# P1.net
KiCad netlist of a schematic drawn in Altium Designer
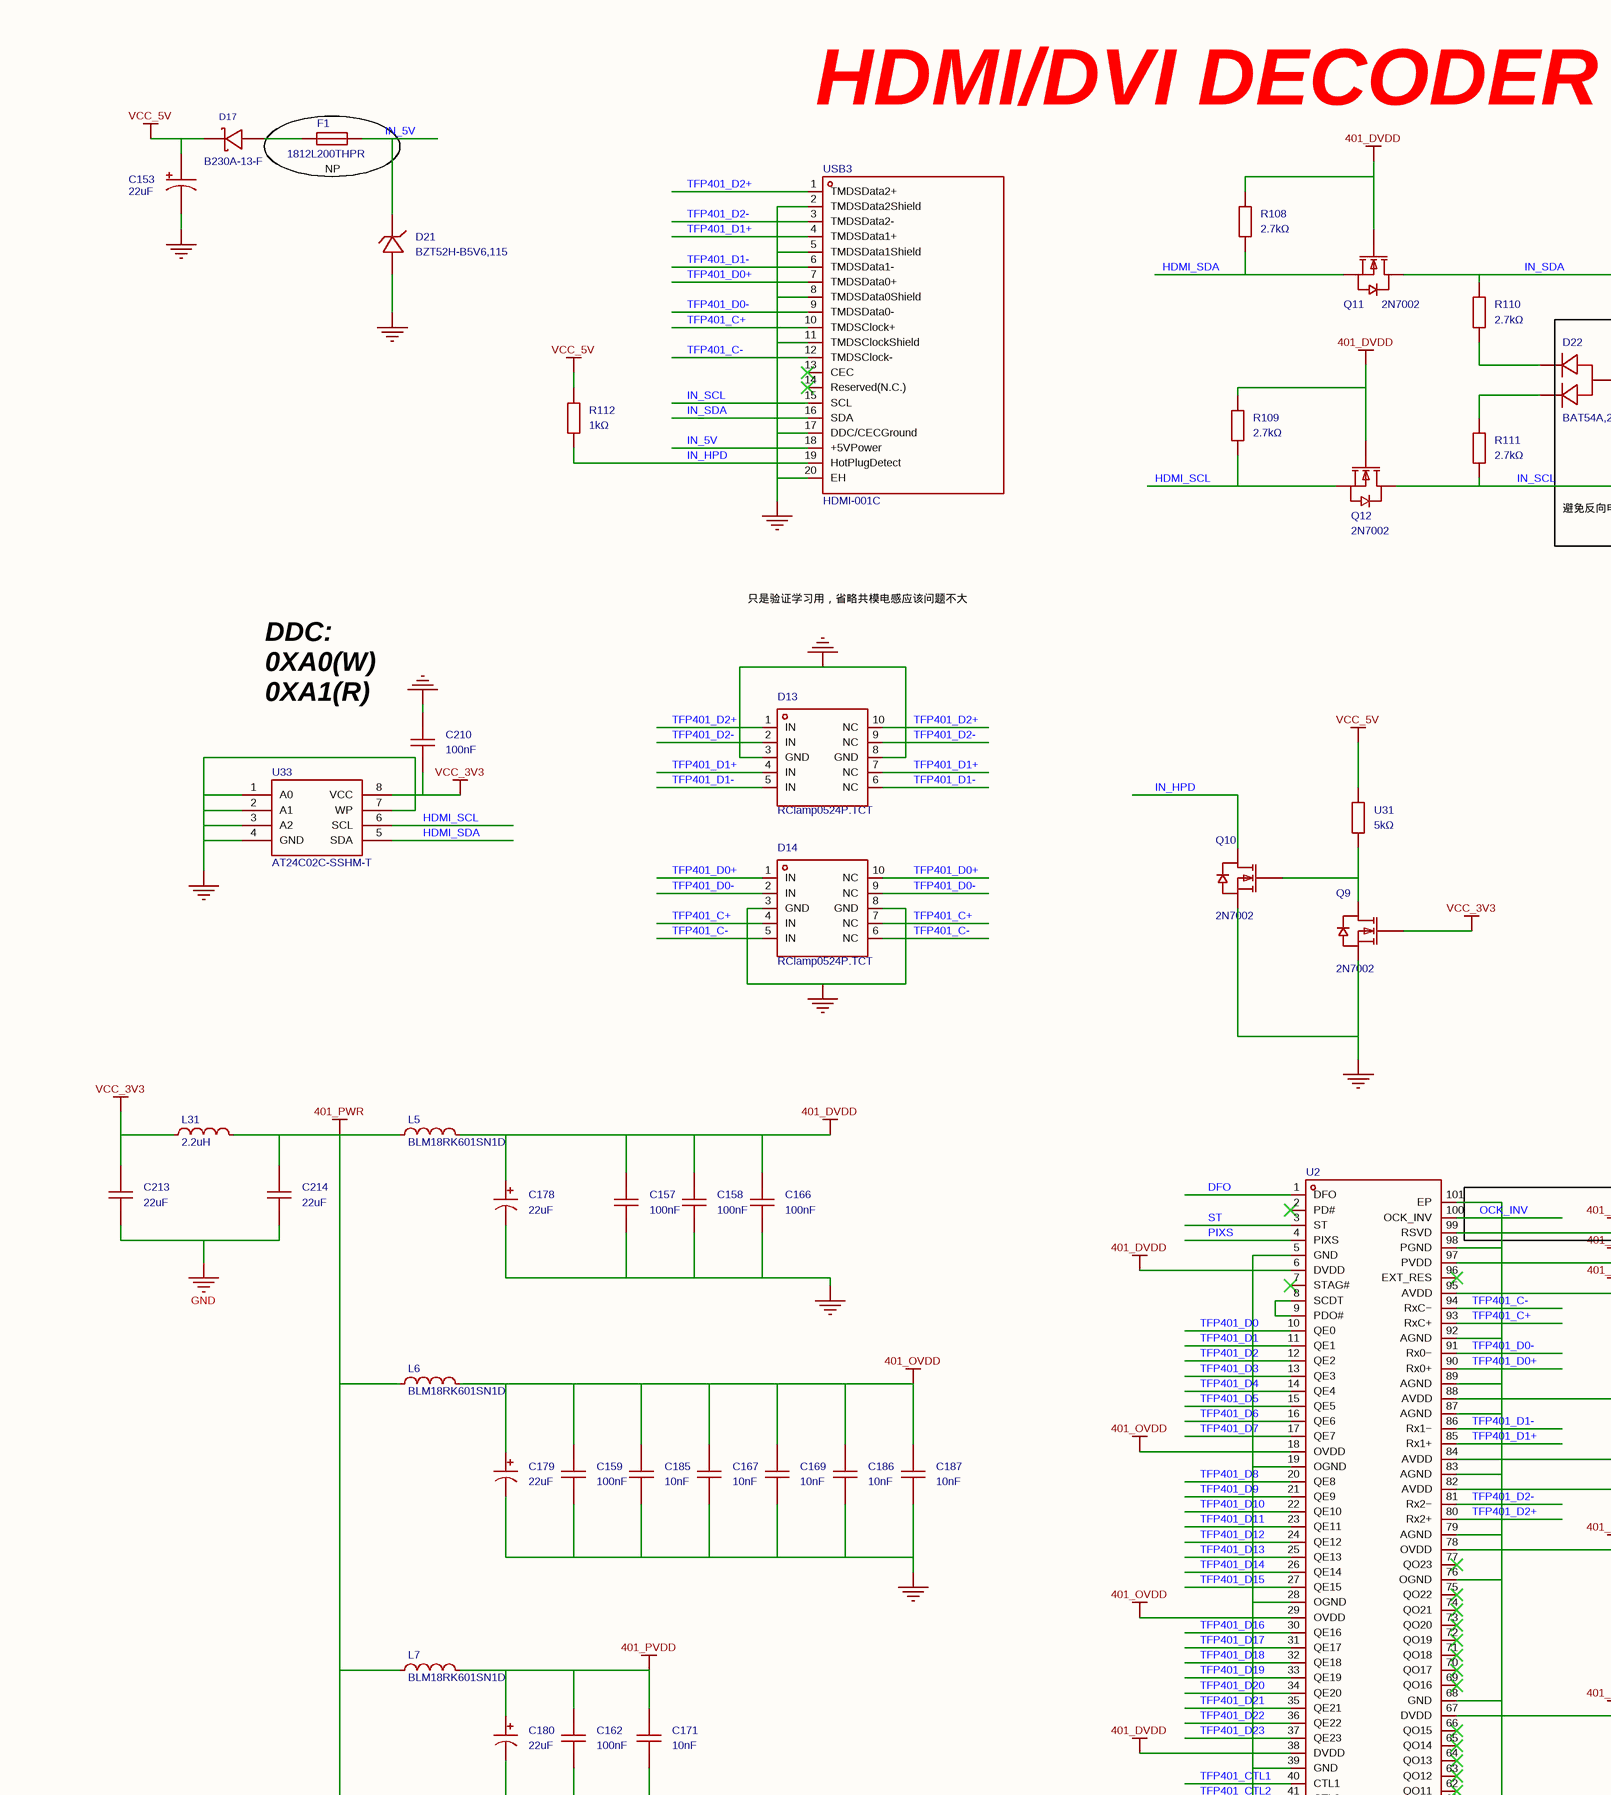
[diagram p0: P1.schdoc, top column 1 of 4]
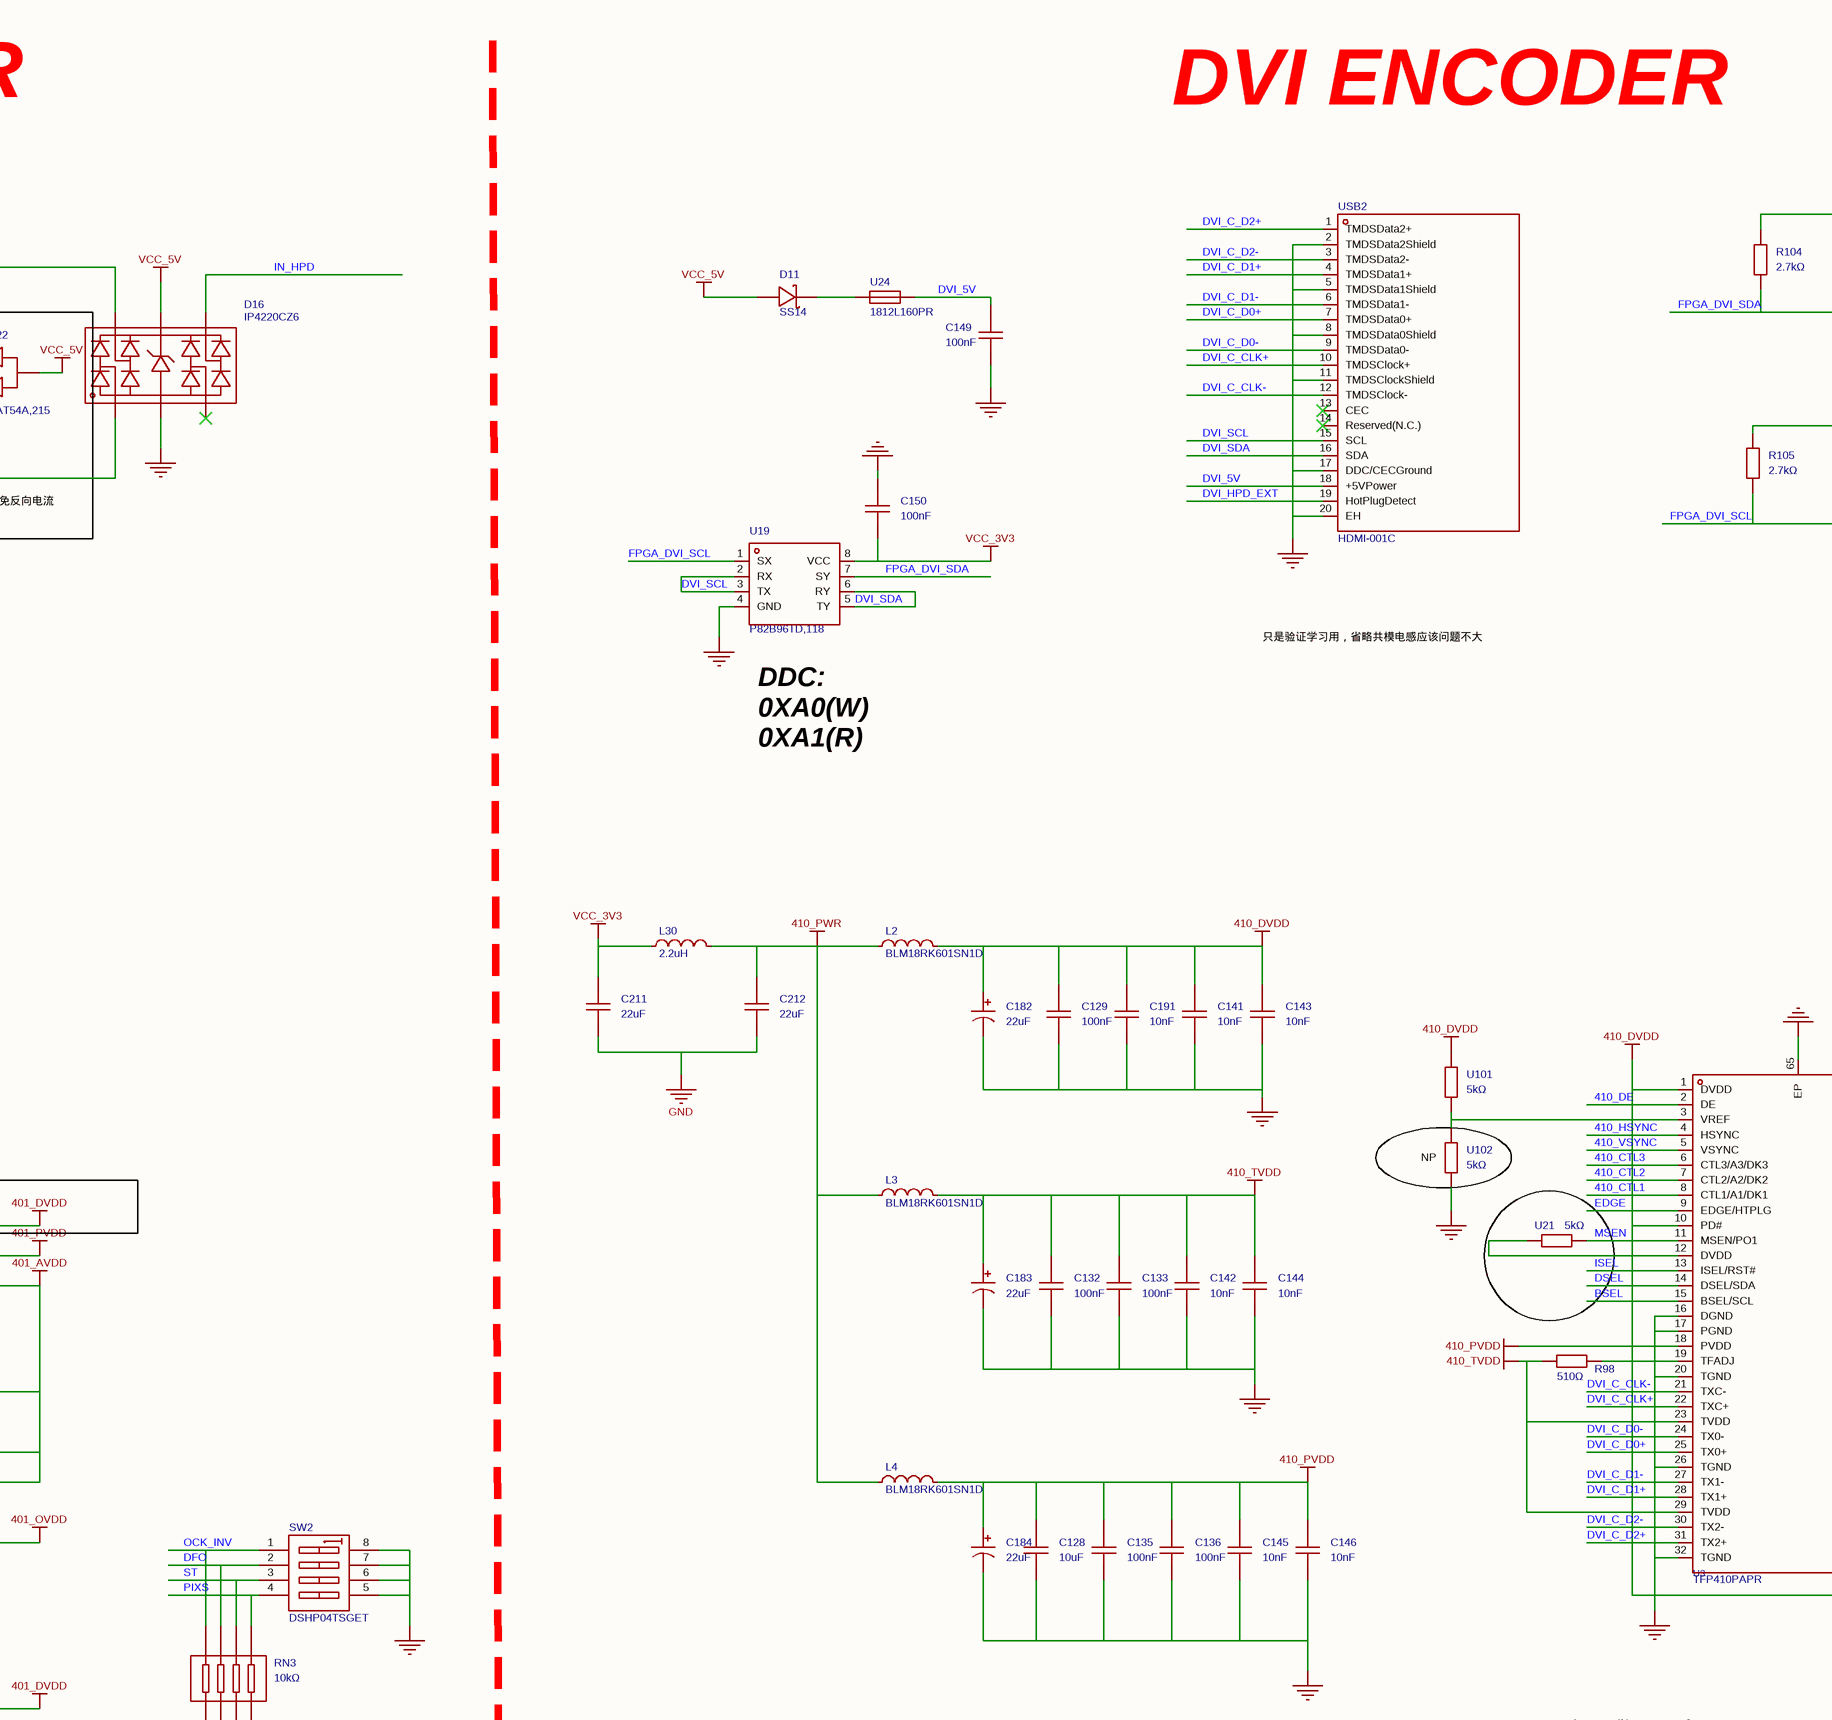
[diagram p1: P1.schdoc, top column 2 of 4]
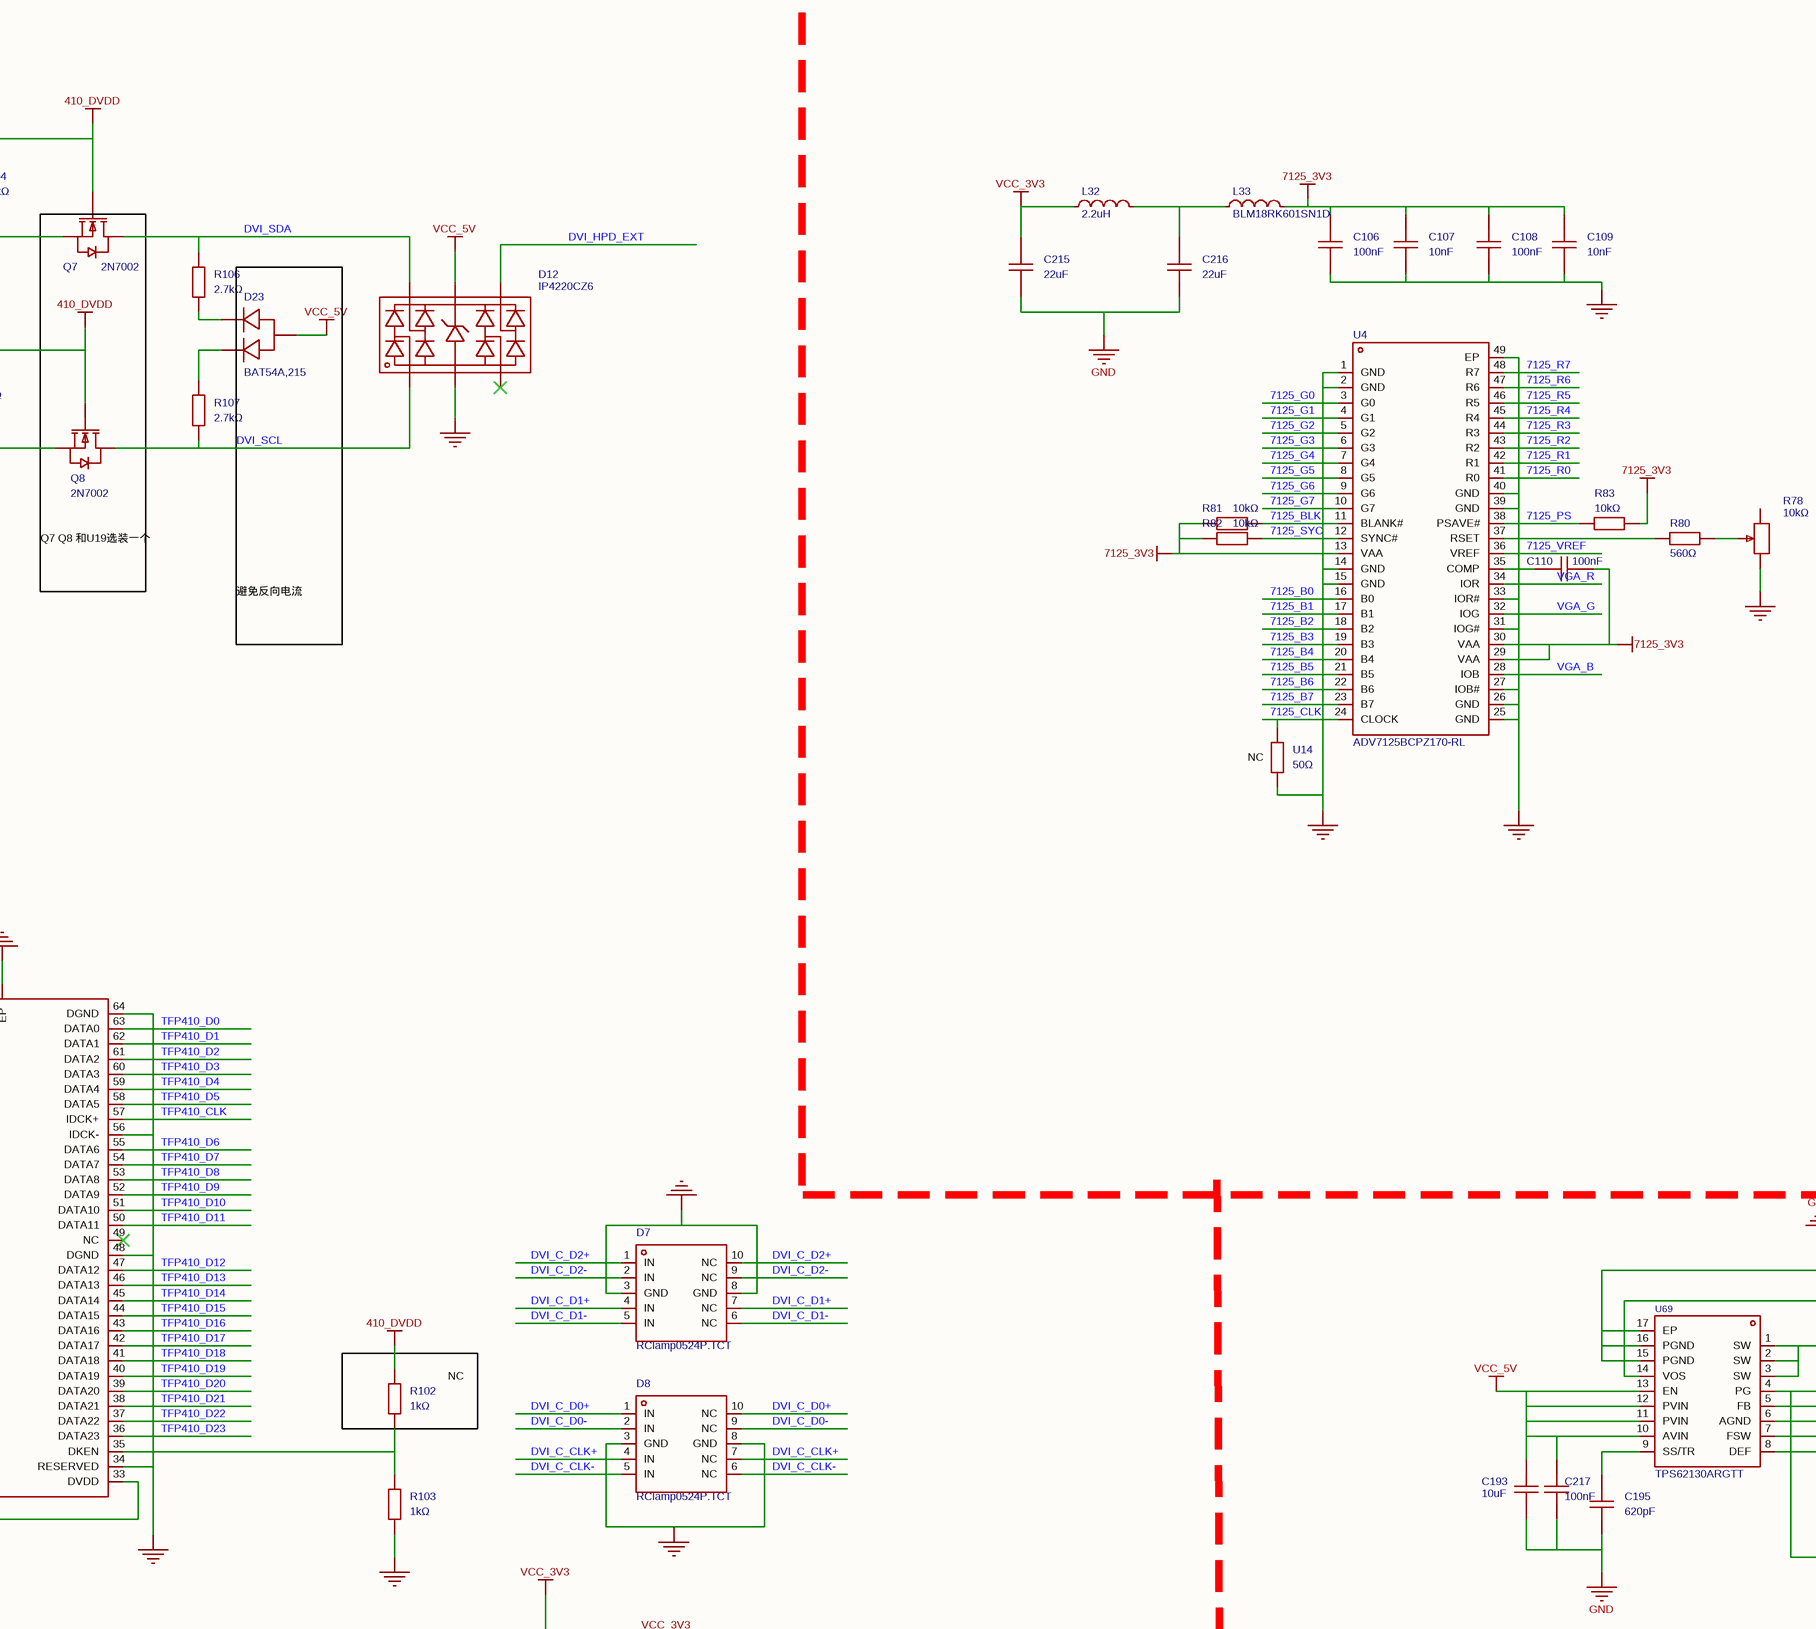
[diagram p2: P1.schdoc, top column 3 of 4]
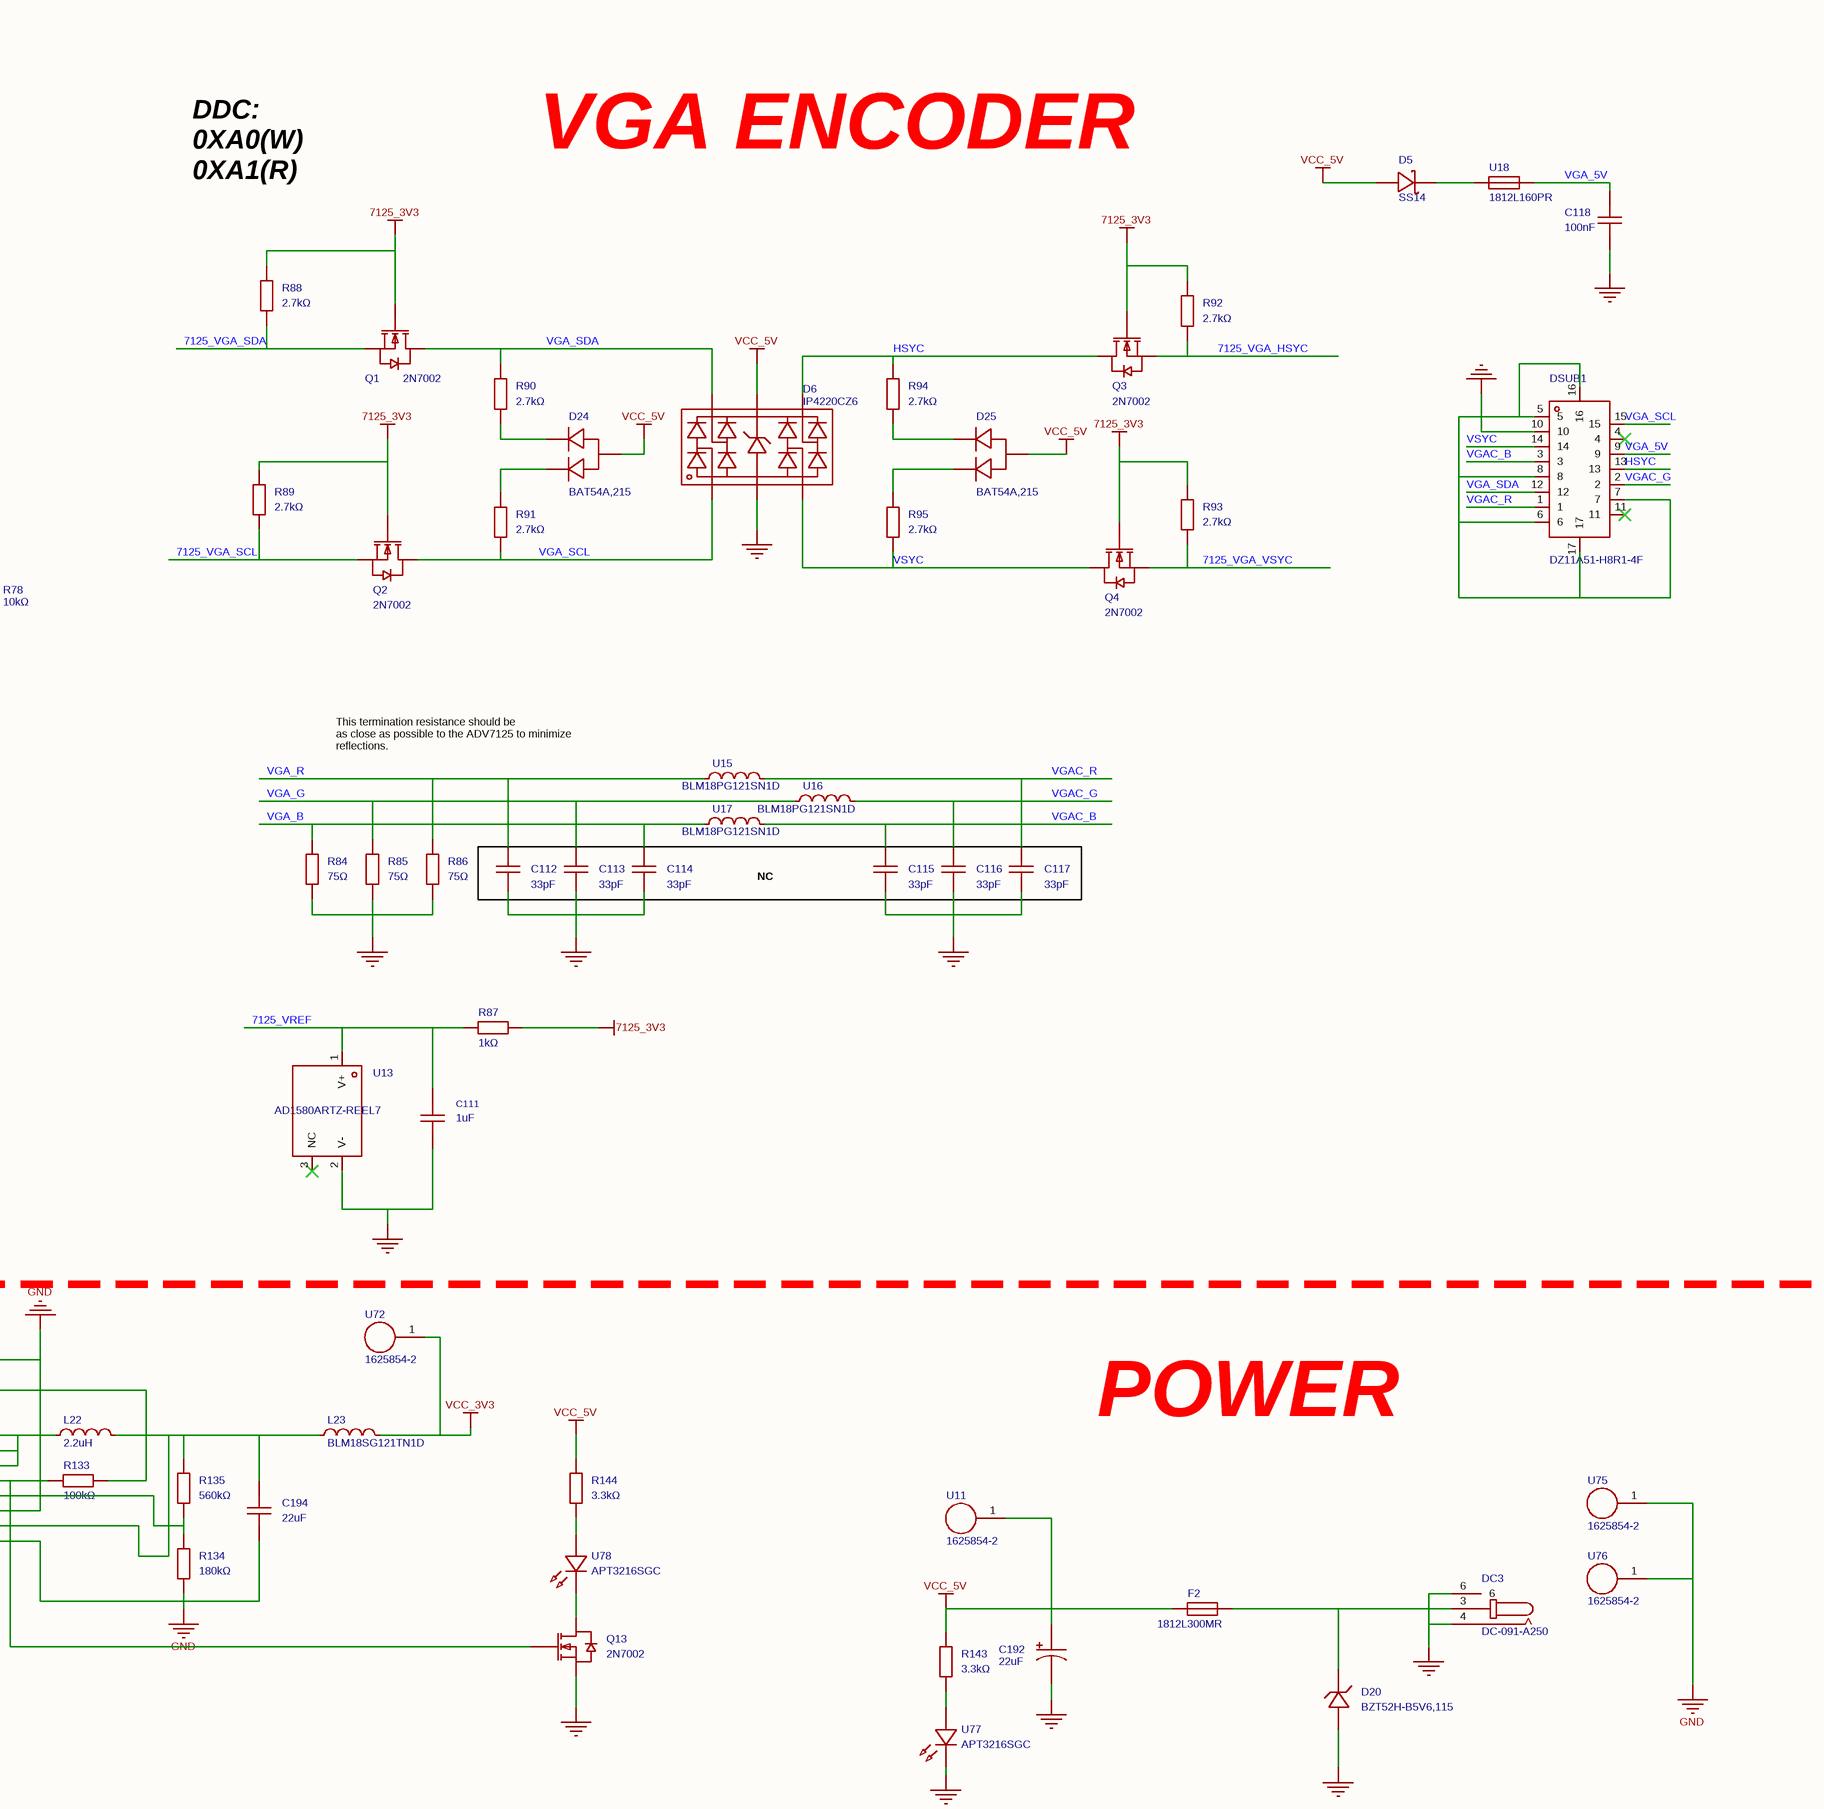
[diagram p3: P1.schdoc, top column 4 of 4]
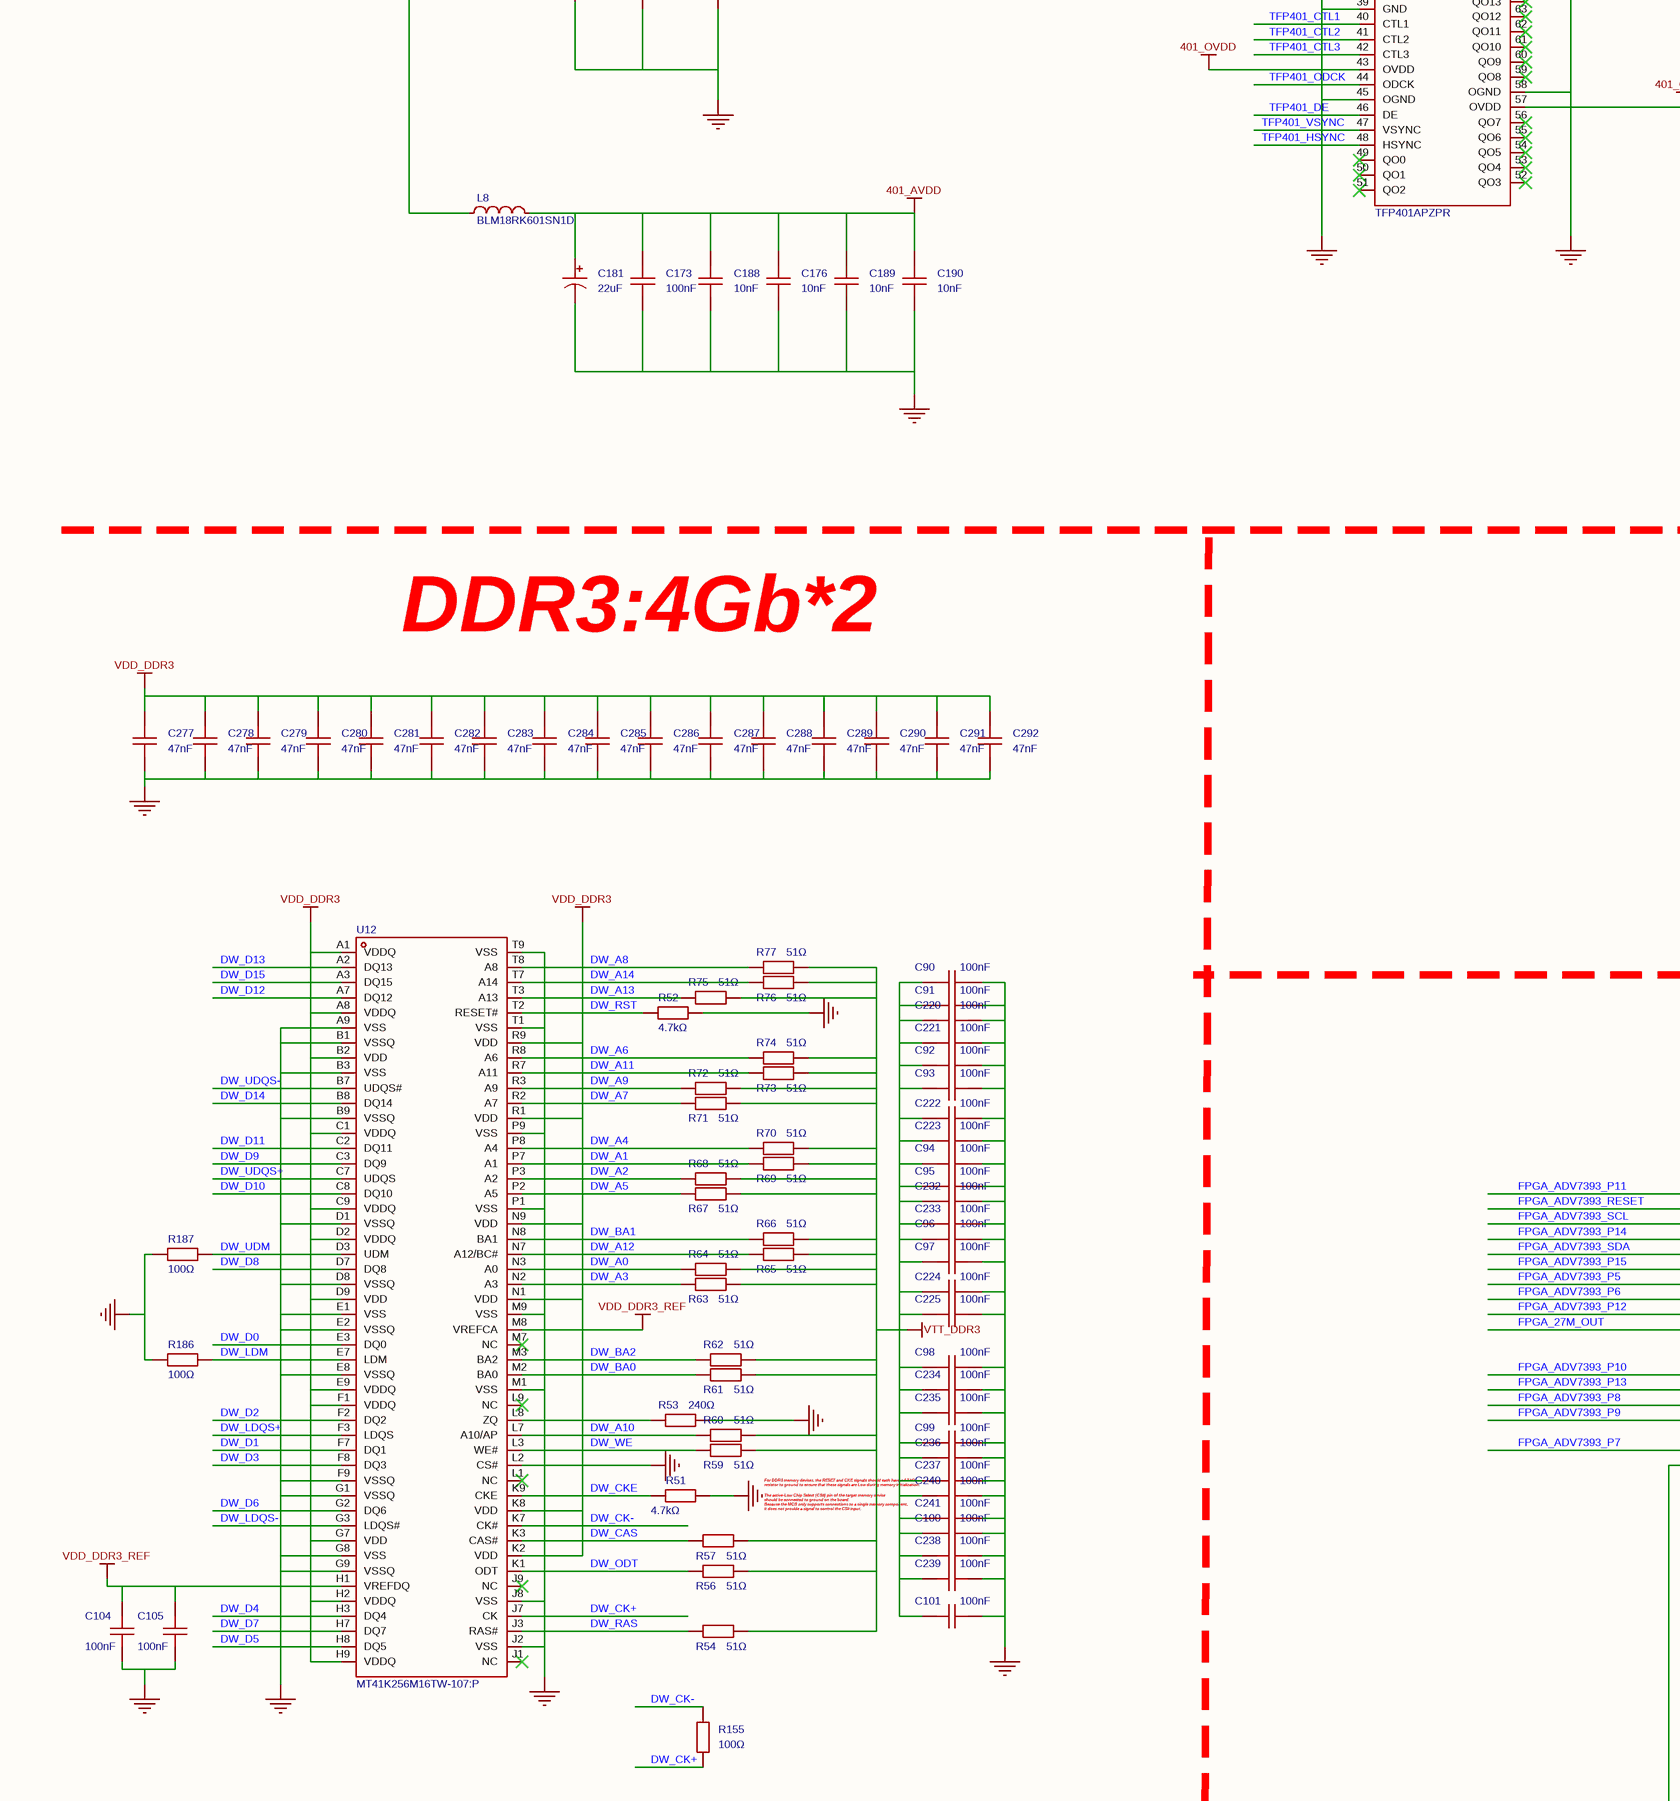
[diagram p4: P1.schdoc, centre column 1 of 4]
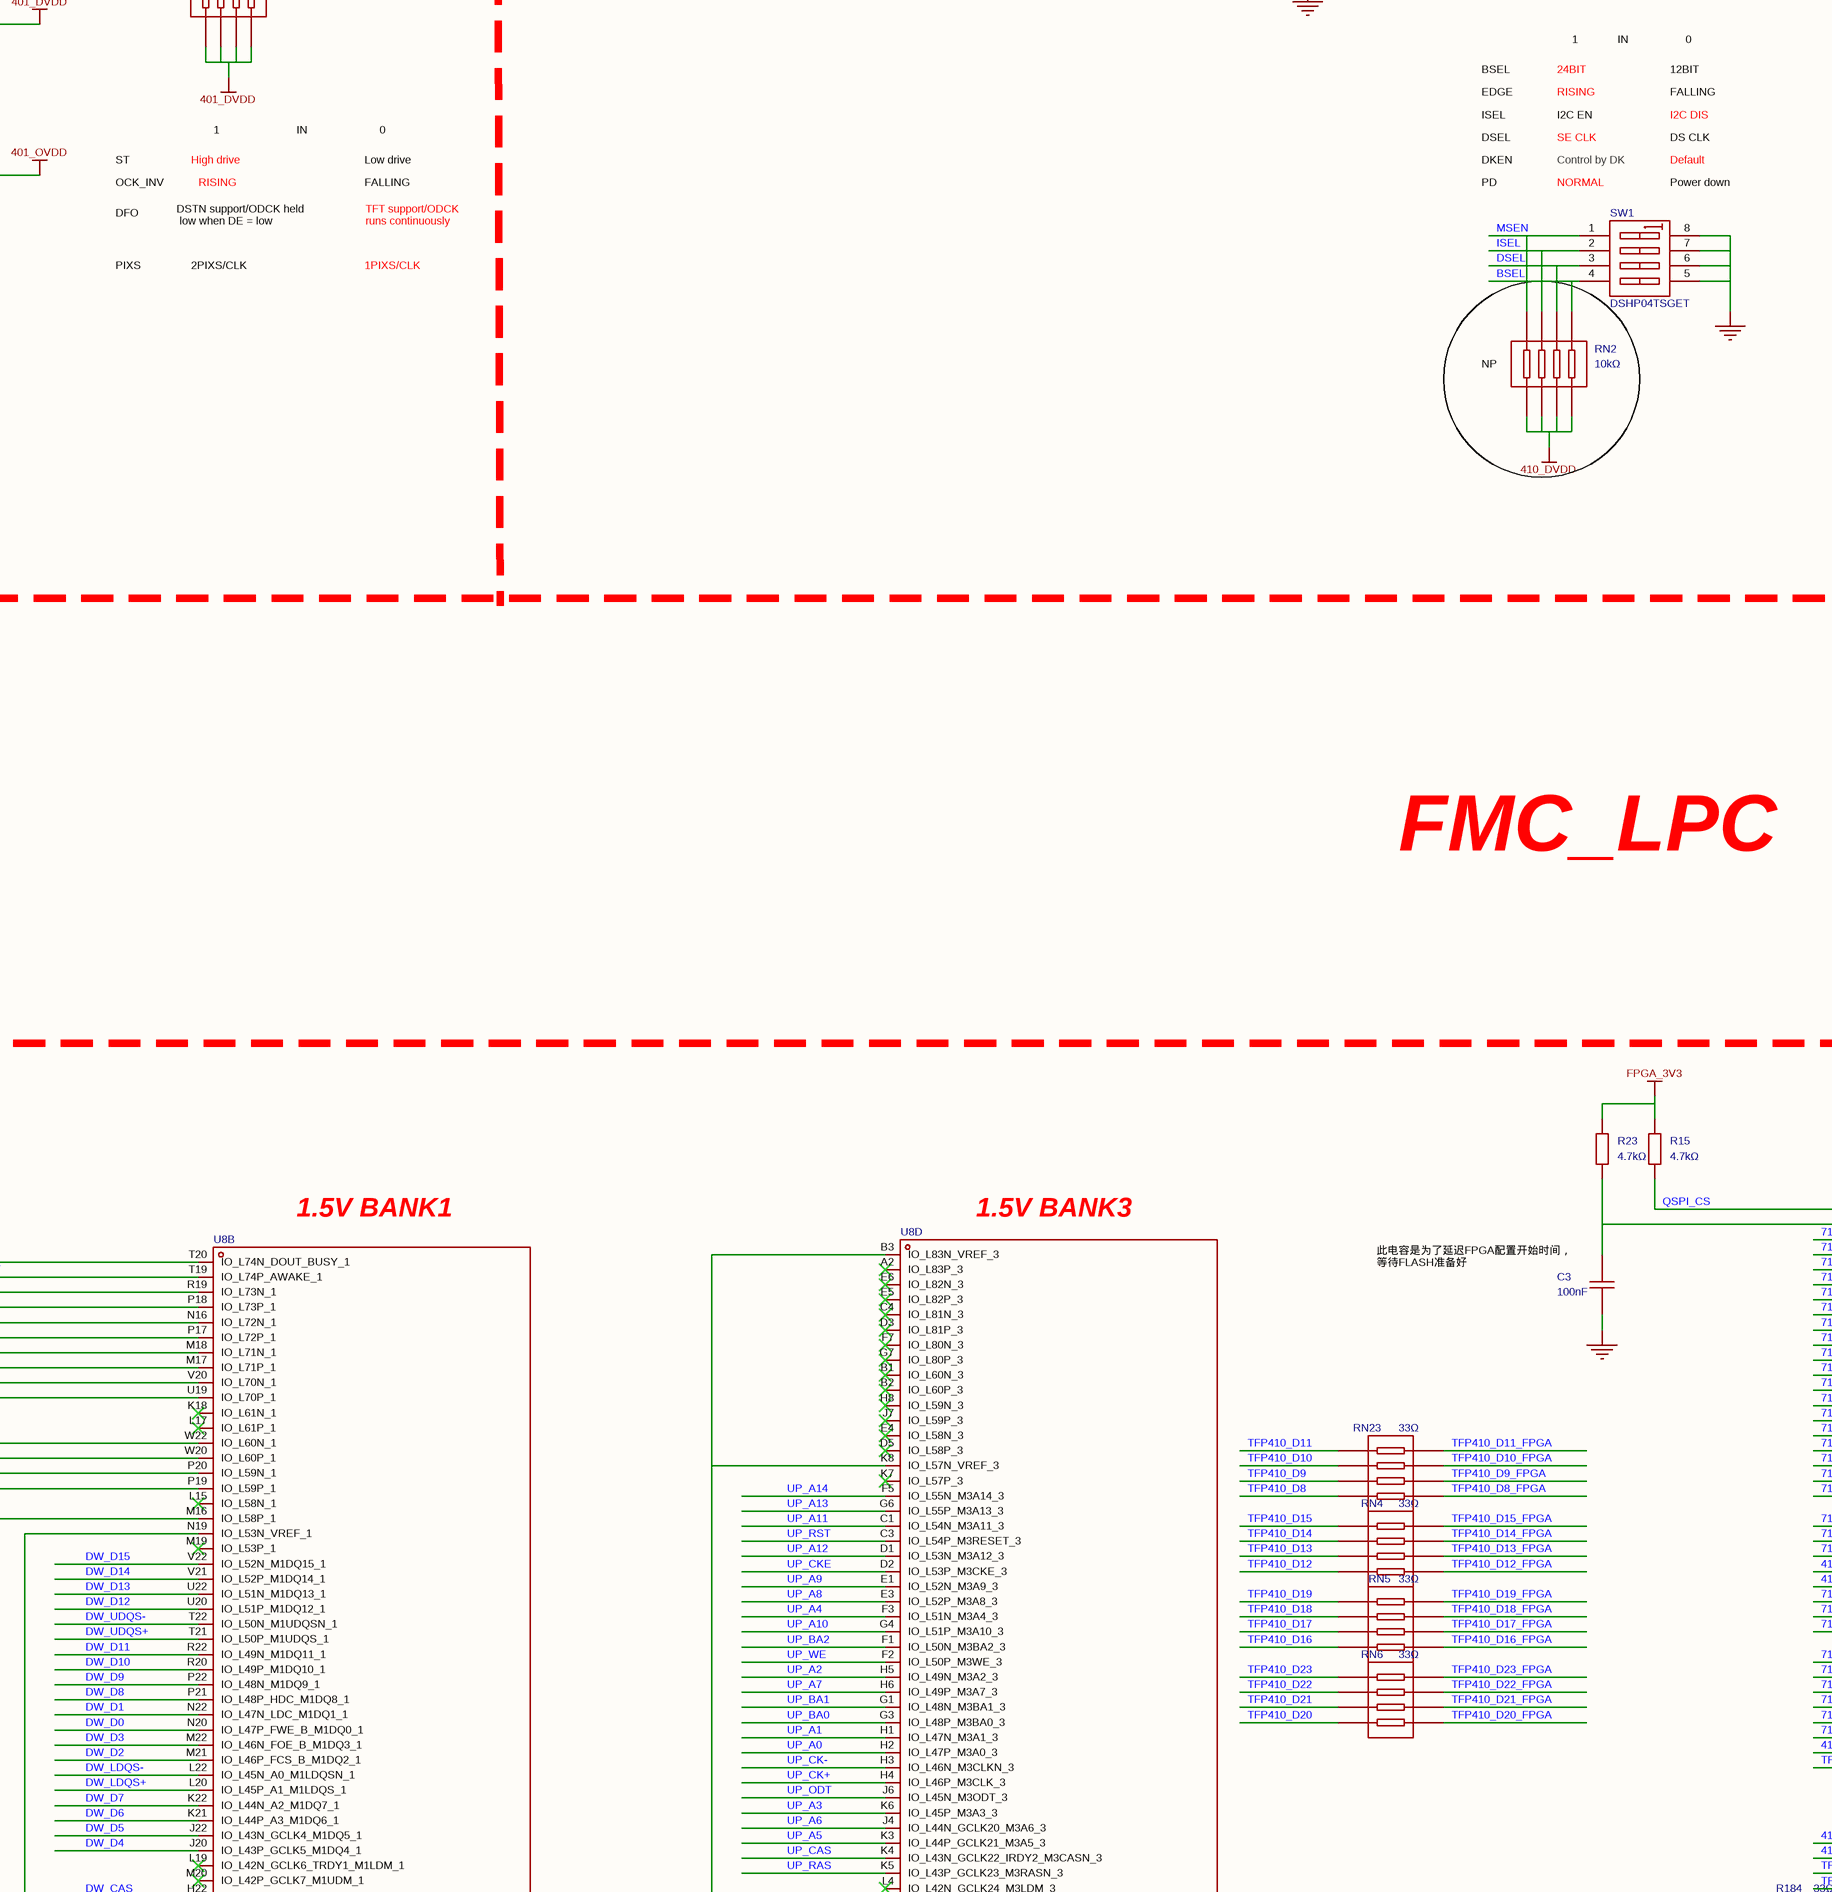
[diagram p5: P1.schdoc, centre column 2 of 4]
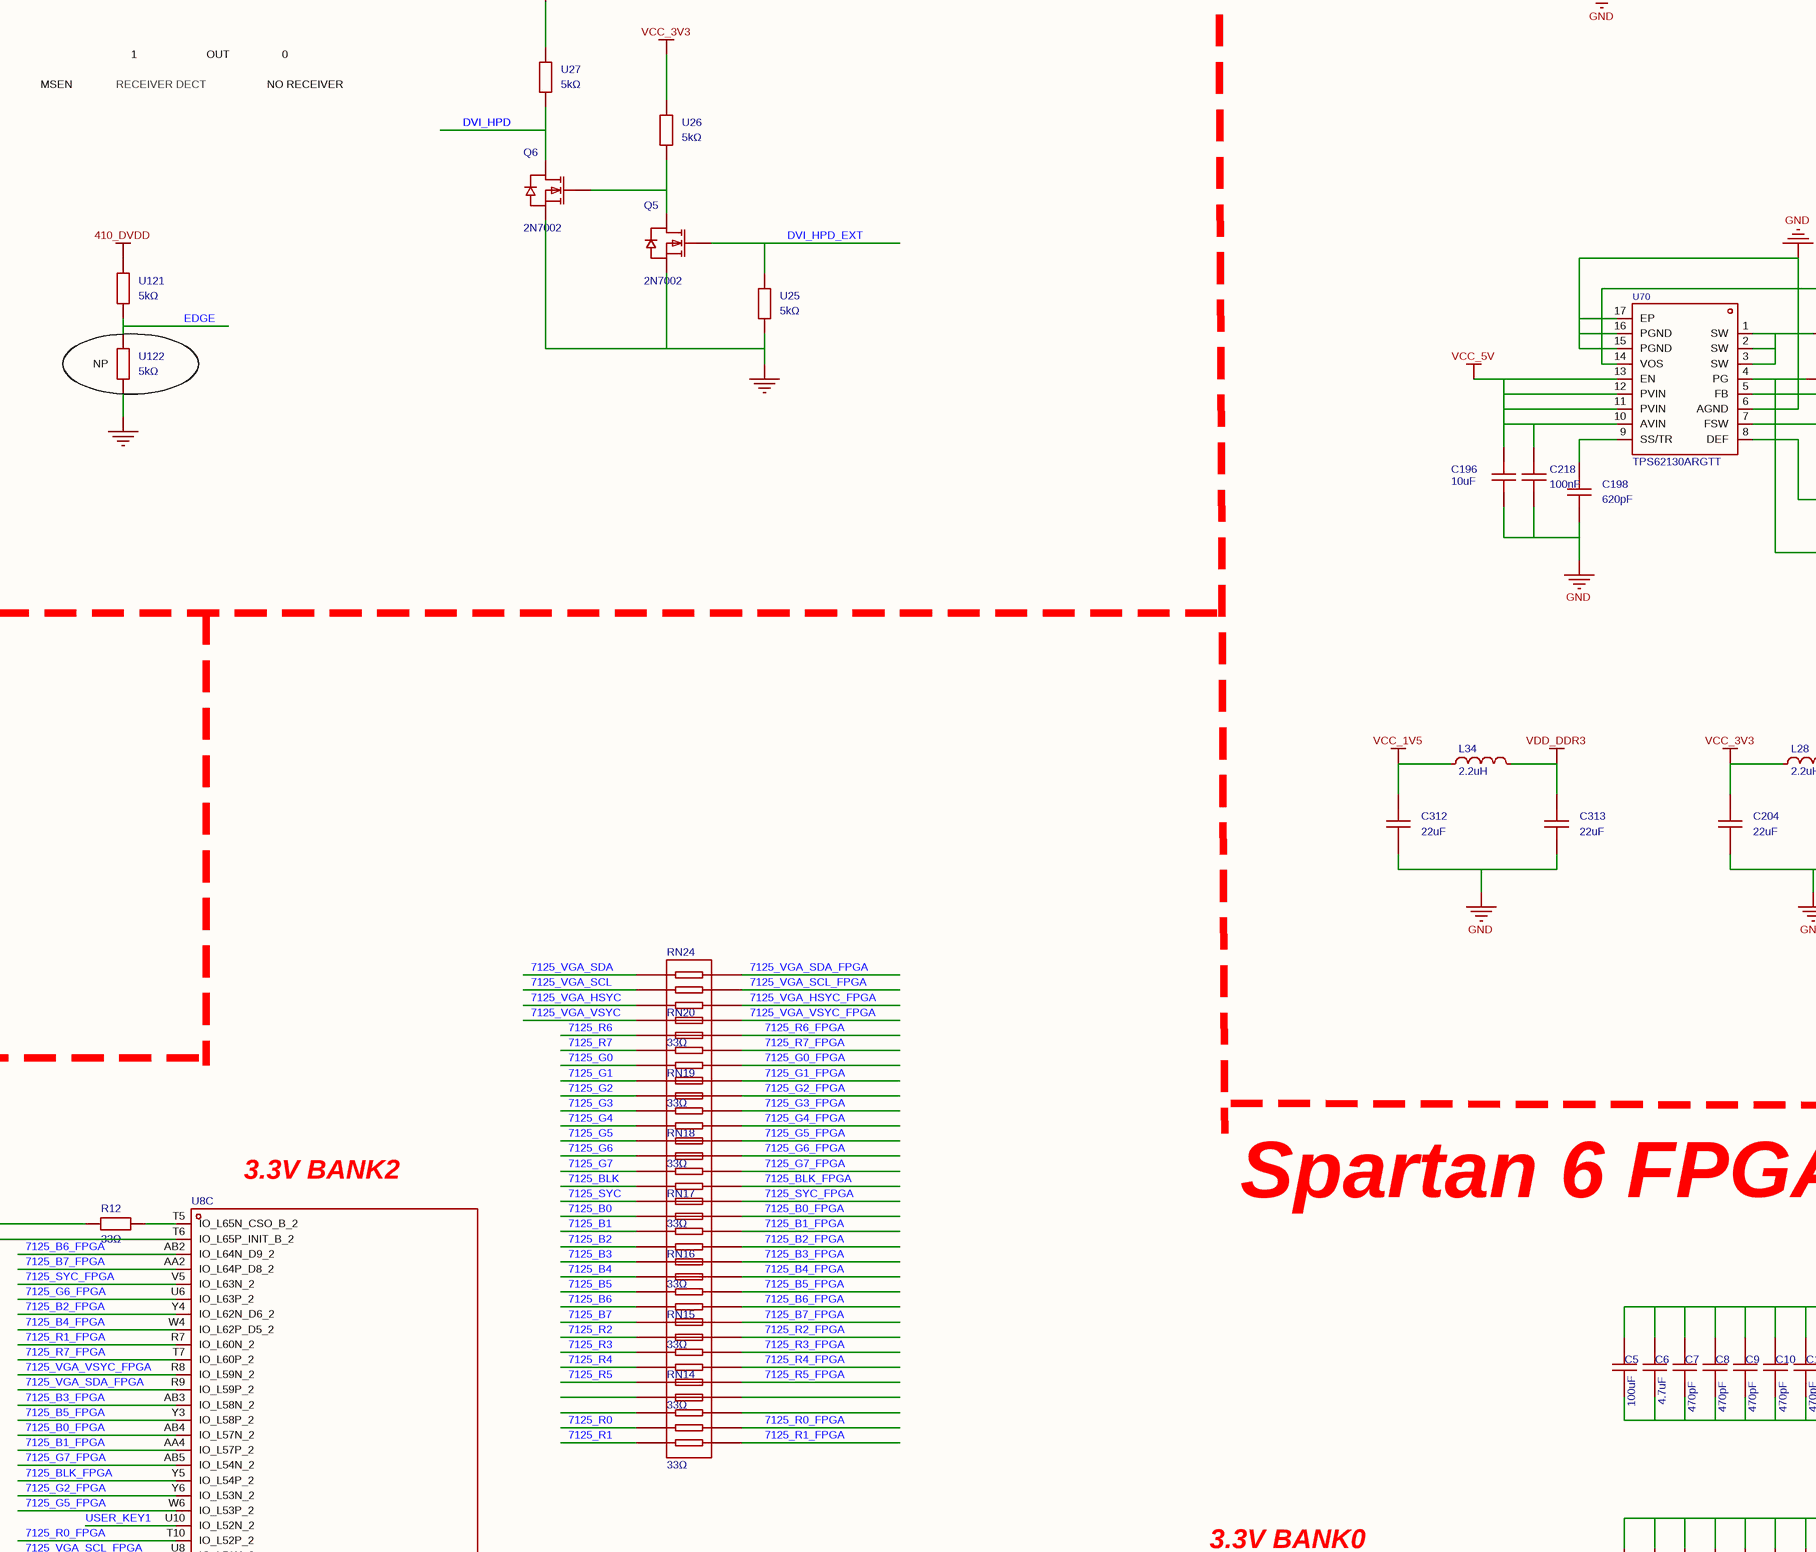
[diagram p6: P1.schdoc, centre column 3 of 4]
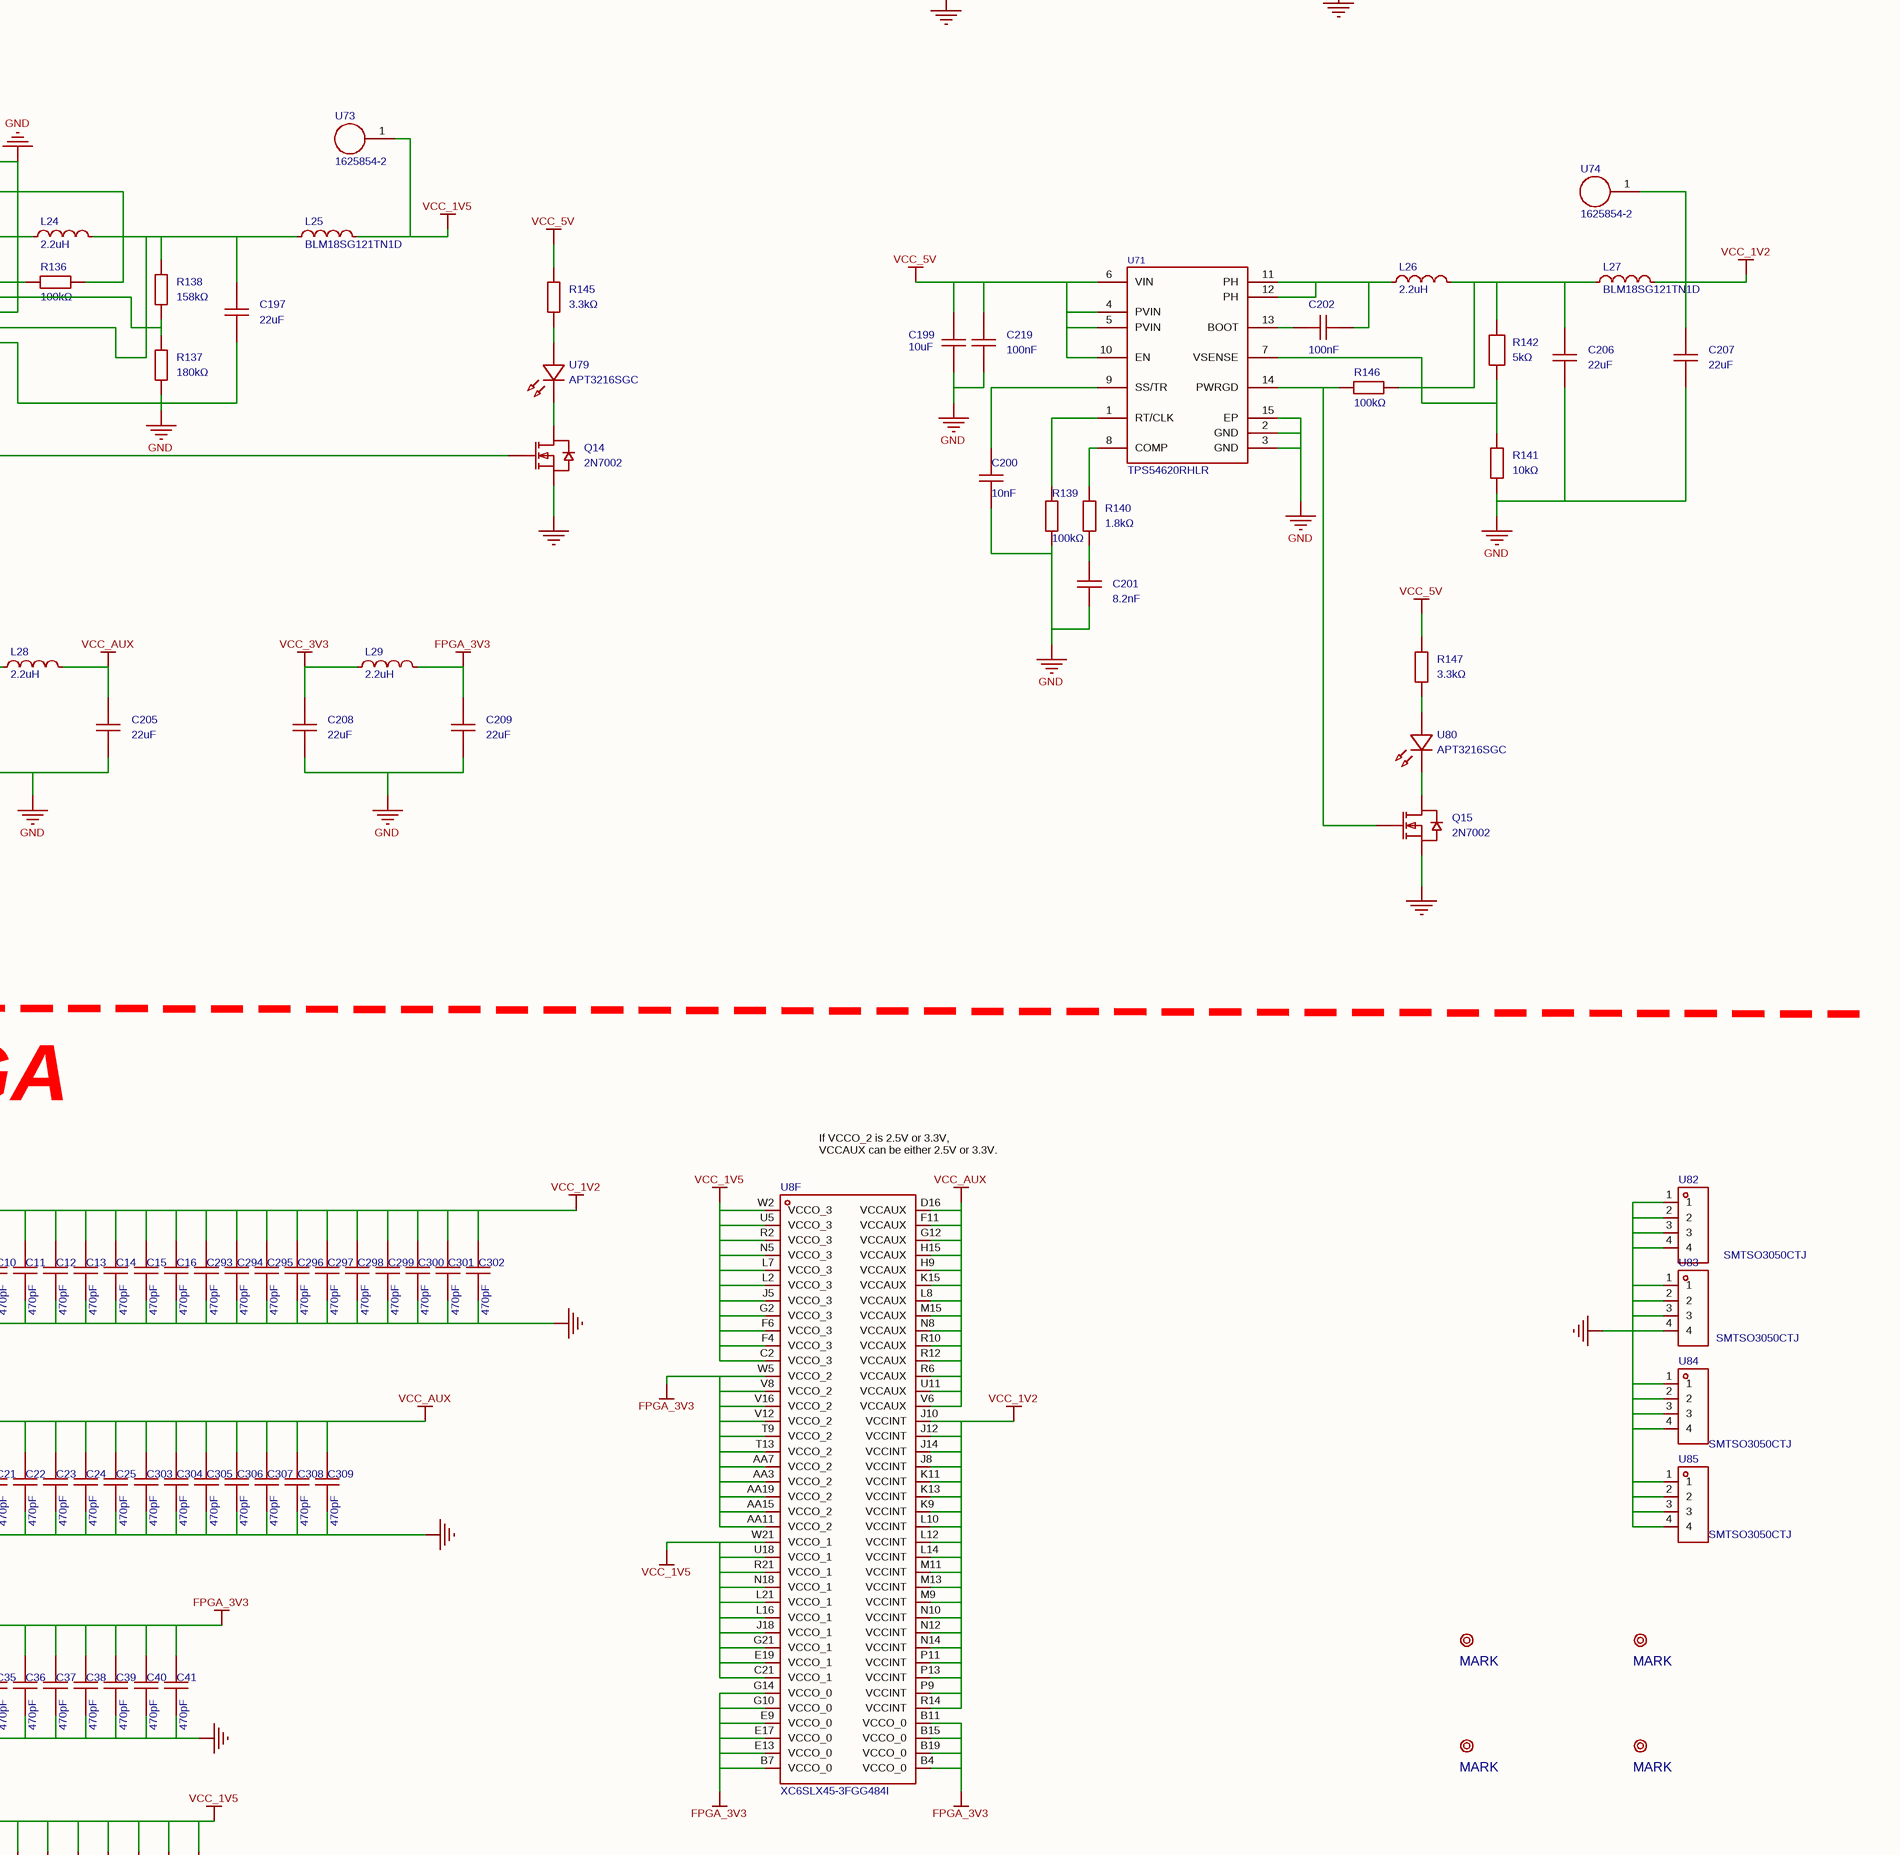
[diagram p7: P1.schdoc, centre column 4 of 4]
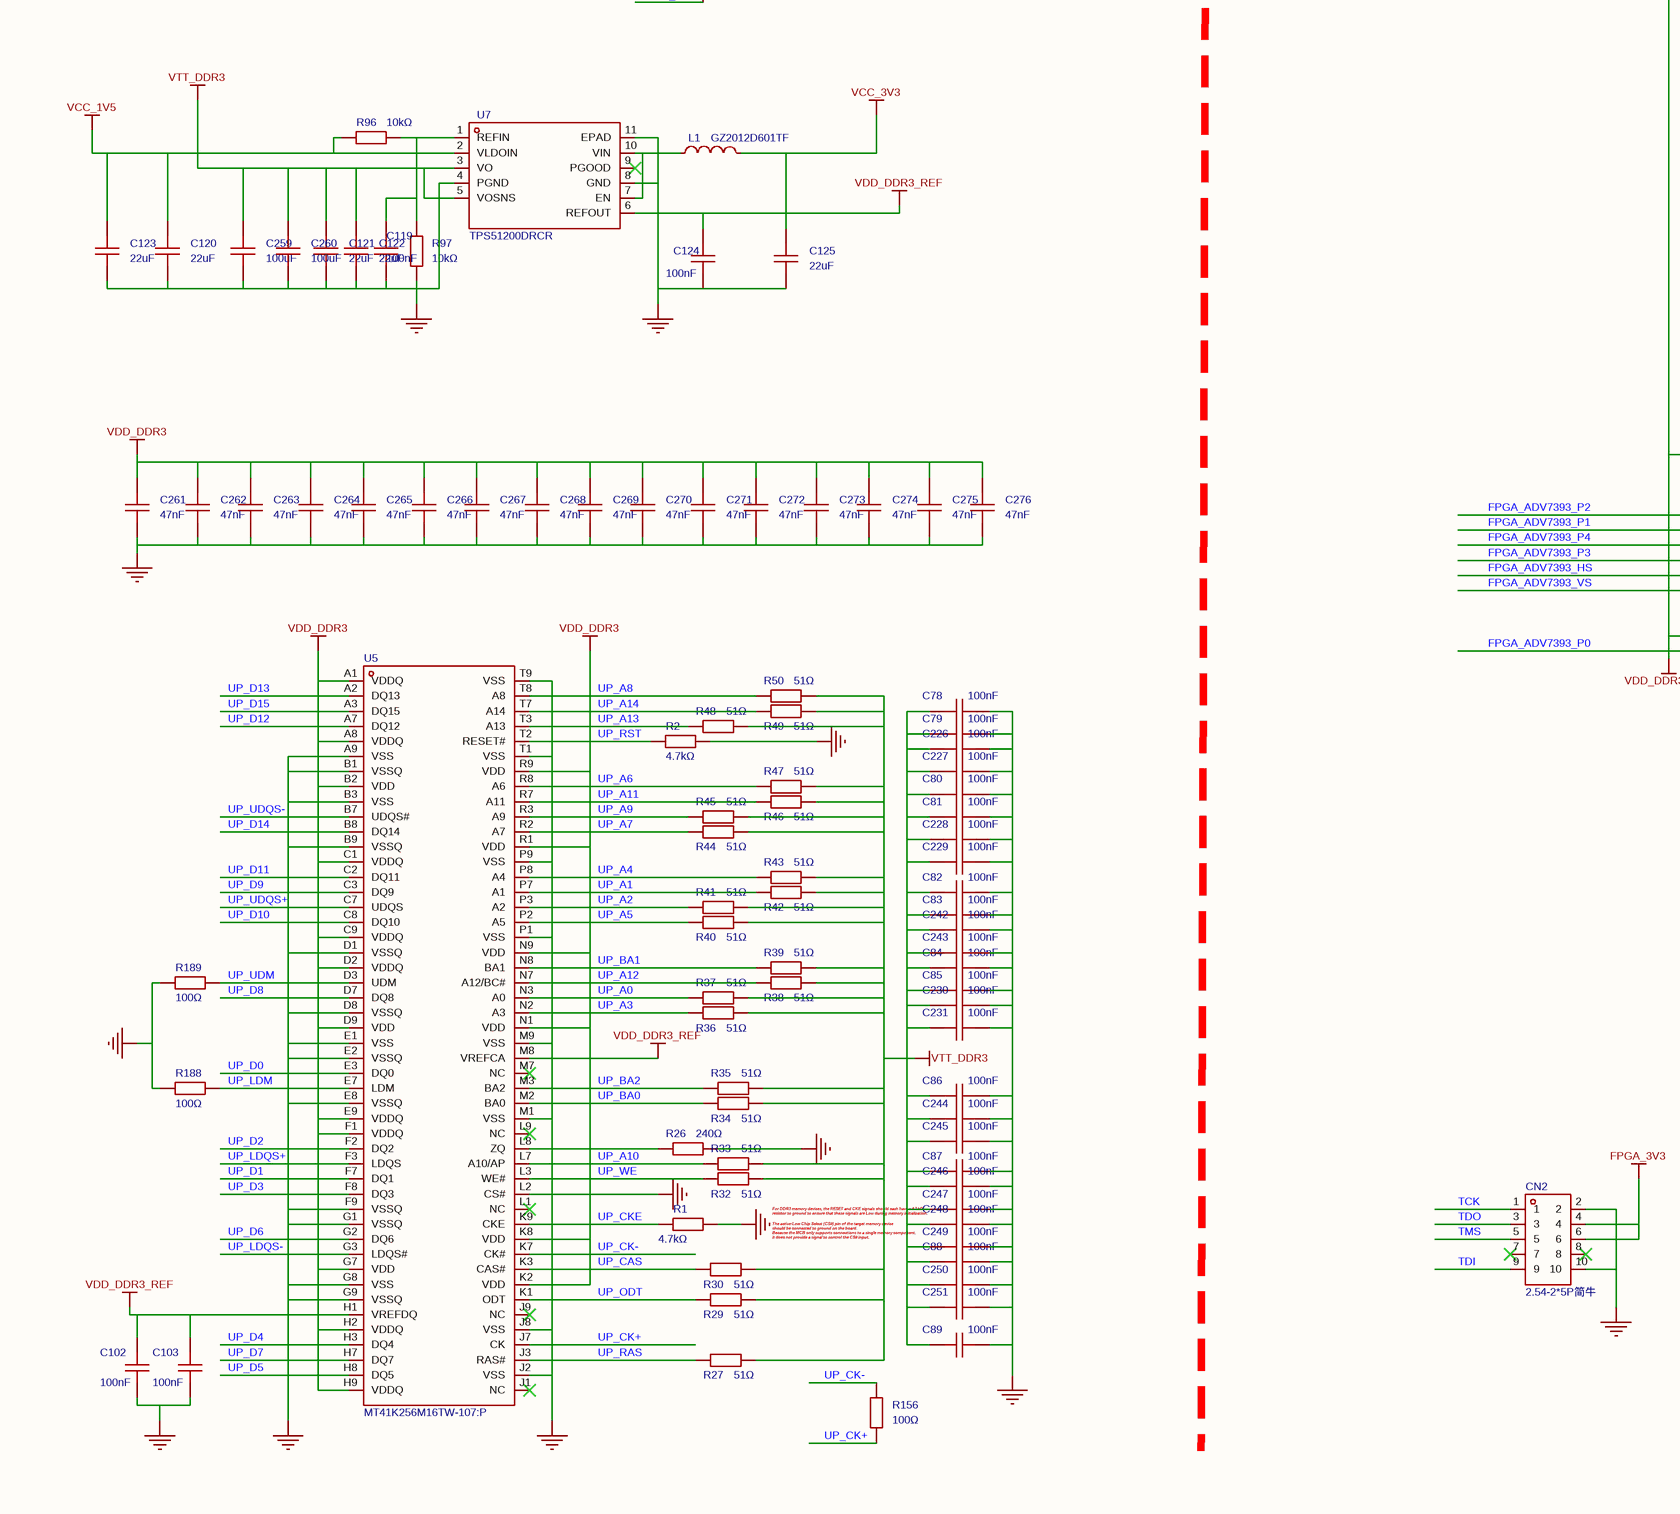
[diagram p8: P1.schdoc, bottom column 1 of 4]
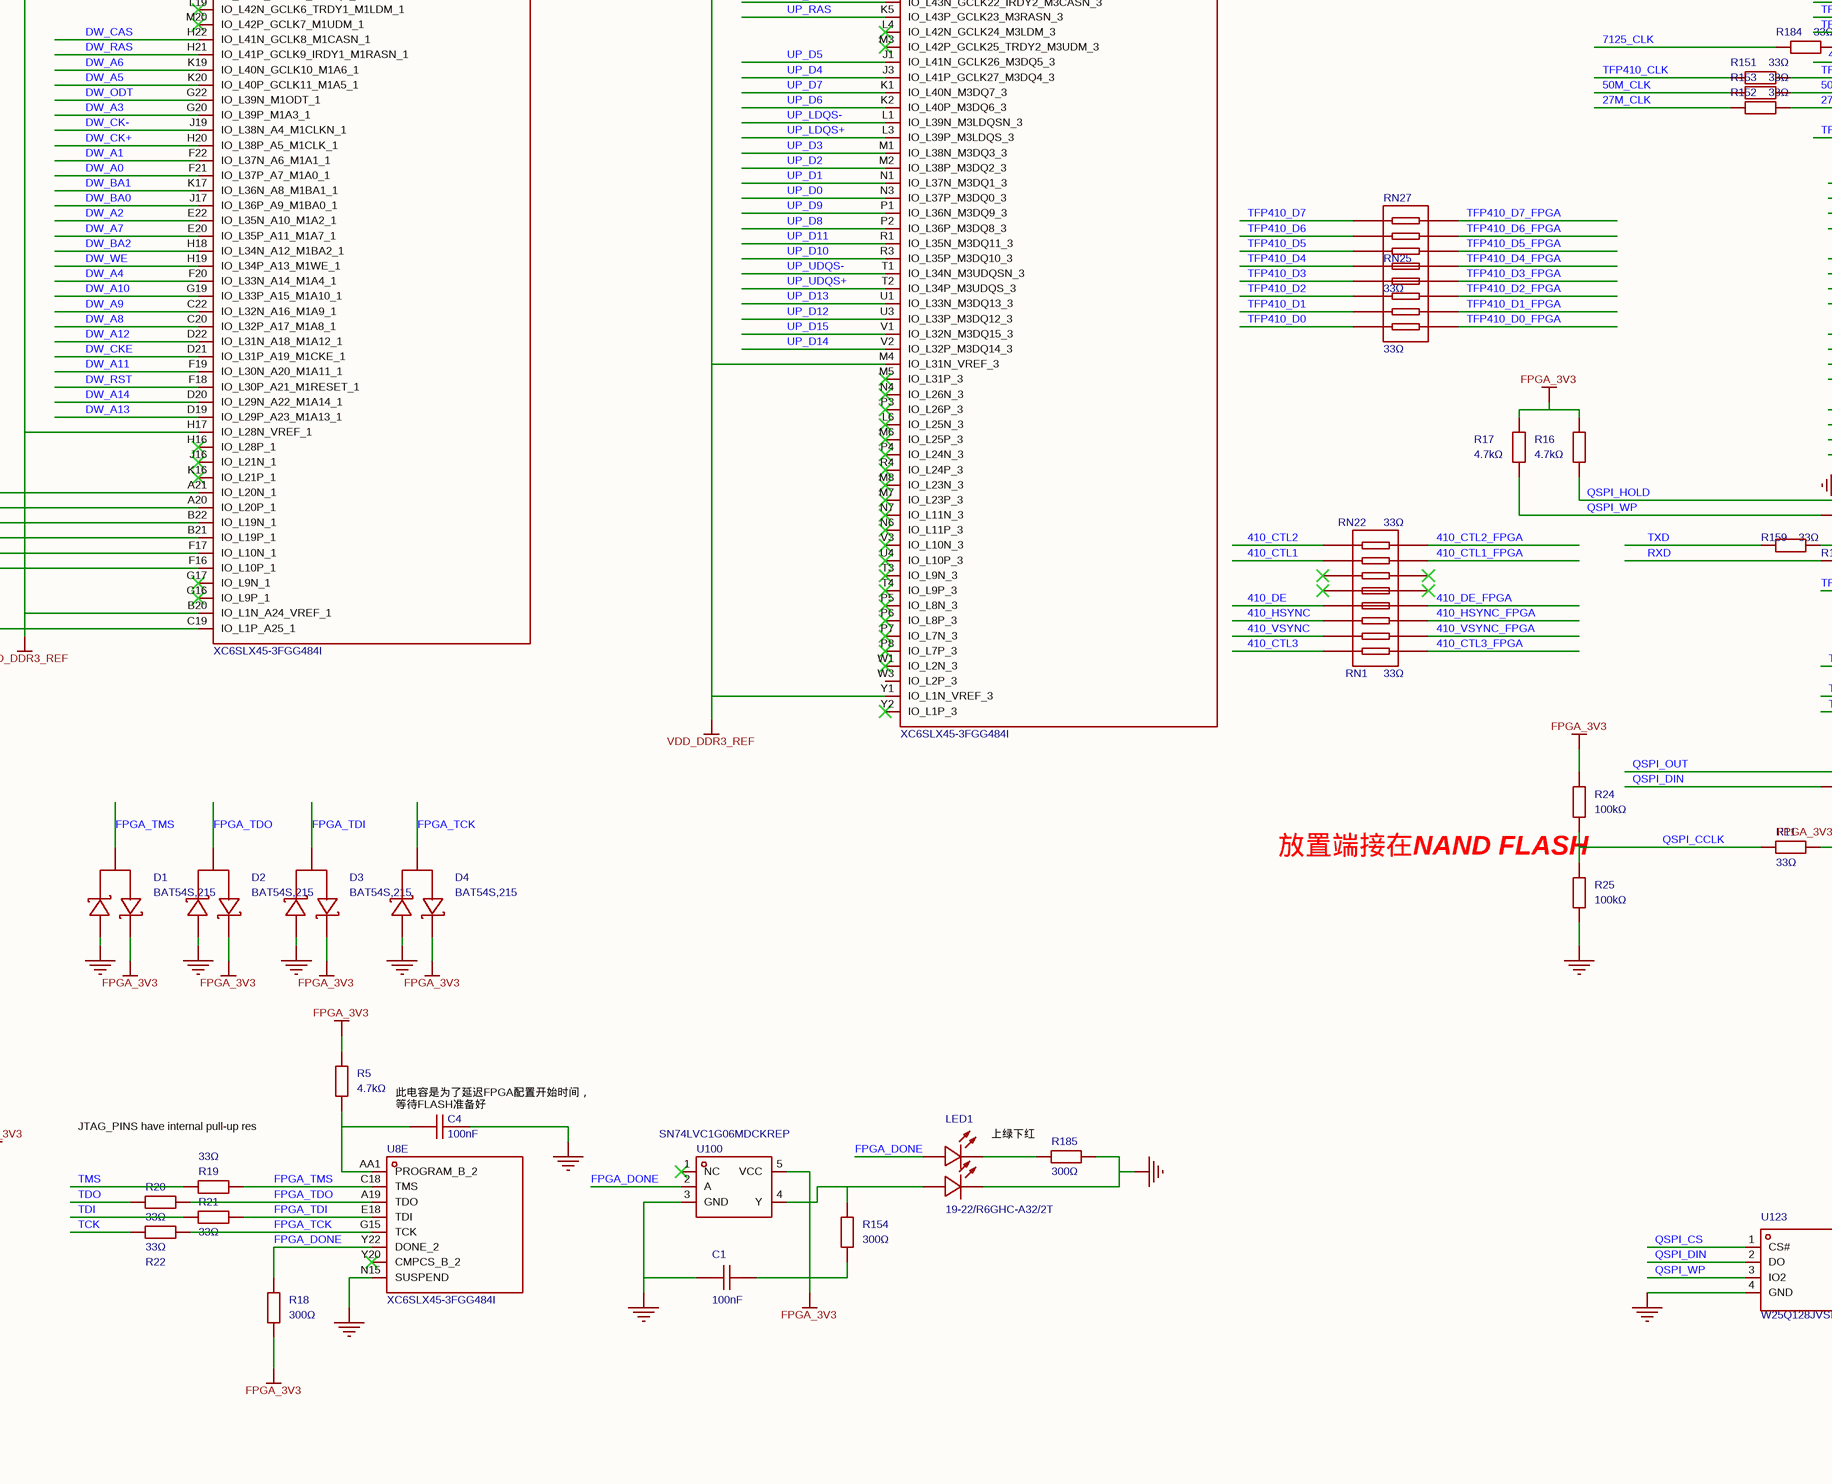
[diagram p9: P1.schdoc, bottom column 2 of 4]
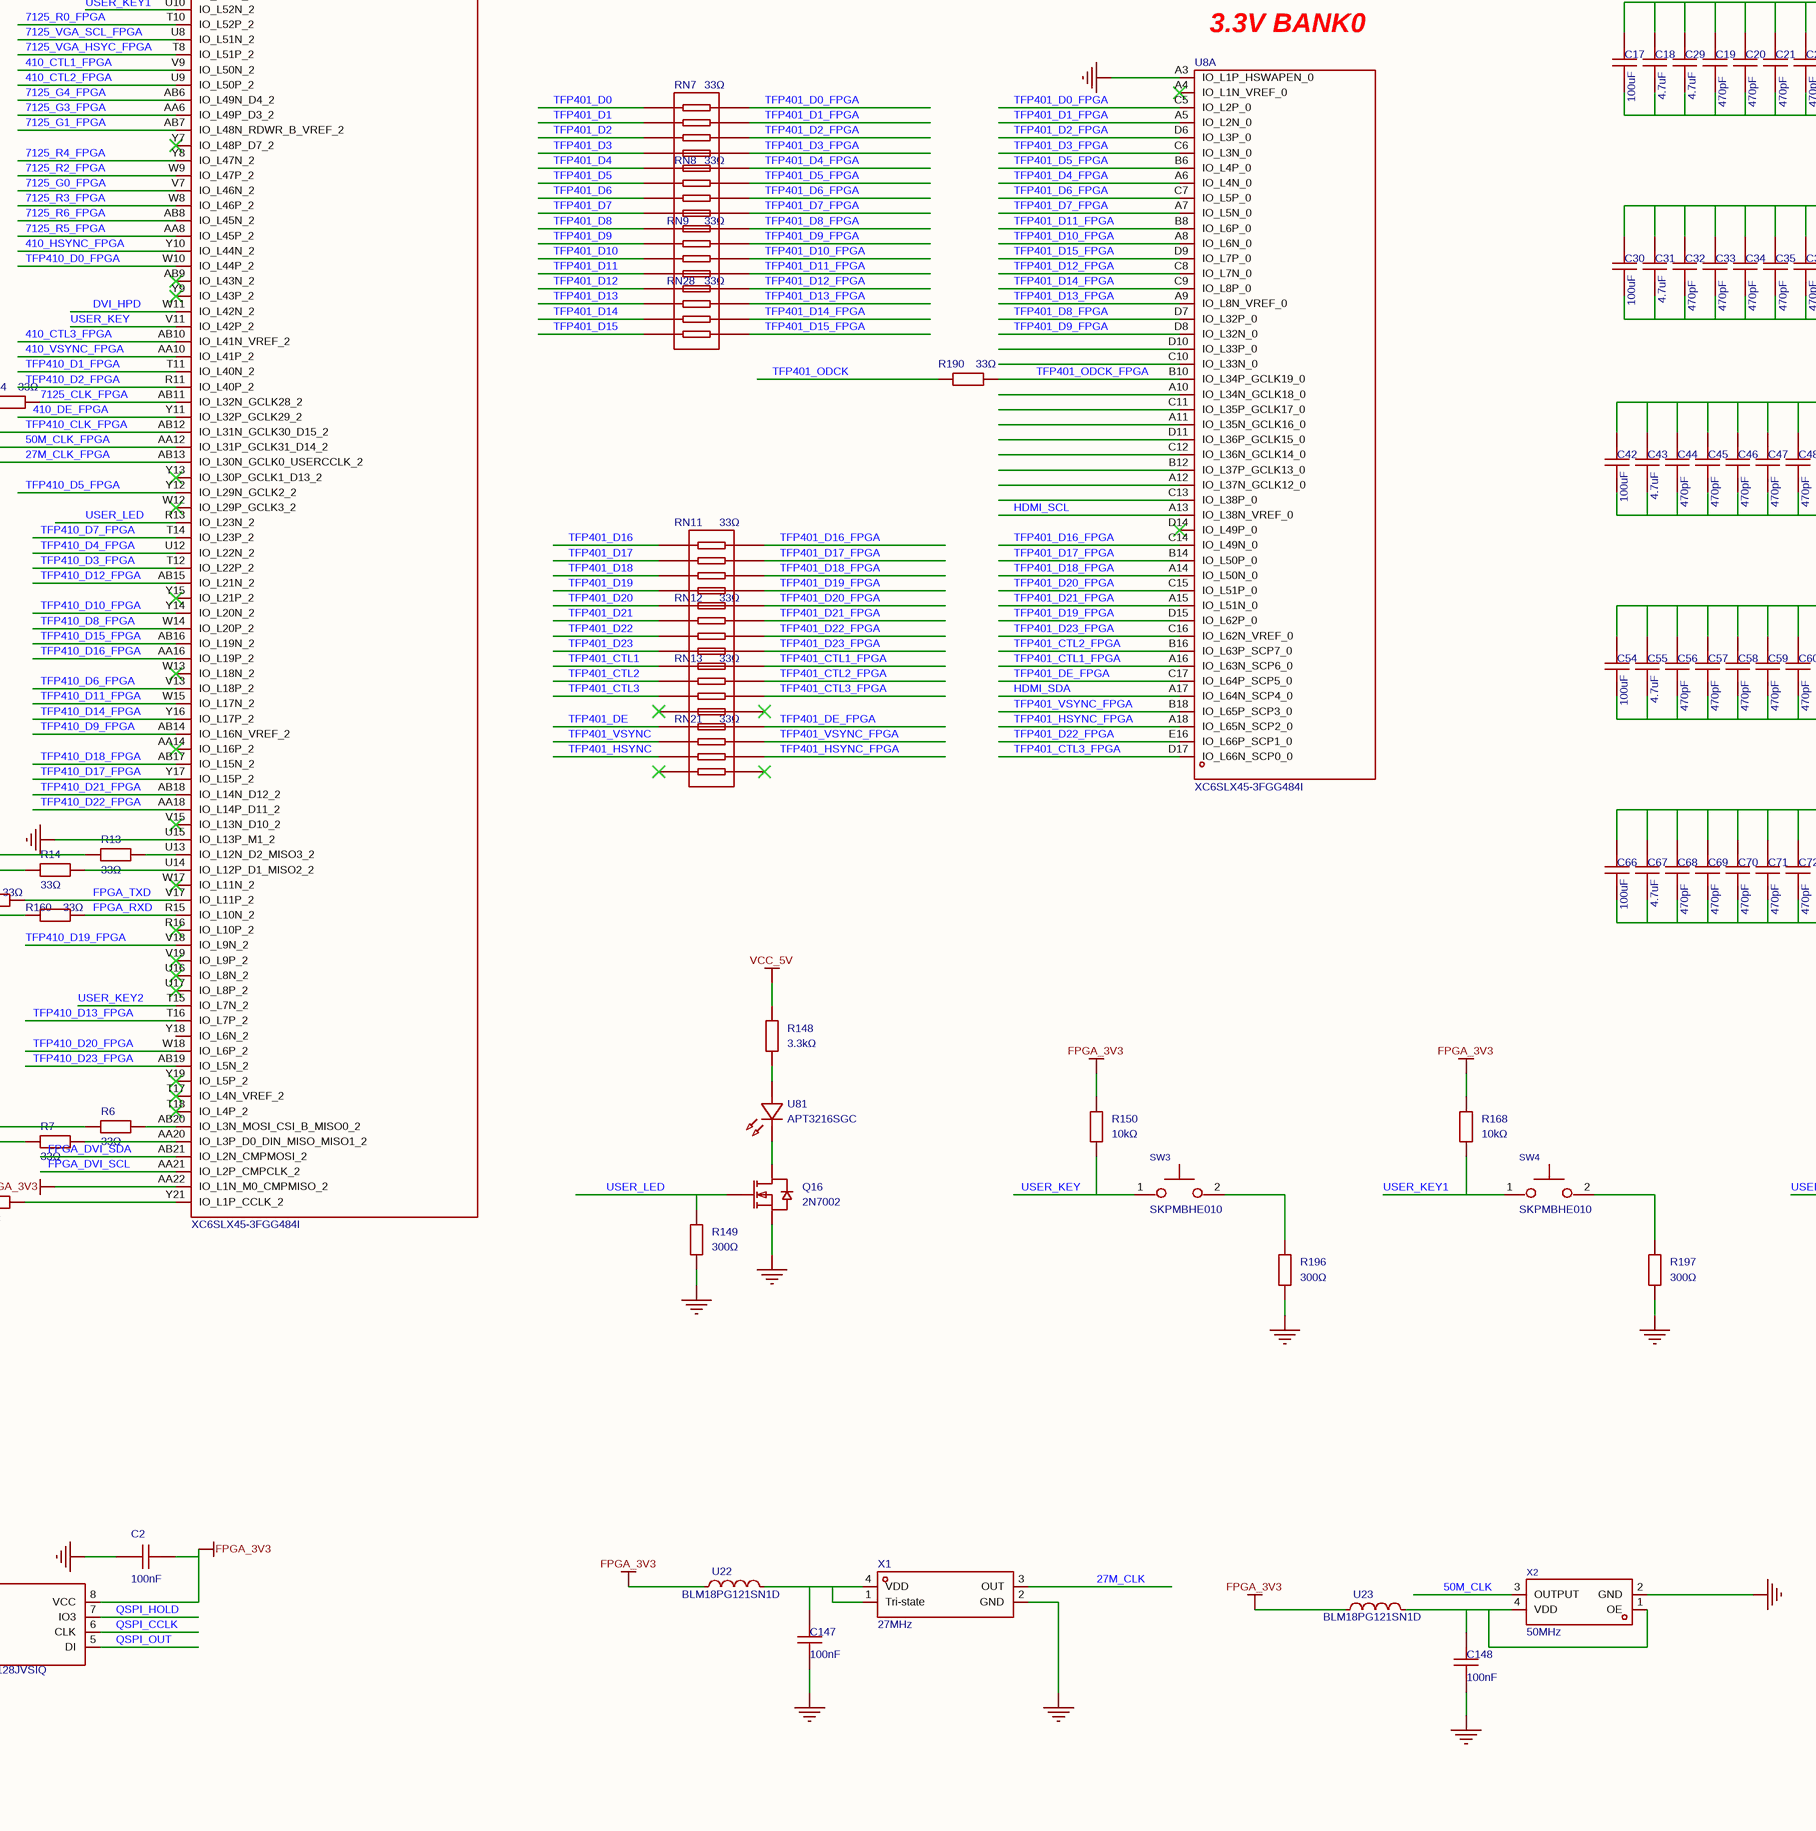
[diagram p10: P1.schdoc, bottom column 3 of 4]
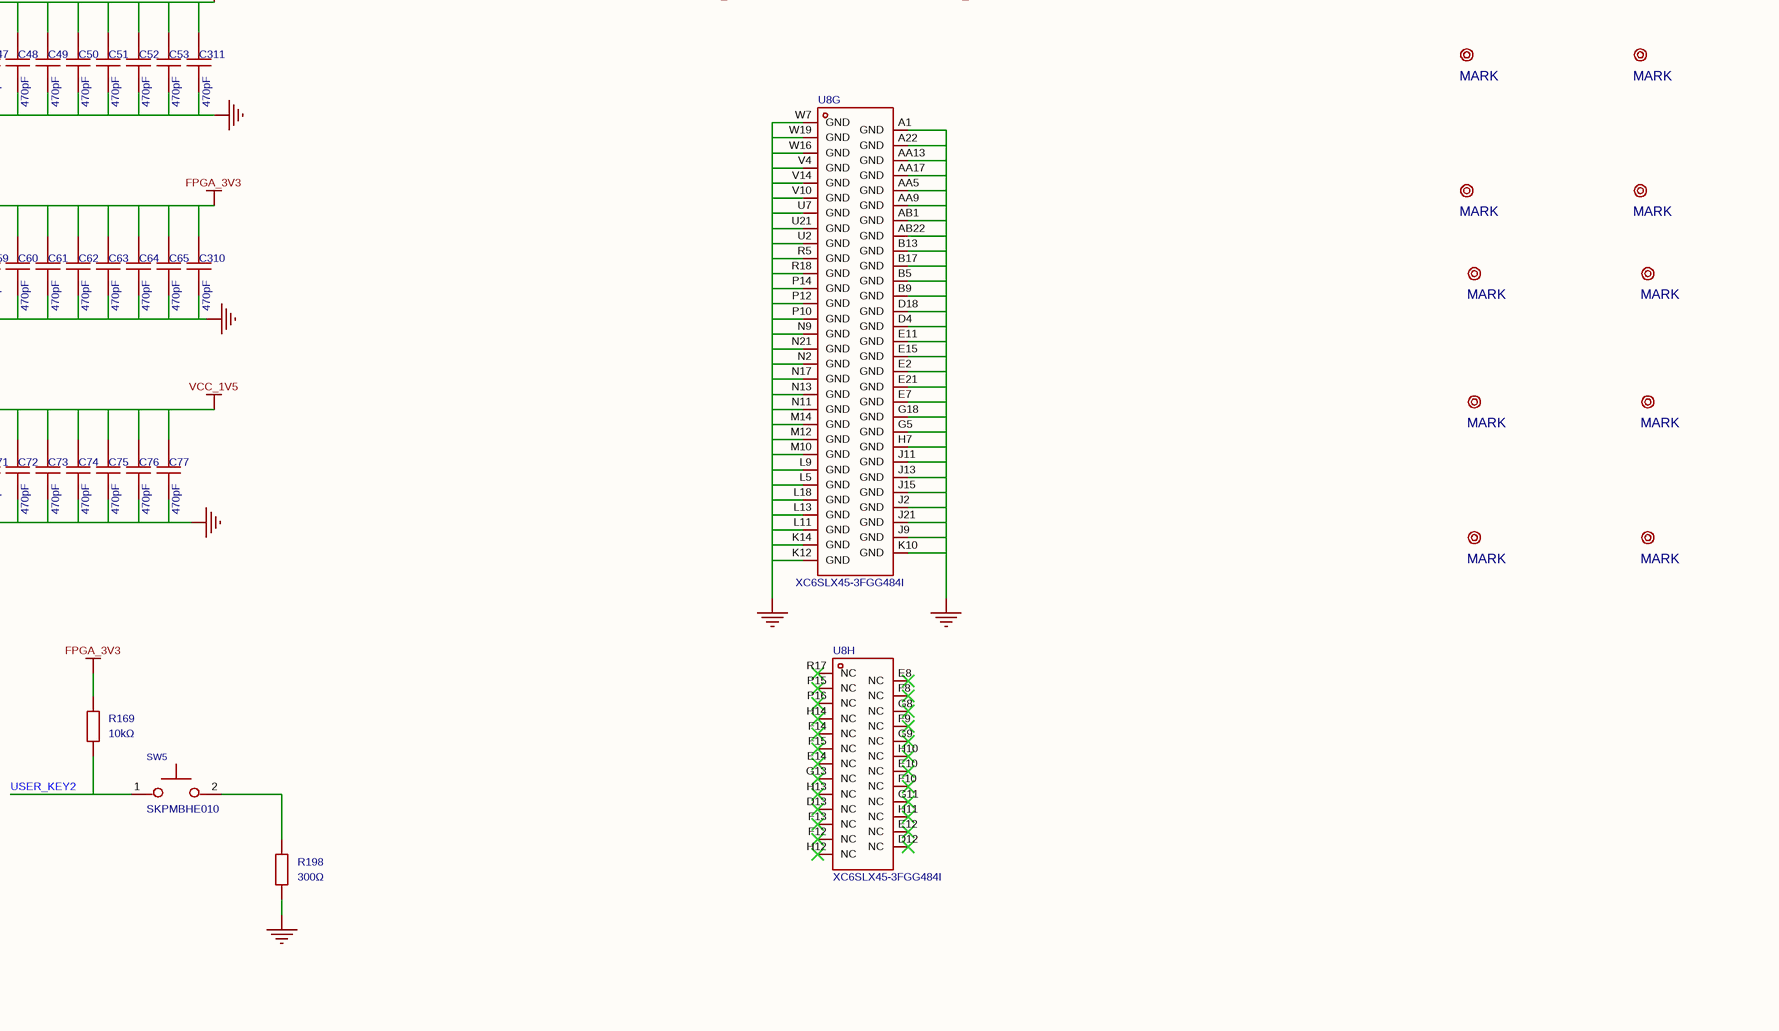
[diagram p11: P1.schdoc, bottom column 4 of 4]

(export (version "E")
  (design (tool "Eeschema 10.0.6"))
  (components
    (comp (ref "C1")
      (value "100nF")
      (footprint "C0603")
      (description "容值:100nF;精度:±10%;额定电压:50V;材质(温度系数):X7R;")
      (fields
        (field (name "MANUFACTURER") "muRata(村田)")
        (field (name "MANUFACTURERPART") "GRM188R71H104KA93D")
      )
      (libsource (lib "altium-import") (part "root_0_GRM188R71H104KA93D_"))
    )
    (comp (ref "C2")
      (value "100nF")
      (footprint "C0603")
      (description "容值:100nF;精度:±10%;额定电压:50V;材质(温度系数):X7R;")
      (fields
        (field (name "MANUFACTURER") "muRata(村田)")
        (field (name "MANUFACTURERPART") "GRM188R71H104KA93D")
      )
      (libsource (lib "altium-import") (part "root_0_GRM188R71H104KA93D_"))
    )
    (comp (ref "C3")
      (value "100nF")
      (footprint "C0603")
      (description "容值:100nF;精度:±10%;额定电压:50V;材质(温度系数):X7R;")
      (fields
        (field (name "MANUFACTURER") "muRata(村田)")
        (field (name "MANUFACTURERPART") "GRM188R71H104KA93D")
      )
      (libsource (lib "altium-import") (part "root_1_GRM188R71H104KA93D_"))
    )
    (comp (ref "C4")
      (value "100nF")
      (footprint "C0603")
      (description "容值:100nF;精度:±10%;额定电压:50V;材质(温度系数):X7R;")
      (fields
        (field (name "MANUFACTURER") "muRata(村田)")
        (field (name "MANUFACTURERPART") "GRM188R71H104KA93D")
      )
      (libsource (lib "altium-import") (part "root_2_GRM188R71H104KA93D_"))
    )
    (comp (ref "C5")
      (value "100uF")
      (footprint "C1210")
      (description "容值:100uF;精度:±20%;额定电压:6.3V;材质(温度系数):X5R;")
      (fields
        (field (name "MANUFACTURER") "muRata(村田)")
        (field (name "MANUFACTURER PART") "GRM32ER60J107ME20L")
      )
      (libsource (lib "altium-import") (part "root_1_GRM32ER60J107ME20L_"))
    )
    (comp (ref "C6")
      (value "4.7uF")
      (footprint "C0603")
      (description "容值:4.7uF;精度:±10%;额定电压:16V;材质(温度系数):X5R;")
      (fields
        (field (name "MANUFACTURER") "muRata(村田)")
        (field (name "MANUFACTURER PART") "GRM188R61C475KE11D")
      )
      (libsource (lib "altium-import") (part "root_1_GRM188R61C475KE11D_"))
    )
    (comp (ref "C7")
      (value "470pF")
      (footprint "C0402")
      (description "容值:470pF;精度:±5%;额定电压:50V;材质(温度系数):X7R;")
      (fields
        (field (name "MANUFACTURER") "muRata(村田)")
        (field (name "MANUFACTURER PART") "GRM155R71H471JA01D")
      )
      (libsource (lib "altium-import") (part "root_1_GRM155R71H471JA01D_"))
    )
    (comp (ref "C8")
      (value "470pF")
      (footprint "C0402")
      (description "容值:470pF;精度:±5%;额定电压:50V;材质(温度系数):X7R;")
      (fields
        (field (name "MANUFACTURER") "muRata(村田)")
        (field (name "MANUFACTURER PART") "GRM155R71H471JA01D")
      )
      (libsource (lib "altium-import") (part "root_1_GRM155R71H471JA01D_"))
    )
    (comp (ref "C9")
      (value "470pF")
      (footprint "C0402")
      (description "容值:470pF;精度:±5%;额定电压:50V;材质(温度系数):X7R;")
      (fields
        (field (name "MANUFACTURER") "muRata(村田)")
        (field (name "MANUFACTURER PART") "GRM155R71H471JA01D")
      )
      (libsource (lib "altium-import") (part "root_1_GRM155R71H471JA01D_"))
    )
    (comp (ref "C10")
      (value "470pF")
      (footprint "C0402")
      (description "容值:470pF;精度:±5%;额定电压:50V;材质(温度系数):X7R;")
      (fields
        (field (name "MANUFACTURER") "muRata(村田)")
        (field (name "MANUFACTURER PART") "GRM155R71H471JA01D")
      )
      (libsource (lib "altium-import") (part "root_1_GRM155R71H471JA01D_"))
    )
    (comp (ref "C11")
      (value "470pF")
      (footprint "C0402")
      (description "容值:470pF;精度:±5%;额定电压:50V;材质(温度系数):X7R;")
      (fields
        (field (name "MANUFACTURER") "muRata(村田)")
        (field (name "MANUFACTURER PART") "GRM155R71H471JA01D")
      )
      (libsource (lib "altium-import") (part "root_1_GRM155R71H471JA01D_"))
    )
    (comp (ref "C12")
      (value "470pF")
      (footprint "C0402")
      (description "容值:470pF;精度:±5%;额定电压:50V;材质(温度系数):X7R;")
      (fields
        (field (name "MANUFACTURER") "muRata(村田)")
        (field (name "MANUFACTURER PART") "GRM155R71H471JA01D")
      )
      (libsource (lib "altium-import") (part "root_1_GRM155R71H471JA01D_"))
    )
    (comp (ref "C13")
      (value "470pF")
      (footprint "C0402")
      (description "容值:470pF;精度:±5%;额定电压:50V;材质(温度系数):X7R;")
      (fields
        (field (name "MANUFACTURER") "muRata(村田)")
        (field (name "MANUFACTURER PART") "GRM155R71H471JA01D")
      )
      (libsource (lib "altium-import") (part "root_1_GRM155R71H471JA01D_"))
    )
    (comp (ref "C14")
      (value "470pF")
      (footprint "C0402")
      (description "容值:470pF;精度:±5%;额定电压:50V;材质(温度系数):X7R;")
      (fields
        (field (name "MANUFACTURER") "muRata(村田)")
        (field (name "MANUFACTURER PART") "GRM155R71H471JA01D")
      )
      (libsource (lib "altium-import") (part "root_1_GRM155R71H471JA01D_"))
    )
    (comp (ref "C15")
      (value "470pF")
      (footprint "C0402")
      (description "容值:470pF;精度:±5%;额定电压:50V;材质(温度系数):X7R;")
      (fields
        (field (name "MANUFACTURER") "muRata(村田)")
        (field (name "MANUFACTURER PART") "GRM155R71H471JA01D")
      )
      (libsource (lib "altium-import") (part "root_1_GRM155R71H471JA01D_"))
    )
    (comp (ref "C16")
      (value "470pF")
      (footprint "C0402")
      (description "容值:470pF;精度:±5%;额定电压:50V;材质(温度系数):X7R;")
      (fields
        (field (name "MANUFACTURER") "muRata(村田)")
        (field (name "MANUFACTURER PART") "GRM155R71H471JA01D")
      )
      (libsource (lib "altium-import") (part "root_1_GRM155R71H471JA01D_"))
    )
    (comp (ref "C17")
      (value "100uF")
      (footprint "C1210")
      (description "容值:100uF;精度:±20%;额定电压:6.3V;材质(温度系数):X5R;")
      (fields
        (field (name "MANUFACTURER") "muRata(村田)")
        (field (name "MANUFACTURER PART") "GRM32ER60J107ME20L")
      )
      (libsource (lib "altium-import") (part "root_1_GRM32ER60J107ME20L_"))
    )
    (comp (ref "C18")
      (value "4.7uF")
      (footprint "C0603")
      (description "容值:4.7uF;精度:±10%;额定电压:16V;材质(温度系数):X5R;")
      (fields
        (field (name "MANUFACTURER") "muRata(村田)")
        (field (name "MANUFACTURER PART") "GRM188R61C475KE11D")
      )
      (libsource (lib "altium-import") (part "root_1_GRM188R61C475KE11D_"))
    )
    (comp (ref "C19")
      (value "470pF")
      (footprint "C0402")
      (description "容值:470pF;精度:±5%;额定电压:50V;材质(温度系数):X7R;")
      (fields
        (field (name "MANUFACTURER") "muRata(村田)")
        (field (name "MANUFACTURER PART") "GRM155R71H471JA01D")
      )
      (libsource (lib "altium-import") (part "root_1_GRM155R71H471JA01D_"))
    )
    (comp (ref "C20")
      (value "470pF")
      (footprint "C0402")
      (description "容值:470pF;精度:±5%;额定电压:50V;材质(温度系数):X7R;")
      (fields
        (field (name "MANUFACTURER") "muRata(村田)")
        (field (name "MANUFACTURER PART") "GRM155R71H471JA01D")
      )
      (libsource (lib "altium-import") (part "root_1_GRM155R71H471JA01D_"))
    )
    (comp (ref "C21")
      (value "470pF")
      (footprint "C0402")
      (description "容值:470pF;精度:±5%;额定电压:50V;材质(温度系数):X7R;")
      (fields
        (field (name "MANUFACTURER") "muRata(村田)")
        (field (name "MANUFACTURER PART") "GRM155R71H471JA01D")
      )
      (libsource (lib "altium-import") (part "root_1_GRM155R71H471JA01D_"))
    )
    (comp (ref "C22")
      (value "470pF")
      (footprint "C0402")
      (description "容值:470pF;精度:±5%;额定电压:50V;材质(温度系数):X7R;")
      (fields
        (field (name "MANUFACTURER") "muRata(村田)")
        (field (name "MANUFACTURER PART") "GRM155R71H471JA01D")
      )
      (libsource (lib "altium-import") (part "root_1_GRM155R71H471JA01D_"))
    )
    (comp (ref "C23")
      (value "470pF")
      (footprint "C0402")
      (description "容值:470pF;精度:±5%;额定电压:50V;材质(温度系数):X7R;")
      (fields
        (field (name "MANUFACTURER") "muRata(村田)")
        (field (name "MANUFACTURER PART") "GRM155R71H471JA01D")
      )
      (libsource (lib "altium-import") (part "root_1_GRM155R71H471JA01D_"))
    )
    (comp (ref "C24")
      (value "470pF")
      (footprint "C0402")
      (description "容值:470pF;精度:±5%;额定电压:50V;材质(温度系数):X7R;")
      (fields
        (field (name "MANUFACTURER") "muRata(村田)")
        (field (name "MANUFACTURER PART") "GRM155R71H471JA01D")
      )
      (libsource (lib "altium-import") (part "root_1_GRM155R71H471JA01D_"))
    )
    (comp (ref "C25")
      (value "470pF")
      (footprint "C0402")
      (description "容值:470pF;精度:±5%;额定电压:50V;材质(温度系数):X7R;")
      (fields
        (field (name "MANUFACTURER") "muRata(村田)")
        (field (name "MANUFACTURER PART") "GRM155R71H471JA01D")
      )
      (libsource (lib "altium-import") (part "root_1_GRM155R71H471JA01D_"))
    )
    (comp (ref "C29")
      (value "4.7uF")
      (footprint "C0603")
      (description "容值:4.7uF;精度:±10%;额定电压:16V;材质(温度系数):X5R;")
      (fields
        (field (name "MANUFACTURER") "muRata(村田)")
        (field (name "MANUFACTURER PART") "GRM188R61C475KE11D")
      )
      (libsource (lib "altium-import") (part "root_1_GRM188R61C475KE11D_"))
    )
    (comp (ref "C30")
      (value "100uF")
      (footprint "C1210")
      (description "容值:100uF;精度:±20%;额定电压:6.3V;材质(温度系数):X5R;")
      (fields
        (field (name "MANUFACTURER") "muRata(村田)")
        (field (name "MANUFACTURER PART") "GRM32ER60J107ME20L")
      )
      (libsource (lib "altium-import") (part "root_1_GRM32ER60J107ME20L_"))
    )
    (comp (ref "C31")
      (value "4.7uF")
      (footprint "C0603")
      (description "容值:4.7uF;精度:±10%;额定电压:16V;材质(温度系数):X5R;")
      (fields
        (field (name "MANUFACTURER") "muRata(村田)")
        (field (name "MANUFACTURER PART") "GRM188R61C475KE11D")
      )
      (libsource (lib "altium-import") (part "root_1_GRM188R61C475KE11D_"))
    )
    (comp (ref "C32")
      (value "470pF")
      (footprint "C0402")
      (description "容值:470pF;精度:±5%;额定电压:50V;材质(温度系数):X7R;")
      (fields
        (field (name "MANUFACTURER") "muRata(村田)")
        (field (name "MANUFACTURER PART") "GRM155R71H471JA01D")
      )
      (libsource (lib "altium-import") (part "root_1_GRM155R71H471JA01D_"))
    )
    (comp (ref "C33")
      (value "470pF")
      (footprint "C0402")
      (description "容值:470pF;精度:±5%;额定电压:50V;材质(温度系数):X7R;")
      (fields
        (field (name "MANUFACTURER") "muRata(村田)")
        (field (name "MANUFACTURER PART") "GRM155R71H471JA01D")
      )
      (libsource (lib "altium-import") (part "root_1_GRM155R71H471JA01D_"))
    )
    (comp (ref "C34")
      (value "470pF")
      (footprint "C0402")
      (description "容值:470pF;精度:±5%;额定电压:50V;材质(温度系数):X7R;")
      (fields
        (field (name "MANUFACTURER") "muRata(村田)")
        (field (name "MANUFACTURER PART") "GRM155R71H471JA01D")
      )
      (libsource (lib "altium-import") (part "root_1_GRM155R71H471JA01D_"))
    )
    (comp (ref "C35")
      (value "470pF")
      (footprint "C0402")
      (description "容值:470pF;精度:±5%;额定电压:50V;材质(温度系数):X7R;")
      (fields
        (field (name "MANUFACTURER") "muRata(村田)")
        (field (name "MANUFACTURER PART") "GRM155R71H471JA01D")
      )
      (libsource (lib "altium-import") (part "root_1_GRM155R71H471JA01D_"))
    )
    (comp (ref "C36")
      (value "470pF")
      (footprint "C0402")
      (description "容值:470pF;精度:±5%;额定电压:50V;材质(温度系数):X7R;")
      (fields
        (field (name "MANUFACTURER") "muRata(村田)")
        (field (name "MANUFACTURER PART") "GRM155R71H471JA01D")
      )
      (libsource (lib "altium-import") (part "root_1_GRM155R71H471JA01D_"))
    )
    (comp (ref "C37")
      (value "470pF")
      (footprint "C0402")
      (description "容值:470pF;精度:±5%;额定电压:50V;材质(温度系数):X7R;")
      (fields
        (field (name "MANUFACTURER") "muRata(村田)")
        (field (name "MANUFACTURER PART") "GRM155R71H471JA01D")
      )
      (libsource (lib "altium-import") (part "root_1_GRM155R71H471JA01D_"))
    )
    (comp (ref "C38")
      (value "470pF")
      (footprint "C0402")
      (description "容值:470pF;精度:±5%;额定电压:50V;材质(温度系数):X7R;")
      (fields
        (field (name "MANUFACTURER") "muRata(村田)")
        (field (name "MANUFACTURER PART") "GRM155R71H471JA01D")
      )
      (libsource (lib "altium-import") (part "root_1_GRM155R71H471JA01D_"))
    )
    (comp (ref "C39")
      (value "470pF")
      (footprint "C0402")
      (description "容值:470pF;精度:±5%;额定电压:50V;材质(温度系数):X7R;")
      (fields
        (field (name "MANUFACTURER") "muRata(村田)")
        (field (name "MANUFACTURER PART") "GRM155R71H471JA01D")
      )
      (libsource (lib "altium-import") (part "root_1_GRM155R71H471JA01D_"))
    )
    (comp (ref "C40")
      (value "470pF")
      (footprint "C0402")
      (description "容值:470pF;精度:±5%;额定电压:50V;材质(温度系数):X7R;")
      (fields
        (field (name "MANUFACTURER") "muRata(村田)")
        (field (name "MANUFACTURER PART") "GRM155R71H471JA01D")
      )
      (libsource (lib "altium-import") (part "root_1_GRM155R71H471JA01D_"))
    )
    (comp (ref "C41")
      (value "470pF")
      (footprint "C0402")
      (description "容值:470pF;精度:±5%;额定电压:50V;材质(温度系数):X7R;")
      (fields
        (field (name "MANUFACTURER") "muRata(村田)")
        (field (name "MANUFACTURER PART") "GRM155R71H471JA01D")
      )
      (libsource (lib "altium-import") (part "root_1_GRM155R71H471JA01D_"))
    )
    (comp (ref "C42")
      (value "100uF")
      (footprint "C1210")
      (description "容值:100uF;精度:±20%;额定电压:6.3V;材质(温度系数):X5R;")
      (fields
        (field (name "MANUFACTURER") "muRata(村田)")
        (field (name "MANUFACTURER PART") "GRM32ER60J107ME20L")
      )
      (libsource (lib "altium-import") (part "root_1_GRM32ER60J107ME20L_"))
    )
    (comp (ref "C43")
      (value "4.7uF")
      (footprint "C0603")
      (description "容值:4.7uF;精度:±10%;额定电压:16V;材质(温度系数):X5R;")
      (fields
        (field (name "MANUFACTURER") "muRata(村田)")
        (field (name "MANUFACTURER PART") "GRM188R61C475KE11D")
      )
      (libsource (lib "altium-import") (part "root_1_GRM188R61C475KE11D_"))
    )
    (comp (ref "C44")
      (value "470pF")
      (footprint "C0402")
      (description "容值:470pF;精度:±5%;额定电压:50V;材质(温度系数):X7R;")
      (fields
        (field (name "MANUFACTURER") "muRata(村田)")
        (field (name "MANUFACTURER PART") "GRM155R71H471JA01D")
      )
      (libsource (lib "altium-import") (part "root_1_GRM155R71H471JA01D_"))
    )
    (comp (ref "C45")
      (value "470pF")
      (footprint "C0402")
      (description "容值:470pF;精度:±5%;额定电压:50V;材质(温度系数):X7R;")
      (fields
        (field (name "MANUFACTURER") "muRata(村田)")
        (field (name "MANUFACTURER PART") "GRM155R71H471JA01D")
      )
      (libsource (lib "altium-import") (part "root_1_GRM155R71H471JA01D_"))
    )
    (comp (ref "C46")
      (value "470pF")
      (footprint "C0402")
      (description "容值:470pF;精度:±5%;额定电压:50V;材质(温度系数):X7R;")
      (fields
        (field (name "MANUFACTURER") "muRata(村田)")
        (field (name "MANUFACTURER PART") "GRM155R71H471JA01D")
      )
      (libsource (lib "altium-import") (part "root_1_GRM155R71H471JA01D_"))
    )
    (comp (ref "C47")
      (value "470pF")
      (footprint "C0402")
      (description "容值:470pF;精度:±5%;额定电压:50V;材质(温度系数):X7R;")
      (fields
        (field (name "MANUFACTURER") "muRata(村田)")
        (field (name "MANUFACTURER PART") "GRM155R71H471JA01D")
      )
      (libsource (lib "altium-import") (part "root_1_GRM155R71H471JA01D_"))
    )
    (comp (ref "C48")
      (value "470pF")
      (footprint "C0402")
      (description "容值:470pF;精度:±5%;额定电压:50V;材质(温度系数):X7R;")
      (fields
        (field (name "MANUFACTURER") "muRata(村田)")
        (field (name "MANUFACTURER PART") "GRM155R71H471JA01D")
      )
      (libsource (lib "altium-import") (part "root_1_GRM155R71H471JA01D_"))
    )
    (comp (ref "C49")
      (value "470pF")
      (footprint "C0402")
      (description "容值:470pF;精度:±5%;额定电压:50V;材质(温度系数):X7R;")
      (fields
        (field (name "MANUFACTURER") "muRata(村田)")
        (field (name "MANUFACTURER PART") "GRM155R71H471JA01D")
      )
      (libsource (lib "altium-import") (part "root_1_GRM155R71H471JA01D_"))
    )
    (comp (ref "C50")
      (value "470pF")
      (footprint "C0402")
      (description "容值:470pF;精度:±5%;额定电压:50V;材质(温度系数):X7R;")
      (fields
        (field (name "MANUFACTURER") "muRata(村田)")
        (field (name "MANUFACTURER PART") "GRM155R71H471JA01D")
      )
      (libsource (lib "altium-import") (part "root_1_GRM155R71H471JA01D_"))
    )
    (comp (ref "C51")
      (value "470pF")
      (footprint "C0402")
      (description "容值:470pF;精度:±5%;额定电压:50V;材质(温度系数):X7R;")
      (fields
        (field (name "MANUFACTURER") "muRata(村田)")
        (field (name "MANUFACTURER PART") "GRM155R71H471JA01D")
      )
      (libsource (lib "altium-import") (part "root_1_GRM155R71H471JA01D_"))
    )
    (comp (ref "C52")
      (value "470pF")
      (footprint "C0402")
      (description "容值:470pF;精度:±5%;额定电压:50V;材质(温度系数):X7R;")
      (fields
        (field (name "MANUFACTURER") "muRata(村田)")
        (field (name "MANUFACTURER PART") "GRM155R71H471JA01D")
      )
      (libsource (lib "altium-import") (part "root_1_GRM155R71H471JA01D_"))
    )
    (comp (ref "C53")
      (value "470pF")
      (footprint "C0402")
      (description "容值:470pF;精度:±5%;额定电压:50V;材质(温度系数):X7R;")
      (fields
        (field (name "MANUFACTURER") "muRata(村田)")
        (field (name "MANUFACTURER PART") "GRM155R71H471JA01D")
      )
      (libsource (lib "altium-import") (part "root_1_GRM155R71H471JA01D_"))
    )
    (comp (ref "C54")
      (value "100uF")
      (footprint "C1210")
      (description "容值:100uF;精度:±20%;额定电压:6.3V;材质(温度系数):X5R;")
      (fields
        (field (name "MANUFACTURER") "muRata(村田)")
        (field (name "MANUFACTURER PART") "GRM32ER60J107ME20L")
      )
      (libsource (lib "altium-import") (part "root_1_GRM32ER60J107ME20L_"))
    )
    (comp (ref "C55")
      (value "4.7uF")
      (footprint "C0603")
      (description "容值:4.7uF;精度:±10%;额定电压:16V;材质(温度系数):X5R;")
      (fields
        (field (name "MANUFACTURER") "muRata(村田)")
        (field (name "MANUFACTURER PART") "GRM188R61C475KE11D")
      )
      (libsource (lib "altium-import") (part "root_1_GRM188R61C475KE11D_"))
    )
    (comp (ref "C56")
      (value "470pF")
      (footprint "C0402")
      (description "容值:470pF;精度:±5%;额定电压:50V;材质(温度系数):X7R;")
      (fields
        (field (name "MANUFACTURER") "muRata(村田)")
        (field (name "MANUFACTURER PART") "GRM155R71H471JA01D")
      )
      (libsource (lib "altium-import") (part "root_1_GRM155R71H471JA01D_"))
    )
    (comp (ref "C57")
      (value "470pF")
      (footprint "C0402")
      (description "容值:470pF;精度:±5%;额定电压:50V;材质(温度系数):X7R;")
      (fields
        (field (name "MANUFACTURER") "muRata(村田)")
        (field (name "MANUFACTURER PART") "GRM155R71H471JA01D")
      )
      (libsource (lib "altium-import") (part "root_1_GRM155R71H471JA01D_"))
    )
    (comp (ref "C58")
      (value "470pF")
      (footprint "C0402")
      (description "容值:470pF;精度:±5%;额定电压:50V;材质(温度系数):X7R;")
      (fields
        (field (name "MANUFACTURER") "muRata(村田)")
        (field (name "MANUFACTURER PART") "GRM155R71H471JA01D")
      )
      (libsource (lib "altium-import") (part "root_1_GRM155R71H471JA01D_"))
    )
    (comp (ref "C59")
      (value "470pF")
      (footprint "C0402")
      (description "容值:470pF;精度:±5%;额定电压:50V;材质(温度系数):X7R;")
      (fields
        (field (name "MANUFACTURER") "muRata(村田)")
        (field (name "MANUFACTURER PART") "GRM155R71H471JA01D")
      )
      (libsource (lib "altium-import") (part "root_1_GRM155R71H471JA01D_"))
    )
    (comp (ref "C60")
      (value "470pF")
      (footprint "C0402")
      (description "容值:470pF;精度:±5%;额定电压:50V;材质(温度系数):X7R;")
      (fields
        (field (name "MANUFACTURER") "muRata(村田)")
        (field (name "MANUFACTURER PART") "GRM155R71H471JA01D")
      )
      (libsource (lib "altium-import") (part "root_1_GRM155R71H471JA01D_"))
    )
    (comp (ref "C61")
      (value "470pF")
      (footprint "C0402")
      (description "容值:470pF;精度:±5%;额定电压:50V;材质(温度系数):X7R;")
      (fields
        (field (name "MANUFACTURER") "muRata(村田)")
        (field (name "MANUFACTURER PART") "GRM155R71H471JA01D")
      )
      (libsource (lib "altium-import") (part "root_1_GRM155R71H471JA01D_"))
    )
    (comp (ref "C62")
      (value "470pF")
      (footprint "C0402")
      (description "容值:470pF;精度:±5%;额定电压:50V;材质(温度系数):X7R;")
      (fields
        (field (name "MANUFACTURER") "muRata(村田)")
        (field (name "MANUFACTURER PART") "GRM155R71H471JA01D")
      )
      (libsource (lib "altium-import") (part "root_1_GRM155R71H471JA01D_"))
    )
    (comp (ref "C63")
      (value "470pF")
      (footprint "C0402")
      (description "容值:470pF;精度:±5%;额定电压:50V;材质(温度系数):X7R;")
      (fields
        (field (name "MANUFACTURER") "muRata(村田)")
        (field (name "MANUFACTURER PART") "GRM155R71H471JA01D")
      )
      (libsource (lib "altium-import") (part "root_1_GRM155R71H471JA01D_"))
    )
    (comp (ref "C64")
      (value "470pF")
      (footprint "C0402")
      (description "容值:470pF;精度:±5%;额定电压:50V;材质(温度系数):X7R;")
      (fields
        (field (name "MANUFACTURER") "muRata(村田)")
        (field (name "MANUFACTURER PART") "GRM155R71H471JA01D")
      )
      (libsource (lib "altium-import") (part "root_1_GRM155R71H471JA01D_"))
    )
    (comp (ref "C65")
      (value "470pF")
      (footprint "C0402")
      (description "容值:470pF;精度:±5%;额定电压:50V;材质(温度系数):X7R;")
      (fields
        (field (name "MANUFACTURER") "muRata(村田)")
        (field (name "MANUFACTURER PART") "GRM155R71H471JA01D")
      )
      (libsource (lib "altium-import") (part "root_1_GRM155R71H471JA01D_"))
    )
    (comp (ref "C66")
      (value "100uF")
      (footprint "C1210")
      (description "容值:100uF;精度:±20%;额定电压:6.3V;材质(温度系数):X5R;")
      (fields
        (field (name "MANUFACTURER") "muRata(村田)")
        (field (name "MANUFACTURER PART") "GRM32ER60J107ME20L")
      )
      (libsource (lib "altium-import") (part "root_1_GRM32ER60J107ME20L_"))
    )
    (comp (ref "C67")
      (value "4.7uF")
      (footprint "C0603")
      (description "容值:4.7uF;精度:±10%;额定电压:16V;材质(温度系数):X5R;")
      (fields
        (field (name "MANUFACTURER") "muRata(村田)")
        (field (name "MANUFACTURER PART") "GRM188R61C475KE11D")
      )
      (libsource (lib "altium-import") (part "root_1_GRM188R61C475KE11D_"))
    )
    (comp (ref "C68")
      (value "470pF")
      (footprint "C0402")
      (description "容值:470pF;精度:±5%;额定电压:50V;材质(温度系数):X7R;")
      (fields
        (field (name "MANUFACTURER") "muRata(村田)")
        (field (name "MANUFACTURER PART") "GRM155R71H471JA01D")
      )
      (libsource (lib "altium-import") (part "root_1_GRM155R71H471JA01D_"))
    )
    (comp (ref "C69")
      (value "470pF")
      (footprint "C0402")
      (description "容值:470pF;精度:±5%;额定电压:50V;材质(温度系数):X7R;")
      (fields
        (field (name "MANUFACTURER") "muRata(村田)")
        (field (name "MANUFACTURER PART") "GRM155R71H471JA01D")
      )
      (libsource (lib "altium-import") (part "root_1_GRM155R71H471JA01D_"))
    )
    (comp (ref "C70")
      (value "470pF")
      (footprint "C0402")
      (description "容值:470pF;精度:±5%;额定电压:50V;材质(温度系数):X7R;")
      (fields
        (field (name "MANUFACTURER") "muRata(村田)")
        (field (name "MANUFACTURER PART") "GRM155R71H471JA01D")
      )
      (libsource (lib "altium-import") (part "root_1_GRM155R71H471JA01D_"))
    )
    (comp (ref "C71")
      (value "470pF")
      (footprint "C0402")
      (description "容值:470pF;精度:±5%;额定电压:50V;材质(温度系数):X7R;")
      (fields
        (field (name "MANUFACTURER") "muRata(村田)")
        (field (name "MANUFACTURER PART") "GRM155R71H471JA01D")
      )
      (libsource (lib "altium-import") (part "root_1_GRM155R71H471JA01D_"))
    )
    (comp (ref "C72")
      (value "470pF")
      (footprint "C0402")
      (description "容值:470pF;精度:±5%;额定电压:50V;材质(温度系数):X7R;")
      (fields
        (field (name "MANUFACTURER") "muRata(村田)")
        (field (name "MANUFACTURER PART") "GRM155R71H471JA01D")
      )
      (libsource (lib "altium-import") (part "root_1_GRM155R71H471JA01D_"))
    )
    (comp (ref "C73")
      (value "470pF")
      (footprint "C0402")
      (description "容值:470pF;精度:±5%;额定电压:50V;材质(温度系数):X7R;")
      (fields
        (field (name "MANUFACTURER") "muRata(村田)")
        (field (name "MANUFACTURER PART") "GRM155R71H471JA01D")
      )
      (libsource (lib "altium-import") (part "root_1_GRM155R71H471JA01D_"))
    )
    (comp (ref "C74")
      (value "470pF")
      (footprint "C0402")
      (description "容值:470pF;精度:±5%;额定电压:50V;材质(温度系数):X7R;")
      (fields
        (field (name "MANUFACTURER") "muRata(村田)")
        (field (name "MANUFACTURER PART") "GRM155R71H471JA01D")
      )
      (libsource (lib "altium-import") (part "root_1_GRM155R71H471JA01D_"))
    )
    (comp (ref "C75")
      (value "470pF")
      (footprint "C0402")
      (description "容值:470pF;精度:±5%;额定电压:50V;材质(温度系数):X7R;")
      (fields
        (field (name "MANUFACTURER") "muRata(村田)")
        (field (name "MANUFACTURER PART") "GRM155R71H471JA01D")
      )
      (libsource (lib "altium-import") (part "root_1_GRM155R71H471JA01D_"))
    )
    (comp (ref "C76")
      (value "470pF")
      (footprint "C0402")
      (description "容值:470pF;精度:±5%;额定电压:50V;材质(温度系数):X7R;")
      (fields
        (field (name "MANUFACTURER") "muRata(村田)")
        (field (name "MANUFACTURER PART") "GRM155R71H471JA01D")
      )
      (libsource (lib "altium-import") (part "root_1_GRM155R71H471JA01D_"))
    )
    (comp (ref "C77")
      (value "470pF")
      (footprint "C0402")
      (description "容值:470pF;精度:±5%;额定电压:50V;材质(温度系数):X7R;")
      (fields
        (field (name "MANUFACTURER") "muRata(村田)")
        (field (name "MANUFACTURER PART") "GRM155R71H471JA01D")
      )
      (libsource (lib "altium-import") (part "root_1_GRM155R71H471JA01D_"))
    )
    (comp (ref "C78")
      (value "100nF")
      (footprint "C0402")
      (description "容值:100nF;精度:±10%;额定电压:10V;材质(温度系数):X7R;")
      (fields
        (field (name "MANUFACTURER") "muRata(村田)")
        (field (name "MANUFACTURERPART") "GCM155R71A104KA55D")
      )
      (libsource (lib "altium-import") (part "root_1_GCM155R71A104KA55D_"))
    )
    (comp (ref "C79")
      (value "100nF")
      (footprint "C0402")
      (description "容值:100nF;精度:±10%;额定电压:10V;材质(温度系数):X7R;")
      (fields
        (field (name "MANUFACTURER") "muRata(村田)")
        (field (name "MANUFACTURERPART") "GCM155R71A104KA55D")
      )
      (libsource (lib "altium-import") (part "root_1_GCM155R71A104KA55D_"))
    )
    (comp (ref "C80")
      (value "100nF")
      (footprint "C0402")
      (description "容值:100nF;精度:±10%;额定电压:10V;材质(温度系数):X7R;")
      (fields
        (field (name "MANUFACTURER") "muRata(村田)")
        (field (name "MANUFACTURERPART") "GCM155R71A104KA55D")
      )
      (libsource (lib "altium-import") (part "root_1_GCM155R71A104KA55D_"))
    )
    (comp (ref "C81")
      (value "100nF")
      (footprint "C0402")
      (description "容值:100nF;精度:±10%;额定电压:10V;材质(温度系数):X7R;")
      (fields
        (field (name "MANUFACTURER") "muRata(村田)")
        (field (name "MANUFACTURERPART") "GCM155R71A104KA55D")
      )
      (libsource (lib "altium-import") (part "root_1_GCM155R71A104KA55D_"))
    )
    (comp (ref "C82")
      (value "100nF")
      (footprint "C0402")
      (description "容值:100nF;精度:±10%;额定电压:10V;材质(温度系数):X7R;")
      (fields
        (field (name "MANUFACTURER") "muRata(村田)")
        (field (name "MANUFACTURERPART") "GCM155R71A104KA55D")
      )
      (libsource (lib "altium-import") (part "root_1_GCM155R71A104KA55D_"))
    )
    (comp (ref "C83")
      (value "100nF")
      (footprint "C0402")
      (description "容值:100nF;精度:±10%;额定电压:10V;材质(温度系数):X7R;")
      (fields
        (field (name "MANUFACTURER") "muRata(村田)")
        (field (name "MANUFACTURERPART") "GCM155R71A104KA55D")
      )
      (libsource (lib "altium-import") (part "root_1_GCM155R71A104KA55D_"))
    )
    (comp (ref "C84")
      (value "100nF")
      (footprint "C0402")
      (description "容值:100nF;精度:±10%;额定电压:10V;材质(温度系数):X7R;")
      (fields
        (field (name "MANUFACTURER") "muRata(村田)")
        (field (name "MANUFACTURERPART") "GCM155R71A104KA55D")
      )
      (libsource (lib "altium-import") (part "root_1_GCM155R71A104KA55D_"))
    )
    (comp (ref "C85")
      (value "100nF")
      (footprint "C0402")
      (description "容值:100nF;精度:±10%;额定电压:10V;材质(温度系数):X7R;")
      (fields
        (field (name "MANUFACTURER") "muRata(村田)")
        (field (name "MANUFACTURERPART") "GCM155R71A104KA55D")
      )
      (libsource (lib "altium-import") (part "root_1_GCM155R71A104KA55D_"))
    )
    (comp (ref "C86")
      (value "100nF")
      (footprint "C0402")
      (description "容值:100nF;精度:±10%;额定电压:10V;材质(温度系数):X7R;")
      (fields
        (field (name "MANUFACTURER") "muRata(村田)")
        (field (name "MANUFACTURERPART") "GCM155R71A104KA55D")
      )
      (libsource (lib "altium-import") (part "root_1_GCM155R71A104KA55D_"))
    )
    (comp (ref "C87")
      (value "100nF")
      (footprint "C0402")
      (description "容值:100nF;精度:±10%;额定电压:10V;材质(温度系数):X7R;")
      (fields
        (field (name "MANUFACTURER") "muRata(村田)")
        (field (name "MANUFACTURERPART") "GCM155R71A104KA55D")
      )
      (libsource (lib "altium-import") (part "root_1_GCM155R71A104KA55D_"))
    )
    (comp (ref "C88")
      (value "100nF")
      (footprint "C0402")
      (description "容值:100nF;精度:±10%;额定电压:10V;材质(温度系数):X7R;")
      (fields
        (field (name "MANUFACTURER") "muRata(村田)")
        (field (name "MANUFACTURERPART") "GCM155R71A104KA55D")
      )
      (libsource (lib "altium-import") (part "root_1_GCM155R71A104KA55D_"))
    )
    (comp (ref "C89")
      (value "100nF")
      (footprint "C0402")
      (description "容值:100nF;精度:±10%;额定电压:10V;材质(温度系数):X7R;")
      (fields
        (field (name "MANUFACTURER") "muRata(村田)")
        (field (name "MANUFACTURERPART") "GCM155R71A104KA55D")
      )
      (libsource (lib "altium-import") (part "root_1_GCM155R71A104KA55D_"))
    )
    (comp (ref "C90")
      (value "100nF")
      (footprint "C0402")
      (description "容值:100nF;精度:±10%;额定电压:10V;材质(温度系数):X7R;")
      (fields
        (field (name "MANUFACTURER") "muRata(村田)")
        (field (name "MANUFACTURERPART") "GCM155R71A104KA55D")
      )
      (libsource (lib "altium-import") (part "root_1_GCM155R71A104KA55D_"))
    )
    (comp (ref "C91")
      (value "100nF")
      (footprint "C0402")
      (description "容值:100nF;精度:±10%;额定电压:10V;材质(温度系数):X7R;")
      (fields
        (field (name "MANUFACTURER") "muRata(村田)")
        (field (name "MANUFACTURERPART") "GCM155R71A104KA55D")
      )
      (libsource (lib "altium-import") (part "root_1_GCM155R71A104KA55D_"))
    )
    (comp (ref "C92")
      (value "100nF")
      (footprint "C0402")
      (description "容值:100nF;精度:±10%;额定电压:10V;材质(温度系数):X7R;")
      (fields
        (field (name "MANUFACTURER") "muRata(村田)")
        (field (name "MANUFACTURERPART") "GCM155R71A104KA55D")
      )
      (libsource (lib "altium-import") (part "root_1_GCM155R71A104KA55D_"))
    )
    (comp (ref "C93")
      (value "100nF")
      (footprint "C0402")
      (description "容值:100nF;精度:±10%;额定电压:10V;材质(温度系数):X7R;")
      (fields
        (field (name "MANUFACTURER") "muRata(村田)")
        (field (name "MANUFACTURERPART") "GCM155R71A104KA55D")
      )
      (libsource (lib "altium-import") (part "root_1_GCM155R71A104KA55D_"))
    )
    (comp (ref "C94")
      (value "100nF")
      (footprint "C0402")
      (description "容值:100nF;精度:±10%;额定电压:10V;材质(温度系数):X7R;")
      (fields
        (field (name "MANUFACTURER") "muRata(村田)")
        (field (name "MANUFACTURERPART") "GCM155R71A104KA55D")
      )
      (libsource (lib "altium-import") (part "root_1_GCM155R71A104KA55D_"))
    )
    (comp (ref "C95")
      (value "100nF")
      (footprint "C0402")
      (description "容值:100nF;精度:±10%;额定电压:10V;材质(温度系数):X7R;")
      (fields
        (field (name "MANUFACTURER") "muRata(村田)")
        (field (name "MANUFACTURERPART") "GCM155R71A104KA55D")
      )
      (libsource (lib "altium-import") (part "root_1_GCM155R71A104KA55D_"))
    )
    (comp (ref "C96")
      (value "100nF")
      (footprint "C0402")
      (description "容值:100nF;精度:±10%;额定电压:10V;材质(温度系数):X7R;")
      (fields
        (field (name "MANUFACTURER") "muRata(村田)")
        (field (name "MANUFACTURERPART") "GCM155R71A104KA55D")
      )
      (libsource (lib "altium-import") (part "root_1_GCM155R71A104KA55D_"))
    )
    (comp (ref "C97")
      (value "100nF")
      (footprint "C0402")
      (description "容值:100nF;精度:±10%;额定电压:10V;材质(温度系数):X7R;")
      (fields
        (field (name "MANUFACTURER") "muRata(村田)")
        (field (name "MANUFACTURERPART") "GCM155R71A104KA55D")
      )
      (libsource (lib "altium-import") (part "root_1_GCM155R71A104KA55D_"))
    )
    (comp (ref "C98")
      (value "100nF")
      (footprint "C0402")
      (description "容值:100nF;精度:±10%;额定电压:10V;材质(温度系数):X7R;")
      (fields
        (field (name "MANUFACTURER") "muRata(村田)")
        (field (name "MANUFACTURERPART") "GCM155R71A104KA55D")
      )
      (libsource (lib "altium-import") (part "root_1_GCM155R71A104KA55D_"))
    )
    (comp (ref "C99")
      (value "100nF")
      (footprint "C0402")
      (description "容值:100nF;精度:±10%;额定电压:10V;材质(温度系数):X7R;")
      (fields
        (field (name "MANUFACTURER") "muRata(村田)")
        (field (name "MANUFACTURERPART") "GCM155R71A104KA55D")
      )
      (libsource (lib "altium-import") (part "root_1_GCM155R71A104KA55D_"))
    )
    (comp (ref "C100")
      (value "100nF")
      (footprint "C0402")
      (description "容值:100nF;精度:±10%;额定电压:10V;材质(温度系数):X7R;")
      (fields
        (field (name "MANUFACTURER") "muRata(村田)")
        (field (name "MANUFACTURERPART") "GCM155R71A104KA55D")
      )
      (libsource (lib "altium-import") (part "root_1_GCM155R71A104KA55D_"))
    )
    (comp (ref "C101")
      (value "100nF")
      (footprint "C0402")
      (description "容值:100nF;精度:±10%;额定电压:10V;材质(温度系数):X7R;")
      (fields
        (field (name "MANUFACTURER") "muRata(村田)")
        (field (name "MANUFACTURERPART") "GCM155R71A104KA55D")
      )
      (libsource (lib "altium-import") (part "root_1_GCM155R71A104KA55D_"))
    )
    (comp (ref "C102")
      (value "100nF")
      (footprint "C0402")
      (description "容值:100nF;精度:±10%;额定电压:10V;材质(温度系数):X7R;")
      (fields
        (field (name "MANUFACTURER") "muRata(村田)")
        (field (name "MANUFACTURERPART") "GCM155R71A104KA55D")
      )
      (libsource (lib "altium-import") (part "root_2_GCM155R71A104KA55D_"))
    )
    (comp (ref "C103")
      (value "100nF")
      (footprint "C0402")
      (description "容值:100nF;精度:±10%;额定电压:10V;材质(温度系数):X7R;")
      (fields
        (field (name "MANUFACTURER") "muRata(村田)")
        (field (name "MANUFACTURERPART") "GCM155R71A104KA55D")
      )
      (libsource (lib "altium-import") (part "root_2_GCM155R71A104KA55D_"))
    )
    (comp (ref "C104")
      (value "100nF")
      (footprint "C0402")
      (description "容值:100nF;精度:±10%;额定电压:10V;材质(温度系数):X7R;")
      (fields
        (field (name "MANUFACTURER") "muRata(村田)")
        (field (name "MANUFACTURERPART") "GCM155R71A104KA55D")
      )
      (libsource (lib "altium-import") (part "root_2_GCM155R71A104KA55D_"))
    )
    (comp (ref "C105")
      (value "100nF")
      (footprint "C0402")
      (description "容值:100nF;精度:±10%;额定电压:10V;材质(温度系数):X7R;")
      (fields
        (field (name "MANUFACTURER") "muRata(村田)")
        (field (name "MANUFACTURERPART") "GCM155R71A104KA55D")
      )
      (libsource (lib "altium-import") (part "root_2_GCM155R71A104KA55D_"))
    )
    (comp (ref "C106")
      (value "100nF")
      (footprint "C0402")
      (description "容值:100nF;精度:±10%;额定电压:10V;材质(温度系数):X7R;")
      (fields
        (field (name "MANUFACTURER") "muRata(村田)")
        (field (name "MANUFACTURERPART") "GCM155R71A104KA55D")
      )
      (libsource (lib "altium-import") (part "root_2_GCM155R71A104KA55D_"))
    )
    (comp (ref "C107")
      (value "10nF")
      (footprint "C0402")
      (description "容值:10nF;精度:±10%;额定电压:50V;材质(温度系数):X7R;")
      (fields
        (field (name "MANUFACTURER") "muRata(村田)")
        (field (name "MANUFACTURER PART") "GCM155R71H103KA55D")
      )
      (libsource (lib "altium-import") (part "root_1_GCM155R71H103KA55D_"))
    )
    (comp (ref "C108")
      (value "100nF")
      (footprint "C0402")
      (description "容值:100nF;精度:±10%;额定电压:10V;材质(温度系数):X7R;")
      (fields
        (field (name "MANUFACTURER") "muRata(村田)")
        (field (name "MANUFACTURERPART") "GCM155R71A104KA55D")
      )
      (libsource (lib "altium-import") (part "root_2_GCM155R71A104KA55D_"))
    )
    (comp (ref "C109")
      (value "10nF")
      (footprint "C0402")
      (description "容值:10nF;精度:±10%;额定电压:50V;材质(温度系数):X7R;")
      (fields
        (field (name "MANUFACTURER") "muRata(村田)")
        (field (name "MANUFACTURER PART") "GCM155R71H103KA55D")
      )
      (libsource (lib "altium-import") (part "root_1_GCM155R71H103KA55D_"))
    )
    (comp (ref "C110")
      (value "100nF")
      (footprint "C0402")
      (description "容值:100nF;精度:±10%;额定电压:10V;材质(温度系数):X7R;")
      (fields
        (field (name "MANUFACTURER") "muRata(村田)")
        (field (name "MANUFACTURERPART") "GCM155R71A104KA55D")
      )
      (libsource (lib "altium-import") (part "root_3_GCM155R71A104KA55D_"))
    )
    (comp (ref "C111")
      (value "1uF")
      (footprint "C0402")
      (description "容值:1uF;精度:±10%;额定电压:6.3V;材质(温度系数):X7R;")
      (fields
        (field (name "MANUFACTURER") "muRata(村田)")
        (field (name "MANUFACTURER PART") "GRT155R70J105KE01D")
      )
      (libsource (lib "altium-import") (part "root_1_GRT155R70J105KE01D_"))
    )
    (comp (ref "C112")
      (value "33pF")
      (footprint "C0402")
      (description "容值:33pF;精度:±5%;额定电压:50V;材质(温度系数):NP0;")
      (fields
        (field (name "MANUFACTURER") "YAGEO(国巨)")
        (field (name "MANUFACTURER PART") "CC0402JRNPO9BN330")
      )
      (libsource (lib "altium-import") (part "root_1_CC0402JRNPO9BN330_"))
    )
    (comp (ref "C113")
      (value "33pF")
      (footprint "C0402")
      (description "容值:33pF;精度:±5%;额定电压:50V;材质(温度系数):NP0;")
      (fields
        (field (name "MANUFACTURER") "YAGEO(国巨)")
        (field (name "MANUFACTURER PART") "CC0402JRNPO9BN330")
      )
      (libsource (lib "altium-import") (part "root_1_CC0402JRNPO9BN330_"))
    )
    (comp (ref "C114")
      (value "33pF")
      (footprint "C0402")
      (description "容值:33pF;精度:±5%;额定电压:50V;材质(温度系数):NP0;")
      (fields
        (field (name "MANUFACTURER") "YAGEO(国巨)")
        (field (name "MANUFACTURER PART") "CC0402JRNPO9BN330")
      )
      (libsource (lib "altium-import") (part "root_1_CC0402JRNPO9BN330_"))
    )
    (comp (ref "C115")
      (value "33pF")
      (footprint "C0402")
      (description "容值:33pF;精度:±5%;额定电压:50V;材质(温度系数):NP0;")
      (fields
        (field (name "MANUFACTURER") "YAGEO(国巨)")
        (field (name "MANUFACTURER PART") "CC0402JRNPO9BN330")
      )
      (libsource (lib "altium-import") (part "root_1_CC0402JRNPO9BN330_"))
    )
    (comp (ref "C116")
      (value "33pF")
      (footprint "C0402")
      (description "容值:33pF;精度:±5%;额定电压:50V;材质(温度系数):NP0;")
      (fields
        (field (name "MANUFACTURER") "YAGEO(国巨)")
        (field (name "MANUFACTURER PART") "CC0402JRNPO9BN330")
      )
      (libsource (lib "altium-import") (part "root_1_CC0402JRNPO9BN330_"))
    )
    (comp (ref "C117")
      (value "33pF")
      (footprint "C0402")
      (description "容值:33pF;精度:±5%;额定电压:50V;材质(温度系数):NP0;")
      (fields
        (field (name "MANUFACTURER") "YAGEO(国巨)")
        (field (name "MANUFACTURER PART") "CC0402JRNPO9BN330")
      )
      (libsource (lib "altium-import") (part "root_1_CC0402JRNPO9BN330_"))
    )
    (comp (ref "C118")
      (value "100nF")
      (footprint "C0603")
      (description "容值:100nF;精度:±10%;额定电压:50V;材质(温度系数):X7R;")
      (fields
        (field (name "MANUFACTURER") "muRata(村田)")
        (field (name "MANUFACTURERPART") "GRM188R71H104KA93D")
      )
      (libsource (lib "altium-import") (part "root_1_GRM188R71H104KA93D_"))
    )
    (comp (ref "C119")
      (value "100nF")
      (footprint "C0402")
      (description "容值:100nF;精度:±10%;额定电压:10V;材质(温度系数):X7R;")
      (fields
        (field (name "MANUFACTURER") "muRata(村田)")
        (field (name "MANUFACTURERPART") "GCM155R71A104KA55D")
      )
      (libsource (lib "altium-import") (part "root_2_GCM155R71A104KA55D_"))
    )
    (comp (ref "C120")
      (value "22uF")
      (footprint "C0402")
      (description "容值:22uF;精度:±20%;额定电压:6.3V;材质(温度系数):X5R;")
      (fields
        (field (name "MANUFACTURER") "muRata(村田)")
        (field (name "MANUFACTURERPART") "GRM155R60J226ME11D")
      )
      (libsource (lib "altium-import") (part "root_1_GRM155R60J226ME11D_"))
    )
    (comp (ref "C121")
      (value "22uF")
      (footprint "C0402")
      (description "容值:22uF;精度:±20%;额定电压:6.3V;材质(温度系数):X5R;")
      (fields
        (field (name "MANUFACTURER") "muRata(村田)")
        (field (name "MANUFACTURERPART") "GRM155R60J226ME11D")
      )
      (libsource (lib "altium-import") (part "root_1_GRM155R60J226ME11D_"))
    )
    (comp (ref "C122")
      (value "22uF")
      (footprint "C0402")
      (description "容值:22uF;精度:±20%;额定电压:6.3V;材质(温度系数):X5R;")
      (fields
        (field (name "MANUFACTURER") "muRata(村田)")
        (field (name "MANUFACTURERPART") "GRM155R60J226ME11D")
      )
      (libsource (lib "altium-import") (part "root_1_GRM155R60J226ME11D_"))
    )
    (comp (ref "C123")
      (value "22uF")
      (footprint "C0402")
      (description "容值:22uF;精度:±20%;额定电压:6.3V;材质(温度系数):X5R;")
      (fields
        (field (name "MANUFACTURER") "muRata(村田)")
        (field (name "MANUFACTURERPART") "GRM155R60J226ME11D")
      )
      (libsource (lib "altium-import") (part "root_1_GRM155R60J226ME11D_"))
    )
    (comp (ref "C124")
      (value "100nF")
      (footprint "C0402")
      (description "容值:100nF;精度:±10%;额定电压:10V;材质(温度系数):X7R;")
      (fields
        (field (name "MANUFACTURER") "muRata(村田)")
        (field (name "MANUFACTURERPART") "GCM155R71A104KA55D")
      )
      (libsource (lib "altium-import") (part "root_2_GCM155R71A104KA55D_"))
    )
    (comp (ref "C125")
      (value "22uF")
      (footprint "C0402")
      (description "容值:22uF;精度:±20%;额定电压:6.3V;材质(温度系数):X5R;")
      (fields
        (field (name "MANUFACTURER") "muRata(村田)")
        (field (name "MANUFACTURERPART") "GRM155R60J226ME11D")
      )
      (libsource (lib "altium-import") (part "root_1_GRM155R60J226ME11D_"))
    )
    (comp (ref "C128")
      (value "10uF")
      (footprint "C0805")
      (description "容值:10uF;精度:±10%;额定电压:50V;材质(温度系数):X5R;")
      (fields
        (field (name "MANUFACTURER") "muRata(村田)")
        (field (name "MANUFACTURER PART") "GRM21BR61H106KE43L")
      )
      (libsource (lib "altium-import") (part "root_1_GRM21BR61H106KE43L_"))
    )
    (comp (ref "C129")
      (value "100nF")
      (footprint "C0402")
      (description "容值:100nF;精度:±10%;额定电压:10V;材质(温度系数):X7R;")
      (fields
        (field (name "MANUFACTURER") "muRata(村田)")
        (field (name "MANUFACTURERPART") "GCM155R71A104KA55D")
      )
      (libsource (lib "altium-import") (part "root_2_GCM155R71A104KA55D_"))
    )
    (comp (ref "C132")
      (value "100nF")
      (footprint "C0402")
      (description "容值:100nF;精度:±10%;额定电压:10V;材质(温度系数):X7R;")
      (fields
        (field (name "MANUFACTURER") "muRata(村田)")
        (field (name "MANUFACTURERPART") "GCM155R71A104KA55D")
      )
      (libsource (lib "altium-import") (part "root_2_GCM155R71A104KA55D_"))
    )
    (comp (ref "C133")
      (value "100nF")
      (footprint "C0402")
      (description "容值:100nF;精度:±10%;额定电压:10V;材质(温度系数):X7R;")
      (fields
        (field (name "MANUFACTURER") "muRata(村田)")
        (field (name "MANUFACTURERPART") "GCM155R71A104KA55D")
      )
      (libsource (lib "altium-import") (part "root_2_GCM155R71A104KA55D_"))
    )
    (comp (ref "C135")
      (value "100nF")
      (footprint "C0402")
      (description "容值:100nF;精度:±10%;额定电压:10V;材质(温度系数):X7R;")
      (fields
        (field (name "MANUFACTURER") "muRata(村田)")
        (field (name "MANUFACTURERPART") "GCM155R71A104KA55D")
      )
      (libsource (lib "altium-import") (part "root_2_GCM155R71A104KA55D_"))
    )
    (comp (ref "C136")
      (value "100nF")
      (footprint "C0402")
      (description "容值:100nF;精度:±10%;额定电压:10V;材质(温度系数):X7R;")
      (fields
        (field (name "MANUFACTURER") "muRata(村田)")
        (field (name "MANUFACTURERPART") "GCM155R71A104KA55D")
      )
      (libsource (lib "altium-import") (part "root_2_GCM155R71A104KA55D_"))
    )
    (comp (ref "C141")
      (value "10nF")
      (footprint "C0402")
      (description "容值:10nF;精度:±10%;额定电压:50V;材质(温度系数):X7R;")
      (fields
        (field (name "MANUFACTURER") "muRata(村田)")
        (field (name "MANUFACTURER PART") "GCM155R71H103KA55D")
      )
      (libsource (lib "altium-import") (part "root_1_GCM155R71H103KA55D_"))
    )
    (comp (ref "C142")
      (value "10nF")
      (footprint "C0402")
      (description "容值:10nF;精度:±10%;额定电压:50V;材质(温度系数):X7R;")
      (fields
        (field (name "MANUFACTURER") "muRata(村田)")
        (field (name "MANUFACTURER PART") "GCM155R71H103KA55D")
      )
      (libsource (lib "altium-import") (part "root_1_GCM155R71H103KA55D_"))
    )
    (comp (ref "C143")
      (value "10nF")
      (footprint "C0402")
      (description "容值:10nF;精度:±10%;额定电压:50V;材质(温度系数):X7R;")
      (fields
        (field (name "MANUFACTURER") "muRata(村田)")
        (field (name "MANUFACTURER PART") "GCM155R71H103KA55D")
      )
      (libsource (lib "altium-import") (part "root_1_GCM155R71H103KA55D_"))
    )
    (comp (ref "C144")
      (value "10nF")
      (footprint "C0402")
      (description "容值:10nF;精度:±10%;额定电压:50V;材质(温度系数):X7R;")
      (fields
        (field (name "MANUFACTURER") "muRata(村田)")
        (field (name "MANUFACTURER PART") "GCM155R71H103KA55D")
      )
      (libsource (lib "altium-import") (part "root_1_GCM155R71H103KA55D_"))
    )
    (comp (ref "C145")
      (value "10nF")
      (footprint "C0402")
      (description "容值:10nF;精度:±10%;额定电压:50V;材质(温度系数):X7R;")
      (fields
        (field (name "MANUFACTURER") "muRata(村田)")
        (field (name "MANUFACTURER PART") "GCM155R71H103KA55D")
      )
      (libsource (lib "altium-import") (part "root_1_GCM155R71H103KA55D_"))
    )
    (comp (ref "C146")
      (value "10nF")
      (footprint "C0402")
      (description "容值:10nF;精度:±10%;额定电压:50V;材质(温度系数):X7R;")
      (fields
        (field (name "MANUFACTURER") "muRata(村田)")
        (field (name "MANUFACTURER PART") "GCM155R71H103KA55D")
      )
      (libsource (lib "altium-import") (part "root_1_GCM155R71H103KA55D_"))
    )
    (comp (ref "C147")
      (value "100nF")
      (footprint "C0603")
      (description "容值:100nF;精度:±10%;额定电压:50V;材质(温度系数):X7R;")
      (fields
        (field (name "MANUFACTURER") "muRata(村田)")
        (field (name "MANUFACTURERPART") "GRM188R71H104KA93D")
      )
      (libsource (lib "altium-import") (part "root_1_GRM188R71H104KA93D_"))
    )
    (comp (ref "C148")
      (value "100nF")
      (footprint "C0603")
      (description "容值:100nF;精度:±10%;额定电压:50V;材质(温度系数):X7R;")
      (fields
        (field (name "MANUFACTURER") "muRata(村田)")
        (field (name "MANUFACTURERPART") "GRM188R71H104KA93D")
      )
      (libsource (lib "altium-import") (part "root_1_GRM188R71H104KA93D_"))
    )
    (comp (ref "C149")
      (value "100nF")
      (footprint "C0603")
      (description "容值:100nF;精度:±10%;额定电压:50V;材质(温度系数):X7R;")
      (fields
        (field (name "MANUFACTURER") "muRata(村田)")
        (field (name "MANUFACTURERPART") "GRM188R71H104KA93D")
      )
      (libsource (lib "altium-import") (part "root_1_GRM188R71H104KA93D_"))
    )
    (comp (ref "C150")
      (value "100nF")
      (footprint "C0402")
      (description "容值:100nF;精度:±10%;额定电压:10V;材质(温度系数):X7R;")
      (fields
        (field (name "MANUFACTURER") "muRata(村田)")
        (field (name "MANUFACTURERPART") "GCM155R71A104KA55D")
      )
      (libsource (lib "altium-import") (part "root_2_GCM155R71A104KA55D_"))
    )
    (comp (ref "C153")
      (value "22uF")
      (footprint "CAP-SMD_BD5.0-L5.3-W5.3-FD")
      (description "容值:22uF;精度:±20%;额定电压:50V;纹波电流:165mA@100kHz;等效串联电阻:880mΩ@100kHz;")
      (fields (field (name "MANUFACTURER") "PANASONIC(松下)") (field (name "MANUFACTURER PART") "EEEFT1H220AR"))
      (libsource (lib "altium-import") (part "root_0_EEEFT1H220AR_"))
    )
    (comp (ref "C157")
      (value "100nF")
      (footprint "C0402")
      (description "容值:100nF;精度:±10%;额定电压:10V;材质(温度系数):X7R;")
      (fields
        (field (name "MANUFACTURER") "muRata(村田)")
        (field (name "MANUFACTURERPART") "GCM155R71A104KA55D")
      )
      (libsource (lib "altium-import") (part "root_2_GCM155R71A104KA55D_"))
    )
    (comp (ref "C158")
      (value "100nF")
      (footprint "C0402")
      (description "容值:100nF;精度:±10%;额定电压:10V;材质(温度系数):X7R;")
      (fields
        (field (name "MANUFACTURER") "muRata(村田)")
        (field (name "MANUFACTURERPART") "GCM155R71A104KA55D")
      )
      (libsource (lib "altium-import") (part "root_2_GCM155R71A104KA55D_"))
    )
    (comp (ref "C159")
      (value "100nF")
      (footprint "C0402")
      (description "容值:100nF;精度:±10%;额定电压:10V;材质(温度系数):X7R;")
      (fields
        (field (name "MANUFACTURER") "muRata(村田)")
        (field (name "MANUFACTURERPART") "GCM155R71A104KA55D")
      )
      (libsource (lib "altium-import") (part "root_2_GCM155R71A104KA55D_"))
    )
    (comp (ref "C162")
      (value "100nF")
      (footprint "C0402")
      (description "容值:100nF;精度:±10%;额定电压:10V;材质(温度系数):X7R;")
      (fields
        (field (name "MANUFACTURER") "muRata(村田)")
        (field (name "MANUFACTURERPART") "GCM155R71A104KA55D")
      )
      (libsource (lib "altium-import") (part "root_2_GCM155R71A104KA55D_"))
    )
    (comp (ref "C166")
      (value "100nF")
      (footprint "C0402")
      (description "容值:100nF;精度:±10%;额定电压:10V;材质(温度系数):X7R;")
      (fields
        (field (name "MANUFACTURER") "muRata(村田)")
        (field (name "MANUFACTURER PART") "GCM155R71A104KA55D")
      )
      (libsource (lib "") (part "root_1_GCM155R71A104KA55D__1"))
    )
    (comp (ref "C167")
      (value "10nF")
      (footprint "C0402")
      (description "容值:10nF;精度:±10%;额定电压:50V;材质(温度系数):X7R;")
      (fields
        (field (name "MANUFACTURER") "muRata(村田)")
        (field (name "MANUFACTURER PART") "GCM155R71H103KA55D")
      )
      (libsource (lib "altium-import") (part "root_1_GCM155R71H103KA55D_"))
    )
    (comp (ref "C169")
      (value "10nF")
      (footprint "C0402")
      (description "容值:10nF;精度:±10%;额定电压:50V;材质(温度系数):X7R;")
      (fields
        (field (name "MANUFACTURER") "muRata(村田)")
        (field (name "MANUFACTURER PART") "GCM155R71H103KA55D")
      )
      (libsource (lib "altium-import") (part "root_1_GCM155R71H103KA55D_"))
    )
    (comp (ref "C171")
      (value "10nF")
      (footprint "C0402")
      (description "容值:10nF;精度:±10%;额定电压:50V;材质(温度系数):X7R;")
      (fields
        (field (name "MANUFACTURER") "muRata(村田)")
        (field (name "MANUFACTURER PART") "GCM155R71H103KA55D")
      )
      (libsource (lib "altium-import") (part "root_1_GCM155R71H103KA55D_"))
    )
    (comp (ref "C173")
      (value "100nF")
      (footprint "C0402")
      (description "容值:100nF;精度:±10%;额定电压:10V;材质(温度系数):X7R;")
      (fields
        (field (name "MANUFACTURER") "muRata(村田)")
        (field (name "MANUFACTURERPART") "GCM155R71A104KA55D")
      )
      (libsource (lib "altium-import") (part "root_2_GCM155R71A104KA55D_"))
    )
    (comp (ref "C176")
      (value "10nF")
      (footprint "C0402")
      (description "容值:10nF;精度:±10%;额定电压:50V;材质(温度系数):X7R;")
      (fields
        (field (name "MANUFACTURER") "muRata(村田)")
        (field (name "MANUFACTURER PART") "GCM155R71H103KA55D")
      )
      (libsource (lib "altium-import") (part "root_1_GCM155R71H103KA55D_"))
    )
    (comp (ref "C178")
      (value "22uF")
      (footprint "CAP-SMD_L3.5-W2.8-R-RD")
      (description "容值:22uF;精度:±20%;额定电压:20V;等效串联电阻:90mΩ@100kHz;")
      (fields (field (name "MANUFACTURER") "PANASONIC(松下)") (field (name "MANUFACTURER PART") "20TQC22MYFB"))
      (libsource (lib "altium-import") (part "root_1_20TQC22MYFB_"))
    )
    (comp (ref "C179")
      (value "22uF")
      (footprint "CAP-SMD_L3.5-W2.8-R-RD")
      (description "容值:22uF;精度:±20%;额定电压:20V;等效串联电阻:90mΩ@100kHz;")
      (fields (field (name "MANUFACTURER") "PANASONIC(松下)") (field (name "MANUFACTURER PART") "20TQC22MYFB"))
      (libsource (lib "altium-import") (part "root_1_20TQC22MYFB_"))
    )
    (comp (ref "C180")
      (value "22uF")
      (footprint "CAP-SMD_L3.5-W2.8-R-RD")
      (description "容值:22uF;精度:±20%;额定电压:20V;等效串联电阻:90mΩ@100kHz;")
      (fields (field (name "MANUFACTURER") "PANASONIC(松下)") (field (name "MANUFACTURER PART") "20TQC22MYFB"))
      (libsource (lib "altium-import") (part "root_1_20TQC22MYFB_"))
    )
    (comp (ref "C181")
      (value "22uF")
      (footprint "CAP-SMD_L3.5-W2.8-R-RD")
      (description "容值:22uF;精度:±20%;额定电压:20V;等效串联电阻:90mΩ@100kHz;")
      (fields (field (name "MANUFACTURER") "PANASONIC(松下)") (field (name "MANUFACTURER PART") "20TQC22MYFB"))
      (libsource (lib "altium-import") (part "root_1_20TQC22MYFB_"))
    )
    (comp (ref "C182")
      (value "22uF")
      (footprint "CAP-SMD_L3.5-W2.8-R-RD")
      (description "容值:22uF;精度:±20%;额定电压:20V;等效串联电阻:90mΩ@100kHz;")
      (fields (field (name "MANUFACTURER") "PANASONIC(松下)") (field (name "MANUFACTURER PART") "20TQC22MYFB"))
      (libsource (lib "altium-import") (part "root_1_20TQC22MYFB_"))
    )
    (comp (ref "C183")
      (value "22uF")
      (footprint "CAP-SMD_L3.5-W2.8-R-RD")
      (description "容值:22uF;精度:±20%;额定电压:20V;等效串联电阻:90mΩ@100kHz;")
      (fields (field (name "MANUFACTURER") "PANASONIC(松下)") (field (name "MANUFACTURER PART") "20TQC22MYFB"))
      (libsource (lib "altium-import") (part "root_1_20TQC22MYFB_"))
    )
    (comp (ref "C184")
      (value "22uF")
      (footprint "CAP-SMD_L3.5-W2.8-R-RD")
      (description "容值:22uF;精度:±20%;额定电压:20V;等效串联电阻:90mΩ@100kHz;")
      (fields (field (name "MANUFACTURER") "PANASONIC(松下)") (field (name "MANUFACTURER PART") "20TQC22MYFB"))
      (libsource (lib "altium-import") (part "root_1_20TQC22MYFB_"))
    )
    (comp (ref "C185")
      (value "10nF")
      (footprint "C0402")
      (description "容值:10nF;精度:±10%;额定电压:50V;材质(温度系数):X7R;")
      (fields
        (field (name "MANUFACTURER") "muRata(村田)")
        (field (name "MANUFACTURER PART") "GCM155R71H103KA55D")
      )
      (libsource (lib "altium-import") (part "root_1_GCM155R71H103KA55D_"))
    )
    (comp (ref "C186")
      (value "10nF")
      (footprint "C0402")
      (description "容值:10nF;精度:±10%;额定电压:50V;材质(温度系数):X7R;")
      (fields
        (field (name "MANUFACTURER") "muRata(村田)")
        (field (name "MANUFACTURER PART") "GCM155R71H103KA55D")
      )
      (libsource (lib "altium-import") (part "root_1_GCM155R71H103KA55D_"))
    )
    (comp (ref "C187")
      (value "10nF")
      (footprint "C0402")
      (description "容值:10nF;精度:±10%;额定电压:50V;材质(温度系数):X7R;")
      (fields
        (field (name "MANUFACTURER") "muRata(村田)")
        (field (name "MANUFACTURER PART") "GCM155R71H103KA55D")
      )
      (libsource (lib "altium-import") (part "root_1_GCM155R71H103KA55D_"))
    )
    (comp (ref "C188")
      (value "10nF")
      (footprint "C0402")
      (description "容值:10nF;精度:±10%;额定电压:50V;材质(温度系数):X7R;")
      (fields
        (field (name "MANUFACTURER") "muRata(村田)")
        (field (name "MANUFACTURER PART") "GCM155R71H103KA55D")
      )
      (libsource (lib "altium-import") (part "root_1_GCM155R71H103KA55D_"))
    )
    (comp (ref "C189")
      (value "10nF")
      (footprint "C0402")
      (description "容值:10nF;精度:±10%;额定电压:50V;材质(温度系数):X7R;")
      (fields
        (field (name "MANUFACTURER") "muRata(村田)")
        (field (name "MANUFACTURER PART") "GCM155R71H103KA55D")
      )
      (libsource (lib "altium-import") (part "root_1_GCM155R71H103KA55D_"))
    )
    (comp (ref "C190")
      (value "10nF")
      (footprint "C0402")
      (description "容值:10nF;精度:±10%;额定电压:50V;材质(温度系数):X7R;")
      (fields
        (field (name "MANUFACTURER") "muRata(村田)")
        (field (name "MANUFACTURER PART") "GCM155R71H103KA55D")
      )
      (libsource (lib "altium-import") (part "root_1_GCM155R71H103KA55D_"))
    )
    (comp (ref "C191")
      (value "10nF")
      (footprint "C0402")
      (description "容值:10nF;精度:±10%;额定电压:50V;材质(温度系数):X7R;")
      (fields
        (field (name "MANUFACTURER") "muRata(村田)")
        (field (name "MANUFACTURER PART") "GCM155R71H103KA55D")
      )
      (libsource (lib "altium-import") (part "root_1_GCM155R71H103KA55D_"))
    )
    (comp (ref "C192")
      (value "22uF")
      (footprint "CAP-SMD_BD5.0-L5.3-W5.3-FD")
      (description "容值:22uF;精度:±20%;额定电压:50V;纹波电流:165mA@100kHz;等效串联电阻:880mΩ@100kHz;")
      (fields (field (name "MANUFACTURER") "PANASONIC(松下)") (field (name "MANUFACTURER PART") "EEEFT1H220AR"))
      (libsource (lib "altium-import") (part "root_0_EEEFT1H220AR_"))
    )
    (comp (ref "C193")
      (value "10uF")
      (footprint "C0805")
      (description "容值:10uF;精度:±20%;额定电压:25V;材质(温度系数):X5R;")
      (fields
        (field (name "MANUFACTURER") "muRata(村田)")
        (field (name "MANUFACTURERPART") "GRM21BR61E106MA73L")
      )
      (libsource (lib "altium-import") (part "root_0_GRM21BR61E106MA73L_"))
    )
    (comp (ref "C194")
      (value "22uF")
      (footprint "C0805")
      (description "容值:22uF;精度:±20%;额定电压:10V;材质(温度系数):X5R;")
      (fields
        (field (name "MANUFACTURER") "muRata(村田)")
        (field (name "MANUFACTURERPART") "GRM21BR61A226ME44L")
      )
      (libsource (lib "altium-import") (part "root_1_GRM21BR61A226ME44L_"))
    )
    (comp (ref "C195")
      (value "620pF")
      (footprint "C0603")
      (description "容值:620pF;精度:±2%;额定电压:50V;材质(温度系数):NP0;")
      (fields
        (field (name "MANUFACTURER") "YAGEO(国巨)")
        (field (name "MANUFACTURER PART") "CC0603GRNPO9BN621")
      )
      (libsource (lib "altium-import") (part "root_1_CC0603GRNPO9BN621_"))
    )
    (comp (ref "C196")
      (value "10uF")
      (footprint "C0805")
      (description "容值:10uF;精度:±20%;额定电压:25V;材质(温度系数):X5R;")
      (fields
        (field (name "MANUFACTURER") "muRata(村田)")
        (field (name "MANUFACTURERPART") "GRM21BR61E106MA73L")
      )
      (libsource (lib "altium-import") (part "root_0_GRM21BR61E106MA73L_"))
    )
    (comp (ref "C197")
      (value "22uF")
      (footprint "C0805")
      (description "容值:22uF;精度:±20%;额定电压:10V;材质(温度系数):X5R;")
      (fields
        (field (name "MANUFACTURER") "muRata(村田)")
        (field (name "MANUFACTURERPART") "GRM21BR61A226ME44L")
      )
      (libsource (lib "altium-import") (part "root_1_GRM21BR61A226ME44L_"))
    )
    (comp (ref "C198")
      (value "620pF")
      (footprint "C0603")
      (description "容值:620pF;精度:±2%;额定电压:50V;材质(温度系数):NP0;")
      (fields
        (field (name "MANUFACTURER") "YAGEO(国巨)")
        (field (name "MANUFACTURER PART") "CC0603GRNPO9BN621")
      )
      (libsource (lib "altium-import") (part "root_1_CC0603GRNPO9BN621_"))
    )
    (comp (ref "C199")
      (value "10uF")
      (footprint "C0805")
      (description "容值:10uF;精度:±20%;额定电压:25V;材质(温度系数):X5R;")
      (fields
        (field (name "MANUFACTURER") "muRata(村田)")
        (field (name "MANUFACTURERPART") "GRM21BR61E106MA73L")
      )
      (libsource (lib "altium-import") (part "root_0_GRM21BR61E106MA73L_"))
    )
    (comp (ref "C200")
      (value "10nF")
      (footprint "C0402")
      (description "容值:10nF;精度:±10%;额定电压:50V;材质(温度系数):X7R;")
      (fields
        (field (name "MANUFACTURER") "muRata(村田)")
        (field (name "MANUFACTURER PART") "GCM155R71H103KA55D")
      )
      (libsource (lib "altium-import") (part "root_1_GCM155R71H103KA55D_"))
    )
    (comp (ref "C201")
      (value "8.2nF")
      (footprint "C0402")
      (description "容值:8.2nF;精度:±10%;额定电压:50V;材质(温度系数):X7R;")
      (fields
        (field (name "MANUFACTURER") "muRata(村田)")
        (field (name "MANUFACTURER PART") "GCM155R71H822KA55D")
      )
      (libsource (lib "altium-import") (part "root_1_GCM155R71H822KA55D_"))
    )
    (comp (ref "C202")
      (value "100nF")
      (footprint "C0603")
      (description "容值:100nF;精度:±10%;额定电压:50V;材质(温度系数):X7R;")
      (fields (field (name "MANUFACTURER") "YAGEO(国巨)") (field (name "MANUFACTURERPART") "CC0603KRX7R9BB104"))
      (libsource (lib "altium-import") (part "root_3_CC0603KRX7R9BB104_"))
    )
    (comp (ref "C204")
      (value "22uF")
      (footprint "C1210")
      (description "容值:22uF;精度:±10%;额定电压:25V;材质(温度系数):X7R;")
      (fields
        (field (name "MANUFACTURER") "muRata(村田)")
        (field (name "MANUFACTURER PART") "GRM32ER71E226KE15L")
      )
      (libsource (lib "altium-import") (part "root_1_GRM32ER71E226KE15L_"))
    )
    (comp (ref "C205")
      (value "22uF")
      (footprint "C1210")
      (description "容值:22uF;精度:±10%;额定电压:25V;材质(温度系数):X7R;")
      (fields
        (field (name "MANUFACTURER") "muRata(村田)")
        (field (name "MANUFACTURER PART") "GRM32ER71E226KE15L")
      )
      (libsource (lib "altium-import") (part "root_1_GRM32ER71E226KE15L_"))
    )
    (comp (ref "C206")
      (value "22uF")
      (footprint "C1210")
      (description "容值:22uF;精度:±10%;额定电压:25V;材质(温度系数):X7R;")
      (fields
        (field (name "MANUFACTURER") "muRata(村田)")
        (field (name "MANUFACTURER PART") "GRM32ER71E226KE15L")
      )
      (libsource (lib "altium-import") (part "root_1_GRM32ER71E226KE15L_"))
    )
    (comp (ref "C207")
      (value "22uF")
      (footprint "C1210")
      (description "容值:22uF;精度:±10%;额定电压:25V;材质(温度系数):X7R;")
      (fields
        (field (name "MANUFACTURER") "muRata(村田)")
        (field (name "MANUFACTURER PART") "GRM32ER71E226KE15L")
      )
      (libsource (lib "altium-import") (part "root_1_GRM32ER71E226KE15L_"))
    )
    (comp (ref "C208")
      (value "22uF")
      (footprint "C1210")
      (description "容值:22uF;精度:±10%;额定电压:25V;材质(温度系数):X7R;")
      (fields
        (field (name "MANUFACTURER") "muRata(村田)")
        (field (name "MANUFACTURER PART") "GRM32ER71E226KE15L")
      )
      (libsource (lib "altium-import") (part "root_1_GRM32ER71E226KE15L_"))
    )
    (comp (ref "C209")
      (value "22uF")
      (footprint "C1210")
      (description "容值:22uF;精度:±10%;额定电压:25V;材质(温度系数):X7R;")
      (fields
        (field (name "MANUFACTURER") "muRata(村田)")
        (field (name "MANUFACTURER PART") "GRM32ER71E226KE15L")
      )
      (libsource (lib "altium-import") (part "root_1_GRM32ER71E226KE15L_"))
    )
    (comp (ref "C210")
      (value "100nF")
      (footprint "C0402")
      (description "容值:100nF;精度:±10%;额定电压:10V;材质(温度系数):X7R;")
      (fields
        (field (name "MANUFACTURER") "muRata(村田)")
        (field (name "MANUFACTURERPART") "GCM155R71A104KA55D")
      )
      (libsource (lib "altium-import") (part "root_2_GCM155R71A104KA55D_"))
    )
    (comp (ref "C211")
      (value "22uF")
      (footprint "C1210")
      (description "容值:22uF;精度:±10%;额定电压:25V;材质(温度系数):X7R;")
      (fields
        (field (name "MANUFACTURER") "muRata(村田)")
        (field (name "MANUFACTURER PART") "GRM32ER71E226KE15L")
      )
      (libsource (lib "altium-import") (part "root_1_GRM32ER71E226KE15L_"))
    )
    (comp (ref "C212")
      (value "22uF")
      (footprint "C1210")
      (description "容值:22uF;精度:±10%;额定电压:25V;材质(温度系数):X7R;")
      (fields
        (field (name "MANUFACTURER") "muRata(村田)")
        (field (name "MANUFACTURER PART") "GRM32ER71E226KE15L")
      )
      (libsource (lib "altium-import") (part "root_1_GRM32ER71E226KE15L_"))
    )
    (comp (ref "C213")
      (value "22uF")
      (footprint "C1210")
      (description "容值:22uF;精度:±10%;额定电压:25V;材质(温度系数):X7R;")
      (fields
        (field (name "MANUFACTURER") "muRata(村田)")
        (field (name "MANUFACTURER PART") "GRM32ER71E226KE15L")
      )
      (libsource (lib "altium-import") (part "root_1_GRM32ER71E226KE15L_"))
    )
    (comp (ref "C214")
      (value "22uF")
      (footprint "C1210")
      (description "容值:22uF;精度:±10%;额定电压:25V;材质(温度系数):X7R;")
      (fields
        (field (name "MANUFACTURER") "muRata(村田)")
        (field (name "MANUFACTURER PART") "GRM32ER71E226KE15L")
      )
      (libsource (lib "altium-import") (part "root_1_GRM32ER71E226KE15L_"))
    )
    (comp (ref "C215")
      (value "22uF")
      (footprint "C1210")
      (description "容值:22uF;精度:±10%;额定电压:25V;材质(温度系数):X7R;")
      (fields
        (field (name "MANUFACTURER") "muRata(村田)")
        (field (name "MANUFACTURER PART") "GRM32ER71E226KE15L")
      )
      (libsource (lib "altium-import") (part "root_1_GRM32ER71E226KE15L_"))
    )
    (comp (ref "C216")
      (value "22uF")
      (footprint "C1210")
      (description "容值:22uF;精度:±10%;额定电压:25V;材质(温度系数):X7R;")
      (fields
        (field (name "MANUFACTURER") "muRata(村田)")
        (field (name "MANUFACTURER PART") "GRM32ER71E226KE15L")
      )
      (libsource (lib "altium-import") (part "root_1_GRM32ER71E226KE15L_"))
    )
    (comp (ref "C217")
      (value "100nF")
      (footprint "C0402")
      (description "容值:100nF;精度:±10%;额定电压:10V;材质(温度系数):X7R;")
      (fields
        (field (name "MANUFACTURER") "muRata(村田)")
        (field (name "MANUFACTURERPART") "GCM155R71A104KA55D")
      )
      (libsource (lib "altium-import") (part "root_2_GCM155R71A104KA55D_"))
    )
    (comp (ref "C218")
      (value "100nF")
      (footprint "C0402")
      (description "容值:100nF;精度:±10%;额定电压:10V;材质(温度系数):X7R;")
      (fields
        (field (name "MANUFACTURER") "muRata(村田)")
        (field (name "MANUFACTURERPART") "GCM155R71A104KA55D")
      )
      (libsource (lib "altium-import") (part "root_2_GCM155R71A104KA55D_"))
    )
    (comp (ref "C219")
      (value "100nF")
      (footprint "C0402")
      (description "容值:100nF;精度:±10%;额定电压:10V;材质(温度系数):X7R;")
      (fields
        (field (name "MANUFACTURER") "muRata(村田)")
        (field (name "MANUFACTURERPART") "GCM155R71A104KA55D")
      )
      (libsource (lib "altium-import") (part "root_2_GCM155R71A104KA55D_"))
    )
    (comp (ref "C220")
      (value "100nF")
      (footprint "C0402")
      (description "容值:100nF;精度:±10%;额定电压:10V;材质(温度系数):X7R;")
      (fields
        (field (name "MANUFACTURER") "muRata(村田)")
        (field (name "MANUFACTURERPART") "GCM155R71A104KA55D")
      )
      (libsource (lib "altium-import") (part "root_1_GCM155R71A104KA55D_"))
    )
    (comp (ref "C221")
      (value "100nF")
      (footprint "C0402")
      (description "容值:100nF;精度:±10%;额定电压:10V;材质(温度系数):X7R;")
      (fields
        (field (name "MANUFACTURER") "muRata(村田)")
        (field (name "MANUFACTURERPART") "GCM155R71A104KA55D")
      )
      (libsource (lib "altium-import") (part "root_1_GCM155R71A104KA55D_"))
    )
    (comp (ref "C222")
      (value "100nF")
      (footprint "C0402")
      (description "容值:100nF;精度:±10%;额定电压:10V;材质(温度系数):X7R;")
      (fields
        (field (name "MANUFACTURER") "muRata(村田)")
        (field (name "MANUFACTURERPART") "GCM155R71A104KA55D")
      )
      (libsource (lib "altium-import") (part "root_1_GCM155R71A104KA55D_"))
    )
    (comp (ref "C223")
      (value "100nF")
      (footprint "C0402")
      (description "容值:100nF;精度:±10%;额定电压:10V;材质(温度系数):X7R;")
      (fields
        (field (name "MANUFACTURER") "muRata(村田)")
        (field (name "MANUFACTURERPART") "GCM155R71A104KA55D")
      )
      (libsource (lib "altium-import") (part "root_1_GCM155R71A104KA55D_"))
    )
    (comp (ref "C224")
      (value "100nF")
      (footprint "C0402")
      (description "容值:100nF;精度:±10%;额定电压:10V;材质(温度系数):X7R;")
      (fields
        (field (name "MANUFACTURER") "muRata(村田)")
        (field (name "MANUFACTURERPART") "GCM155R71A104KA55D")
      )
      (libsource (lib "altium-import") (part "root_1_GCM155R71A104KA55D_"))
    )
    (comp (ref "C225")
      (value "100nF")
      (footprint "C0402")
      (description "容值:100nF;精度:±10%;额定电压:10V;材质(温度系数):X7R;")
      (fields
        (field (name "MANUFACTURER") "muRata(村田)")
        (field (name "MANUFACTURERPART") "GCM155R71A104KA55D")
      )
      (libsource (lib "altium-import") (part "root_1_GCM155R71A104KA55D_"))
    )
    (comp (ref "C226")
      (value "100nF")
      (footprint "C0402")
      (description "容值:100nF;精度:±10%;额定电压:10V;材质(温度系数):X7R;")
      (fields
        (field (name "MANUFACTURER") "muRata(村田)")
        (field (name "MANUFACTURERPART") "GCM155R71A104KA55D")
      )
      (libsource (lib "altium-import") (part "root_1_GCM155R71A104KA55D_"))
    )
    (comp (ref "C227")
      (value "100nF")
      (footprint "C0402")
      (description "容值:100nF;精度:±10%;额定电压:10V;材质(温度系数):X7R;")
      (fields
        (field (name "MANUFACTURER") "muRata(村田)")
        (field (name "MANUFACTURERPART") "GCM155R71A104KA55D")
      )
      (libsource (lib "altium-import") (part "root_1_GCM155R71A104KA55D_"))
    )
    (comp (ref "C228")
      (value "100nF")
      (footprint "C0402")
      (description "容值:100nF;精度:±10%;额定电压:10V;材质(温度系数):X7R;")
      (fields
        (field (name "MANUFACTURER") "muRata(村田)")
        (field (name "MANUFACTURERPART") "GCM155R71A104KA55D")
      )
      (libsource (lib "altium-import") (part "root_1_GCM155R71A104KA55D_"))
    )
    (comp (ref "C229")
      (value "100nF")
      (footprint "C0402")
      (description "容值:100nF;精度:±10%;额定电压:10V;材质(温度系数):X7R;")
      (fields
        (field (name "MANUFACTURER") "muRata(村田)")
        (field (name "MANUFACTURERPART") "GCM155R71A104KA55D")
      )
      (libsource (lib "altium-import") (part "root_1_GCM155R71A104KA55D_"))
    )
    (comp (ref "C230")
      (value "100nF")
      (footprint "C0402")
      (description "容值:100nF;精度:±10%;额定电压:10V;材质(温度系数):X7R;")
      (fields
        (field (name "MANUFACTURER") "muRata(村田)")
        (field (name "MANUFACTURERPART") "GCM155R71A104KA55D")
      )
      (libsource (lib "altium-import") (part "root_1_GCM155R71A104KA55D_"))
    )
    (comp (ref "C231")
      (value "100nF")
      (footprint "C0402")
      (description "容值:100nF;精度:±10%;额定电压:10V;材质(温度系数):X7R;")
      (fields
        (field (name "MANUFACTURER") "muRata(村田)")
        (field (name "MANUFACTURERPART") "GCM155R71A104KA55D")
      )
      (libsource (lib "altium-import") (part "root_1_GCM155R71A104KA55D_"))
    )
    (comp (ref "C232")
      (value "100nF")
      (footprint "C0402")
      (description "容值:100nF;精度:±10%;额定电压:10V;材质(温度系数):X7R;")
      (fields
        (field (name "MANUFACTURER") "muRata(村田)")
        (field (name "MANUFACTURERPART") "GCM155R71A104KA55D")
      )
      (libsource (lib "altium-import") (part "root_1_GCM155R71A104KA55D_"))
    )
    (comp (ref "C233")
      (value "100nF")
      (footprint "C0402")
      (description "容值:100nF;精度:±10%;额定电压:10V;材质(温度系数):X7R;")
      (fields
        (field (name "MANUFACTURER") "muRata(村田)")
        (field (name "MANUFACTURERPART") "GCM155R71A104KA55D")
      )
      (libsource (lib "altium-import") (part "root_1_GCM155R71A104KA55D_"))
    )
    (comp (ref "C234")
      (value "100nF")
      (footprint "C0402")
      (description "容值:100nF;精度:±10%;额定电压:10V;材质(温度系数):X7R;")
      (fields
        (field (name "MANUFACTURER") "muRata(村田)")
        (field (name "MANUFACTURERPART") "GCM155R71A104KA55D")
      )
      (libsource (lib "altium-import") (part "root_1_GCM155R71A104KA55D_"))
    )
    (comp (ref "C235")
      (value "100nF")
      (footprint "C0402")
      (description "容值:100nF;精度:±10%;额定电压:10V;材质(温度系数):X7R;")
      (fields
        (field (name "MANUFACTURER") "muRata(村田)")
        (field (name "MANUFACTURERPART") "GCM155R71A104KA55D")
      )
      (libsource (lib "altium-import") (part "root_1_GCM155R71A104KA55D_"))
    )
    (comp (ref "C236")
      (value "100nF")
      (footprint "C0402")
      (description "容值:100nF;精度:±10%;额定电压:10V;材质(温度系数):X7R;")
      (fields
        (field (name "MANUFACTURER") "muRata(村田)")
        (field (name "MANUFACTURERPART") "GCM155R71A104KA55D")
      )
      (libsource (lib "altium-import") (part "root_1_GCM155R71A104KA55D_"))
    )
    (comp (ref "C237")
      (value "100nF")
      (footprint "C0402")
      (description "容值:100nF;精度:±10%;额定电压:10V;材质(温度系数):X7R;")
      (fields
        (field (name "MANUFACTURER") "muRata(村田)")
        (field (name "MANUFACTURERPART") "GCM155R71A104KA55D")
      )
      (libsource (lib "altium-import") (part "root_1_GCM155R71A104KA55D_"))
    )
    (comp (ref "C238")
      (value "100nF")
      (footprint "C0402")
      (description "容值:100nF;精度:±10%;额定电压:10V;材质(温度系数):X7R;")
      (fields
        (field (name "MANUFACTURER") "muRata(村田)")
        (field (name "MANUFACTURERPART") "GCM155R71A104KA55D")
      )
      (libsource (lib "altium-import") (part "root_1_GCM155R71A104KA55D_"))
    )
    (comp (ref "C239")
      (value "100nF")
      (footprint "C0402")
      (description "容值:100nF;精度:±10%;额定电压:10V;材质(温度系数):X7R;")
      (fields
        (field (name "MANUFACTURER") "muRata(村田)")
        (field (name "MANUFACTURERPART") "GCM155R71A104KA55D")
      )
      (libsource (lib "altium-import") (part "root_1_GCM155R71A104KA55D_"))
    )
    (comp (ref "C240")
      (value "100nF")
      (footprint "C0402")
      (description "容值:100nF;精度:±10%;额定电压:10V;材质(温度系数):X7R;")
      (fields
        (field (name "MANUFACTURER") "muRata(村田)")
        (field (name "MANUFACTURERPART") "GCM155R71A104KA55D")
      )
      (libsource (lib "altium-import") (part "root_1_GCM155R71A104KA55D_"))
    )
    (comp (ref "C241")
      (value "100nF")
      (footprint "C0402")
      (description "容值:100nF;精度:±10%;额定电压:10V;材质(温度系数):X7R;")
      (fields
        (field (name "MANUFACTURER") "muRata(村田)")
        (field (name "MANUFACTURERPART") "GCM155R71A104KA55D")
      )
      (libsource (lib "altium-import") (part "root_1_GCM155R71A104KA55D_"))
    )
    (comp (ref "C242")
      (value "100nF")
      (footprint "C0402")
      (description "容值:100nF;精度:±10%;额定电压:10V;材质(温度系数):X7R;")
      (fields
        (field (name "MANUFACTURER") "muRata(村田)")
        (field (name "MANUFACTURERPART") "GCM155R71A104KA55D")
      )
      (libsource (lib "altium-import") (part "root_1_GCM155R71A104KA55D_"))
    )
    (comp (ref "C243")
      (value "100nF")
      (footprint "C0402")
      (description "容值:100nF;精度:±10%;额定电压:10V;材质(温度系数):X7R;")
      (fields
        (field (name "MANUFACTURER") "muRata(村田)")
        (field (name "MANUFACTURERPART") "GCM155R71A104KA55D")
      )
      (libsource (lib "altium-import") (part "root_1_GCM155R71A104KA55D_"))
    )
    (comp (ref "C244")
      (value "100nF")
      (footprint "C0402")
      (description "容值:100nF;精度:±10%;额定电压:10V;材质(温度系数):X7R;")
      (fields
        (field (name "MANUFACTURER") "muRata(村田)")
        (field (name "MANUFACTURERPART") "GCM155R71A104KA55D")
      )
      (libsource (lib "altium-import") (part "root_1_GCM155R71A104KA55D_"))
    )
    (comp (ref "C245")
      (value "100nF")
      (footprint "C0402")
      (description "容值:100nF;精度:±10%;额定电压:10V;材质(温度系数):X7R;")
      (fields
        (field (name "MANUFACTURER") "muRata(村田)")
        (field (name "MANUFACTURERPART") "GCM155R71A104KA55D")
      )
      (libsource (lib "altium-import") (part "root_1_GCM155R71A104KA55D_"))
    )
    (comp (ref "C246")
      (value "100nF")
      (footprint "C0402")
      (description "容值:100nF;精度:±10%;额定电压:10V;材质(温度系数):X7R;")
      (fields
        (field (name "MANUFACTURER") "muRata(村田)")
        (field (name "MANUFACTURERPART") "GCM155R71A104KA55D")
      )
      (libsource (lib "altium-import") (part "root_1_GCM155R71A104KA55D_"))
    )
    (comp (ref "C247")
      (value "100nF")
      (footprint "C0402")
      (description "容值:100nF;精度:±10%;额定电压:10V;材质(温度系数):X7R;")
      (fields
        (field (name "MANUFACTURER") "muRata(村田)")
        (field (name "MANUFACTURERPART") "GCM155R71A104KA55D")
      )
      (libsource (lib "altium-import") (part "root_1_GCM155R71A104KA55D_"))
    )
    (comp (ref "C248")
      (value "100nF")
      (footprint "C0402")
      (description "容值:100nF;精度:±10%;额定电压:10V;材质(温度系数):X7R;")
      (fields
        (field (name "MANUFACTURER") "muRata(村田)")
        (field (name "MANUFACTURERPART") "GCM155R71A104KA55D")
      )
      (libsource (lib "altium-import") (part "root_1_GCM155R71A104KA55D_"))
    )
    (comp (ref "C249")
      (value "100nF")
      (footprint "C0402")
      (description "容值:100nF;精度:±10%;额定电压:10V;材质(温度系数):X7R;")
      (fields
        (field (name "MANUFACTURER") "muRata(村田)")
        (field (name "MANUFACTURERPART") "GCM155R71A104KA55D")
      )
      (libsource (lib "altium-import") (part "root_1_GCM155R71A104KA55D_"))
    )
    (comp (ref "C250")
      (value "100nF")
      (footprint "C0402")
      (description "容值:100nF;精度:±10%;额定电压:10V;材质(温度系数):X7R;")
      (fields
        (field (name "MANUFACTURER") "muRata(村田)")
        (field (name "MANUFACTURERPART") "GCM155R71A104KA55D")
      )
      (libsource (lib "altium-import") (part "root_1_GCM155R71A104KA55D_"))
    )
    (comp (ref "C251")
      (value "100nF")
      (footprint "C0402")
      (description "容值:100nF;精度:±10%;额定电压:10V;材质(温度系数):X7R;")
      (fields
        (field (name "MANUFACTURER") "muRata(村田)")
        (field (name "MANUFACTURERPART") "GCM155R71A104KA55D")
      )
      (libsource (lib "altium-import") (part "root_1_GCM155R71A104KA55D_"))
    )
    (comp (ref "C259")
      (value "100uF")
      (footprint "C1206")
      (description "容值:100uF;精度:±20%;额定电压:10V;材质(温度系数):X5R;")
      (fields
        (field (name "MANUFACTURER") "muRata(村田)")
        (field (name "MANUFACTURER PART") "GRM31CR61A107ME05L")
      )
      (libsource (lib "altium-import") (part "root_1_GRM31CR61A107ME05L_"))
    )
    (comp (ref "C260")
      (value "100uF")
      (footprint "C1206")
      (description "容值:100uF;精度:±20%;额定电压:10V;材质(温度系数):X5R;")
      (fields
        (field (name "MANUFACTURER") "muRata(村田)")
        (field (name "MANUFACTURER PART") "GRM31CR61A107ME05L")
      )
      (libsource (lib "altium-import") (part "root_1_GRM31CR61A107ME05L_"))
    )
    (comp (ref "C261")
      (value "47nF")
      (footprint "C0402")
      (description "容值:47nF;精度:±10%;额定电压:50V;材质(温度系数):X7R;")
      (fields
        (field (name "MANUFACTURER") "muRata(村田)")
        (field (name "MANUFACTURER PART") "GRM155R71H473KE14D")
      )
      (libsource (lib "altium-import") (part "root_1_GRM155R71H473KE14D_"))
    )
    (comp (ref "C262")
      (value "47nF")
      (footprint "C0402")
      (description "容值:47nF;精度:±10%;额定电压:50V;材质(温度系数):X7R;")
      (fields
        (field (name "MANUFACTURER") "muRata(村田)")
        (field (name "MANUFACTURER PART") "GRM155R71H473KE14D")
      )
      (libsource (lib "altium-import") (part "root_1_GRM155R71H473KE14D_"))
    )
    (comp (ref "C263")
      (value "47nF")
      (footprint "C0402")
      (description "容值:47nF;精度:±10%;额定电压:50V;材质(温度系数):X7R;")
      (fields
        (field (name "MANUFACTURER") "muRata(村田)")
        (field (name "MANUFACTURER PART") "GRM155R71H473KE14D")
      )
      (libsource (lib "altium-import") (part "root_1_GRM155R71H473KE14D_"))
    )
    (comp (ref "C264")
      (value "47nF")
      (footprint "C0402")
      (description "容值:47nF;精度:±10%;额定电压:50V;材质(温度系数):X7R;")
      (fields
        (field (name "MANUFACTURER") "muRata(村田)")
        (field (name "MANUFACTURER PART") "GRM155R71H473KE14D")
      )
      (libsource (lib "altium-import") (part "root_1_GRM155R71H473KE14D_"))
    )
    (comp (ref "C265")
      (value "47nF")
      (footprint "C0402")
      (description "容值:47nF;精度:±10%;额定电压:50V;材质(温度系数):X7R;")
      (fields
        (field (name "MANUFACTURER") "muRata(村田)")
        (field (name "MANUFACTURER PART") "GRM155R71H473KE14D")
      )
      (libsource (lib "altium-import") (part "root_1_GRM155R71H473KE14D_"))
    )
    (comp (ref "C266")
      (value "47nF")
      (footprint "C0402")
      (description "容值:47nF;精度:±10%;额定电压:50V;材质(温度系数):X7R;")
      (fields
        (field (name "MANUFACTURER") "muRata(村田)")
        (field (name "MANUFACTURER PART") "GRM155R71H473KE14D")
      )
      (libsource (lib "altium-import") (part "root_1_GRM155R71H473KE14D_"))
    )
    (comp (ref "C267")
      (value "47nF")
      (footprint "C0402")
      (description "容值:47nF;精度:±10%;额定电压:50V;材质(温度系数):X7R;")
      (fields
        (field (name "MANUFACTURER") "muRata(村田)")
        (field (name "MANUFACTURER PART") "GRM155R71H473KE14D")
      )
      (libsource (lib "altium-import") (part "root_1_GRM155R71H473KE14D_"))
    )
    (comp (ref "C268")
      (value "47nF")
      (footprint "C0402")
      (description "容值:47nF;精度:±10%;额定电压:50V;材质(温度系数):X7R;")
      (fields
        (field (name "MANUFACTURER") "muRata(村田)")
        (field (name "MANUFACTURER PART") "GRM155R71H473KE14D")
      )
      (libsource (lib "altium-import") (part "root_1_GRM155R71H473KE14D_"))
    )
    (comp (ref "C269")
      (value "47nF")
      (footprint "C0402")
      (description "容值:47nF;精度:±10%;额定电压:50V;材质(温度系数):X7R;")
      (fields
        (field (name "MANUFACTURER") "muRata(村田)")
        (field (name "MANUFACTURER PART") "GRM155R71H473KE14D")
      )
      (libsource (lib "altium-import") (part "root_1_GRM155R71H473KE14D_"))
    )
    (comp (ref "C270")
      (value "47nF")
      (footprint "C0402")
      (description "容值:47nF;精度:±10%;额定电压:50V;材质(温度系数):X7R;")
      (fields
        (field (name "MANUFACTURER") "muRata(村田)")
        (field (name "MANUFACTURER PART") "GRM155R71H473KE14D")
      )
      (libsource (lib "altium-import") (part "root_1_GRM155R71H473KE14D_"))
    )
    (comp (ref "C271")
      (value "47nF")
      (footprint "C0402")
      (description "容值:47nF;精度:±10%;额定电压:50V;材质(温度系数):X7R;")
      (fields
        (field (name "MANUFACTURER") "muRata(村田)")
        (field (name "MANUFACTURER PART") "GRM155R71H473KE14D")
      )
      (libsource (lib "altium-import") (part "root_1_GRM155R71H473KE14D_"))
    )
    (comp (ref "C272")
      (value "47nF")
      (footprint "C0402")
      (description "容值:47nF;精度:±10%;额定电压:50V;材质(温度系数):X7R;")
      (fields
        (field (name "MANUFACTURER") "muRata(村田)")
        (field (name "MANUFACTURER PART") "GRM155R71H473KE14D")
      )
      (libsource (lib "altium-import") (part "root_1_GRM155R71H473KE14D_"))
    )
    (comp (ref "C273")
      (value "47nF")
      (footprint "C0402")
      (description "容值:47nF;精度:±10%;额定电压:50V;材质(温度系数):X7R;")
      (fields
        (field (name "MANUFACTURER") "muRata(村田)")
        (field (name "MANUFACTURER PART") "GRM155R71H473KE14D")
      )
      (libsource (lib "altium-import") (part "root_1_GRM155R71H473KE14D_"))
    )
    (comp (ref "C274")
      (value "47nF")
      (footprint "C0402")
      (description "容值:47nF;精度:±10%;额定电压:50V;材质(温度系数):X7R;")
      (fields
        (field (name "MANUFACTURER") "muRata(村田)")
        (field (name "MANUFACTURER PART") "GRM155R71H473KE14D")
      )
      (libsource (lib "altium-import") (part "root_1_GRM155R71H473KE14D_"))
    )
    (comp (ref "C275")
      (value "47nF")
      (footprint "C0402")
      (description "容值:47nF;精度:±10%;额定电压:50V;材质(温度系数):X7R;")
      (fields
        (field (name "MANUFACTURER") "muRata(村田)")
        (field (name "MANUFACTURER PART") "GRM155R71H473KE14D")
      )
      (libsource (lib "altium-import") (part "root_1_GRM155R71H473KE14D_"))
    )
    (comp (ref "C276")
      (value "47nF")
      (footprint "C0402")
      (description "容值:47nF;精度:±10%;额定电压:50V;材质(温度系数):X7R;")
      (fields
        (field (name "MANUFACTURER") "muRata(村田)")
        (field (name "MANUFACTURER PART") "GRM155R71H473KE14D")
      )
      (libsource (lib "altium-import") (part "root_1_GRM155R71H473KE14D_"))
    )
    (comp (ref "C277")
      (value "47nF")
      (footprint "C0402")
      (description "容值:47nF;精度:±10%;额定电压:50V;材质(温度系数):X7R;")
      (fields
        (field (name "MANUFACTURER") "muRata(村田)")
        (field (name "MANUFACTURER PART") "GRM155R71H473KE14D")
      )
      (libsource (lib "altium-import") (part "root_1_GRM155R71H473KE14D_"))
    )
    (comp (ref "C278")
      (value "47nF")
      (footprint "C0402")
      (description "容值:47nF;精度:±10%;额定电压:50V;材质(温度系数):X7R;")
      (fields
        (field (name "MANUFACTURER") "muRata(村田)")
        (field (name "MANUFACTURER PART") "GRM155R71H473KE14D")
      )
      (libsource (lib "altium-import") (part "root_1_GRM155R71H473KE14D_"))
    )
    (comp (ref "C279")
      (value "47nF")
      (footprint "C0402")
      (description "容值:47nF;精度:±10%;额定电压:50V;材质(温度系数):X7R;")
      (fields
        (field (name "MANUFACTURER") "muRata(村田)")
        (field (name "MANUFACTURER PART") "GRM155R71H473KE14D")
      )
      (libsource (lib "altium-import") (part "root_1_GRM155R71H473KE14D_"))
    )
    (comp (ref "C280")
      (value "47nF")
      (footprint "C0402")
      (description "容值:47nF;精度:±10%;额定电压:50V;材质(温度系数):X7R;")
      (fields
        (field (name "MANUFACTURER") "muRata(村田)")
        (field (name "MANUFACTURER PART") "GRM155R71H473KE14D")
      )
      (libsource (lib "altium-import") (part "root_1_GRM155R71H473KE14D_"))
    )
    (comp (ref "C281")
      (value "47nF")
      (footprint "C0402")
      (description "容值:47nF;精度:±10%;额定电压:50V;材质(温度系数):X7R;")
      (fields
        (field (name "MANUFACTURER") "muRata(村田)")
        (field (name "MANUFACTURER PART") "GRM155R71H473KE14D")
      )
      (libsource (lib "altium-import") (part "root_1_GRM155R71H473KE14D_"))
    )
    (comp (ref "C282")
      (value "47nF")
      (footprint "C0402")
      (description "容值:47nF;精度:±10%;额定电压:50V;材质(温度系数):X7R;")
      (fields
        (field (name "MANUFACTURER") "muRata(村田)")
        (field (name "MANUFACTURER PART") "GRM155R71H473KE14D")
      )
      (libsource (lib "altium-import") (part "root_1_GRM155R71H473KE14D_"))
    )
    (comp (ref "C283")
      (value "47nF")
      (footprint "C0402")
      (description "容值:47nF;精度:±10%;额定电压:50V;材质(温度系数):X7R;")
      (fields
        (field (name "MANUFACTURER") "muRata(村田)")
        (field (name "MANUFACTURER PART") "GRM155R71H473KE14D")
      )
      (libsource (lib "altium-import") (part "root_1_GRM155R71H473KE14D_"))
    )
    (comp (ref "C284")
      (value "47nF")
      (footprint "C0402")
      (description "容值:47nF;精度:±10%;额定电压:50V;材质(温度系数):X7R;")
      (fields
        (field (name "MANUFACTURER") "muRata(村田)")
        (field (name "MANUFACTURER PART") "GRM155R71H473KE14D")
      )
      (libsource (lib "altium-import") (part "root_1_GRM155R71H473KE14D_"))
    )
    (comp (ref "C285")
      (value "47nF")
      (footprint "C0402")
      (description "容值:47nF;精度:±10%;额定电压:50V;材质(温度系数):X7R;")
      (fields
        (field (name "MANUFACTURER") "muRata(村田)")
        (field (name "MANUFACTURER PART") "GRM155R71H473KE14D")
      )
      (libsource (lib "altium-import") (part "root_1_GRM155R71H473KE14D_"))
    )
    (comp (ref "C286")
      (value "47nF")
      (footprint "C0402")
      (description "容值:47nF;精度:±10%;额定电压:50V;材质(温度系数):X7R;")
      (fields
        (field (name "MANUFACTURER") "muRata(村田)")
        (field (name "MANUFACTURER PART") "GRM155R71H473KE14D")
      )
      (libsource (lib "altium-import") (part "root_1_GRM155R71H473KE14D_"))
    )
    (comp (ref "C287")
      (value "47nF")
      (footprint "C0402")
      (description "容值:47nF;精度:±10%;额定电压:50V;材质(温度系数):X7R;")
      (fields
        (field (name "MANUFACTURER") "muRata(村田)")
        (field (name "MANUFACTURER PART") "GRM155R71H473KE14D")
      )
      (libsource (lib "altium-import") (part "root_1_GRM155R71H473KE14D_"))
    )
    (comp (ref "C288")
      (value "47nF")
      (footprint "C0402")
      (description "容值:47nF;精度:±10%;额定电压:50V;材质(温度系数):X7R;")
      (fields
        (field (name "MANUFACTURER") "muRata(村田)")
        (field (name "MANUFACTURER PART") "GRM155R71H473KE14D")
      )
      (libsource (lib "altium-import") (part "root_1_GRM155R71H473KE14D_"))
    )
    (comp (ref "C289")
      (value "47nF")
      (footprint "C0402")
      (description "容值:47nF;精度:±10%;额定电压:50V;材质(温度系数):X7R;")
      (fields
        (field (name "MANUFACTURER") "muRata(村田)")
        (field (name "MANUFACTURER PART") "GRM155R71H473KE14D")
      )
      (libsource (lib "altium-import") (part "root_1_GRM155R71H473KE14D_"))
    )
    (comp (ref "C290")
      (value "47nF")
      (footprint "C0402")
      (description "容值:47nF;精度:±10%;额定电压:50V;材质(温度系数):X7R;")
      (fields
        (field (name "MANUFACTURER") "muRata(村田)")
        (field (name "MANUFACTURER PART") "GRM155R71H473KE14D")
      )
      (libsource (lib "altium-import") (part "root_1_GRM155R71H473KE14D_"))
    )
    (comp (ref "C291")
      (value "47nF")
      (footprint "C0402")
      (description "容值:47nF;精度:±10%;额定电压:50V;材质(温度系数):X7R;")
      (fields
        (field (name "MANUFACTURER") "muRata(村田)")
        (field (name "MANUFACTURER PART") "GRM155R71H473KE14D")
      )
      (libsource (lib "altium-import") (part "root_1_GRM155R71H473KE14D_"))
    )
    (comp (ref "C292")
      (value "47nF")
      (footprint "C0402")
      (description "容值:47nF;精度:±10%;额定电压:50V;材质(温度系数):X7R;")
      (fields
        (field (name "MANUFACTURER") "muRata(村田)")
        (field (name "MANUFACTURER PART") "GRM155R71H473KE14D")
      )
      (libsource (lib "altium-import") (part "root_1_GRM155R71H473KE14D_"))
    )
    (comp (ref "C293")
      (value "470pF")
      (footprint "C0402")
      (description "容值:470pF;精度:±5%;额定电压:50V;材质(温度系数):X7R;")
      (fields
        (field (name "MANUFACTURER") "muRata(村田)")
        (field (name "MANUFACTURER PART") "GRM155R71H471JA01D")
      )
      (libsource (lib "altium-import") (part "root_1_GRM155R71H471JA01D_"))
    )
    (comp (ref "C294")
      (value "470pF")
      (footprint "C0402")
      (description "容值:470pF;精度:±5%;额定电压:50V;材质(温度系数):X7R;")
      (fields
        (field (name "MANUFACTURER") "muRata(村田)")
        (field (name "MANUFACTURER PART") "GRM155R71H471JA01D")
      )
      (libsource (lib "altium-import") (part "root_1_GRM155R71H471JA01D_"))
    )
    (comp (ref "C295")
      (value "470pF")
      (footprint "C0402")
      (description "容值:470pF;精度:±5%;额定电压:50V;材质(温度系数):X7R;")
      (fields
        (field (name "MANUFACTURER") "muRata(村田)")
        (field (name "MANUFACTURER PART") "GRM155R71H471JA01D")
      )
      (libsource (lib "altium-import") (part "root_1_GRM155R71H471JA01D_"))
    )
    (comp (ref "C296")
      (value "470pF")
      (footprint "C0402")
      (description "容值:470pF;精度:±5%;额定电压:50V;材质(温度系数):X7R;")
      (fields
        (field (name "MANUFACTURER") "muRata(村田)")
        (field (name "MANUFACTURER PART") "GRM155R71H471JA01D")
      )
      (libsource (lib "altium-import") (part "root_1_GRM155R71H471JA01D_"))
    )
    (comp (ref "C297")
      (value "470pF")
      (footprint "C0402")
      (description "容值:470pF;精度:±5%;额定电压:50V;材质(温度系数):X7R;")
      (fields
        (field (name "MANUFACTURER") "muRata(村田)")
        (field (name "MANUFACTURER PART") "GRM155R71H471JA01D")
      )
      (libsource (lib "altium-import") (part "root_1_GRM155R71H471JA01D_"))
    )
    (comp (ref "C298")
      (value "470pF")
      (footprint "C0402")
      (description "容值:470pF;精度:±5%;额定电压:50V;材质(温度系数):X7R;")
      (fields
        (field (name "MANUFACTURER") "muRata(村田)")
        (field (name "MANUFACTURER PART") "GRM155R71H471JA01D")
      )
      (libsource (lib "altium-import") (part "root_1_GRM155R71H471JA01D_"))
    )
    (comp (ref "C299")
      (value "470pF")
      (footprint "C0402")
      (description "容值:470pF;精度:±5%;额定电压:50V;材质(温度系数):X7R;")
      (fields
        (field (name "MANUFACTURER") "muRata(村田)")
        (field (name "MANUFACTURER PART") "GRM155R71H471JA01D")
      )
      (libsource (lib "altium-import") (part "root_1_GRM155R71H471JA01D_"))
    )
    (comp (ref "C300")
      (value "470pF")
      (footprint "C0402")
      (description "容值:470pF;精度:±5%;额定电压:50V;材质(温度系数):X7R;")
      (fields
        (field (name "MANUFACTURER") "muRata(村田)")
        (field (name "MANUFACTURER PART") "GRM155R71H471JA01D")
      )
      (libsource (lib "altium-import") (part "root_1_GRM155R71H471JA01D_"))
    )
    (comp (ref "C301")
      (value "470pF")
      (footprint "C0402")
      (description "容值:470pF;精度:±5%;额定电压:50V;材质(温度系数):X7R;")
      (fields
        (field (name "MANUFACTURER") "muRata(村田)")
        (field (name "MANUFACTURER PART") "GRM155R71H471JA01D")
      )
      (libsource (lib "altium-import") (part "root_1_GRM155R71H471JA01D_"))
    )
    (comp (ref "C302")
      (value "470pF")
      (footprint "C0402")
      (description "容值:470pF;精度:±5%;额定电压:50V;材质(温度系数):X7R;")
      (fields
        (field (name "MANUFACTURER") "muRata(村田)")
        (field (name "MANUFACTURER PART") "GRM155R71H471JA01D")
      )
      (libsource (lib "altium-import") (part "root_1_GRM155R71H471JA01D_"))
    )
    (comp (ref "C303")
      (value "470pF")
      (footprint "C0402")
      (description "容值:470pF;精度:±5%;额定电压:50V;材质(温度系数):X7R;")
      (fields
        (field (name "MANUFACTURER") "muRata(村田)")
        (field (name "MANUFACTURER PART") "GRM155R71H471JA01D")
      )
      (libsource (lib "altium-import") (part "root_1_GRM155R71H471JA01D_"))
    )
    (comp (ref "C304")
      (value "470pF")
      (footprint "C0402")
      (description "容值:470pF;精度:±5%;额定电压:50V;材质(温度系数):X7R;")
      (fields
        (field (name "MANUFACTURER") "muRata(村田)")
        (field (name "MANUFACTURER PART") "GRM155R71H471JA01D")
      )
      (libsource (lib "altium-import") (part "root_1_GRM155R71H471JA01D_"))
    )
    (comp (ref "C305")
      (value "470pF")
      (footprint "C0402")
      (description "容值:470pF;精度:±5%;额定电压:50V;材质(温度系数):X7R;")
      (fields
        (field (name "MANUFACTURER") "muRata(村田)")
        (field (name "MANUFACTURER PART") "GRM155R71H471JA01D")
      )
      (libsource (lib "altium-import") (part "root_1_GRM155R71H471JA01D_"))
    )
    (comp (ref "C306")
      (value "470pF")
      (footprint "C0402")
      (description "容值:470pF;精度:±5%;额定电压:50V;材质(温度系数):X7R;")
      (fields
        (field (name "MANUFACTURER") "muRata(村田)")
        (field (name "MANUFACTURER PART") "GRM155R71H471JA01D")
      )
      (libsource (lib "altium-import") (part "root_1_GRM155R71H471JA01D_"))
    )
    (comp (ref "C307")
      (value "470pF")
      (footprint "C0402")
      (description "容值:470pF;精度:±5%;额定电压:50V;材质(温度系数):X7R;")
      (fields
        (field (name "MANUFACTURER") "muRata(村田)")
        (field (name "MANUFACTURER PART") "GRM155R71H471JA01D")
      )
      (libsource (lib "altium-import") (part "root_1_GRM155R71H471JA01D_"))
    )
    (comp (ref "C308")
      (value "470pF")
      (footprint "C0402")
      (description "容值:470pF;精度:±5%;额定电压:50V;材质(温度系数):X7R;")
      (fields
        (field (name "MANUFACTURER") "muRata(村田)")
        (field (name "MANUFACTURER PART") "GRM155R71H471JA01D")
      )
      (libsource (lib "altium-import") (part "root_1_GRM155R71H471JA01D_"))
    )
    (comp (ref "C309")
      (value "470pF")
      (footprint "C0402")
      (description "容值:470pF;精度:±5%;额定电压:50V;材质(温度系数):X7R;")
      (fields
        (field (name "MANUFACTURER") "muRata(村田)")
        (field (name "MANUFACTURER PART") "GRM155R71H471JA01D")
      )
      (libsource (lib "altium-import") (part "root_1_GRM155R71H471JA01D_"))
    )
    (comp (ref "C310")
      (value "470pF")
      (footprint "C0402")
      (description "容值:470pF;精度:±5%;额定电压:50V;材质(温度系数):X7R;")
      (fields
        (field (name "MANUFACTURER") "muRata(村田)")
        (field (name "MANUFACTURER PART") "GRM155R71H471JA01D")
      )
      (libsource (lib "altium-import") (part "root_1_GRM155R71H471JA01D_"))
    )
    (comp (ref "C311")
      (value "470pF")
      (footprint "C0402")
      (description "容值:470pF;精度:±5%;额定电压:50V;材质(温度系数):X7R;")
      (fields
        (field (name "MANUFACTURER") "muRata(村田)")
        (field (name "MANUFACTURER PART") "GRM155R71H471JA01D")
      )
      (libsource (lib "altium-import") (part "root_1_GRM155R71H471JA01D_"))
    )
    (comp (ref "C312")
      (value "22uF")
      (footprint "C1210")
      (description "容值:22uF;精度:±10%;额定电压:25V;材质(温度系数):X7R;")
      (fields
        (field (name "MANUFACTURER") "muRata(村田)")
        (field (name "MANUFACTURER PART") "GRM32ER71E226KE15L")
      )
      (libsource (lib "altium-import") (part "root_1_GRM32ER71E226KE15L_"))
    )
    (comp (ref "C313")
      (value "22uF")
      (footprint "C1210")
      (description "容值:22uF;精度:±10%;额定电压:25V;材质(温度系数):X7R;")
      (fields
        (field (name "MANUFACTURER") "muRata(村田)")
        (field (name "MANUFACTURER PART") "GRM32ER71E226KE15L")
      )
      (libsource (lib "altium-import") (part "root_1_GRM32ER71E226KE15L_"))
    )
    (comp (ref "CN2")
      (value "2.54-2*5P简牛")
      (footprint "IDC-TH_10P-P2.54_C5665")
      (description "连接器类型:简牛座;间距:2.54mm;结构:2x5P;封装形式:直插;行距:2.54mm;排数:2;每排PIN数:5;触头材质:-;触头镀层:-;")
      (fields (field (name "MANUFACTURER") "BOOMELE(博穆精密)"))
      (libsource (lib "altium-import") (part "root_0_2.54-2*5P简牛_"))
    )
    (comp (ref "D1")
      (value "BAT54S,215")
      (footprint "SOT-23-3_L3.0-W1.7-P0.95-LS2.9-BR")
      (description "二极管配置:1对串联式;正向压降(Vf):800mV@100mA;直流反向耐压(Vr):30V;平均整流电流(Io):200mA;")
      (fields (field (name "MANUFACTURER") "Nexperia(安世)"))
      (libsource (lib "altium-import") (part "root_1_BAT54S,215_"))
    )
    (comp (ref "D2")
      (value "BAT54S,215")
      (footprint "SOT-23-3_L3.0-W1.7-P0.95-LS2.9-BR")
      (description "二极管配置:1对串联式;正向压降(Vf):800mV@100mA;直流反向耐压(Vr):30V;平均整流电流(Io):200mA;")
      (fields (field (name "MANUFACTURER") "Nexperia(安世)"))
      (libsource (lib "altium-import") (part "root_1_BAT54S,215_"))
    )
    (comp (ref "D3")
      (value "BAT54S,215")
      (footprint "SOT-23-3_L3.0-W1.7-P0.95-LS2.9-BR")
      (description "二极管配置:1对串联式;正向压降(Vf):800mV@100mA;直流反向耐压(Vr):30V;平均整流电流(Io):200mA;")
      (fields (field (name "MANUFACTURER") "Nexperia(安世)"))
      (libsource (lib "altium-import") (part "root_1_BAT54S,215_"))
    )
    (comp (ref "D4")
      (value "BAT54S,215")
      (footprint "SOT-23-3_L3.0-W1.7-P0.95-LS2.9-BR")
      (description "二极管配置:1对串联式;正向压降(Vf):800mV@100mA;直流反向耐压(Vr):30V;平均整流电流(Io):200mA;")
      (fields (field (name "MANUFACTURER") "Nexperia(安世)"))
      (libsource (lib "altium-import") (part "root_1_BAT54S,215_"))
    )
    (comp (ref "D5")
      (value "SS14")
      (footprint "SMA_L4.2-W2.6-LS5.3-RD")
      (description "二极管配置:独立式;正向压降(Vf):550mV@1A;直流反向耐压(Vr):40V;平均整流电流(Io):1A;")
      (fields (field (name "MANUFACTURER") "MDD"))
      (libsource (lib "altium-import") (part "root_2_SS14_C2480_"))
    )
    (comp (ref "D6")
      (value "IP4220CZ6")
      (footprint "SOT-23-6_L2.9-W1.6-P0.95-LS2.7-BL")
      (fields (field (name "MANUFACTURER") "UMW(友台半导体)"))
      (libsource (lib "altium-import") (part "root_0_IP4220CZ6_"))
    )
    (comp (ref "D7")
      (value "RClamp0524P.TCT")
      (footprint "SLP2510P8_L2.5-W1.0-P0.50-BL")
      (description "反向截止电压(Vrwm):5V;最大钳位电压:15V;峰值脉冲电流(Ipp)@10/1000us:5A@8/20us;击穿电压:6V;")
      (fields (field (name "MANUFACTURER") "SEMTECH"))
      (libsource (lib "altium-import") (part "root_0_RClamp0524P.TCT_"))
    )
    (comp (ref "D8")
      (value "RClamp0524P.TCT")
      (footprint "SLP2510P8_L2.5-W1.0-P0.50-BL")
      (description "反向截止电压(Vrwm):5V;最大钳位电压:15V;峰值脉冲电流(Ipp)@10/1000us:5A@8/20us;击穿电压:6V;")
      (fields (field (name "MANUFACTURER") "SEMTECH"))
      (libsource (lib "altium-import") (part "root_0_RClamp0524P.TCT_"))
    )
    (comp (ref "D11")
      (value "SS14")
      (footprint "SMA_L4.2-W2.6-LS5.3-RD")
      (description "二极管配置:独立式;正向压降(Vf):550mV@1A;直流反向耐压(Vr):40V;平均整流电流(Io):1A;")
      (fields (field (name "MANUFACTURER") "MDD"))
      (libsource (lib "altium-import") (part "root_2_SS14_C2480_"))
    )
    (comp (ref "D12")
      (value "IP4220CZ6")
      (footprint "SOT-23-6_L2.9-W1.6-P0.95-LS2.7-BL")
      (fields (field (name "MANUFACTURER") "UMW(友台半导体)"))
      (libsource (lib "altium-import") (part "root_0_IP4220CZ6_"))
    )
    (comp (ref "D13")
      (value "RClamp0524P.TCT")
      (footprint "SLP2510P8_L2.5-W1.0-P0.50-BL")
      (description "反向截止电压(Vrwm):5V;最大钳位电压:15V;峰值脉冲电流(Ipp)@10/1000us:5A@8/20us;击穿电压:6V;")
      (fields (field (name "MANUFACTURER") "SEMTECH"))
      (libsource (lib "altium-import") (part "root_0_RClamp0524P.TCT_"))
    )
    (comp (ref "D14")
      (value "RClamp0524P.TCT")
      (footprint "SLP2510P8_L2.5-W1.0-P0.50-BL")
      (description "反向截止电压(Vrwm):5V;最大钳位电压:15V;峰值脉冲电流(Ipp)@10/1000us:5A@8/20us;击穿电压:6V;")
      (fields (field (name "MANUFACTURER") "SEMTECH"))
      (libsource (lib "altium-import") (part "root_0_RClamp0524P.TCT_"))
    )
    (comp (ref "D16")
      (value "IP4220CZ6")
      (footprint "SOT-23-6_L2.9-W1.6-P0.95-LS2.7-BL")
      (fields (field (name "MANUFACTURER") "UMW(友台半导体)"))
      (libsource (lib "altium-import") (part "root_0_IP4220CZ6_"))
    )
    (comp (ref "D17")
      (value "B230A-13-F")
      (footprint "SMA_L4.4-W2.6-LS5.0-RD")
      (description "正向压降(Vf):500mV@2A;直流反向耐压(Vr):30V;平均整流电流(Io):2A;")
      (fields (field (name "MANUFACTURER") "DIODES(美台)"))
      (libsource (lib "altium-import") (part "root_0_B230A-13-F_"))
    )
    (comp (ref "D20")
      (value "BZT52H-B5V6,115")
      (footprint "SOD-123F_L2.6-W1.6-LS3.5-RD")
      (description "二极管配置:独立式;稳压值(标称值):5.6V;稳压值(范围):5.49V~5.71V;功率:375mW;精度:±2%;")
      (fields (field (name "MANUFACTURER") "Nexperia(安世)") (field (name "TOLERANCE") "±2%"))
      (libsource (lib "altium-import") (part "root_3_BZT52H-B5V6,115_"))
    )
    (comp (ref "D21")
      (value "BZT52H-B5V6,115")
      (footprint "SOD-123F_L2.6-W1.6-LS3.5-RD")
      (description "二极管配置:独立式;稳压值(标称值):5.6V;稳压值(范围):5.49V~5.71V;功率:375mW;精度:±2%;")
      (fields (field (name "MANUFACTURER") "Nexperia(安世)") (field (name "TOLERANCE") "±2%"))
      (libsource (lib "altium-import") (part "root_3_BZT52H-B5V6,115_"))
    )
    (comp (ref "D22")
      (value "BAT54A,215")
      (footprint "SOT-23-3_L3.0-W1.7-P0.95-LS2.9-BR")
      (description "二极管配置:1对共阳极;直流反向耐压(Vr):30V;平均整流电流(Io):200mA;")
      (fields (field (name "MANUFACTURER") "Nexperia(安世)"))
      (libsource (lib "altium-import") (part "root_3_BAT54A,215_"))
    )
    (comp (ref "D23")
      (value "BAT54A,215")
      (footprint "SOT-23-3_L3.0-W1.7-P0.95-LS2.9-BR")
      (description "二极管配置:1对共阳极;直流反向耐压(Vr):30V;平均整流电流(Io):200mA;")
      (fields (field (name "MANUFACTURER") "Nexperia(安世)"))
      (libsource (lib "altium-import") (part "root_3_BAT54A,215_"))
    )
    (comp (ref "D24")
      (value "BAT54A,215")
      (footprint "SOT-23-3_L3.0-W1.7-P0.95-LS2.9-BR")
      (description "二极管配置:1对共阳极;直流反向耐压(Vr):30V;平均整流电流(Io):200mA;")
      (fields (field (name "MANUFACTURER") "Nexperia(安世)"))
      (libsource (lib "altium-import") (part "root_3_BAT54A,215_"))
    )
    (comp (ref "D25")
      (value "BAT54A,215")
      (footprint "SOT-23-3_L3.0-W1.7-P0.95-LS2.9-BR")
      (description "二极管配置:1对共阳极;直流反向耐压(Vr):30V;平均整流电流(Io):200mA;")
      (fields (field (name "MANUFACTURER") "Nexperia(安世)"))
      (libsource (lib "altium-import") (part "root_3_BAT54A,215_"))
    )
    (comp (ref "DC3")
      (value "DC-091-A250")
      (footprint "DC-IN-TH_DC-091-A250")
      (description "连接器类型:DC电源插座;安装方式:弯插;触点内径:2.5mm;触点外径:6.45mm;额定电流:5A;额定电压:24V;工作温度范围:-30℃~+70℃;")
      (fields (field (name "MANUFACTURER") "XUNPU(讯普)"))
      (libsource (lib "altium-import") (part "root_0_mirrored_DC-091-A250_"))
    )
    (comp (ref "DSUB1")
      (value "DZ11A51-H8R1-4F")
      (footprint "DSUB-TH_DZ11A5X-H8R1-4F")
      (description "连接器类型:D-Sub;公母:母;总PIN位数:15P;安装方式:弯插;排数:3;额定电流:2A;工作温度范围:-20℃~+85℃;")
      (fields (field (name "MANUFACTURER") "FOXCONN(富士康)"))
      (libsource (lib "altium-import") (part "root_0_DZ11A51-H8R1-4F_"))
    )
    (comp (ref "F1")
      (value "1812L200THPR")
      (footprint "F1812")
      (description "最大电压:8V;最大电流:100A;保持电流:2A;跳闸电流:3.5A;")
      (fields (field (name "MANUFACTURER") "Littelfuse(美国力特)"))
      (libsource (lib "altium-import") (part "root_0_1812L200THPR_"))
    )
    (comp (ref "F2")
      (value "1812L300MR")
      (footprint "F1812")
      (description "最大电压:6V;最大电流:100A;保持电流:3A;跳闸电流:5A;")
      (fields (field (name "MANUFACTURER") "Littelfuse(美国力特)"))
      (libsource (lib "altium-import") (part "root_0_1812L300MR_"))
    )
    (comp (ref "L1")
      (value "GZ2012D601TF")
      (footprint "L0805")
      (description "标称阻抗@测试频率:600Ω@100MHz;误差:±25%;直流电阻(RDC):300mΩ;")
      (fields (field (name "MANUFACTURER") "Sunlord(顺络)") (field (name "TOLERANCE") "±25%"))
      (libsource (lib "altium-import") (part "root_0_GZ2012D601TF_"))
    )
    (comp (ref "L2")
      (value "BLM18RK601SN1D")
      (footprint "L0603")
      (description "标称阻抗@测试频率:600Ω@100MHz;误差:±25%;直流电阻(RDC):600mΩ;")
      (fields (field (name "MANUFACTURER") "muRata(村田)") (field (name "TOLERANCE") "±25%"))
      (libsource (lib "altium-import") (part "root_0_BLM18RK601SN1D_"))
    )
    (comp (ref "L3")
      (value "BLM18RK601SN1D")
      (footprint "L0603")
      (description "标称阻抗@测试频率:600Ω@100MHz;误差:±25%;直流电阻(RDC):600mΩ;")
      (fields (field (name "MANUFACTURER") "muRata(村田)") (field (name "TOLERANCE") "±25%"))
      (libsource (lib "altium-import") (part "root_0_BLM18RK601SN1D_"))
    )
    (comp (ref "L4")
      (value "BLM18RK601SN1D")
      (footprint "L0603")
      (description "标称阻抗@测试频率:600Ω@100MHz;误差:±25%;直流电阻(RDC):600mΩ;")
      (fields (field (name "MANUFACTURER") "muRata(村田)") (field (name "TOLERANCE") "±25%"))
      (libsource (lib "altium-import") (part "root_0_BLM18RK601SN1D_"))
    )
    (comp (ref "L5")
      (value "BLM18RK601SN1D")
      (footprint "L0603")
      (description "标称阻抗@测试频率:600Ω@100MHz;误差:±25%;直流电阻(RDC):600mΩ;")
      (fields (field (name "MANUFACTURER") "muRata(村田)") (field (name "TOLERANCE") "±25%"))
      (libsource (lib "altium-import") (part "root_0_BLM18RK601SN1D_"))
    )
    (comp (ref "L6")
      (value "BLM18RK601SN1D")
      (footprint "L0603")
      (description "标称阻抗@测试频率:600Ω@100MHz;误差:±25%;直流电阻(RDC):600mΩ;")
      (fields (field (name "MANUFACTURER") "muRata(村田)") (field (name "TOLERANCE") "±25%"))
      (libsource (lib "altium-import") (part "root_0_BLM18RK601SN1D_"))
    )
    (comp (ref "L7")
      (value "BLM18RK601SN1D")
      (footprint "L0603")
      (description "标称阻抗@测试频率:600Ω@100MHz;误差:±25%;直流电阻(RDC):600mΩ;")
      (fields (field (name "MANUFACTURER") "muRata(村田)") (field (name "TOLERANCE") "±25%"))
      (libsource (lib "altium-import") (part "root_0_BLM18RK601SN1D_"))
    )
    (comp (ref "L8")
      (value "BLM18RK601SN1D")
      (footprint "L0603")
      (description "标称阻抗@测试频率:600Ω@100MHz;误差:±25%;直流电阻(RDC):600mΩ;")
      (fields (field (name "MANUFACTURER") "muRata(村田)") (field (name "TOLERANCE") "±25%"))
      (libsource (lib "altium-import") (part "root_0_BLM18RK601SN1D_"))
    )
    (comp (ref "L22")
      (value "2.2uH")
      (footprint "IND-SMD_L7.0-W6.6")
      (description "精度:±20%;电感值:2.2uH;直流电阻(DCR):15mΩ;额定电流:9.5A;")
      (fields (field (name "MANUFACTURER") "Sunlord(顺络)") (field (name "MANUFACTURERPART") "MWSA0603S-2R2MT"))
      (libsource (lib "altium-import") (part "root_0_MWSA0603S-2R2MT_"))
    )
    (comp (ref "L23")
      (value "BLM18SG121TN1D")
      (footprint "L0603")
      (description "标称阻抗@测试频率:120Ω@100MHz;误差:±25%;直流电阻(RDC):25mΩ;")
      (fields (field (name "MANUFACTURER") "muRata(村田)") (field (name "TOLERANCE") "±25%"))
      (libsource (lib "altium-import") (part "root_0_BLM18SG121TN1D_"))
    )
    (comp (ref "L24")
      (value "2.2uH")
      (footprint "IND-SMD_L7.0-W6.6")
      (description "精度:±20%;电感值:2.2uH;直流电阻(DCR):15mΩ;额定电流:9.5A;")
      (fields (field (name "MANUFACTURER") "Sunlord(顺络)") (field (name "MANUFACTURERPART") "MWSA0603S-2R2MT"))
      (libsource (lib "altium-import") (part "root_0_MWSA0603S-2R2MT_"))
    )
    (comp (ref "L25")
      (value "BLM18SG121TN1D")
      (footprint "L0603")
      (description "标称阻抗@测试频率:120Ω@100MHz;误差:±25%;直流电阻(RDC):25mΩ;")
      (fields (field (name "MANUFACTURER") "muRata(村田)") (field (name "TOLERANCE") "±25%"))
      (libsource (lib "altium-import") (part "root_0_BLM18SG121TN1D_"))
    )
    (comp (ref "L26")
      (value "2.2uH")
      (footprint "IND-SMD_L7.0-W6.6")
      (description "精度:±20%;电感值:2.2uH;直流电阻(DCR):15mΩ;额定电流:9.5A;")
      (fields (field (name "MANUFACTURER") "Sunlord(顺络)") (field (name "MANUFACTURERPART") "MWSA0603S-2R2MT"))
      (libsource (lib "altium-import") (part "root_0_MWSA0603S-2R2MT_"))
    )
    (comp (ref "L27")
      (value "BLM18SG121TN1D")
      (footprint "L0603")
      (description "标称阻抗@测试频率:120Ω@100MHz;误差:±25%;直流电阻(RDC):25mΩ;")
      (fields (field (name "MANUFACTURER") "muRata(村田)") (field (name "TOLERANCE") "±25%"))
      (libsource (lib "altium-import") (part "root_0_BLM18SG121TN1D_"))
    )
    (comp (ref "L28")
      (value "2.2uH")
      (footprint "IND-SMD_L7.0-W6.6")
      (description "电感值:2.2uH;精度:±20%;额定电流:9.5A;饱和电流(Isat):10A;类型:一体成型电感;")
      (fields (field (name "MANUFACTURER") "cjiang(长江微电)") (field (name "MANUFACTURERPART") "FXL0630-2R2-M"))
      (libsource (lib "altium-import") (part "root_0_FXL0630-2R2-M_"))
    )
    (comp (ref "L29")
      (value "2.2uH")
      (footprint "IND-SMD_L7.0-W6.6")
      (description "电感值:2.2uH;精度:±20%;额定电流:9.5A;饱和电流(Isat):10A;类型:一体成型电感;")
      (fields (field (name "MANUFACTURER") "cjiang(长江微电)") (field (name "MANUFACTURERPART") "FXL0630-2R2-M"))
      (libsource (lib "altium-import") (part "root_0_FXL0630-2R2-M_"))
    )
    (comp (ref "L30")
      (value "2.2uH")
      (footprint "IND-SMD_L7.0-W6.6")
      (description "电感值:2.2uH;精度:±20%;额定电流:9.5A;饱和电流(Isat):10A;类型:一体成型电感;")
      (fields (field (name "MANUFACTURER") "cjiang(长江微电)") (field (name "MANUFACTURERPART") "FXL0630-2R2-M"))
      (libsource (lib "altium-import") (part "root_0_FXL0630-2R2-M_"))
    )
    (comp (ref "L31")
      (value "2.2uH")
      (footprint "IND-SMD_L7.0-W6.6")
      (description "电感值:2.2uH;精度:±20%;额定电流:9.5A;饱和电流(Isat):10A;类型:一体成型电感;")
      (fields (field (name "MANUFACTURER") "cjiang(长江微电)") (field (name "MANUFACTURERPART") "FXL0630-2R2-M"))
      (libsource (lib "altium-import") (part "root_0_FXL0630-2R2-M_"))
    )
    (comp (ref "L32")
      (value "2.2uH")
      (footprint "IND-SMD_L7.0-W6.6")
      (description "电感值:2.2uH;精度:±20%;额定电流:9.5A;饱和电流(Isat):10A;类型:一体成型电感;")
      (fields (field (name "MANUFACTURER") "cjiang(长江微电)") (field (name "MANUFACTURERPART") "FXL0630-2R2-M"))
      (libsource (lib "altium-import") (part "root_0_FXL0630-2R2-M_"))
    )
    (comp (ref "L33")
      (value "BLM18RK601SN1D")
      (footprint "L0603")
      (description "标称阻抗@测试频率:600Ω@100MHz;误差:±25%;直流电阻(RDC):600mΩ;")
      (fields (field (name "MANUFACTURER") "muRata(村田)") (field (name "TOLERANCE") "±25%"))
      (libsource (lib "altium-import") (part "root_0_BLM18RK601SN1D_"))
    )
    (comp (ref "L34")
      (value "2.2uH")
      (footprint "IND-SMD_L7.0-W6.6")
      (description "电感值:2.2uH;精度:±20%;额定电流:9.5A;饱和电流(Isat):10A;类型:一体成型电感;")
      (fields (field (name "MANUFACTURER") "cjiang(长江微电)") (field (name "MANUFACTURERPART") "FXL0630-2R2-M"))
      (libsource (lib "altium-import") (part "root_0_FXL0630-2R2-M_"))
    )
    (comp (ref "LED1")
      (value "19-22/R6GHC-A32/2T")
      (footprint "LED-ARRAY-SMD_4P-L1.9-W1.6-BL-CW")
      (description "发光颜色:红色,翠绿色;")
      (fields (field (name "MANUFACTURER") "EVERLIGHT(亿光)"))
      (libsource (lib "altium-import") (part "root_2_19-22/R6GHC-A32/2T_"))
    )
    (comp (ref "Q1")
      (value "2N7002")
      (footprint "SOT-23-3_L2.9-W1.3-P1.90-LS2.4-BR")
      (fields (field (name "MANUFACTURER") "CJ(江苏长电/长晶)"))
      (libsource (lib "altium-import") (part "root_3_2N7002_C8545_"))
    )
    (comp (ref "Q2")
      (value "2N7002")
      (footprint "SOT-23-3_L2.9-W1.3-P1.90-LS2.4-BR")
      (fields (field (name "MANUFACTURER") "CJ(江苏长电/长晶)"))
      (libsource (lib "altium-import") (part "root_3_2N7002_C8545_"))
    )
    (comp (ref "Q3")
      (value "2N7002")
      (footprint "SOT-23-3_L2.9-W1.3-P1.90-LS2.4-BR")
      (fields (field (name "MANUFACTURER") "CJ(江苏长电/长晶)"))
      (libsource (lib "altium-import") (part "root_3_mirrored_2N7002_C8545_"))
    )
    (comp (ref "Q4")
      (value "2N7002")
      (footprint "SOT-23-3_L2.9-W1.3-P1.90-LS2.4-BR")
      (fields (field (name "MANUFACTURER") "CJ(江苏长电/长晶)"))
      (libsource (lib "altium-import") (part "root_3_mirrored_2N7002_C8545_"))
    )
    (comp (ref "Q5")
      (value "2N7002")
      (footprint "SOT-23-3_L2.9-W1.3-P1.90-LS2.4-BR")
      (fields (field (name "MANUFACTURER") "CJ(江苏长电/长晶)"))
      (libsource (lib "altium-import") (part "root_0_mirrored_2N7002_C8545_"))
    )
    (comp (ref "Q6")
      (value "2N7002")
      (footprint "SOT-23-3_L2.9-W1.3-P1.90-LS2.4-BR")
      (fields (field (name "MANUFACTURER") "CJ(江苏长电/长晶)"))
      (libsource (lib "altium-import") (part "root_0_mirrored_2N7002_C8545_"))
    )
    (comp (ref "Q7")
      (value "2N7002")
      (footprint "SOT-23-3_L2.9-W1.3-P1.90-LS2.4-BR")
      (fields (field (name "MANUFACTURER") "CJ(江苏长电/长晶)"))
      (libsource (lib "altium-import") (part "root_3_2N7002_C8545_"))
    )
    (comp (ref "Q8")
      (value "2N7002")
      (footprint "SOT-23-3_L2.9-W1.3-P1.90-LS2.4-BR")
      (fields (field (name "MANUFACTURER") "CJ(江苏长电/长晶)"))
      (libsource (lib "altium-import") (part "root_3_2N7002_C8545_"))
    )
    (comp (ref "Q9")
      (value "2N7002")
      (footprint "SOT-23-3_L2.9-W1.3-P1.90-LS2.4-BR")
      (fields (field (name "MANUFACTURER") "CJ(江苏长电/长晶)"))
      (libsource (lib "altium-import") (part "root_0_mirrored_2N7002_C8545_"))
    )
    (comp (ref "Q10")
      (value "2N7002")
      (footprint "SOT-23-3_L2.9-W1.3-P1.90-LS2.4-BR")
      (fields (field (name "MANUFACTURER") "CJ(江苏长电/长晶)"))
      (libsource (lib "altium-import") (part "root_0_mirrored_2N7002_C8545_"))
    )
    (comp (ref "Q11")
      (value "2N7002")
      (footprint "SOT-23-3_L2.9-W1.3-P1.90-LS2.4-BR")
      (fields (field (name "MANUFACTURER") "CJ(江苏长电/长晶)"))
      (libsource (lib "altium-import") (part "root_3_2N7002_C8545_"))
    )
    (comp (ref "Q12")
      (value "2N7002")
      (footprint "SOT-23-3_L2.9-W1.3-P1.90-LS2.4-BR")
      (fields (field (name "MANUFACTURER") "CJ(江苏长电/长晶)"))
      (libsource (lib "altium-import") (part "root_3_2N7002_C8545_"))
    )
    (comp (ref "Q13")
      (value "2N7002")
      (footprint "SOT-23-3_L2.9-W1.3-P1.90-LS2.4-BR")
      (fields (field (name "MANUFACTURER") "CJ(江苏长电/长晶)"))
      (libsource (lib "altium-import") (part "root_0_2N7002_C8545_"))
    )
    (comp (ref "Q14")
      (value "2N7002")
      (footprint "SOT-23-3_L2.9-W1.3-P1.90-LS2.4-BR")
      (fields (field (name "MANUFACTURER") "CJ(江苏长电/长晶)"))
      (libsource (lib "altium-import") (part "root_0_2N7002_C8545_"))
    )
    (comp (ref "Q15")
      (value "2N7002")
      (footprint "SOT-23-3_L2.9-W1.3-P1.90-LS2.4-BR")
      (fields (field (name "MANUFACTURER") "CJ(江苏长电/长晶)"))
      (libsource (lib "altium-import") (part "root_0_2N7002_C8545_"))
    )
    (comp (ref "Q16")
      (value "2N7002")
      (footprint "SOT-23-3_L2.9-W1.3-P1.90-LS2.4-BR")
      (fields (field (name "MANUFACTURER") "CJ(江苏长电/长晶)"))
      (libsource (lib "altium-import") (part "root_0_2N7002_C8545_"))
    )
    (comp (ref "R1")
      (value "4.7kΩ")
      (footprint "R0402")
      (description "电阻类型:厚膜电阻;阻值:4.7kΩ;精度:±1%;功率:62.5mW;最大工作电压:50V;温度系数:±100ppm/℃;")
      (fields (field (name "MANUFACTURER") "YAGEO(国巨)") (field (name "MANUFACTURERPART") "RC0402FR-074K7L"))
      (libsource (lib "altium-import") (part "root_0_RC0402FR-074K7L_"))
    )
    (comp (ref "R2")
      (value "4.7kΩ")
      (footprint "R0402")
      (description "电阻类型:厚膜电阻;阻值:4.7kΩ;精度:±1%;功率:62.5mW;最大工作电压:50V;温度系数:±100ppm/℃;")
      (fields (field (name "MANUFACTURER") "YAGEO(国巨)") (field (name "MANUFACTURERPART") "RC0402FR-074K7L"))
      (libsource (lib "altium-import") (part "root_0_RC0402FR-074K7L_"))
    )
    (comp (ref "R5")
      (value "4.7kΩ")
      (footprint "R0402")
      (description "电阻类型:厚膜电阻;阻值:4.7kΩ;精度:±1%;功率:62.5mW;最大工作电压:50V;温度系数:±100ppm/℃;")
      (fields (field (name "MANUFACTURER") "YAGEO(国巨)") (field (name "MANUFACTURERPART") "RC0402FR-074K7L"))
      (libsource (lib "altium-import") (part "root_1_RC0402FR-074K7L_"))
    )
    (comp (ref "R6")
      (value "33Ω")
      (footprint "R0402")
      (description "电阻类型:厚膜电阻;阻值:33Ω;精度:±1%;功率:62.5mW;最大工作电压:50V;温度系数:±100ppm/℃;")
      (fields (field (name "MANUFACTURER") "YAGEO(国巨)") (field (name "MANUFACTURERPART") "RC0402FR-0733RL"))
      (libsource (lib "altium-import") (part "root_0_RC0402FR-0733RL_"))
    )
    (comp (ref "R7")
      (value "33Ω")
      (footprint "R0402")
      (description "电阻类型:厚膜电阻;阻值:33Ω;精度:±1%;功率:62.5mW;最大工作电压:50V;温度系数:±100ppm/℃;")
      (fields (field (name "MANUFACTURER") "YAGEO(国巨)") (field (name "MANUFACTURERPART") "RC0402FR-0733RL"))
      (libsource (lib "altium-import") (part "root_0_RC0402FR-0733RL_"))
    )
    (comp (ref "R11")
      (value "33Ω")
      (footprint "R0402")
      (description "电阻类型:厚膜电阻;阻值:33Ω;精度:±1%;功率:62.5mW;最大工作电压:50V;温度系数:±100ppm/℃;")
      (fields (field (name "MANUFACTURER") "YAGEO(国巨)") (field (name "MANUFACTURERPART") "RC0402FR-0733RL"))
      (libsource (lib "altium-import") (part "root_0_RC0402FR-0733RL_"))
    )
    (comp (ref "R12")
      (value "33Ω")
      (footprint "R0402")
      (description "电阻类型:厚膜电阻;阻值:33Ω;精度:±1%;功率:62.5mW;最大工作电压:50V;温度系数:±100ppm/℃;")
      (fields (field (name "MANUFACTURER") "YAGEO(国巨)") (field (name "MANUFACTURERPART") "RC0402FR-0733RL"))
      (libsource (lib "altium-import") (part "root_0_RC0402FR-0733RL_"))
    )
    (comp (ref "R13")
      (value "33Ω")
      (footprint "R0402")
      (description "电阻类型:厚膜电阻;阻值:33Ω;精度:±1%;功率:62.5mW;最大工作电压:50V;温度系数:±100ppm/℃;")
      (fields (field (name "MANUFACTURER") "YAGEO(国巨)") (field (name "MANUFACTURERPART") "RC0402FR-0733RL"))
      (libsource (lib "altium-import") (part "root_0_RC0402FR-0733RL_"))
    )
    (comp (ref "R14")
      (value "33Ω")
      (footprint "R0402")
      (description "电阻类型:厚膜电阻;阻值:33Ω;精度:±1%;功率:62.5mW;最大工作电压:50V;温度系数:±100ppm/℃;")
      (fields (field (name "MANUFACTURER") "YAGEO(国巨)") (field (name "MANUFACTURERPART") "RC0402FR-0733RL"))
      (libsource (lib "altium-import") (part "root_0_RC0402FR-0733RL_"))
    )
    (comp (ref "R15")
      (value "4.7kΩ")
      (footprint "R0402")
      (description "电阻类型:厚膜电阻;阻值:4.7kΩ;精度:±1%;功率:62.5mW;最大工作电压:50V;温度系数:±100ppm/℃;")
      (fields (field (name "MANUFACTURER") "YAGEO(国巨)") (field (name "MANUFACTURERPART") "RC0402FR-074K7L"))
      (libsource (lib "altium-import") (part "root_1_RC0402FR-074K7L_"))
    )
    (comp (ref "R16")
      (value "4.7kΩ")
      (footprint "R0402")
      (description "电阻类型:厚膜电阻;阻值:4.7kΩ;精度:±1%;功率:62.5mW;最大工作电压:50V;温度系数:±100ppm/℃;")
      (fields (field (name "MANUFACTURER") "YAGEO(国巨)") (field (name "MANUFACTURERPART") "RC0402FR-074K7L"))
      (libsource (lib "altium-import") (part "root_1_RC0402FR-074K7L_"))
    )
    (comp (ref "R17")
      (value "4.7kΩ")
      (footprint "R0402")
      (description "电阻类型:厚膜电阻;阻值:4.7kΩ;精度:±1%;功率:62.5mW;最大工作电压:50V;温度系数:±100ppm/℃;")
      (fields (field (name "MANUFACTURER") "YAGEO(国巨)") (field (name "MANUFACTURERPART") "RC0402FR-074K7L"))
      (libsource (lib "altium-import") (part "root_1_RC0402FR-074K7L_"))
    )
    (comp (ref "R18")
      (value "300Ω")
      (footprint "R0402")
      (description "电阻类型:厚膜电阻;阻值:300Ω;精度:±1%;功率:62.5mW;最大工作电压:50V;温度系数:±100ppm/℃;")
      (fields (field (name "MANUFACTURER") "YAGEO(国巨)") (field (name "MANUFACTURERPART") "RC0402FR-07300RL"))
      (libsource (lib "altium-import") (part "root_1_RC0402FR-07300RL_"))
    )
    (comp (ref "R19")
      (value "33Ω")
      (footprint "R0402")
      (description "电阻类型:厚膜电阻;阻值:33Ω;精度:±1%;功率:62.5mW;最大工作电压:50V;温度系数:±100ppm/℃;")
      (fields (field (name "MANUFACTURER") "YAGEO(国巨)") (field (name "MANUFACTURERPART") "RC0402FR-0733RL"))
      (libsource (lib "altium-import") (part "root_0_RC0402FR-0733RL_"))
    )
    (comp (ref "R20")
      (value "33Ω")
      (footprint "R0402")
      (description "电阻类型:厚膜电阻;阻值:33Ω;精度:±1%;功率:62.5mW;最大工作电压:50V;温度系数:±100ppm/℃;")
      (fields (field (name "MANUFACTURER") "YAGEO(国巨)") (field (name "MANUFACTURERPART") "RC0402FR-0733RL"))
      (libsource (lib "altium-import") (part "root_0_RC0402FR-0733RL_"))
    )
    (comp (ref "R21")
      (value "33Ω")
      (footprint "R0402")
      (description "电阻类型:厚膜电阻;阻值:33Ω;精度:±1%;功率:62.5mW;最大工作电压:50V;温度系数:±100ppm/℃;")
      (fields (field (name "MANUFACTURER") "YAGEO(国巨)") (field (name "MANUFACTURERPART") "RC0402FR-0733RL"))
      (libsource (lib "altium-import") (part "root_0_RC0402FR-0733RL_"))
    )
    (comp (ref "R22")
      (value "33Ω")
      (footprint "R0402")
      (description "电阻类型:厚膜电阻;阻值:33Ω;精度:±1%;功率:62.5mW;最大工作电压:50V;温度系数:±100ppm/℃;")
      (fields (field (name "MANUFACTURER") "YAGEO(国巨)") (field (name "MANUFACTURERPART") "RC0402FR-0733RL"))
      (libsource (lib "altium-import") (part "root_0_RC0402FR-0733RL_"))
    )
    (comp (ref "R23")
      (value "4.7kΩ")
      (footprint "R0402")
      (description "电阻类型:厚膜电阻;阻值:4.7kΩ;精度:±1%;功率:62.5mW;最大工作电压:50V;温度系数:±100ppm/℃;")
      (fields (field (name "MANUFACTURER") "YAGEO(国巨)") (field (name "MANUFACTURERPART") "RC0402FR-074K7L"))
      (libsource (lib "altium-import") (part "root_1_RC0402FR-074K7L_"))
    )
    (comp (ref "R24")
      (value "100kΩ")
      (footprint "R0402")
      (description "电阻类型:厚膜电阻;阻值:100kΩ;精度:±1%;功率:62.5mW;最大工作电压:50V;温度系数:±100ppm/℃;")
      (fields (field (name "MANUFACTURER") "YAGEO(国巨)") (field (name "MANUFACTURERPART") "RC0402FR-07100KL"))
      (libsource (lib "altium-import") (part "root_1_RC0402FR-07100KL_"))
    )
    (comp (ref "R25")
      (value "100kΩ")
      (footprint "R0402")
      (description "电阻类型:厚膜电阻;阻值:100kΩ;精度:±1%;功率:62.5mW;最大工作电压:50V;温度系数:±100ppm/℃;")
      (fields (field (name "MANUFACTURER") "YAGEO(国巨)") (field (name "MANUFACTURERPART") "RC0402FR-07100KL"))
      (libsource (lib "altium-import") (part "root_1_RC0402FR-07100KL_"))
    )
    (comp (ref "R26")
      (value "240Ω")
      (footprint "R0402")
      (description "电阻类型:厚膜电阻;阻值:240Ω;精度:±1%;功率:62.5mW;最大工作电压:50V;温度系数:±100ppm/℃;")
      (fields (field (name "MANUFACTURER") "YAGEO(国巨)") (field (name "MANUFACTURERPART") "RC0402FR-07240RL"))
      (libsource (lib "altium-import") (part "root_0_RC0402FR-07240RL_"))
    )
    (comp (ref "R27")
      (value "51Ω")
      (footprint "R0402")
      (description "电阻类型:厚膜电阻;阻值:51Ω;精度:±1%;功率:62.5mW;最大工作电压:50V;温度系数:±100ppm/℃;")
      (fields (field (name "MANUFACTURER") "YAGEO(国巨)") (field (name "MANUFACTURERPART") "RC0402FR-0751RL"))
      (libsource (lib "altium-import") (part "root_0_RC0402FR-0751RL_"))
    )
    (comp (ref "R29")
      (value "51Ω")
      (footprint "R0402")
      (description "电阻类型:厚膜电阻;阻值:51Ω;精度:±1%;功率:62.5mW;最大工作电压:50V;温度系数:±100ppm/℃;")
      (fields (field (name "MANUFACTURER") "YAGEO(国巨)") (field (name "MANUFACTURERPART") "RC0402FR-0751RL"))
      (libsource (lib "altium-import") (part "root_0_RC0402FR-0751RL_"))
    )
    (comp (ref "R30")
      (value "51Ω")
      (footprint "R0402")
      (description "电阻类型:厚膜电阻;阻值:51Ω;精度:±1%;功率:62.5mW;最大工作电压:50V;温度系数:±100ppm/℃;")
      (fields (field (name "MANUFACTURER") "YAGEO(国巨)") (field (name "MANUFACTURERPART") "RC0402FR-0751RL"))
      (libsource (lib "altium-import") (part "root_0_RC0402FR-0751RL_"))
    )
    (comp (ref "R32")
      (value "51Ω")
      (footprint "R0402")
      (description "电阻类型:厚膜电阻;阻值:51Ω;精度:±1%;功率:62.5mW;最大工作电压:50V;温度系数:±100ppm/℃;")
      (fields (field (name "MANUFACTURER") "YAGEO(国巨)") (field (name "MANUFACTURERPART") "RC0402FR-0751RL"))
      (libsource (lib "altium-import") (part "root_0_RC0402FR-0751RL_"))
    )
    (comp (ref "R33")
      (value "51Ω")
      (footprint "R0402")
      (description "电阻类型:厚膜电阻;阻值:51Ω;精度:±1%;功率:62.5mW;最大工作电压:50V;温度系数:±100ppm/℃;")
      (fields (field (name "MANUFACTURER") "YAGEO(国巨)") (field (name "MANUFACTURERPART") "RC0402FR-0751RL"))
      (libsource (lib "altium-import") (part "root_0_RC0402FR-0751RL_"))
    )
    (comp (ref "R34")
      (value "51Ω")
      (footprint "R0402")
      (description "电阻类型:厚膜电阻;阻值:51Ω;精度:±1%;功率:62.5mW;最大工作电压:50V;温度系数:±100ppm/℃;")
      (fields (field (name "MANUFACTURER") "YAGEO(国巨)") (field (name "MANUFACTURERPART") "RC0402FR-0751RL"))
      (libsource (lib "altium-import") (part "root_0_RC0402FR-0751RL_"))
    )
    (comp (ref "R35")
      (value "51Ω")
      (footprint "R0402")
      (description "电阻类型:厚膜电阻;阻值:51Ω;精度:±1%;功率:62.5mW;最大工作电压:50V;温度系数:±100ppm/℃;")
      (fields (field (name "MANUFACTURER") "YAGEO(国巨)") (field (name "MANUFACTURERPART") "RC0402FR-0751RL"))
      (libsource (lib "altium-import") (part "root_0_RC0402FR-0751RL_"))
    )
    (comp (ref "R36")
      (value "51Ω")
      (footprint "R0402")
      (description "电阻类型:厚膜电阻;阻值:51Ω;精度:±1%;功率:62.5mW;最大工作电压:50V;温度系数:±100ppm/℃;")
      (fields (field (name "MANUFACTURER") "YAGEO(国巨)") (field (name "MANUFACTURERPART") "RC0402FR-0751RL"))
      (libsource (lib "altium-import") (part "root_0_RC0402FR-0751RL_"))
    )
    (comp (ref "R37")
      (value "51Ω")
      (footprint "R0402")
      (description "电阻类型:厚膜电阻;阻值:51Ω;精度:±1%;功率:62.5mW;最大工作电压:50V;温度系数:±100ppm/℃;")
      (fields (field (name "MANUFACTURER") "YAGEO(国巨)") (field (name "MANUFACTURERPART") "RC0402FR-0751RL"))
      (libsource (lib "altium-import") (part "root_0_RC0402FR-0751RL_"))
    )
    (comp (ref "R38")
      (value "51Ω")
      (footprint "R0402")
      (description "电阻类型:厚膜电阻;阻值:51Ω;精度:±1%;功率:62.5mW;最大工作电压:50V;温度系数:±100ppm/℃;")
      (fields (field (name "MANUFACTURER") "YAGEO(国巨)") (field (name "MANUFACTURERPART") "RC0402FR-0751RL"))
      (libsource (lib "altium-import") (part "root_0_RC0402FR-0751RL_"))
    )
    (comp (ref "R39")
      (value "51Ω")
      (footprint "R0402")
      (description "电阻类型:厚膜电阻;阻值:51Ω;精度:±1%;功率:62.5mW;最大工作电压:50V;温度系数:±100ppm/℃;")
      (fields (field (name "MANUFACTURER") "YAGEO(国巨)") (field (name "MANUFACTURERPART") "RC0402FR-0751RL"))
      (libsource (lib "altium-import") (part "root_0_RC0402FR-0751RL_"))
    )
    (comp (ref "R40")
      (value "51Ω")
      (footprint "R0402")
      (description "电阻类型:厚膜电阻;阻值:51Ω;精度:±1%;功率:62.5mW;最大工作电压:50V;温度系数:±100ppm/℃;")
      (fields (field (name "MANUFACTURER") "YAGEO(国巨)") (field (name "MANUFACTURERPART") "RC0402FR-0751RL"))
      (libsource (lib "altium-import") (part "root_0_RC0402FR-0751RL_"))
    )
    (comp (ref "R41")
      (value "51Ω")
      (footprint "R0402")
      (description "电阻类型:厚膜电阻;阻值:51Ω;精度:±1%;功率:62.5mW;最大工作电压:50V;温度系数:±100ppm/℃;")
      (fields (field (name "MANUFACTURER") "YAGEO(国巨)") (field (name "MANUFACTURERPART") "RC0402FR-0751RL"))
      (libsource (lib "altium-import") (part "root_0_RC0402FR-0751RL_"))
    )
    (comp (ref "R42")
      (value "51Ω")
      (footprint "R0402")
      (description "电阻类型:厚膜电阻;阻值:51Ω;精度:±1%;功率:62.5mW;最大工作电压:50V;温度系数:±100ppm/℃;")
      (fields (field (name "MANUFACTURER") "YAGEO(国巨)") (field (name "MANUFACTURERPART") "RC0402FR-0751RL"))
      (libsource (lib "altium-import") (part "root_0_RC0402FR-0751RL_"))
    )
    (comp (ref "R43")
      (value "51Ω")
      (footprint "R0402")
      (description "电阻类型:厚膜电阻;阻值:51Ω;精度:±1%;功率:62.5mW;最大工作电压:50V;温度系数:±100ppm/℃;")
      (fields (field (name "MANUFACTURER") "YAGEO(国巨)") (field (name "MANUFACTURERPART") "RC0402FR-0751RL"))
      (libsource (lib "altium-import") (part "root_0_RC0402FR-0751RL_"))
    )
    (comp (ref "R44")
      (value "51Ω")
      (footprint "R0402")
      (description "电阻类型:厚膜电阻;阻值:51Ω;精度:±1%;功率:62.5mW;最大工作电压:50V;温度系数:±100ppm/℃;")
      (fields (field (name "MANUFACTURER") "YAGEO(国巨)") (field (name "MANUFACTURERPART") "RC0402FR-0751RL"))
      (libsource (lib "altium-import") (part "root_0_RC0402FR-0751RL_"))
    )
    (comp (ref "R45")
      (value "51Ω")
      (footprint "R0402")
      (description "电阻类型:厚膜电阻;阻值:51Ω;精度:±1%;功率:62.5mW;最大工作电压:50V;温度系数:±100ppm/℃;")
      (fields (field (name "MANUFACTURER") "YAGEO(国巨)") (field (name "MANUFACTURERPART") "RC0402FR-0751RL"))
      (libsource (lib "altium-import") (part "root_0_RC0402FR-0751RL_"))
    )
    (comp (ref "R46")
      (value "51Ω")
      (footprint "R0402")
      (description "电阻类型:厚膜电阻;阻值:51Ω;精度:±1%;功率:62.5mW;最大工作电压:50V;温度系数:±100ppm/℃;")
      (fields (field (name "MANUFACTURER") "YAGEO(国巨)") (field (name "MANUFACTURERPART") "RC0402FR-0751RL"))
      (libsource (lib "altium-import") (part "root_0_RC0402FR-0751RL_"))
    )
    (comp (ref "R47")
      (value "51Ω")
      (footprint "R0402")
      (description "电阻类型:厚膜电阻;阻值:51Ω;精度:±1%;功率:62.5mW;最大工作电压:50V;温度系数:±100ppm/℃;")
      (fields (field (name "MANUFACTURER") "YAGEO(国巨)") (field (name "MANUFACTURERPART") "RC0402FR-0751RL"))
      (libsource (lib "altium-import") (part "root_0_RC0402FR-0751RL_"))
    )
    (comp (ref "R48")
      (value "51Ω")
      (footprint "R0402")
      (description "电阻类型:厚膜电阻;阻值:51Ω;精度:±1%;功率:62.5mW;最大工作电压:50V;温度系数:±100ppm/℃;")
      (fields (field (name "MANUFACTURER") "YAGEO(国巨)") (field (name "MANUFACTURERPART") "RC0402FR-0751RL"))
      (libsource (lib "altium-import") (part "root_0_RC0402FR-0751RL_"))
    )
    (comp (ref "R49")
      (value "51Ω")
      (footprint "R0402")
      (description "电阻类型:厚膜电阻;阻值:51Ω;精度:±1%;功率:62.5mW;最大工作电压:50V;温度系数:±100ppm/℃;")
      (fields (field (name "MANUFACTURER") "YAGEO(国巨)") (field (name "MANUFACTURERPART") "RC0402FR-0751RL"))
      (libsource (lib "altium-import") (part "root_0_RC0402FR-0751RL_"))
    )
    (comp (ref "R50")
      (value "51Ω")
      (footprint "R0402")
      (description "电阻类型:厚膜电阻;阻值:51Ω;精度:±1%;功率:62.5mW;最大工作电压:50V;温度系数:±100ppm/℃;")
      (fields (field (name "MANUFACTURER") "YAGEO(国巨)") (field (name "MANUFACTURERPART") "RC0402FR-0751RL"))
      (libsource (lib "altium-import") (part "root_0_RC0402FR-0751RL_"))
    )
    (comp (ref "R51")
      (value "4.7kΩ")
      (footprint "R0402")
      (description "电阻类型:厚膜电阻;阻值:4.7kΩ;精度:±1%;功率:62.5mW;最大工作电压:50V;温度系数:±100ppm/℃;")
      (fields (field (name "MANUFACTURER") "YAGEO(国巨)") (field (name "MANUFACTURERPART") "RC0402FR-074K7L"))
      (libsource (lib "altium-import") (part "root_0_RC0402FR-074K7L_"))
    )
    (comp (ref "R52")
      (value "4.7kΩ")
      (footprint "R0402")
      (description "电阻类型:厚膜电阻;阻值:4.7kΩ;精度:±1%;功率:62.5mW;最大工作电压:50V;温度系数:±100ppm/℃;")
      (fields (field (name "MANUFACTURER") "YAGEO(国巨)") (field (name "MANUFACTURERPART") "RC0402FR-074K7L"))
      (libsource (lib "altium-import") (part "root_0_RC0402FR-074K7L_"))
    )
    (comp (ref "R53")
      (value "240Ω")
      (footprint "R0402")
      (description "电阻类型:厚膜电阻;阻值:240Ω;精度:±1%;功率:62.5mW;最大工作电压:50V;温度系数:±100ppm/℃;")
      (fields (field (name "MANUFACTURER") "YAGEO(国巨)") (field (name "MANUFACTURERPART") "RC0402FR-07240RL"))
      (libsource (lib "altium-import") (part "root_0_RC0402FR-07240RL_"))
    )
    (comp (ref "R54")
      (value "51Ω")
      (footprint "R0402")
      (description "电阻类型:厚膜电阻;阻值:51Ω;精度:±1%;功率:62.5mW;最大工作电压:50V;温度系数:±100ppm/℃;")
      (fields (field (name "MANUFACTURER") "YAGEO(国巨)") (field (name "MANUFACTURERPART") "RC0402FR-0751RL"))
      (libsource (lib "altium-import") (part "root_0_RC0402FR-0751RL_"))
    )
    (comp (ref "R56")
      (value "51Ω")
      (footprint "R0402")
      (description "电阻类型:厚膜电阻;阻值:51Ω;精度:±1%;功率:62.5mW;最大工作电压:50V;温度系数:±100ppm/℃;")
      (fields (field (name "MANUFACTURER") "YAGEO(国巨)") (field (name "MANUFACTURERPART") "RC0402FR-0751RL"))
      (libsource (lib "altium-import") (part "root_0_RC0402FR-0751RL_"))
    )
    (comp (ref "R57")
      (value "51Ω")
      (footprint "R0402")
      (description "电阻类型:厚膜电阻;阻值:51Ω;精度:±1%;功率:62.5mW;最大工作电压:50V;温度系数:±100ppm/℃;")
      (fields (field (name "MANUFACTURER") "YAGEO(国巨)") (field (name "MANUFACTURERPART") "RC0402FR-0751RL"))
      (libsource (lib "altium-import") (part "root_0_RC0402FR-0751RL_"))
    )
    (comp (ref "R59")
      (value "51Ω")
      (footprint "R0402")
      (description "电阻类型:厚膜电阻;阻值:51Ω;精度:±1%;功率:62.5mW;最大工作电压:50V;温度系数:±100ppm/℃;")
      (fields (field (name "MANUFACTURER") "YAGEO(国巨)") (field (name "MANUFACTURERPART") "RC0402FR-0751RL"))
      (libsource (lib "altium-import") (part "root_0_RC0402FR-0751RL_"))
    )
    (comp (ref "R60")
      (value "51Ω")
      (footprint "R0402")
      (description "电阻类型:厚膜电阻;阻值:51Ω;精度:±1%;功率:62.5mW;最大工作电压:50V;温度系数:±100ppm/℃;")
      (fields (field (name "MANUFACTURER") "YAGEO(国巨)") (field (name "MANUFACTURERPART") "RC0402FR-0751RL"))
      (libsource (lib "altium-import") (part "root_0_RC0402FR-0751RL_"))
    )
    (comp (ref "R61")
      (value "51Ω")
      (footprint "R0402")
      (description "电阻类型:厚膜电阻;阻值:51Ω;精度:±1%;功率:62.5mW;最大工作电压:50V;温度系数:±100ppm/℃;")
      (fields (field (name "MANUFACTURER") "YAGEO(国巨)") (field (name "MANUFACTURERPART") "RC0402FR-0751RL"))
      (libsource (lib "altium-import") (part "root_0_RC0402FR-0751RL_"))
    )
    (comp (ref "R62")
      (value "51Ω")
      (footprint "R0402")
      (description "电阻类型:厚膜电阻;阻值:51Ω;精度:±1%;功率:62.5mW;最大工作电压:50V;温度系数:±100ppm/℃;")
      (fields (field (name "MANUFACTURER") "YAGEO(国巨)") (field (name "MANUFACTURERPART") "RC0402FR-0751RL"))
      (libsource (lib "altium-import") (part "root_0_RC0402FR-0751RL_"))
    )
    (comp (ref "R63")
      (value "51Ω")
      (footprint "R0402")
      (description "电阻类型:厚膜电阻;阻值:51Ω;精度:±1%;功率:62.5mW;最大工作电压:50V;温度系数:±100ppm/℃;")
      (fields (field (name "MANUFACTURER") "YAGEO(国巨)") (field (name "MANUFACTURERPART") "RC0402FR-0751RL"))
      (libsource (lib "altium-import") (part "root_0_RC0402FR-0751RL_"))
    )
    (comp (ref "R64")
      (value "51Ω")
      (footprint "R0402")
      (description "电阻类型:厚膜电阻;阻值:51Ω;精度:±1%;功率:62.5mW;最大工作电压:50V;温度系数:±100ppm/℃;")
      (fields (field (name "MANUFACTURER") "YAGEO(国巨)") (field (name "MANUFACTURERPART") "RC0402FR-0751RL"))
      (libsource (lib "altium-import") (part "root_0_RC0402FR-0751RL_"))
    )
    (comp (ref "R65")
      (value "51Ω")
      (footprint "R0402")
      (description "电阻类型:厚膜电阻;阻值:51Ω;精度:±1%;功率:62.5mW;最大工作电压:50V;温度系数:±100ppm/℃;")
      (fields (field (name "MANUFACTURER") "YAGEO(国巨)") (field (name "MANUFACTURERPART") "RC0402FR-0751RL"))
      (libsource (lib "altium-import") (part "root_0_RC0402FR-0751RL_"))
    )
    (comp (ref "R66")
      (value "51Ω")
      (footprint "R0402")
      (description "电阻类型:厚膜电阻;阻值:51Ω;精度:±1%;功率:62.5mW;最大工作电压:50V;温度系数:±100ppm/℃;")
      (fields (field (name "MANUFACTURER") "YAGEO(国巨)") (field (name "MANUFACTURERPART") "RC0402FR-0751RL"))
      (libsource (lib "altium-import") (part "root_0_RC0402FR-0751RL_"))
    )
    (comp (ref "R67")
      (value "51Ω")
      (footprint "R0402")
      (description "电阻类型:厚膜电阻;阻值:51Ω;精度:±1%;功率:62.5mW;最大工作电压:50V;温度系数:±100ppm/℃;")
      (fields (field (name "MANUFACTURER") "YAGEO(国巨)") (field (name "MANUFACTURERPART") "RC0402FR-0751RL"))
      (libsource (lib "altium-import") (part "root_0_RC0402FR-0751RL_"))
    )
    (comp (ref "R68")
      (value "51Ω")
      (footprint "R0402")
      (description "电阻类型:厚膜电阻;阻值:51Ω;精度:±1%;功率:62.5mW;最大工作电压:50V;温度系数:±100ppm/℃;")
      (fields (field (name "MANUFACTURER") "YAGEO(国巨)") (field (name "MANUFACTURERPART") "RC0402FR-0751RL"))
      (libsource (lib "altium-import") (part "root_0_RC0402FR-0751RL_"))
    )
    (comp (ref "R69")
      (value "51Ω")
      (footprint "R0402")
      (description "电阻类型:厚膜电阻;阻值:51Ω;精度:±1%;功率:62.5mW;最大工作电压:50V;温度系数:±100ppm/℃;")
      (fields (field (name "MANUFACTURER") "YAGEO(国巨)") (field (name "MANUFACTURERPART") "RC0402FR-0751RL"))
      (libsource (lib "altium-import") (part "root_0_RC0402FR-0751RL_"))
    )
    (comp (ref "R70")
      (value "51Ω")
      (footprint "R0402")
      (description "电阻类型:厚膜电阻;阻值:51Ω;精度:±1%;功率:62.5mW;最大工作电压:50V;温度系数:±100ppm/℃;")
      (fields (field (name "MANUFACTURER") "YAGEO(国巨)") (field (name "MANUFACTURERPART") "RC0402FR-0751RL"))
      (libsource (lib "altium-import") (part "root_0_RC0402FR-0751RL_"))
    )
    (comp (ref "R71")
      (value "51Ω")
      (footprint "R0402")
      (description "电阻类型:厚膜电阻;阻值:51Ω;精度:±1%;功率:62.5mW;最大工作电压:50V;温度系数:±100ppm/℃;")
      (fields (field (name "MANUFACTURER") "YAGEO(国巨)") (field (name "MANUFACTURERPART") "RC0402FR-0751RL"))
      (libsource (lib "altium-import") (part "root_0_RC0402FR-0751RL_"))
    )
    (comp (ref "R72")
      (value "51Ω")
      (footprint "R0402")
      (description "电阻类型:厚膜电阻;阻值:51Ω;精度:±1%;功率:62.5mW;最大工作电压:50V;温度系数:±100ppm/℃;")
      (fields (field (name "MANUFACTURER") "YAGEO(国巨)") (field (name "MANUFACTURERPART") "RC0402FR-0751RL"))
      (libsource (lib "altium-import") (part "root_0_RC0402FR-0751RL_"))
    )
    (comp (ref "R73")
      (value "51Ω")
      (footprint "R0402")
      (description "电阻类型:厚膜电阻;阻值:51Ω;精度:±1%;功率:62.5mW;最大工作电压:50V;温度系数:±100ppm/℃;")
      (fields (field (name "MANUFACTURER") "YAGEO(国巨)") (field (name "MANUFACTURERPART") "RC0402FR-0751RL"))
      (libsource (lib "altium-import") (part "root_0_RC0402FR-0751RL_"))
    )
    (comp (ref "R74")
      (value "51Ω")
      (footprint "R0402")
      (description "电阻类型:厚膜电阻;阻值:51Ω;精度:±1%;功率:62.5mW;最大工作电压:50V;温度系数:±100ppm/℃;")
      (fields (field (name "MANUFACTURER") "YAGEO(国巨)") (field (name "MANUFACTURERPART") "RC0402FR-0751RL"))
      (libsource (lib "altium-import") (part "root_0_RC0402FR-0751RL_"))
    )
    (comp (ref "R75")
      (value "51Ω")
      (footprint "R0402")
      (description "电阻类型:厚膜电阻;阻值:51Ω;精度:±1%;功率:62.5mW;最大工作电压:50V;温度系数:±100ppm/℃;")
      (fields (field (name "MANUFACTURER") "YAGEO(国巨)") (field (name "MANUFACTURERPART") "RC0402FR-0751RL"))
      (libsource (lib "altium-import") (part "root_0_RC0402FR-0751RL_"))
    )
    (comp (ref "R76")
      (value "51Ω")
      (footprint "R0402")
      (description "电阻类型:厚膜电阻;阻值:51Ω;精度:±1%;功率:62.5mW;最大工作电压:50V;温度系数:±100ppm/℃;")
      (fields (field (name "MANUFACTURER") "YAGEO(国巨)") (field (name "MANUFACTURERPART") "RC0402FR-0751RL"))
      (libsource (lib "altium-import") (part "root_0_RC0402FR-0751RL_"))
    )
    (comp (ref "R77")
      (value "51Ω")
      (footprint "R0402")
      (description "电阻类型:厚膜电阻;阻值:51Ω;精度:±1%;功率:62.5mW;最大工作电压:50V;温度系数:±100ppm/℃;")
      (fields (field (name "MANUFACTURER") "YAGEO(国巨)") (field (name "MANUFACTURERPART") "RC0402FR-0751RL"))
      (libsource (lib "altium-import") (part "root_0_RC0402FR-0751RL_"))
    )
    (comp (ref "R78")
      (value "10kΩ")
      (footprint "RES-ADJ-SMD_3224W")
      (description "阻值:10kΩ;精度:±10%;功率:250mW;温度系数:±100ppm/℃;")
      (fields (field (name "MANUFACTURER") "BOURNS") (field (name "MANUFACTURERPART") "3224W-1-103E"))
      (libsource (lib "altium-import") (part "root_0_3224W-1-103E_"))
    )
    (comp (ref "R80")
      (value "560Ω")
      (footprint "R0402")
      (description "电阻类型:厚膜电阻;阻值:560Ω;精度:±1%;功率:62.5mW;最大工作电压:50V;温度系数:±100ppm/℃;")
      (fields (field (name "MANUFACTURER") "YAGEO(国巨)") (field (name "MANUFACTURERPART") "RC0402FR-07560RL"))
      (libsource (lib "altium-import") (part "root_0_RC0402FR-07560RL_"))
    )
    (comp (ref "R81")
      (value "10kΩ")
      (footprint "R0402")
      (description "电阻类型:厚膜电阻;阻值:10kΩ;精度:±1%;功率:62.5mW;最大工作电压:50V;温度系数:±100ppm/℃;")
      (fields (field (name "MANUFACTURER") "YAGEO(国巨)") (field (name "MANUFACTURERPART") "RC0402FR-0710KL"))
      (libsource (lib "altium-import") (part "root_0_RC0402FR-0710KL_"))
    )
    (comp (ref "R82")
      (value "10kΩ")
      (footprint "R0402")
      (description "电阻类型:厚膜电阻;阻值:10kΩ;精度:±1%;功率:62.5mW;最大工作电压:50V;温度系数:±100ppm/℃;")
      (fields (field (name "MANUFACTURER") "YAGEO(国巨)") (field (name "MANUFACTURERPART") "RC0402FR-0710KL"))
      (libsource (lib "altium-import") (part "root_0_RC0402FR-0710KL_"))
    )
    (comp (ref "R83")
      (value "10kΩ")
      (footprint "R0402")
      (description "电阻类型:厚膜电阻;阻值:10kΩ;精度:±1%;功率:62.5mW;最大工作电压:50V;温度系数:±100ppm/℃;")
      (fields (field (name "MANUFACTURER") "YAGEO(国巨)") (field (name "MANUFACTURERPART") "RC0402FR-0710KL"))
      (libsource (lib "altium-import") (part "root_0_RC0402FR-0710KL_"))
    )
    (comp (ref "R84")
      (value "75Ω")
      (footprint "R0603")
      (description "电阻类型:厚膜电阻;阻值:75Ω;精度:±1%;功率:100mW;最大工作电压:75V;温度系数:±100ppm/℃;")
      (fields (field (name "MANUFACTURER") "YAGEO(国巨)") (field (name "MANUFACTURERPART") "RC0603FR-0775RL"))
      (libsource (lib "altium-import") (part "root_1_RC0603FR-0775RL_"))
    )
    (comp (ref "R85")
      (value "75Ω")
      (footprint "R0603")
      (description "电阻类型:厚膜电阻;阻值:75Ω;精度:±1%;功率:100mW;最大工作电压:75V;温度系数:±100ppm/℃;")
      (fields (field (name "MANUFACTURER") "YAGEO(国巨)") (field (name "MANUFACTURERPART") "RC0603FR-0775RL"))
      (libsource (lib "altium-import") (part "root_1_RC0603FR-0775RL_"))
    )
    (comp (ref "R86")
      (value "75Ω")
      (footprint "R0603")
      (description "电阻类型:厚膜电阻;阻值:75Ω;精度:±1%;功率:100mW;最大工作电压:75V;温度系数:±100ppm/℃;")
      (fields (field (name "MANUFACTURER") "YAGEO(国巨)") (field (name "MANUFACTURERPART") "RC0603FR-0775RL"))
      (libsource (lib "altium-import") (part "root_1_RC0603FR-0775RL_"))
    )
    (comp (ref "R87")
      (value "1kΩ")
      (footprint "R0402")
      (description "电阻类型:厚膜电阻;阻值:1kΩ;精度:±1%;功率:62.5mW;最大工作电压:50V;温度系数:±100ppm/℃;")
      (fields (field (name "MANUFACTURER") "YAGEO(国巨)") (field (name "MANUFACTURERPART") "RC0402FR-071KL"))
      (libsource (lib "altium-import") (part "root_0_RC0402FR-071KL_"))
    )
    (comp (ref "R88")
      (value "2.7kΩ")
      (footprint "R0402")
      (description "电阻类型:厚膜电阻;阻值:2.7kΩ;精度:±1%;功率:62.5mW;最大工作电压:50V;温度系数:±100ppm/℃;")
      (fields (field (name "MANUFACTURER") "YAGEO(国巨)") (field (name "MANUFACTURERPART") "RC0402FR-072K7L"))
      (libsource (lib "altium-import") (part "root_1_RC0402FR-072K7L_"))
    )
    (comp (ref "R89")
      (value "2.7kΩ")
      (footprint "R0402")
      (description "电阻类型:厚膜电阻;阻值:2.7kΩ;精度:±1%;功率:62.5mW;最大工作电压:50V;温度系数:±100ppm/℃;")
      (fields (field (name "MANUFACTURER") "YAGEO(国巨)") (field (name "MANUFACTURERPART") "RC0402FR-072K7L"))
      (libsource (lib "altium-import") (part "root_1_RC0402FR-072K7L_"))
    )
    (comp (ref "R90")
      (value "2.7kΩ")
      (footprint "R0402")
      (description "电阻类型:厚膜电阻;阻值:2.7kΩ;精度:±1%;功率:62.5mW;最大工作电压:50V;温度系数:±100ppm/℃;")
      (fields (field (name "MANUFACTURER") "YAGEO(国巨)") (field (name "MANUFACTURERPART") "RC0402FR-072K7L"))
      (libsource (lib "altium-import") (part "root_1_RC0402FR-072K7L_"))
    )
    (comp (ref "R91")
      (value "2.7kΩ")
      (footprint "R0402")
      (description "电阻类型:厚膜电阻;阻值:2.7kΩ;精度:±1%;功率:62.5mW;最大工作电压:50V;温度系数:±100ppm/℃;")
      (fields (field (name "MANUFACTURER") "YAGEO(国巨)") (field (name "MANUFACTURERPART") "RC0402FR-072K7L"))
      (libsource (lib "altium-import") (part "root_1_RC0402FR-072K7L_"))
    )
    (comp (ref "R92")
      (value "2.7kΩ")
      (footprint "R0402")
      (description "电阻类型:厚膜电阻;阻值:2.7kΩ;精度:±1%;功率:62.5mW;最大工作电压:50V;温度系数:±100ppm/℃;")
      (fields (field (name "MANUFACTURER") "YAGEO(国巨)") (field (name "MANUFACTURERPART") "RC0402FR-072K7L"))
      (libsource (lib "altium-import") (part "root_1_RC0402FR-072K7L_"))
    )
    (comp (ref "R93")
      (value "2.7kΩ")
      (footprint "R0402")
      (description "电阻类型:厚膜电阻;阻值:2.7kΩ;精度:±1%;功率:62.5mW;最大工作电压:50V;温度系数:±100ppm/℃;")
      (fields (field (name "MANUFACTURER") "YAGEO(国巨)") (field (name "MANUFACTURERPART") "RC0402FR-072K7L"))
      (libsource (lib "altium-import") (part "root_1_RC0402FR-072K7L_"))
    )
    (comp (ref "R94")
      (value "2.7kΩ")
      (footprint "R0402")
      (description "电阻类型:厚膜电阻;阻值:2.7kΩ;精度:±1%;功率:62.5mW;最大工作电压:50V;温度系数:±100ppm/℃;")
      (fields (field (name "MANUFACTURER") "YAGEO(国巨)") (field (name "MANUFACTURERPART") "RC0402FR-072K7L"))
      (libsource (lib "altium-import") (part "root_1_RC0402FR-072K7L_"))
    )
    (comp (ref "R95")
      (value "2.7kΩ")
      (footprint "R0402")
      (description "电阻类型:厚膜电阻;阻值:2.7kΩ;精度:±1%;功率:62.5mW;最大工作电压:50V;温度系数:±100ppm/℃;")
      (fields (field (name "MANUFACTURER") "YAGEO(国巨)") (field (name "MANUFACTURERPART") "RC0402FR-072K7L"))
      (libsource (lib "altium-import") (part "root_1_RC0402FR-072K7L_"))
    )
    (comp (ref "R96")
      (value "10kΩ")
      (footprint "R0402")
      (description "电阻类型:厚膜电阻;阻值:10kΩ;精度:±1%;功率:62.5mW;最大工作电压:50V;温度系数:±100ppm/℃;")
      (fields (field (name "MANUFACTURER") "YAGEO(国巨)") (field (name "MANUFACTURERPART") "RC0402FR-0710KL"))
      (libsource (lib "altium-import") (part "root_0_RC0402FR-0710KL_"))
    )
    (comp (ref "R97")
      (value "10kΩ")
      (footprint "R0402")
      (description "电阻类型:厚膜电阻;阻值:10kΩ;精度:±1%;功率:62.5mW;最大工作电压:50V;温度系数:±100ppm/℃;")
      (fields (field (name "MANUFACTURER") "YAGEO(国巨)") (field (name "MANUFACTURERPART") "RC0402FR-0710KL"))
      (libsource (lib "altium-import") (part "root_1_RC0402FR-0710KL_"))
    )
    (comp (ref "R98")
      (value "510Ω")
      (footprint "R0402")
      (description "电阻类型:厚膜电阻;阻值:510Ω;精度:±1%;功率:62.5mW;最大工作电压:50V;温度系数:±100ppm/℃;")
      (fields (field (name "MANUFACTURER") "YAGEO(国巨)") (field (name "MANUFACTURERPART") "RC0402FR-07510RL"))
      (libsource (lib "altium-import") (part "root_2_RC0402FR-07510RL_"))
    )
    (comp (ref "R102")
      (value "1kΩ")
      (footprint "R0402")
      (description "电阻类型:厚膜电阻;阻值:1kΩ;精度:±1%;功率:62.5mW;最大工作电压:50V;温度系数:±100ppm/℃;")
      (fields (field (name "MANUFACTURER") "YAGEO(国巨)") (field (name "MANUFACTURERPART") "RC0402FR-071KL"))
      (libsource (lib "altium-import") (part "root_1_RC0402FR-071KL_"))
    )
    (comp (ref "R103")
      (value "1kΩ")
      (footprint "R0402")
      (description "电阻类型:厚膜电阻;阻值:1kΩ;精度:±1%;功率:62.5mW;最大工作电压:50V;温度系数:±100ppm/℃;")
      (fields (field (name "MANUFACTURER") "YAGEO(国巨)") (field (name "MANUFACTURERPART") "RC0402FR-071KL"))
      (libsource (lib "altium-import") (part "root_1_RC0402FR-071KL_"))
    )
    (comp (ref "R104")
      (value "2.7kΩ")
      (footprint "R0402")
      (description "电阻类型:厚膜电阻;阻值:2.7kΩ;精度:±1%;功率:62.5mW;最大工作电压:50V;温度系数:±100ppm/℃;")
      (fields (field (name "MANUFACTURER") "YAGEO(国巨)") (field (name "MANUFACTURERPART") "RC0402FR-072K7L"))
      (libsource (lib "altium-import") (part "root_1_RC0402FR-072K7L_"))
    )
    (comp (ref "R105")
      (value "2.7kΩ")
      (footprint "R0402")
      (description "电阻类型:厚膜电阻;阻值:2.7kΩ;精度:±1%;功率:62.5mW;最大工作电压:50V;温度系数:±100ppm/℃;")
      (fields (field (name "MANUFACTURER") "YAGEO(国巨)") (field (name "MANUFACTURERPART") "RC0402FR-072K7L"))
      (libsource (lib "altium-import") (part "root_1_RC0402FR-072K7L_"))
    )
    (comp (ref "R106")
      (value "2.7kΩ")
      (footprint "R0402")
      (description "电阻类型:厚膜电阻;阻值:2.7kΩ;精度:±1%;功率:62.5mW;最大工作电压:50V;温度系数:±100ppm/℃;")
      (fields (field (name "MANUFACTURER") "YAGEO(国巨)") (field (name "MANUFACTURERPART") "RC0402FR-072K7L"))
      (libsource (lib "altium-import") (part "root_1_RC0402FR-072K7L_"))
    )
    (comp (ref "R107")
      (value "2.7kΩ")
      (footprint "R0402")
      (description "电阻类型:厚膜电阻;阻值:2.7kΩ;精度:±1%;功率:62.5mW;最大工作电压:50V;温度系数:±100ppm/℃;")
      (fields (field (name "MANUFACTURER") "YAGEO(国巨)") (field (name "MANUFACTURERPART") "RC0402FR-072K7L"))
      (libsource (lib "altium-import") (part "root_1_RC0402FR-072K7L_"))
    )
    (comp (ref "R108")
      (value "2.7kΩ")
      (footprint "R0402")
      (description "电阻类型:厚膜电阻;阻值:2.7kΩ;精度:±1%;功率:62.5mW;最大工作电压:50V;温度系数:±100ppm/℃;")
      (fields (field (name "MANUFACTURER") "YAGEO(国巨)") (field (name "MANUFACTURERPART") "RC0402FR-072K7L"))
      (libsource (lib "altium-import") (part "root_1_RC0402FR-072K7L_"))
    )
    (comp (ref "R109")
      (value "2.7kΩ")
      (footprint "R0402")
      (description "电阻类型:厚膜电阻;阻值:2.7kΩ;精度:±1%;功率:62.5mW;最大工作电压:50V;温度系数:±100ppm/℃;")
      (fields (field (name "MANUFACTURER") "YAGEO(国巨)") (field (name "MANUFACTURERPART") "RC0402FR-072K7L"))
      (libsource (lib "altium-import") (part "root_1_RC0402FR-072K7L_"))
    )
    (comp (ref "R110")
      (value "2.7kΩ")
      (footprint "R0402")
      (description "电阻类型:厚膜电阻;阻值:2.7kΩ;精度:±1%;功率:62.5mW;最大工作电压:50V;温度系数:±100ppm/℃;")
      (fields (field (name "MANUFACTURER") "YAGEO(国巨)") (field (name "MANUFACTURERPART") "RC0402FR-072K7L"))
      (libsource (lib "altium-import") (part "root_1_RC0402FR-072K7L_"))
    )
    (comp (ref "R111")
      (value "2.7kΩ")
      (footprint "R0402")
      (description "电阻类型:厚膜电阻;阻值:2.7kΩ;精度:±1%;功率:62.5mW;最大工作电压:50V;温度系数:±100ppm/℃;")
      (fields (field (name "MANUFACTURER") "YAGEO(国巨)") (field (name "MANUFACTURERPART") "RC0402FR-072K7L"))
      (libsource (lib "altium-import") (part "root_1_RC0402FR-072K7L_"))
    )
    (comp (ref "R112")
      (value "1kΩ")
      (footprint "R0402")
      (description "电阻类型:厚膜电阻;阻值:1kΩ;精度:±1%;功率:62.5mW;最大工作电压:50V;温度系数:±100ppm/℃;")
      (fields (field (name "MANUFACTURER") "YAGEO(国巨)") (field (name "MANUFACTURERPART") "RC0402FR-071KL"))
      (libsource (lib "altium-import") (part "root_1_RC0402FR-071KL_"))
    )
    (comp (ref "R133")
      (value "100kΩ")
      (footprint "R0603")
      (description "电阻类型:厚膜电阻;阻值:100kΩ;精度:±1%;功率:100mW;温度系数:±100ppm/℃;")
      (fields (field (name "MANUFACTURER") "YAGEO(国巨)") (field (name "MANUFACTURER PART") "RC0603FR-07100KL"))
      (libsource (lib "altium-import") (part "root_0_RC0603FR-07100KL_"))
    )
    (comp (ref "R134")
      (value "180kΩ")
      (footprint "R0603")
      (description "电阻类型:厚膜电阻;阻值:180kΩ;功率:100mW;温度系数:±100ppm/℃;精度:±1%;")
      (fields
        (field (name "MANUFACTURER") "UNI-ROYAL(厚声)")
        (field (name "MANUFACTURER PART") "0603WAF1803T5E")
      )
      (libsource (lib "altium-import") (part "root_1_0603WAF1803T5E_"))
    )
    (comp (ref "R135")
      (value "560kΩ")
      (footprint "R0402")
      (description "电阻类型:厚膜电阻;阻值:560kΩ;精度:±1%;功率:62.5mW;最大工作电压:50V;温度系数:±100ppm/℃;")
      (fields (field (name "MANUFACTURER") "YAGEO(国巨)") (field (name "MANUFACTURERPART") "RC0402FR-07560KL"))
      (libsource (lib "altium-import") (part "root_1_RC0402FR-07560KL_"))
    )
    (comp (ref "R136")
      (value "100kΩ")
      (footprint "R0603")
      (description "电阻类型:厚膜电阻;阻值:100kΩ;精度:±1%;功率:100mW;温度系数:±100ppm/℃;")
      (fields (field (name "MANUFACTURER") "YAGEO(国巨)") (field (name "MANUFACTURER PART") "RC0603FR-07100KL"))
      (libsource (lib "altium-import") (part "root_0_RC0603FR-07100KL_"))
    )
    (comp (ref "R137")
      (value "180kΩ")
      (footprint "R0603")
      (description "电阻类型:厚膜电阻;阻值:180kΩ;功率:100mW;温度系数:±100ppm/℃;精度:±1%;")
      (fields
        (field (name "MANUFACTURER") "UNI-ROYAL(厚声)")
        (field (name "MANUFACTURER PART") "0603WAF1803T5E")
      )
      (libsource (lib "altium-import") (part "root_1_0603WAF1803T5E_"))
    )
    (comp (ref "R138")
      (value "158kΩ")
      (footprint "R0402")
      (description "电阻类型:厚膜电阻;阻值:158kΩ;精度:±1%;功率:62.5mW;最大工作电压:50V;温度系数:±100ppm/℃;")
      (fields
        (field (name "MANUFACTURER") "UNI-ROYAL(厚声)")
        (field (name "MANUFACTURER PART") "0402WGF1583TCE")
      )
      (libsource (lib "altium-import") (part "root_1_0402WGF1583TCE_"))
    )
    (comp (ref "R139")
      (value "100kΩ")
      (footprint "R0402")
      (description "电阻类型:厚膜电阻;阻值:100kΩ;精度:±1%;功率:62.5mW;最大工作电压:50V;温度系数:±100ppm/℃;")
      (fields (field (name "MANUFACTURER") "YAGEO(国巨)") (field (name "MANUFACTURERPART") "RC0402FR-07100KL"))
      (libsource (lib "altium-import") (part "root_1_RC0402FR-07100KL_"))
    )
    (comp (ref "R140")
      (value "1.8kΩ")
      (footprint "R0402")
      (description "电阻类型:厚膜电阻;阻值:1.8kΩ;精度:±1%;功率:62.5mW;最大工作电压:50V;温度系数:±100ppm/℃;")
      (fields (field (name "MANUFACTURER") "YAGEO(国巨)") (field (name "MANUFACTURERPART") "RC0402FR-071K8L"))
      (libsource (lib "altium-import") (part "root_1_RC0402FR-071K8L_"))
    )
    (comp (ref "R141")
      (value "10kΩ")
      (footprint "R0402")
      (description "电阻类型:厚膜电阻;阻值:10kΩ;精度:±1%;功率:62.5mW;最大工作电压:50V;温度系数:±100ppm/℃;")
      (fields (field (name "MANUFACTURER") "YAGEO(国巨)") (field (name "MANUFACTURERPART") "RC0402FR-0710KL"))
      (libsource (lib "altium-import") (part "root_1_RC0402FR-0710KL_"))
    )
    (comp (ref "R142")
      (value "5kΩ")
      (footprint "R0603")
      (description "电阻类型:薄膜电阻;阻值:5kΩ;精度:±0.1%;功率:100mW;最大工作电压:50V;温度系数:±25ppm/℃;")
      (fields (field (name "MANUFACTURER") "Viking(光颉)") (field (name "MANUFACTURERPART") "AR03BTCX5001"))
      (libsource (lib "altium-import") (part "root_1_AR03BTCX5001_"))
    )
    (comp (ref "R143")
      (value "3.3kΩ")
      (footprint "R0805")
      (description "电阻类型:厚膜电阻;阻值:3.3kΩ;精度:±1%;功率:125mW;最大工作电压:150V;温度系数:±100ppm/℃;")
      (fields (field (name "MANUFACTURER") "YAGEO(国巨)") (field (name "MANUFACTURERPART") "RC0805FR-073K3L"))
      (libsource (lib "altium-import") (part "root_1_RC0805FR-073K3L_"))
    )
    (comp (ref "R144")
      (value "3.3kΩ")
      (footprint "R0805")
      (description "电阻类型:厚膜电阻;阻值:3.3kΩ;精度:±1%;功率:125mW;最大工作电压:150V;温度系数:±100ppm/℃;")
      (fields (field (name "MANUFACTURER") "YAGEO(国巨)") (field (name "MANUFACTURERPART") "RC0805FR-073K3L"))
      (libsource (lib "altium-import") (part "root_1_RC0805FR-073K3L_"))
    )
    (comp (ref "R145")
      (value "3.3kΩ")
      (footprint "R0805")
      (description "电阻类型:厚膜电阻;阻值:3.3kΩ;精度:±1%;功率:125mW;最大工作电压:150V;温度系数:±100ppm/℃;")
      (fields (field (name "MANUFACTURER") "YAGEO(国巨)") (field (name "MANUFACTURERPART") "RC0805FR-073K3L"))
      (libsource (lib "altium-import") (part "root_1_RC0805FR-073K3L_"))
    )
    (comp (ref "R146")
      (value "100kΩ")
      (footprint "R0603")
      (description "电阻类型:厚膜电阻;阻值:100kΩ;精度:±1%;功率:100mW;温度系数:±100ppm/℃;")
      (fields (field (name "MANUFACTURER") "YAGEO(国巨)") (field (name "MANUFACTURER PART") "RC0603FR-07100KL"))
      (libsource (lib "altium-import") (part "root_0_RC0603FR-07100KL_"))
    )
    (comp (ref "R147")
      (value "3.3kΩ")
      (footprint "R0805")
      (description "电阻类型:厚膜电阻;阻值:3.3kΩ;精度:±1%;功率:125mW;最大工作电压:150V;温度系数:±100ppm/℃;")
      (fields (field (name "MANUFACTURER") "YAGEO(国巨)") (field (name "MANUFACTURERPART") "RC0805FR-073K3L"))
      (libsource (lib "altium-import") (part "root_1_RC0805FR-073K3L_"))
    )
    (comp (ref "R148")
      (value "3.3kΩ")
      (footprint "R0805")
      (description "电阻类型:厚膜电阻;阻值:3.3kΩ;精度:±1%;功率:125mW;最大工作电压:150V;温度系数:±100ppm/℃;")
      (fields (field (name "MANUFACTURER") "YAGEO(国巨)") (field (name "MANUFACTURERPART") "RC0805FR-073K3L"))
      (libsource (lib "altium-import") (part "root_1_RC0805FR-073K3L_"))
    )
    (comp (ref "R149")
      (value "300Ω")
      (footprint "R0402")
      (description "电阻类型:厚膜电阻;阻值:300Ω;精度:±1%;功率:62.5mW;最大工作电压:50V;温度系数:±100ppm/℃;")
      (fields (field (name "MANUFACTURER") "YAGEO(国巨)") (field (name "MANUFACTURERPART") "RC0402FR-07300RL"))
      (libsource (lib "altium-import") (part "root_1_RC0402FR-07300RL_"))
    )
    (comp (ref "R150")
      (value "10kΩ")
      (footprint "R0402")
      (description "电阻类型:厚膜电阻;阻值:10kΩ;精度:±1%;功率:62.5mW;最大工作电压:50V;温度系数:±100ppm/℃;")
      (fields (field (name "MANUFACTURER") "YAGEO(国巨)") (field (name "MANUFACTURERPART") "RC0402FR-0710KL"))
      (libsource (lib "altium-import") (part "root_1_RC0402FR-0710KL_"))
    )
    (comp (ref "R151")
      (value "33Ω")
      (footprint "R0402")
      (description "电阻类型:厚膜电阻;阻值:33Ω;精度:±1%;功率:62.5mW;最大工作电压:50V;温度系数:±100ppm/℃;")
      (fields (field (name "MANUFACTURER") "YAGEO(国巨)") (field (name "MANUFACTURERPART") "RC0402FR-0733RL"))
      (libsource (lib "altium-import") (part "root_0_RC0402FR-0733RL_"))
    )
    (comp (ref "R152")
      (value "33Ω")
      (footprint "R0402")
      (description "电阻类型:厚膜电阻;阻值:33Ω;精度:±1%;功率:62.5mW;最大工作电压:50V;温度系数:±100ppm/℃;")
      (fields (field (name "MANUFACTURER") "YAGEO(国巨)") (field (name "MANUFACTURERPART") "RC0402FR-0733RL"))
      (libsource (lib "altium-import") (part "root_0_RC0402FR-0733RL_"))
    )
    (comp (ref "R153")
      (value "33Ω")
      (footprint "R0402")
      (description "电阻类型:厚膜电阻;阻值:33Ω;精度:±1%;功率:62.5mW;最大工作电压:50V;温度系数:±100ppm/℃;")
      (fields (field (name "MANUFACTURER") "YAGEO(国巨)") (field (name "MANUFACTURERPART") "RC0402FR-0733RL"))
      (libsource (lib "altium-import") (part "root_0_RC0402FR-0733RL_"))
    )
    (comp (ref "R154")
      (value "300Ω")
      (footprint "R0402")
      (description "电阻类型:厚膜电阻;阻值:300Ω;精度:±1%;功率:62.5mW;最大工作电压:50V;温度系数:±100ppm/℃;")
      (fields (field (name "MANUFACTURER") "YAGEO(国巨)") (field (name "MANUFACTURERPART") "RC0402FR-07300RL"))
      (libsource (lib "altium-import") (part "root_1_RC0402FR-07300RL_"))
    )
    (comp (ref "R155")
      (value "100Ω")
      (footprint "R0402")
      (description "电阻类型:厚膜电阻;阻值:100Ω;精度:±1%;功率:62.5mW;最大工作电压:50V;温度系数:±100ppm/℃;")
      (fields (field (name "MANUFACTURER") "YAGEO(国巨)") (field (name "MANUFACTURERPART") "RC0402FR-07100RL"))
      (libsource (lib "altium-import") (part "root_1_RC0402FR-07100RL_"))
    )
    (comp (ref "R156")
      (value "100Ω")
      (footprint "R0402")
      (description "电阻类型:厚膜电阻;阻值:100Ω;精度:±1%;功率:62.5mW;最大工作电压:50V;温度系数:±100ppm/℃;")
      (fields (field (name "MANUFACTURER") "YAGEO(国巨)") (field (name "MANUFACTURERPART") "RC0402FR-07100RL"))
      (libsource (lib "altium-import") (part "root_1_RC0402FR-07100RL_"))
    )
    (comp (ref "R159")
      (value "33Ω")
      (footprint "R0402")
      (description "电阻类型:厚膜电阻;阻值:33Ω;精度:±1%;功率:62.5mW;最大工作电压:50V;温度系数:±100ppm/℃;")
      (fields (field (name "MANUFACTURER") "YAGEO(国巨)") (field (name "MANUFACTURERPART") "RC0402FR-0733RL"))
      (libsource (lib "altium-import") (part "root_0_RC0402FR-0733RL_"))
    )
    (comp (ref "R160")
      (value "33Ω")
      (footprint "R0402")
      (description "电阻类型:厚膜电阻;阻值:33Ω;精度:±1%;功率:62.5mW;最大工作电压:50V;温度系数:±100ppm/℃;")
      (fields (field (name "MANUFACTURER") "YAGEO(国巨)") (field (name "MANUFACTURERPART") "RC0402FR-0733RL"))
      (libsource (lib "altium-import") (part "root_0_RC0402FR-0733RL_"))
    )
    (comp (ref "R168")
      (value "10kΩ")
      (footprint "R0402")
      (description "电阻类型:厚膜电阻;阻值:10kΩ;精度:±1%;功率:62.5mW;最大工作电压:50V;温度系数:±100ppm/℃;")
      (fields (field (name "MANUFACTURER") "YAGEO(国巨)") (field (name "MANUFACTURERPART") "RC0402FR-0710KL"))
      (libsource (lib "altium-import") (part "root_1_RC0402FR-0710KL_"))
    )
    (comp (ref "R169")
      (value "10kΩ")
      (footprint "R0402")
      (description "电阻类型:厚膜电阻;阻值:10kΩ;精度:±1%;功率:62.5mW;最大工作电压:50V;温度系数:±100ppm/℃;")
      (fields (field (name "MANUFACTURER") "YAGEO(国巨)") (field (name "MANUFACTURERPART") "RC0402FR-0710KL"))
      (libsource (lib "altium-import") (part "root_1_RC0402FR-0710KL_"))
    )
    (comp (ref "R184")
      (value "33Ω")
      (footprint "R0402")
      (description "电阻类型:厚膜电阻;阻值:33Ω;精度:±1%;功率:62.5mW;最大工作电压:50V;温度系数:±100ppm/℃;")
      (fields (field (name "MANUFACTURER") "YAGEO(国巨)") (field (name "MANUFACTURERPART") "RC0402FR-0733RL"))
      (libsource (lib "altium-import") (part "root_0_RC0402FR-0733RL_"))
    )
    (comp (ref "R185")
      (value "300Ω")
      (footprint "R0402")
      (description "电阻类型:厚膜电阻;阻值:300Ω;精度:±1%;功率:62.5mW;最大工作电压:50V;温度系数:±100ppm/℃;")
      (fields (field (name "MANUFACTURER") "YAGEO(国巨)") (field (name "MANUFACTURERPART") "RC0402FR-07300RL"))
      (libsource (lib "altium-import") (part "root_2_RC0402FR-07300RL_"))
    )
    (comp (ref "R186")
      (value "100Ω")
      (footprint "R0402")
      (description "电阻类型:厚膜电阻;阻值:100Ω;精度:±1%;功率:62.5mW;最大工作电压:50V;温度系数:±100ppm/℃;")
      (fields (field (name "MANUFACTURER") "YAGEO(国巨)") (field (name "MANUFACTURERPART") "RC0402FR-07100RL"))
      (libsource (lib "altium-import") (part "root_2_RC0402FR-07100RL_"))
    )
    (comp (ref "R187")
      (value "100Ω")
      (footprint "R0402")
      (description "电阻类型:厚膜电阻;阻值:100Ω;精度:±1%;功率:62.5mW;最大工作电压:50V;温度系数:±100ppm/℃;")
      (fields (field (name "MANUFACTURER") "YAGEO(国巨)") (field (name "MANUFACTURERPART") "RC0402FR-07100RL"))
      (libsource (lib "altium-import") (part "root_2_RC0402FR-07100RL_"))
    )
    (comp (ref "R188")
      (value "100Ω")
      (footprint "R0402")
      (description "电阻类型:厚膜电阻;阻值:100Ω;精度:±1%;功率:62.5mW;最大工作电压:50V;温度系数:±100ppm/℃;")
      (fields (field (name "MANUFACTURER") "YAGEO(国巨)") (field (name "MANUFACTURERPART") "RC0402FR-07100RL"))
      (libsource (lib "altium-import") (part "root_2_RC0402FR-07100RL_"))
    )
    (comp (ref "R189")
      (value "100Ω")
      (footprint "R0402")
      (description "电阻类型:厚膜电阻;阻值:100Ω;精度:±1%;功率:62.5mW;最大工作电压:50V;温度系数:±100ppm/℃;")
      (fields (field (name "MANUFACTURER") "YAGEO(国巨)") (field (name "MANUFACTURERPART") "RC0402FR-07100RL"))
      (libsource (lib "altium-import") (part "root_2_RC0402FR-07100RL_"))
    )
    (comp (ref "R190")
      (value "33Ω")
      (footprint "R0402")
      (description "电阻类型:厚膜电阻;阻值:33Ω;精度:±1%;功率:62.5mW;最大工作电压:50V;温度系数:±100ppm/℃;")
      (fields (field (name "MANUFACTURER") "YAGEO(国巨)") (field (name "MANUFACTURERPART") "RC0402FR-0733RL"))
      (libsource (lib "altium-import") (part "root_0_RC0402FR-0733RL_"))
    )
    (comp (ref "R196")
      (value "300Ω")
      (footprint "R0402")
      (description "电阻类型:厚膜电阻;阻值:300Ω;精度:±1%;功率:62.5mW;最大工作电压:50V;温度系数:±100ppm/℃;")
      (fields (field (name "MANUFACTURER") "YAGEO(国巨)") (field (name "MANUFACTURERPART") "RC0402FR-07300RL"))
      (libsource (lib "altium-import") (part "root_1_RC0402FR-07300RL_"))
    )
    (comp (ref "R197")
      (value "300Ω")
      (footprint "R0402")
      (description "电阻类型:厚膜电阻;阻值:300Ω;精度:±1%;功率:62.5mW;最大工作电压:50V;温度系数:±100ppm/℃;")
      (fields (field (name "MANUFACTURER") "YAGEO(国巨)") (field (name "MANUFACTURERPART") "RC0402FR-07300RL"))
      (libsource (lib "altium-import") (part "root_1_RC0402FR-07300RL_"))
    )
    (comp (ref "R198")
      (value "300Ω")
      (footprint "R0402")
      (description "电阻类型:厚膜电阻;阻值:300Ω;精度:±1%;功率:62.5mW;最大工作电压:50V;温度系数:±100ppm/℃;")
      (fields (field (name "MANUFACTURER") "YAGEO(国巨)") (field (name "MANUFACTURERPART") "RC0402FR-07300RL"))
      (libsource (lib "altium-import") (part "root_1_RC0402FR-07300RL_"))
    )
    (comp (ref "RN1")
      (value "33Ω")
      (footprint "RES-ARRAY-SMD_0402-8P-L2.0-W1.0-BL")
      (description "电阻器数:4;阻值:33Ω;精度:±1%;单个元件功率:62.5mW;温度系数:±200ppm/℃;")
      (fields (field (name "MANUFACTURER") "YAGEO(国巨)") (field (name "MANUFACTURERPART") "YC124-FR-0733RL"))
      (libsource (lib "altium-import") (part "root_1_YC124-FR-0733RL_"))
    )
    (comp (ref "RN2")
      (value "10kΩ")
      (footprint "RES-ARRAY-SMD_0603-8P-L3.2-W1.6-BL")
      (description "电阻器数:4;阻值:10kΩ;精度:±5%;单个元件功率:62.5mW;温度系数:±200ppm/℃;")
      (fields
        (field (name "MANUFACTURER") "UNI-ROYAL(厚声)")
        (field (name "MANUFACTURER PART") "4D03WGJ0103T5E")
      )
      (libsource (lib "altium-import") (part "root_1_4D03WGJ0103T5E_"))
    )
    (comp (ref "RN3")
      (value "10kΩ")
      (footprint "RES-ARRAY-SMD_0603-8P-L3.2-W1.6-BL")
      (description "电阻器数:4;阻值:10kΩ;精度:±5%;单个元件功率:62.5mW;温度系数:±200ppm/℃;")
      (fields
        (field (name "MANUFACTURER") "UNI-ROYAL(厚声)")
        (field (name "MANUFACTURER PART") "4D03WGJ0103T5E")
      )
      (libsource (lib "altium-import") (part "root_1_4D03WGJ0103T5E_"))
    )
    (comp (ref "RN4")
      (value "33Ω")
      (footprint "RES-ARRAY-SMD_0402-8P-L2.0-W1.0-BL")
      (description "电阻器数:4;阻值:33Ω;精度:±1%;单个元件功率:62.5mW;温度系数:±200ppm/℃;")
      (fields (field (name "MANUFACTURER") "YAGEO(国巨)") (field (name "MANUFACTURERPART") "YC124-FR-0733RL"))
      (libsource (lib "altium-import") (part "root_1_YC124-FR-0733RL_"))
    )
    (comp (ref "RN5")
      (value "33Ω")
      (footprint "RES-ARRAY-SMD_0402-8P-L2.0-W1.0-BL")
      (description "电阻器数:4;阻值:33Ω;精度:±1%;单个元件功率:62.5mW;温度系数:±200ppm/℃;")
      (fields (field (name "MANUFACTURER") "YAGEO(国巨)") (field (name "MANUFACTURERPART") "YC124-FR-0733RL"))
      (libsource (lib "altium-import") (part "root_1_YC124-FR-0733RL_"))
    )
    (comp (ref "RN6")
      (value "33Ω")
      (footprint "RES-ARRAY-SMD_0402-8P-L2.0-W1.0-BL")
      (description "电阻器数:4;阻值:33Ω;精度:±1%;单个元件功率:62.5mW;温度系数:±200ppm/℃;")
      (fields (field (name "MANUFACTURER") "YAGEO(国巨)") (field (name "MANUFACTURERPART") "YC124-FR-0733RL"))
      (libsource (lib "altium-import") (part "root_1_YC124-FR-0733RL_"))
    )
    (comp (ref "RN7")
      (value "33Ω")
      (footprint "RES-ARRAY-SMD_0402-8P-L2.0-W1.0-BL")
      (description "电阻器数:4;阻值:33Ω;精度:±1%;单个元件功率:62.5mW;温度系数:±200ppm/℃;")
      (fields (field (name "MANUFACTURER") "YAGEO(国巨)") (field (name "MANUFACTURERPART") "YC124-FR-0733RL"))
      (libsource (lib "altium-import") (part "root_1_YC124-FR-0733RL_"))
    )
    (comp (ref "RN8")
      (value "33Ω")
      (footprint "RES-ARRAY-SMD_0402-8P-L2.0-W1.0-BL")
      (description "电阻器数:4;阻值:33Ω;精度:±1%;单个元件功率:62.5mW;温度系数:±200ppm/℃;")
      (fields (field (name "MANUFACTURER") "YAGEO(国巨)") (field (name "MANUFACTURERPART") "YC124-FR-0733RL"))
      (libsource (lib "altium-import") (part "root_1_YC124-FR-0733RL_"))
    )
    (comp (ref "RN9")
      (value "33Ω")
      (footprint "RES-ARRAY-SMD_0402-8P-L2.0-W1.0-BL")
      (description "电阻器数:4;阻值:33Ω;精度:±1%;单个元件功率:62.5mW;温度系数:±200ppm/℃;")
      (fields (field (name "MANUFACTURER") "YAGEO(国巨)") (field (name "MANUFACTURERPART") "YC124-FR-0733RL"))
      (libsource (lib "altium-import") (part "root_1_YC124-FR-0733RL_"))
    )
    (comp (ref "RN11")
      (value "33Ω")
      (footprint "RES-ARRAY-SMD_0402-8P-L2.0-W1.0-BL")
      (description "电阻器数:4;阻值:33Ω;精度:±1%;单个元件功率:62.5mW;温度系数:±200ppm/℃;")
      (fields (field (name "MANUFACTURER") "YAGEO(国巨)") (field (name "MANUFACTURERPART") "YC124-FR-0733RL"))
      (libsource (lib "altium-import") (part "root_1_YC124-FR-0733RL_"))
    )
    (comp (ref "RN12")
      (value "33Ω")
      (footprint "RES-ARRAY-SMD_0402-8P-L2.0-W1.0-BL")
      (description "电阻器数:4;阻值:33Ω;精度:±1%;单个元件功率:62.5mW;温度系数:±200ppm/℃;")
      (fields (field (name "MANUFACTURER") "YAGEO(国巨)") (field (name "MANUFACTURERPART") "YC124-FR-0733RL"))
      (libsource (lib "altium-import") (part "root_1_YC124-FR-0733RL_"))
    )
    (comp (ref "RN13")
      (value "33Ω")
      (footprint "RES-ARRAY-SMD_0402-8P-L2.0-W1.0-BL")
      (description "电阻器数:4;阻值:33Ω;精度:±1%;单个元件功率:62.5mW;温度系数:±200ppm/℃;")
      (fields (field (name "MANUFACTURER") "YAGEO(国巨)") (field (name "MANUFACTURERPART") "YC124-FR-0733RL"))
      (libsource (lib "altium-import") (part "root_1_YC124-FR-0733RL_"))
    )
    (comp (ref "RN14")
      (value "33Ω")
      (footprint "RES-ARRAY-SMD_0402-8P-L2.0-W1.0-BL")
      (description "电阻器数:4;阻值:33Ω;精度:±1%;单个元件功率:62.5mW;温度系数:±200ppm/℃;")
      (fields (field (name "MANUFACTURER") "YAGEO(国巨)") (field (name "MANUFACTURERPART") "YC124-FR-0733RL"))
      (libsource (lib "altium-import") (part "root_1_YC124-FR-0733RL_"))
    )
    (comp (ref "RN15")
      (value "33Ω")
      (footprint "RES-ARRAY-SMD_0402-8P-L2.0-W1.0-BL")
      (description "电阻器数:4;阻值:33Ω;精度:±1%;单个元件功率:62.5mW;温度系数:±200ppm/℃;")
      (fields (field (name "MANUFACTURER") "YAGEO(国巨)") (field (name "MANUFACTURERPART") "YC124-FR-0733RL"))
      (libsource (lib "altium-import") (part "root_1_YC124-FR-0733RL_"))
    )
    (comp (ref "RN16")
      (value "33Ω")
      (footprint "RES-ARRAY-SMD_0402-8P-L2.0-W1.0-BL")
      (description "电阻器数:4;阻值:33Ω;精度:±1%;单个元件功率:62.5mW;温度系数:±200ppm/℃;")
      (fields (field (name "MANUFACTURER") "YAGEO(国巨)") (field (name "MANUFACTURERPART") "YC124-FR-0733RL"))
      (libsource (lib "altium-import") (part "root_1_YC124-FR-0733RL_"))
    )
    (comp (ref "RN17")
      (value "33Ω")
      (footprint "RES-ARRAY-SMD_0402-8P-L2.0-W1.0-BL")
      (description "电阻器数:4;阻值:33Ω;精度:±1%;单个元件功率:62.5mW;温度系数:±200ppm/℃;")
      (fields (field (name "MANUFACTURER") "YAGEO(国巨)") (field (name "MANUFACTURERPART") "YC124-FR-0733RL"))
      (libsource (lib "altium-import") (part "root_1_YC124-FR-0733RL_"))
    )
    (comp (ref "RN18")
      (value "33Ω")
      (footprint "RES-ARRAY-SMD_0402-8P-L2.0-W1.0-BL")
      (description "电阻器数:4;阻值:33Ω;精度:±1%;单个元件功率:62.5mW;温度系数:±200ppm/℃;")
      (fields (field (name "MANUFACTURER") "YAGEO(国巨)") (field (name "MANUFACTURERPART") "YC124-FR-0733RL"))
      (libsource (lib "altium-import") (part "root_1_YC124-FR-0733RL_"))
    )
    (comp (ref "RN19")
      (value "33Ω")
      (footprint "RES-ARRAY-SMD_0402-8P-L2.0-W1.0-BL")
      (description "电阻器数:4;阻值:33Ω;精度:±1%;单个元件功率:62.5mW;温度系数:±200ppm/℃;")
      (fields (field (name "MANUFACTURER") "YAGEO(国巨)") (field (name "MANUFACTURERPART") "YC124-FR-0733RL"))
      (libsource (lib "altium-import") (part "root_1_YC124-FR-0733RL_"))
    )
    (comp (ref "RN20")
      (value "33Ω")
      (footprint "RES-ARRAY-SMD_0402-8P-L2.0-W1.0-BL")
      (description "电阻器数:4;阻值:33Ω;精度:±1%;单个元件功率:62.5mW;温度系数:±200ppm/℃;")
      (fields (field (name "MANUFACTURER") "YAGEO(国巨)") (field (name "MANUFACTURERPART") "YC124-FR-0733RL"))
      (libsource (lib "altium-import") (part "root_1_YC124-FR-0733RL_"))
    )
    (comp (ref "RN21")
      (value "33Ω")
      (footprint "RES-ARRAY-SMD_0402-8P-L2.0-W1.0-BL")
      (description "电阻器数:4;阻值:33Ω;精度:±1%;单个元件功率:62.5mW;温度系数:±200ppm/℃;")
      (fields (field (name "MANUFACTURER") "YAGEO(国巨)") (field (name "MANUFACTURERPART") "YC124-FR-0733RL"))
      (libsource (lib "altium-import") (part "root_1_YC124-FR-0733RL_"))
    )
    (comp (ref "RN22")
      (value "33Ω")
      (footprint "RES-ARRAY-SMD_0402-8P-L2.0-W1.0-BL")
      (description "电阻器数:4;阻值:33Ω;精度:±1%;单个元件功率:62.5mW;温度系数:±200ppm/℃;")
      (fields (field (name "MANUFACTURER") "YAGEO(国巨)") (field (name "MANUFACTURERPART") "YC124-FR-0733RL"))
      (libsource (lib "altium-import") (part "root_1_YC124-FR-0733RL_"))
    )
    (comp (ref "RN23")
      (value "33Ω")
      (footprint "RES-ARRAY-SMD_0402-8P-L2.0-W1.0-BL")
      (description "电阻器数:4;阻值:33Ω;精度:±1%;单个元件功率:62.5mW;温度系数:±200ppm/℃;")
      (fields (field (name "MANUFACTURER") "YAGEO(国巨)") (field (name "MANUFACTURERPART") "YC124-FR-0733RL"))
      (libsource (lib "altium-import") (part "root_1_YC124-FR-0733RL_"))
    )
    (comp (ref "RN24")
      (value "33Ω")
      (footprint "RES-ARRAY-SMD_0402-8P-L2.0-W1.0-BL")
      (description "电阻器数:4;阻值:33Ω;精度:±1%;单个元件功率:62.5mW;温度系数:±200ppm/℃;")
      (fields (field (name "MANUFACTURER") "YAGEO(国巨)") (field (name "MANUFACTURERPART") "YC124-FR-0733RL"))
      (libsource (lib "altium-import") (part "root_1_YC124-FR-0733RL_"))
    )
    (comp (ref "RN25")
      (value "33Ω")
      (footprint "RES-ARRAY-SMD_0402-8P-L2.0-W1.0-BL")
      (description "电阻器数:4;阻值:33Ω;精度:±1%;单个元件功率:62.5mW;温度系数:±200ppm/℃;")
      (fields (field (name "MANUFACTURER") "YAGEO(国巨)") (field (name "MANUFACTURERPART") "YC124-FR-0733RL"))
      (libsource (lib "altium-import") (part "root_1_YC124-FR-0733RL_"))
    )
    (comp (ref "RN27")
      (value "33Ω")
      (footprint "RES-ARRAY-SMD_0402-8P-L2.0-W1.0-BL")
      (description "电阻器数:4;阻值:33Ω;精度:±1%;单个元件功率:62.5mW;温度系数:±200ppm/℃;")
      (fields (field (name "MANUFACTURER") "YAGEO(国巨)") (field (name "MANUFACTURERPART") "YC124-FR-0733RL"))
      (libsource (lib "altium-import") (part "root_1_YC124-FR-0733RL_"))
    )
    (comp (ref "RN28")
      (value "33Ω")
      (footprint "RES-ARRAY-SMD_0402-8P-L2.0-W1.0-BL")
      (description "电阻器数:4;阻值:33Ω;精度:±1%;单个元件功率:62.5mW;温度系数:±200ppm/℃;")
      (fields (field (name "MANUFACTURER") "YAGEO(国巨)") (field (name "MANUFACTURERPART") "YC124-FR-0733RL"))
      (libsource (lib "altium-import") (part "root_1_YC124-FR-0733RL_"))
    )
    (comp (ref "SW1")
      (value "DSHP04TSGET")
      (footprint "SW-SMD_8P-L6.7-W5.4-P1.27-LS8.4")
      (description "类型:平拨,凹槽式;电路结构:单刀单掷;开关位数:4位;使用寿命:-;颜色:黑色;")
      (fields (field (name "MANUFACTURER") "YE"))
      (libsource (lib "altium-import") (part "root_0_DSHP04TSGET_"))
    )
    (comp (ref "SW2")
      (value "DSHP04TSGET")
      (footprint "SW-SMD_8P-L6.7-W5.4-P1.27-LS8.4")
      (description "类型:平拨,凹槽式;电路结构:单刀单掷;开关位数:4位;使用寿命:-;颜色:黑色;")
      (fields (field (name "MANUFACTURER") "YE"))
      (libsource (lib "altium-import") (part "root_0_DSHP04TSGET_"))
    )
    (comp (ref "SW3")
      (value "SKPMBHE010")
      (footprint "KEY-SMD_2P-L6.0-W6.0-P6.00")
      (description "电路结构:单刀单掷;按钮形状:圆形按钮;安装方式:立贴;开关长度:6mm;开关宽度:5.9mm;开关高度:5mm;触点电流:50mA;额定电压(DC):16V;带灯:-;机械寿命:-;")
      (fields (field (name "MANUFACTURER") "ALPSALPINE(阿尔卑斯阿尔派)"))
      (libsource (lib "altium-import") (part "root_0_SKPMBHE010_"))
    )
    (comp (ref "SW4")
      (value "SKPMBHE010")
      (footprint "KEY-SMD_2P-L6.0-W6.0-P6.00")
      (description "电路结构:单刀单掷;按钮形状:圆形按钮;安装方式:立贴;开关长度:6mm;开关宽度:5.9mm;开关高度:5mm;触点电流:50mA;额定电压(DC):16V;带灯:-;机械寿命:-;")
      (fields (field (name "MANUFACTURER") "ALPSALPINE(阿尔卑斯阿尔派)"))
      (libsource (lib "altium-import") (part "root_0_SKPMBHE010_"))
    )
    (comp (ref "SW5")
      (value "SKPMBHE010")
      (footprint "KEY-SMD_2P-L6.0-W6.0-P6.00")
      (description "电路结构:单刀单掷;按钮形状:圆形按钮;安装方式:立贴;开关长度:6mm;开关宽度:5.9mm;开关高度:5mm;触点电流:50mA;额定电压(DC):16V;带灯:-;机械寿命:-;")
      (fields (field (name "MANUFACTURER") "ALPSALPINE(阿尔卑斯阿尔派)"))
      (libsource (lib "altium-import") (part "root_0_SKPMBHE010_"))
    )
    (comp (ref "U2")
      (value "TFP401APZPR")
      (footprint "HTQFP-100_L14.0-W14.0-P0.50-LS16.0-BL-EP6.2")
      (fields (field (name "MANUFACTURER") "TI(德州仪器)"))
      (libsource (lib "altium-import") (part "root_0_TFP401APZPR_"))
    )
    (comp (ref "U3")
      (value "TFP410PAPR")
      (footprint "HTQFP-64_L10.0-W10.0-P0.50-LS12.0-BL-EP5.0")
      (description "TFP410 165MHz TMDS DVI 变送器/串行器和 Panelbus™ 集成电路")
      (fields (field (name "MANUFACTURER") "TI(德州仪器)"))
      (libsource (lib "altium-import") (part "root_0_TFP410PAPR_"))
    )
    (comp (ref "U4")
      (value "ADV7125BCPZ170-RL")
      (footprint "LFCSP-48_L7.0-W7.0-P0.50-BL-EP5.1")
      (fields (field (name "MANUFACTURER") "ADI(亚德诺)"))
      (libsource (lib "altium-import") (part "root_0_ADV7125BCPZ170-RL_"))
    )
    (comp (ref "U5")
      (value "MT41K256M16TW-107:P")
      (footprint "FBGA-96_L14.0-W8.0-R16-C6-P0.80-TL")
      (description "商业级")
      (fields (field (name "MANUFACTURER") "micron(镁光)"))
      (libsource (lib "altium-import") (part "root_0_MT41K256M16TW-107{colon}P_"))
    )
    (comp (ref "U7")
      (value "TPS51200DRCR")
      (footprint "WSON-10_L3.0-W3.0-P0.50-BL-EP")
      (description "输出电压:-;")
      (fields (field (name "MANUFACTURER") "TI(德州仪器)"))
      (libsource (lib "altium-import") (part "root_0_TPS51200DRCR_"))
    )
    (comp (ref "U8")
      (value "XC6SLX45-3FGG484I")
      (footprint "FBGA-484_L23.0-W23.0-R22-C22-P1.00-TL")
      (fields (field (name "MANUFACTURER") "XILINX(赛灵思)"))
      (libsource (lib "altium-import") (part "root_0_XC6SLX45-3FGG484I_"))
    )
    (comp (ref "U11")
      (value "1625854-2")
      (footprint "TEST-RING")
      (description "PC 测试点 表面贴装")
      (fields (field (name "MANUFACTURER") "TE Connectivity(泰科电子)"))
      (libsource (lib "altium-import") (part "root_1_1625854-2_"))
    )
    (comp (ref "U12")
      (value "MT41K256M16TW-107:P")
      (footprint "FBGA-96_L14.0-W8.0-R16-C6-P0.80-TL")
      (description "商业级")
      (fields (field (name "MANUFACTURER") "micron(镁光)"))
      (libsource (lib "altium-import") (part "root_0_MT41K256M16TW-107{colon}P_"))
    )
    (comp (ref "U13")
      (value "AD1580ARTZ-REEL7")
      (footprint "SOT-23-3_L2.9-W1.6-P1.90-LS2.8-BR")
      (description "输出类型:固定;输入电压:-;输出电压:1.225V;输出电流:10mA;精度:±0.82%;")
      (fields (field (name "MANUFACTURER") "ADI(亚德诺)") (field (name "TOLERANCE") "±0.82%"))
      (libsource (lib "altium-import") (part "root_3_AD1580ARTZ-REEL7_"))
    )
    (comp (ref "U14")
      (value "50Ω")
      (footprint "R0402")
      (description "电阻类型:薄膜电阻;阻值:50Ω;精度:±0.1%;功率:62.5mW;温度系数:±50ppm/℃;")
      (fields (field (name "MANUFACTURER") "YAGEO(国巨)") (field (name "MANUFACTURERPART") "RT0402BRE0750RL"))
      (libsource (lib "altium-import") (part "root_1_RT0402BRE0750RL_"))
    )
    (comp (ref "U15")
      (value "BLM18PG121SN1D")
      (footprint "L0603")
      (description "标称阻抗@测试频率:120Ω@100MHz;误差:±25%;直流电阻(RDC):50mΩ;")
      (fields (field (name "MANUFACTURER") "muRata(村田)") (field (name "TOLERANCE") "±25%"))
      (libsource (lib "altium-import") (part "root_0_BLM18PG121SN1D_"))
    )
    (comp (ref "U16")
      (value "BLM18PG121SN1D")
      (footprint "L0603")
      (description "标称阻抗@测试频率:120Ω@100MHz;误差:±25%;直流电阻(RDC):50mΩ;")
      (fields (field (name "MANUFACTURER") "muRata(村田)") (field (name "TOLERANCE") "±25%"))
      (libsource (lib "altium-import") (part "root_0_BLM18PG121SN1D_"))
    )
    (comp (ref "U17")
      (value "BLM18PG121SN1D")
      (footprint "L0603")
      (description "标称阻抗@测试频率:120Ω@100MHz;误差:±25%;直流电阻(RDC):50mΩ;")
      (fields (field (name "MANUFACTURER") "muRata(村田)") (field (name "TOLERANCE") "±25%"))
      (libsource (lib "altium-import") (part "root_0_BLM18PG121SN1D_"))
    )
    (comp (ref "U18")
      (value "1812L160PR")
      (footprint "F1812")
      (description "最大电压:8V;最大电流:100A;保持电流:1.6A;跳闸电流:2.8A;")
      (fields (field (name "MANUFACTURER") "Littelfuse(美国力特)"))
      (libsource (lib "altium-import") (part "root_0_1812L160PR_"))
    )
    (comp (ref "U19")
      (value "P82B96TD,118")
      (footprint "SOIC-8_L4.9-W3.9-P1.27-LS6.0-BL")
      (description "类型:缓冲器；驱动器;通道数:2;应用:I2C;")
      (fields (field (name "MANUFACTURER") "NXP(恩智浦)"))
      (libsource (lib "altium-import") (part "root_0_P82B96TD,118_"))
    )
    (comp (ref "U21")
      (value "5kΩ")
      (footprint "R0603")
      (description "电阻类型:薄膜电阻;阻值:5kΩ;精度:±0.1%;功率:100mW;温度系数:±50ppm/℃;")
      (fields (field (name "MANUFACTURER") "YAGEO(国巨)") (field (name "MANUFACTURERPART") "RT0603BRE075KL"))
      (libsource (lib "altium-import") (part "root_0_RT0603BRE075KL_"))
    )
    (comp (ref "U22")
      (value "BLM18PG121SN1D")
      (footprint "L0603")
      (description "标称阻抗@测试频率:120Ω@100MHz;误差:±25%;直流电阻(RDC):50mΩ;")
      (fields (field (name "MANUFACTURER") "muRata(村田)") (field (name "TOLERANCE") "±25%"))
      (libsource (lib "altium-import") (part "root_0_BLM18PG121SN1D_"))
    )
    (comp (ref "U23")
      (value "BLM18PG121SN1D")
      (footprint "L0603")
      (description "标称阻抗@测试频率:120Ω@100MHz;误差:±25%;直流电阻(RDC):50mΩ;")
      (fields (field (name "MANUFACTURER") "muRata(村田)") (field (name "TOLERANCE") "±25%"))
      (libsource (lib "altium-import") (part "root_0_BLM18PG121SN1D_"))
    )
    (comp (ref "U24")
      (value "1812L160PR")
      (footprint "F1812")
      (description "最大电压:8V;最大电流:100A;保持电流:1.6A;跳闸电流:2.8A;")
      (fields (field (name "MANUFACTURER") "Littelfuse(美国力特)"))
      (libsource (lib "altium-import") (part "root_0_1812L160PR_"))
    )
    (comp (ref "U25")
      (value "5kΩ")
      (footprint "R0603")
      (description "电阻类型:薄膜电阻;阻值:5kΩ;精度:±0.1%;功率:100mW;温度系数:±50ppm/℃;")
      (fields (field (name "MANUFACTURER") "YAGEO(国巨)") (field (name "MANUFACTURERPART") "RT0603BRE075KL"))
      (libsource (lib "altium-import") (part "root_1_RT0603BRE075KL_"))
    )
    (comp (ref "U26")
      (value "5kΩ")
      (footprint "R0603")
      (description "电阻类型:薄膜电阻;阻值:5kΩ;精度:±0.1%;功率:100mW;温度系数:±50ppm/℃;")
      (fields (field (name "MANUFACTURER") "YAGEO(国巨)") (field (name "MANUFACTURERPART") "RT0603BRE075KL"))
      (libsource (lib "altium-import") (part "root_1_RT0603BRE075KL_"))
    )
    (comp (ref "U27")
      (value "5kΩ")
      (footprint "R0603")
      (description "电阻类型:薄膜电阻;阻值:5kΩ;精度:±0.1%;功率:100mW;温度系数:±50ppm/℃;")
      (fields (field (name "MANUFACTURER") "YAGEO(国巨)") (field (name "MANUFACTURERPART") "RT0603BRE075KL"))
      (libsource (lib "altium-import") (part "root_1_RT0603BRE075KL_"))
    )
    (comp (ref "U31")
      (value "5kΩ")
      (footprint "R0603")
      (description "电阻类型:薄膜电阻;阻值:5kΩ;精度:±0.1%;功率:100mW;温度系数:±50ppm/℃;")
      (fields (field (name "MANUFACTURER") "YAGEO(国巨)") (field (name "MANUFACTURERPART") "RT0603BRE075KL"))
      (libsource (lib "altium-import") (part "root_1_RT0603BRE075KL_"))
    )
    (comp (ref "U33")
      (value "AT24C02C-SSHM-T")
      (footprint "SOIC-8_L5.0-W4.0-P1.27-LS6.0-BL")
      (description "接口类型:I2C;存储容量:2Kbit;")
      (fields (field (name "MANUFACTURER") "MICROCHIP(美国微芯)"))
      (libsource (lib "altium-import") (part "root_0_AT24C02C-SSHM-T_"))
    )
    (comp (ref "U69")
      (value "TPS62130ARGTT")
      (footprint "TQFN-16_L3.0-W3.0-P0.50-TL-EP1.7")
      (fields (field (name "MANUFACTURER") "TI(德州仪器)"))
      (libsource (lib "altium-import") (part "root_0_mirrored_TPS62130ARGTT_"))
    )
    (comp (ref "U70")
      (value "TPS62130ARGTT")
      (footprint "TQFN-16_L3.0-W3.0-P0.50-TL-EP1.7")
      (fields (field (name "MANUFACTURER") "TI(德州仪器)"))
      (libsource (lib "altium-import") (part "root_0_mirrored_TPS62130ARGTT_"))
    )
    (comp (ref "U71")
      (value "TPS54620RHLR")
      (footprint "VQFN-14_L3.5-W3.5-P0.50-TL-EP_TPS54622RHLT")
      (description "功能类型:降压型;输出类型:可调;输入电压:4.5V~17V;输出电压:800mV~15V;输出电流(最大值):6A;")
      (fields (field (name "MANUFACTURER") "TI(德州仪器)"))
      (libsource (lib "altium-import") (part "root_0_TPS54620RHLR_"))
    )
    (comp (ref "U72")
      (value "1625854-2")
      (footprint "TEST-RING")
      (description "PC 测试点 表面贴装")
      (fields (field (name "MANUFACTURER") "TE Connectivity(泰科电子)"))
      (libsource (lib "altium-import") (part "root_1_1625854-2_"))
    )
    (comp (ref "U73")
      (value "1625854-2")
      (footprint "TEST-RING")
      (description "PC 测试点 表面贴装")
      (fields (field (name "MANUFACTURER") "TE Connectivity(泰科电子)"))
      (libsource (lib "altium-import") (part "root_1_1625854-2_"))
    )
    (comp (ref "U74")
      (value "1625854-2")
      (footprint "TEST-RING")
      (description "PC 测试点 表面贴装")
      (fields (field (name "MANUFACTURER") "TE Connectivity(泰科电子)"))
      (libsource (lib "altium-import") (part "root_1_1625854-2_"))
    )
    (comp (ref "U75")
      (value "1625854-2")
      (footprint "TEST-RING")
      (description "PC 测试点 表面贴装")
      (fields (field (name "MANUFACTURER") "TE Connectivity(泰科电子)"))
      (libsource (lib "altium-import") (part "root_1_1625854-2_"))
    )
    (comp (ref "U76")
      (value "1625854-2")
      (footprint "TEST-RING")
      (description "PC 测试点 表面贴装")
      (fields (field (name "MANUFACTURER") "TE Connectivity(泰科电子)"))
      (libsource (lib "altium-import") (part "root_1_1625854-2_"))
    )
    (comp (ref "U77")
      (value "APT3216SGC")
      (footprint "LED1206-RD")
      (description "发光颜色:翠绿色;正向电压(VF):2.2V;正向电流:20mA;主波长:568nm;透镜颜色:无色透明透镜;发光强度:12mcd;发光角度:120°;")
      (fields (field (name "MANUFACTURER") "Kingbright"))
      (libsource (lib "altium-import") (part "root_1_APT3216SGC_"))
    )
    (comp (ref "U78")
      (value "APT3216SGC")
      (footprint "LED1206-RD")
      (description "发光颜色:翠绿色;正向电压(VF):2.2V;正向电流:20mA;主波长:568nm;透镜颜色:无色透明透镜;发光强度:12mcd;发光角度:120°;")
      (fields (field (name "MANUFACTURER") "Kingbright"))
      (libsource (lib "altium-import") (part "root_1_APT3216SGC_"))
    )
    (comp (ref "U79")
      (value "APT3216SGC")
      (footprint "LED1206-RD")
      (description "发光颜色:翠绿色;正向电压(VF):2.2V;正向电流:20mA;主波长:568nm;透镜颜色:无色透明透镜;发光强度:12mcd;发光角度:120°;")
      (fields (field (name "MANUFACTURER") "Kingbright"))
      (libsource (lib "altium-import") (part "root_1_APT3216SGC_"))
    )
    (comp (ref "U80")
      (value "APT3216SGC")
      (footprint "LED1206-RD")
      (description "发光颜色:翠绿色;正向电压(VF):2.2V;正向电流:20mA;主波长:568nm;透镜颜色:无色透明透镜;发光强度:12mcd;发光角度:120°;")
      (fields (field (name "MANUFACTURER") "Kingbright"))
      (libsource (lib "altium-import") (part "root_1_APT3216SGC_"))
    )
    (comp (ref "U81")
      (value "APT3216SGC")
      (footprint "LED1206-RD")
      (description "发光颜色:翠绿色;正向电压(VF):2.2V;正向电流:20mA;主波长:568nm;透镜颜色:无色透明透镜;发光强度:12mcd;发光角度:120°;")
      (fields (field (name "MANUFACTURER") "Kingbright"))
      (libsource (lib "altium-import") (part "root_1_APT3216SGC_"))
    )
    (comp (ref "U82")
      (value "SMTSO3050CTJ")
      (footprint "SMD_SMTSO3060CTJ")
      (description "M3x5.56xL5+1.53")
      (fields (field (name "MANUFACTURER") "Sinhoo(雄和远景)"))
      (libsource (lib "altium-import") (part "root_0_SMTSO3050CTJ_"))
    )
    (comp (ref "U83")
      (value "SMTSO3050CTJ")
      (footprint "SMD_SMTSO3060CTJ")
      (description "M3x5.56xL5+1.53")
      (fields (field (name "MANUFACTURER") "Sinhoo(雄和远景)"))
      (libsource (lib "altium-import") (part "root_0_SMTSO3050CTJ_"))
    )
    (comp (ref "U84")
      (value "SMTSO3050CTJ")
      (footprint "SMD_SMTSO3060CTJ")
      (description "M3x5.56xL5+1.53")
      (fields (field (name "MANUFACTURER") "Sinhoo(雄和远景)"))
      (libsource (lib "altium-import") (part "root_0_SMTSO3050CTJ_"))
    )
    (comp (ref "U85")
      (value "SMTSO3050CTJ")
      (footprint "SMD_SMTSO3060CTJ")
      (description "M3x5.56xL5+1.53")
      (fields (field (name "MANUFACTURER") "Sinhoo(雄和远景)"))
      (libsource (lib "altium-import") (part "root_0_SMTSO3050CTJ_"))
    )
    (comp (ref "U86")
      (value "MARK")
      (footprint "MARK")
      (libsource (lib "altium-import") (part "root_0_MARK_"))
    )
    (comp (ref "U87")
      (value "MARK")
      (footprint "MARK")
      (libsource (lib "altium-import") (part "root_0_MARK_"))
    )
    (comp (ref "U88")
      (value "MARK")
      (footprint "MARK")
      (libsource (lib "altium-import") (part "root_0_MARK_"))
    )
    (comp (ref "U89")
      (value "MARK")
      (footprint "MARK")
      (libsource (lib "altium-import") (part "root_0_MARK_"))
    )
    (comp (ref "U90")
      (value "MARK")
      (footprint "MARK")
      (libsource (lib "altium-import") (part "root_0_MARK_"))
    )
    (comp (ref "U91")
      (value "MARK")
      (footprint "MARK")
      (libsource (lib "altium-import") (part "root_0_MARK_"))
    )
    (comp (ref "U92")
      (value "MARK")
      (footprint "MARK")
      (libsource (lib "altium-import") (part "root_0_MARK_"))
    )
    (comp (ref "U93")
      (value "MARK")
      (footprint "MARK")
      (libsource (lib "altium-import") (part "root_0_MARK_"))
    )
    (comp (ref "U94")
      (value "MARK")
      (footprint "MARK")
      (libsource (lib "altium-import") (part "root_0_MARK_"))
    )
    (comp (ref "U95")
      (value "MARK")
      (footprint "MARK")
      (libsource (lib "altium-import") (part "root_0_MARK_"))
    )
    (comp (ref "U96")
      (value "MARK")
      (footprint "MARK")
      (libsource (lib "altium-import") (part "root_0_MARK_"))
    )
    (comp (ref "U97")
      (value "MARK")
      (footprint "MARK")
      (libsource (lib "altium-import") (part "root_0_MARK_"))
    )
    (comp (ref "U98")
      (value "MARK")
      (footprint "MARK")
      (libsource (lib "altium-import") (part "root_0_MARK_"))
    )
    (comp (ref "U99")
      (value "MARK")
      (footprint "MARK")
      (libsource (lib "altium-import") (part "root_0_MARK_"))
    )
    (comp (ref "U100")
      (value "SN74LVC1G06MDCKREP")
      (footprint "SC-70-5_L2.0-W1.3-P0.65-LS2.1-BL")
      (description "电源电压:1.65V~5.5V;供电电流(最大值):10uA;电路数:1;最大传播延迟(tpd):5.5ns@5V,50pF;")
      (fields (field (name "MANUFACTURER") "TI(德州仪器)"))
      (libsource (lib "altium-import") (part "root_0_SN74LVC1G06MDCKREP_"))
    )
    (comp (ref "U101")
      (value "5kΩ")
      (footprint "R0603")
      (description "电阻类型:薄膜电阻;阻值:5kΩ;精度:±0.1%;功率:100mW;温度系数:±50ppm/℃;")
      (fields (field (name "MANUFACTURER") "YAGEO(国巨)") (field (name "MANUFACTURERPART") "RT0603BRE075KL"))
      (libsource (lib "altium-import") (part "root_1_RT0603BRE075KL_"))
    )
    (comp (ref "U102")
      (value "5kΩ")
      (footprint "R0603")
      (description "电阻类型:薄膜电阻;阻值:5kΩ;精度:±0.1%;功率:100mW;温度系数:±50ppm/℃;")
      (fields (field (name "MANUFACTURER") "YAGEO(国巨)") (field (name "MANUFACTURERPART") "RT0603BRE075KL"))
      (libsource (lib "altium-import") (part "root_1_RT0603BRE075KL_"))
    )
    (comp (ref "U121")
      (value "5kΩ")
      (footprint "R0603")
      (description "电阻类型:薄膜电阻;阻值:5kΩ;精度:±0.1%;功率:100mW;温度系数:±50ppm/℃;")
      (fields (field (name "MANUFACTURER") "YAGEO(国巨)") (field (name "MANUFACTURERPART") "RT0603BRE075KL"))
      (libsource (lib "altium-import") (part "root_1_RT0603BRE075KL_"))
    )
    (comp (ref "U122")
      (value "5kΩ")
      (footprint "R0603")
      (description "电阻类型:薄膜电阻;阻值:5kΩ;精度:±0.1%;功率:100mW;温度系数:±50ppm/℃;")
      (fields (field (name "MANUFACTURER") "YAGEO(国巨)") (field (name "MANUFACTURERPART") "RT0603BRE075KL"))
      (libsource (lib "altium-import") (part "root_1_RT0603BRE075KL_"))
    )
    (comp (ref "U123")
      (value "W25Q128JVSIQ")
      (footprint "SOIC-8_L5.3-W5.3-P1.27-LS8.0-BL")
      (description "接口类型:-;存储容量:128Mbit;时钟频率(fc):-;")
      (fields (field (name "MANUFACTURER") "WINBOND(华邦)"))
      (libsource (lib "altium-import") (part "root_0_W25Q128JVSIQ_"))
    )
    (comp (ref "USB2")
      (value "HDMI-001C")
      (footprint "HDMI-SMD_HDMI-001C")
      (description "连接器类型:HDMI;公母:母;总PIN位数:19P;安装方式:弯插;排数:2;额定电流:500mA;触头材质:-;触头镀层:-;工作温度范围:-45℃~+85℃;")
      (fields (field (name "MANUFACTURER") "XUNPU(讯普)"))
      (libsource (lib "altium-import") (part "root_0_HDMI-001C_C2836126_"))
    )
    (comp (ref "USB3")
      (value "HDMI-001C")
      (footprint "HDMI-SMD_HDMI-001C")
      (description "连接器类型:HDMI;公母:母;总PIN位数:19P;安装方式:弯插;排数:2;额定电流:500mA;触头材质:-;触头镀层:-;工作温度范围:-45℃~+85℃;")
      (fields (field (name "MANUFACTURER") "XUNPU(讯普)"))
      (libsource (lib "altium-import") (part "root_0_HDMI-001C_C2836126_"))
    )
    (comp (ref "X1")
      (value "27MHz")
      (footprint "OSC-SMD_4P-L3.2-W2.5-BL")
      (description "频率:27MHz;常温频差:±10ppm;输出模式:CMOS;工作电压:1.8V~3.3V;")
      (fields
        (field (name "MANUFACTURER") "YXC(扬兴晶振)")
        (field (name "MANUFACTURER PART") "OT2EL4C4JI-111OLP-27M")
      )
      (libsource (lib "altium-import") (part "root_0_OT2EL4C4JI-111OLP-27M_"))
    )
    (comp (ref "X2")
      (value "50MHz")
      (footprint "OSC-SMD_4P-L3.2-W2.5-BL")
      (description "频率:50MHz;输出模式:CMOS;工作电压:1.62V~3.63V;供电电流:8.1mA;频率稳定度(全温):±50ppm;")
      (fields
        (field (name "MANUFACTURER") "EPSON(爱普生)")
        (field (name "MANUFACTURER PART") "SG-8018CE 50.000000MHz TJHPA")
      )
      (libsource (lib "altium-import") (part "root_2_SG-8018CE 50.000000MHz TJHPA_"))
    )
  )
  (nets
    (net (code "1") (name "/27M_CLK") (class "Default")
      (node (ref "R152") (pin "1") (pinfunction "1_1") (pintype "passive"))
      (node (ref "X1") (pin "3") (pinfunction "OUT_3") (pintype "passive"))
    )
    (net (code "2") (name "/27M_CLK_FPGA") (class "Default")
      (node (ref "R152") (pin "2") (pinfunction "2_2") (pintype "passive"))
      (node (ref "U8") (pin "AB13") (pinfunction "IO_L30N_GCLK0_USERCCLK_2_AB13") (pintype "passive"))
    )
    (net (code "3") (name "/50M_CLK") (class "Default")
      (node (ref "R153") (pin "1") (pinfunction "1_1") (pintype "passive"))
      (node (ref "X2") (pin "3") (pinfunction "OUTPUT_3") (pintype "passive"))
    )
    (net (code "4") (name "/50M_CLK_FPGA") (class "Default")
      (node (ref "R153") (pin "2") (pinfunction "2_2") (pintype "passive"))
      (node (ref "U8") (pin "AA12") (pinfunction "IO_L31P_GCLK31_D14_2_AA12") (pintype "passive"))
    )
    (net (code "5") (name "/410_CTL1") (class "Default")
      (node (ref "RN22") (pin "6") (pinfunction "6_6") (pintype "passive"))
      (node (ref "U3") (pin "8") (pinfunction "CTL1/A1/DK1_8") (pintype "passive"))
    )
    (net (code "6") (name "/410_CTL1_FPGA") (class "Default")
      (node (ref "RN22") (pin "3") (pinfunction "3_3") (pintype "passive"))
      (node (ref "U8") (pin "V9") (pinfunction "IO_L50N_2_V9") (pintype "passive"))
    )
    (net (code "7") (name "/410_CTL2") (class "Default")
      (node (ref "RN22") (pin "5") (pinfunction "5_5") (pintype "passive"))
      (node (ref "U3") (pin "7") (pinfunction "CTL2/A2/DK2_7") (pintype "passive"))
    )
    (net (code "8") (name "/410_CTL2_FPGA") (class "Default")
      (node (ref "RN22") (pin "4") (pinfunction "4_4") (pintype "passive"))
      (node (ref "U8") (pin "U9") (pinfunction "IO_L50P_2_U9") (pintype "passive"))
    )
    (net (code "9") (name "/410_CTL3") (class "Default")
      (node (ref "RN1") (pin "8") (pinfunction "8_8") (pintype "passive"))
      (node (ref "U3") (pin "6") (pinfunction "CTL3/A3/DK3_6") (pintype "passive"))
    )
    (net (code "10") (name "/410_CTL3_FPGA") (class "Default")
      (node (ref "RN1") (pin "1") (pinfunction "1_1") (pintype "passive"))
      (node (ref "U8") (pin "AB10") (pinfunction "IO_L41N_VREF_2_AB10") (pintype "passive"))
    )
    (net (code "11") (name "/410_DE") (class "Default")
      (node (ref "RN1") (pin "5") (pinfunction "5_5") (pintype "passive"))
      (node (ref "U3") (pin "2") (pinfunction "DE_2") (pintype "passive"))
    )
    (net (code "12") (name "/410_DE_FPGA") (class "Default")
      (node (ref "RN1") (pin "4") (pinfunction "4_4") (pintype "passive"))
      (node (ref "U8") (pin "Y11") (pinfunction "IO_L32P_GCLK29_2_Y11") (pintype "passive"))
    )
    (net (code "13") (name "/410_HSYNC") (class "Default")
      (node (ref "RN1") (pin "6") (pinfunction "6_6") (pintype "passive"))
      (node (ref "U3") (pin "4") (pinfunction "HSYNC_4") (pintype "passive"))
    )
    (net (code "14") (name "/410_HSYNC_FPGA") (class "Default")
      (node (ref "RN1") (pin "3") (pinfunction "3_3") (pintype "passive"))
      (node (ref "U8") (pin "Y10") (pinfunction "IO_L44N_2_Y10") (pintype "passive"))
    )
    (net (code "15") (name "/410_VSYNC") (class "Default")
      (node (ref "RN1") (pin "7") (pinfunction "7_7") (pintype "passive"))
      (node (ref "U3") (pin "5") (pinfunction "VSYNC_5") (pintype "passive"))
    )
    (net (code "16") (name "/410_VSYNC_FPGA") (class "Default")
      (node (ref "RN1") (pin "2") (pinfunction "2_2") (pintype "passive"))
      (node (ref "U8") (pin "AA10") (pinfunction "IO_L41P_2_AA10") (pintype "passive"))
    )
    (net (code "17") (name "/7125_B0") (class "Default")
      (node (ref "RN17") (pin "5") (pinfunction "5_5") (pintype "passive"))
      (node (ref "U4") (pin "16") (pinfunction "B0_16") (pintype "passive"))
    )
    (net (code "18") (name "/7125_B0_FPGA") (class "Default")
      (node (ref "RN17") (pin "4") (pinfunction "4_4") (pintype "passive"))
      (node (ref "U8") (pin "AB4") (pinfunction "IO_L57N_2_AB4") (pintype "passive"))
    )
    (net (code "19") (name "/7125_B1") (class "Default")
      (node (ref "RN17") (pin "6") (pinfunction "6_6") (pintype "passive"))
      (node (ref "U4") (pin "17") (pinfunction "B1_17") (pintype "passive"))
    )
    (net (code "20") (name "/7125_B1_FPGA") (class "Default")
      (node (ref "RN17") (pin "3") (pinfunction "3_3") (pintype "passive"))
      (node (ref "U8") (pin "AA4") (pinfunction "IO_L57P_2_AA4") (pintype "passive"))
    )
    (net (code "21") (name "/7125_B2") (class "Default")
      (node (ref "RN17") (pin "7") (pinfunction "7_7") (pintype "passive"))
      (node (ref "U4") (pin "18") (pinfunction "B2_18") (pintype "passive"))
    )
    (net (code "22") (name "/7125_B2_FPGA") (class "Default")
      (node (ref "RN17") (pin "2") (pinfunction "2_2") (pintype "passive"))
      (node (ref "U8") (pin "Y4") (pinfunction "IO_L62N_D6_2_Y4") (pintype "passive"))
    )
    (net (code "23") (name "/7125_B3") (class "Default")
      (node (ref "RN17") (pin "8") (pinfunction "8_8") (pintype "passive"))
      (node (ref "U4") (pin "19") (pinfunction "B3_19") (pintype "passive"))
    )
    (net (code "24") (name "/7125_B3_FPGA") (class "Default")
      (node (ref "RN17") (pin "1") (pinfunction "1_1") (pintype "passive"))
      (node (ref "U8") (pin "AB3") (pinfunction "IO_L58N_2_AB3") (pintype "passive"))
    )
    (net (code "25") (name "/7125_B4") (class "Default")
      (node (ref "RN16") (pin "5") (pinfunction "5_5") (pintype "passive"))
      (node (ref "U4") (pin "20") (pinfunction "B4_20") (pintype "passive"))
    )
    (net (code "26") (name "/7125_B4_FPGA") (class "Default")
      (node (ref "RN16") (pin "4") (pinfunction "4_4") (pintype "passive"))
      (node (ref "U8") (pin "W4") (pinfunction "IO_L62P_D5_2_W4") (pintype "passive"))
    )
    (net (code "27") (name "/7125_B5") (class "Default")
      (node (ref "RN16") (pin "6") (pinfunction "6_6") (pintype "passive"))
      (node (ref "U4") (pin "21") (pinfunction "B5_21") (pintype "passive"))
    )
    (net (code "28") (name "/7125_B5_FPGA") (class "Default")
      (node (ref "RN16") (pin "3") (pinfunction "3_3") (pintype "passive"))
      (node (ref "U8") (pin "Y3") (pinfunction "IO_L58P_2_Y3") (pintype "passive"))
    )
    (net (code "29") (name "/7125_B6") (class "Default")
      (node (ref "RN16") (pin "7") (pinfunction "7_7") (pintype "passive"))
      (node (ref "U4") (pin "22") (pinfunction "B6_22") (pintype "passive"))
    )
    (net (code "30") (name "/7125_B6_FPGA") (class "Default")
      (node (ref "RN16") (pin "2") (pinfunction "2_2") (pintype "passive"))
      (node (ref "U8") (pin "AB2") (pinfunction "IO_L64N_D9_2_AB2") (pintype "passive"))
    )
    (net (code "31") (name "/7125_B7") (class "Default")
      (node (ref "RN16") (pin "8") (pinfunction "8_8") (pintype "passive"))
      (node (ref "U4") (pin "23") (pinfunction "B7_23") (pintype "passive"))
    )
    (net (code "32") (name "/7125_B7_FPGA") (class "Default")
      (node (ref "RN16") (pin "1") (pinfunction "1_1") (pintype "passive"))
      (node (ref "U8") (pin "AA2") (pinfunction "IO_L64P_D8_2_AA2") (pintype "passive"))
    )
    (net (code "33") (name "/7125_BLK") (class "Default")
      (node (ref "R81") (pin "2") (pinfunction "2_2") (pintype "passive"))
      (node (ref "RN18") (pin "7") (pinfunction "7_7") (pintype "passive"))
      (node (ref "U4") (pin "11") (pinfunction "BLANK#_11") (pintype "passive"))
    )
    (net (code "34") (name "/7125_BLK_FPGA") (class "Default")
      (node (ref "RN18") (pin "2") (pinfunction "2_2") (pintype "passive"))
      (node (ref "U8") (pin "Y5") (pinfunction "IO_L54P_2_Y5") (pintype "passive"))
    )
    (net (code "35") (name "/7125_CLK") (class "Default")
      (node (ref "R184") (pin "1") (pinfunction "1_1") (pintype "passive"))
      (node (ref "U14") (pin "2") (pinfunction "2_2") (pintype "passive"))
      (node (ref "U4") (pin "24") (pinfunction "CLOCK_24") (pintype "passive"))
    )
    (net (code "36") (name "/7125_CLK_FPGA") (class "Default")
      (node (ref "R184") (pin "2") (pinfunction "2_2") (pintype "passive"))
      (node (ref "U8") (pin "AB11") (pinfunction "IO_L32N_GCLK28_2_AB11") (pintype "passive"))
    )
    (net (code "37") (name "/7125_G0") (class "Default")
      (node (ref "RN20") (pin "7") (pinfunction "7_7") (pintype "passive"))
      (node (ref "U4") (pin "3") (pinfunction "G0_3") (pintype "passive"))
    )
    (net (code "38") (name "/7125_G0_FPGA") (class "Default")
      (node (ref "RN20") (pin "2") (pinfunction "2_2") (pintype "passive"))
      (node (ref "U8") (pin "V7") (pinfunction "IO_L46N_2_V7") (pintype "passive"))
    )
    (net (code "39") (name "/7125_G1") (class "Default")
      (node (ref "RN20") (pin "8") (pinfunction "8_8") (pintype "passive"))
      (node (ref "U4") (pin "4") (pinfunction "G1_4") (pintype "passive"))
    )
    (net (code "40") (name "/7125_G1_FPGA") (class "Default")
      (node (ref "RN20") (pin "1") (pinfunction "1_1") (pintype "passive"))
      (node (ref "U8") (pin "AB7") (pinfunction "IO_L48N_RDWR_B_VREF_2_AB7") (pintype "passive"))
    )
    (net (code "41") (name "/7125_G2") (class "Default")
      (node (ref "RN19") (pin "5") (pinfunction "5_5") (pintype "passive"))
      (node (ref "U4") (pin "5") (pinfunction "G2_5") (pintype "passive"))
    )
    (net (code "42") (name "/7125_G2_FPGA") (class "Default")
      (node (ref "RN19") (pin "4") (pinfunction "4_4") (pintype "passive"))
      (node (ref "U8") (pin "Y6") (pinfunction "IO_L53N_2_Y6") (pintype "passive"))
    )
    (net (code "43") (name "/7125_G3") (class "Default")
      (node (ref "RN19") (pin "6") (pinfunction "6_6") (pintype "passive"))
      (node (ref "U4") (pin "6") (pinfunction "G3_6") (pintype "passive"))
    )
    (net (code "44") (name "/7125_G3_FPGA") (class "Default")
      (node (ref "RN19") (pin "3") (pinfunction "3_3") (pintype "passive"))
      (node (ref "U8") (pin "AA6") (pinfunction "IO_L49P_D3_2_AA6") (pintype "passive"))
    )
    (net (code "45") (name "/7125_G4") (class "Default")
      (node (ref "RN19") (pin "7") (pinfunction "7_7") (pintype "passive"))
      (node (ref "U4") (pin "7") (pinfunction "G4_7") (pintype "passive"))
    )
    (net (code "46") (name "/7125_G4_FPGA") (class "Default")
      (node (ref "RN19") (pin "2") (pinfunction "2_2") (pintype "passive"))
      (node (ref "U8") (pin "AB6") (pinfunction "IO_L49N_D4_2_AB6") (pintype "passive"))
    )
    (net (code "47") (name "/7125_G5") (class "Default")
      (node (ref "RN19") (pin "8") (pinfunction "8_8") (pintype "passive"))
      (node (ref "U4") (pin "8") (pinfunction "G5_8") (pintype "passive"))
    )
    (net (code "48") (name "/7125_G5_FPGA") (class "Default")
      (node (ref "RN19") (pin "1") (pinfunction "1_1") (pintype "passive"))
      (node (ref "U8") (pin "W6") (pinfunction "IO_L53P_2_W6") (pintype "passive"))
    )
    (net (code "49") (name "/7125_G6") (class "Default")
      (node (ref "RN18") (pin "5") (pinfunction "5_5") (pintype "passive"))
      (node (ref "U4") (pin "9") (pinfunction "G6_9") (pintype "passive"))
    )
    (net (code "50") (name "/7125_G6_FPGA") (class "Default")
      (node (ref "RN18") (pin "4") (pinfunction "4_4") (pintype "passive"))
      (node (ref "U8") (pin "U6") (pinfunction "IO_L63P_2_U6") (pintype "passive"))
    )
    (net (code "51") (name "/7125_G7") (class "Default")
      (node (ref "RN18") (pin "6") (pinfunction "6_6") (pintype "passive"))
      (node (ref "U4") (pin "10") (pinfunction "G7_10") (pintype "passive"))
    )
    (net (code "52") (name "/7125_G7_FPGA") (class "Default")
      (node (ref "RN18") (pin "3") (pinfunction "3_3") (pintype "passive"))
      (node (ref "U8") (pin "AB5") (pinfunction "IO_L54N_2_AB5") (pintype "passive"))
    )
    (net (code "53") (name "/7125_PS") (class "Default")
      (node (ref "R83") (pin "1") (pinfunction "1_1") (pintype "passive"))
      (node (ref "U4") (pin "38") (pinfunction "PSAVE#_38") (pintype "passive"))
    )
    (net (code "54") (name "/7125_R0") (class "Default")
      (node (ref "RN14") (pin "7") (pinfunction "7_7") (pintype "passive"))
      (node (ref "U4") (pin "41") (pinfunction "R0_41") (pintype "passive"))
    )
    (net (code "55") (name "/7125_R0_FPGA") (class "Default")
      (node (ref "RN14") (pin "2") (pinfunction "2_2") (pintype "passive"))
      (node (ref "U8") (pin "T10") (pinfunction "IO_L52P_2_T10") (pintype "passive"))
    )
    (net (code "56") (name "/7125_R1") (class "Default")
      (node (ref "RN14") (pin "8") (pinfunction "8_8") (pintype "passive"))
      (node (ref "U4") (pin "42") (pinfunction "R1_42") (pintype "passive"))
    )
    (net (code "57") (name "/7125_R1_FPGA") (class "Default")
      (node (ref "RN14") (pin "1") (pinfunction "1_1") (pintype "passive"))
      (node (ref "U8") (pin "R7") (pinfunction "IO_L60N_2_R7") (pintype "passive"))
    )
    (net (code "58") (name "/7125_R2") (class "Default")
      (node (ref "RN15") (pin "5") (pinfunction "5_5") (pintype "passive"))
      (node (ref "U4") (pin "43") (pinfunction "R2_43") (pintype "passive"))
    )
    (net (code "59") (name "/7125_R2_FPGA") (class "Default")
      (node (ref "RN15") (pin "4") (pinfunction "4_4") (pintype "passive"))
      (node (ref "U8") (pin "W9") (pinfunction "IO_L47P_2_W9") (pintype "passive"))
    )
    (net (code "60") (name "/7125_R3") (class "Default")
      (node (ref "RN15") (pin "6") (pinfunction "6_6") (pintype "passive"))
      (node (ref "U4") (pin "44") (pinfunction "R3_44") (pintype "passive"))
    )
    (net (code "61") (name "/7125_R3_FPGA") (class "Default")
      (node (ref "RN15") (pin "3") (pinfunction "3_3") (pintype "passive"))
      (node (ref "U8") (pin "W8") (pinfunction "IO_L46P_2_W8") (pintype "passive"))
    )
    (net (code "62") (name "/7125_R4") (class "Default")
      (node (ref "RN15") (pin "7") (pinfunction "7_7") (pintype "passive"))
      (node (ref "U4") (pin "45") (pinfunction "R4_45") (pintype "passive"))
    )
    (net (code "63") (name "/7125_R4_FPGA") (class "Default")
      (node (ref "RN15") (pin "2") (pinfunction "2_2") (pintype "passive"))
      (node (ref "U8") (pin "Y8") (pinfunction "IO_L47N_2_Y8") (pintype "passive"))
    )
    (net (code "64") (name "/7125_R5") (class "Default")
      (node (ref "RN15") (pin "8") (pinfunction "8_8") (pintype "passive"))
      (node (ref "U4") (pin "46") (pinfunction "R5_46") (pintype "passive"))
    )
    (net (code "65") (name "/7125_R5_FPGA") (class "Default")
      (node (ref "RN15") (pin "1") (pinfunction "1_1") (pintype "passive"))
      (node (ref "U8") (pin "AA8") (pinfunction "IO_L45P_2_AA8") (pintype "passive"))
    )
    (net (code "66") (name "/7125_R6") (class "Default")
      (node (ref "RN20") (pin "5") (pinfunction "5_5") (pintype "passive"))
      (node (ref "U4") (pin "47") (pinfunction "R6_47") (pintype "passive"))
    )
    (net (code "67") (name "/7125_R6_FPGA") (class "Default")
      (node (ref "RN20") (pin "4") (pinfunction "4_4") (pintype "passive"))
      (node (ref "U8") (pin "AB8") (pinfunction "IO_L45N_2_AB8") (pintype "passive"))
    )
    (net (code "68") (name "/7125_R7") (class "Default")
      (node (ref "RN20") (pin "6") (pinfunction "6_6") (pintype "passive"))
      (node (ref "U4") (pin "48") (pinfunction "R7_48") (pintype "passive"))
    )
    (net (code "69") (name "/7125_R7_FPGA") (class "Default")
      (node (ref "RN20") (pin "3") (pinfunction "3_3") (pintype "passive"))
      (node (ref "U8") (pin "T7") (pinfunction "IO_L60P_2_T7") (pintype "passive"))
    )
    (net (code "70") (name "/7125_SYC") (class "Default")
      (node (ref "R82") (pin "2") (pinfunction "2_2") (pintype "passive"))
      (node (ref "RN18") (pin "8") (pinfunction "8_8") (pintype "passive"))
      (node (ref "U4") (pin "12") (pinfunction "SYNC#_12") (pintype "passive"))
    )
    (net (code "71") (name "/7125_SYC_FPGA") (class "Default")
      (node (ref "RN18") (pin "1") (pinfunction "1_1") (pintype "passive"))
      (node (ref "U8") (pin "V5") (pinfunction "IO_L63N_2_V5") (pintype "passive"))
    )
    (net (code "72") (name "/7125_VGA_HSYC") (class "Default")
      (node (ref "Q3") (pin "2") (pinfunction "S_2") (pintype "passive"))
      (node (ref "R92") (pin "1") (pinfunction "1_1") (pintype "passive"))
      (node (ref "RN24") (pin "7") (pinfunction "7_7") (pintype "passive"))
    )
    (net (code "73") (name "/7125_VGA_HSYC_FPGA") (class "Default")
      (node (ref "RN24") (pin "2") (pinfunction "2_2") (pintype "passive"))
      (node (ref "U8") (pin "T8") (pinfunction "IO_L51P_2_T8") (pintype "passive"))
    )
    (net (code "74") (name "/7125_VGA_SCL") (class "Default")
      (node (ref "Q2") (pin "2") (pinfunction "S_2") (pintype "passive"))
      (node (ref "R89") (pin "1") (pinfunction "1_1") (pintype "passive"))
      (node (ref "RN24") (pin "6") (pinfunction "6_6") (pintype "passive"))
    )
    (net (code "75") (name "/7125_VGA_SCL_FPGA") (class "Default")
      (node (ref "RN24") (pin "3") (pinfunction "3_3") (pintype "passive"))
      (node (ref "U8") (pin "U8") (pinfunction "IO_L51N_2_U8") (pintype "passive"))
    )
    (net (code "76") (name "/7125_VGA_SDA") (class "Default")
      (node (ref "Q1") (pin "2") (pinfunction "S_2") (pintype "passive"))
      (node (ref "R88") (pin "1") (pinfunction "1_1") (pintype "passive"))
      (node (ref "RN24") (pin "5") (pinfunction "5_5") (pintype "passive"))
    )
    (net (code "77") (name "/7125_VGA_SDA_FPGA") (class "Default")
      (node (ref "RN24") (pin "4") (pinfunction "4_4") (pintype "passive"))
      (node (ref "U8") (pin "R9") (pinfunction "IO_L59P_2_R9") (pintype "passive"))
    )
    (net (code "78") (name "/7125_VGA_VSYC") (class "Default")
      (node (ref "Q4") (pin "2") (pinfunction "S_2") (pintype "passive"))
      (node (ref "R93") (pin "1") (pinfunction "1_1") (pintype "passive"))
      (node (ref "RN24") (pin "8") (pinfunction "8_8") (pintype "passive"))
    )
    (net (code "79") (name "/7125_VGA_VSYC_FPGA") (class "Default")
      (node (ref "RN24") (pin "1") (pinfunction "1_1") (pintype "passive"))
      (node (ref "U8") (pin "R8") (pinfunction "IO_L59N_2_R8") (pintype "passive"))
    )
    (net (code "80") (name "/7125_VREF") (class "Default")
      (node (ref "C111") (pin "2") (pinfunction "2_2") (pintype "passive"))
      (node (ref "R87") (pin "1") (pinfunction "1_1") (pintype "passive"))
      (node (ref "U13") (pin "1") (pinfunction "V+_1") (pintype "passive"))
      (node (ref "U4") (pin "36") (pinfunction "VREF_36") (pintype "passive"))
    )
    (net (code "81") (name "/BSEL") (class "Default")
      (node (ref "RN2") (pin "5") (pinfunction "5_5") (pintype "passive"))
      (node (ref "SW1") (pin "4") (pinfunction "A4_4") (pintype "passive"))
      (node (ref "U3") (pin "15") (pinfunction "BSEL/SCL_15") (pintype "passive"))
    )
    (net (code "82") (name "/DFO") (class "Default")
      (node (ref "RN3") (pin "7") (pinfunction "7_7") (pintype "passive"))
      (node (ref "SW2") (pin "2") (pinfunction "A2_2") (pintype "passive"))
      (node (ref "U2") (pin "1") (pinfunction "DFO_1") (pintype "passive"))
    )
    (net (code "83") (name "/DSEL") (class "Default")
      (node (ref "RN2") (pin "6") (pinfunction "6_6") (pintype "passive"))
      (node (ref "SW1") (pin "3") (pinfunction "A3_3") (pintype "passive"))
      (node (ref "U3") (pin "14") (pinfunction "DSEL/SDA_14") (pintype "passive"))
    )
    (net (code "84") (name "/DVI_5V") (class "Default")
      (node (ref "C149") (pin "2") (pinfunction "2_2") (pintype "passive"))
      (node (ref "U24") (pin "2") (pinfunction "2_2") (pintype "passive"))
      (node (ref "USB2") (pin "18") (pinfunction "+5VPower_18") (pintype "passive"))
    )
    (net (code "85") (name "/DVI_C_CLK+") (class "Default")
      (node (ref "D8") (pin "4") (pinfunction "IN_4") (pintype "passive"))
      (node (ref "D8") (pin "7") (pinfunction "NC_7") (pintype "passive"))
      (node (ref "U3") (pin "22") (pinfunction "TXC+_22") (pintype "passive"))
      (node (ref "USB2") (pin "10") (pinfunction "TMDSClock+_10") (pintype "passive"))
    )
    (net (code "86") (name "/DVI_C_CLK-") (class "Default")
      (node (ref "D8") (pin "5") (pinfunction "IN_5") (pintype "passive"))
      (node (ref "D8") (pin "6") (pinfunction "NC_6") (pintype "passive"))
      (node (ref "U3") (pin "21") (pinfunction "TXC-_21") (pintype "passive"))
      (node (ref "USB2") (pin "12") (pinfunction "TMDSClock-_12") (pintype "passive"))
    )
    (net (code "87") (name "/DVI_C_D0+") (class "Default")
      (node (ref "D8") (pin "1") (pinfunction "IN_1") (pintype "passive"))
      (node (ref "D8") (pin "10") (pinfunction "NC_10") (pintype "passive"))
      (node (ref "U3") (pin "25") (pinfunction "TX0+_25") (pintype "passive"))
      (node (ref "USB2") (pin "7") (pinfunction "TMDSData0+_7") (pintype "passive"))
    )
    (net (code "88") (name "/DVI_C_D0-") (class "Default")
      (node (ref "D8") (pin "2") (pinfunction "IN_2") (pintype "passive"))
      (node (ref "D8") (pin "9") (pinfunction "NC_9") (pintype "passive"))
      (node (ref "U3") (pin "24") (pinfunction "TX0-_24") (pintype "passive"))
      (node (ref "USB2") (pin "9") (pinfunction "TMDSData0-_9") (pintype "passive"))
    )
    (net (code "89") (name "/DVI_C_D1+") (class "Default")
      (node (ref "D7") (pin "4") (pinfunction "IN_4") (pintype "passive"))
      (node (ref "D7") (pin "7") (pinfunction "NC_7") (pintype "passive"))
      (node (ref "U3") (pin "28") (pinfunction "TX1+_28") (pintype "passive"))
      (node (ref "USB2") (pin "4") (pinfunction "TMDSData1+_4") (pintype "passive"))
    )
    (net (code "90") (name "/DVI_C_D1-") (class "Default")
      (node (ref "D7") (pin "5") (pinfunction "IN_5") (pintype "passive"))
      (node (ref "D7") (pin "6") (pinfunction "NC_6") (pintype "passive"))
      (node (ref "U3") (pin "27") (pinfunction "TX1-_27") (pintype "passive"))
      (node (ref "USB2") (pin "6") (pinfunction "TMDSData1-_6") (pintype "passive"))
    )
    (net (code "91") (name "/DVI_C_D2+") (class "Default")
      (node (ref "D7") (pin "1") (pinfunction "IN_1") (pintype "passive"))
      (node (ref "D7") (pin "10") (pinfunction "NC_10") (pintype "passive"))
      (node (ref "U3") (pin "31") (pinfunction "TX2+_31") (pintype "passive"))
      (node (ref "USB2") (pin "1") (pinfunction "TMDSData2+_1") (pintype "passive"))
    )
    (net (code "92") (name "/DVI_C_D2-") (class "Default")
      (node (ref "D7") (pin "2") (pinfunction "IN_2") (pintype "passive"))
      (node (ref "D7") (pin "9") (pinfunction "NC_9") (pintype "passive"))
      (node (ref "U3") (pin "30") (pinfunction "TX2-_30") (pintype "passive"))
      (node (ref "USB2") (pin "3") (pinfunction "TMDSData2-_3") (pintype "passive"))
    )
    (net (code "93") (name "/DVI_HPD") (class "Default")
      (node (ref "Q6") (pin "3") (pinfunction "D_3") (pintype "passive"))
      (node (ref "U27") (pin "1") (pinfunction "1_1") (pintype "passive"))
      (node (ref "U8") (pin "W11") (pinfunction "IO_L42N_2_W11") (pintype "passive"))
    )
    (net (code "94") (name "/DVI_HPD_EXT") (class "Default")
      (node (ref "D12") (pin "4") (pinfunction "4_4") (pintype "passive"))
      (node (ref "Q5") (pin "1") (pinfunction "G_1") (pintype "passive"))
      (node (ref "U25") (pin "2") (pinfunction "2_2") (pintype "passive"))
      (node (ref "USB2") (pin "19") (pinfunction "HotPlugDetect_19") (pintype "passive"))
    )
    (net (code "95") (name "/DVI_SCL") (class "Default")
      (node (ref "D12") (pin "1") (pinfunction "1_1") (pintype "passive"))
      (node (ref "Q8") (pin "3") (pinfunction "D_3") (pintype "passive"))
      (node (ref "R107") (pin "1") (pinfunction "1_1") (pintype "passive"))
      (node (ref "U19") (pin "2") (pinfunction "RX_2") (pintype "passive"))
      (node (ref "U19") (pin "3") (pinfunction "TX_3") (pintype "passive"))
      (node (ref "USB2") (pin "15") (pinfunction "SCL_15") (pintype "passive"))
    )
    (net (code "96") (name "/DVI_SDA") (class "Default")
      (node (ref "D12") (pin "6") (pinfunction "6_6") (pintype "passive"))
      (node (ref "Q7") (pin "3") (pinfunction "D_3") (pintype "passive"))
      (node (ref "R106") (pin "2") (pinfunction "2_2") (pintype "passive"))
      (node (ref "U19") (pin "5") (pinfunction "TY_5") (pintype "passive"))
      (node (ref "U19") (pin "6") (pinfunction "RY_6") (pintype "passive"))
      (node (ref "USB2") (pin "16") (pinfunction "SDA_16") (pintype "passive"))
    )
    (net (code "97") (name "/DW_A0") (class "Default")
      (node (ref "R64") (pin "1") (pinfunction "1_1") (pintype "passive"))
      (node (ref "U12") (pin "N3") (pinfunction "A0_N3") (pintype "passive"))
      (node (ref "U8") (pin "F21") (pinfunction "IO_L37P_A7_M1A0_1_F21") (pintype "passive"))
    )
    (net (code "98") (name "/DW_A1") (class "Default")
      (node (ref "R69") (pin "1") (pinfunction "1_1") (pintype "passive"))
      (node (ref "U12") (pin "P7") (pinfunction "A1_P7") (pintype "passive"))
      (node (ref "U8") (pin "F22") (pinfunction "IO_L37N_A6_M1A1_1_F22") (pintype "passive"))
    )
    (net (code "99") (name "/DW_A2") (class "Default")
      (node (ref "R68") (pin "1") (pinfunction "1_1") (pintype "passive"))
      (node (ref "U12") (pin "P3") (pinfunction "A2_P3") (pintype "passive"))
      (node (ref "U8") (pin "E22") (pinfunction "IO_L35N_A10_M1A2_1_E22") (pintype "passive"))
    )
    (net (code "100") (name "/DW_A3") (class "Default")
      (node (ref "R63") (pin "1") (pinfunction "1_1") (pintype "passive"))
      (node (ref "U12") (pin "N2") (pinfunction "A3_N2") (pintype "passive"))
      (node (ref "U8") (pin "G20") (pinfunction "IO_L39P_M1A3_1_G20") (pintype "passive"))
    )
    (net (code "101") (name "/DW_A4") (class "Default")
      (node (ref "R70") (pin "1") (pinfunction "1_1") (pintype "passive"))
      (node (ref "U12") (pin "P8") (pinfunction "A4_P8") (pintype "passive"))
      (node (ref "U8") (pin "F20") (pinfunction "IO_L33N_A14_M1A4_1_F20") (pintype "passive"))
    )
    (net (code "102") (name "/DW_A5") (class "Default")
      (node (ref "R67") (pin "1") (pinfunction "1_1") (pintype "passive"))
      (node (ref "U12") (pin "P2") (pinfunction "A5_P2") (pintype "passive"))
      (node (ref "U8") (pin "K20") (pinfunction "IO_L40P_GCLK11_M1A5_1_K20") (pintype "passive"))
    )
    (net (code "103") (name "/DW_A6") (class "Default")
      (node (ref "R74") (pin "1") (pinfunction "1_1") (pintype "passive"))
      (node (ref "U12") (pin "R8") (pinfunction "A6_R8") (pintype "passive"))
      (node (ref "U8") (pin "K19") (pinfunction "IO_L40N_GCLK10_M1A6_1_K19") (pintype "passive"))
    )
    (net (code "104") (name "/DW_A7") (class "Default")
      (node (ref "R71") (pin "1") (pinfunction "1_1") (pintype "passive"))
      (node (ref "U12") (pin "R2") (pinfunction "A7_R2") (pintype "passive"))
      (node (ref "U8") (pin "E20") (pinfunction "IO_L35P_A11_M1A7_1_E20") (pintype "passive"))
    )
    (net (code "105") (name "/DW_A8") (class "Default")
      (node (ref "R77") (pin "1") (pinfunction "1_1") (pintype "passive"))
      (node (ref "U12") (pin "T8") (pinfunction "A8_T8") (pintype "passive"))
      (node (ref "U8") (pin "C20") (pinfunction "IO_L32P_A17_M1A8_1_C20") (pintype "passive"))
    )
    (net (code "106") (name "/DW_A9") (class "Default")
      (node (ref "R72") (pin "1") (pinfunction "1_1") (pintype "passive"))
      (node (ref "U12") (pin "R3") (pinfunction "A9_R3") (pintype "passive"))
      (node (ref "U8") (pin "C22") (pinfunction "IO_L32N_A16_M1A9_1_C22") (pintype "passive"))
    )
    (net (code "107") (name "/DW_A10") (class "Default")
      (node (ref "R60") (pin "1") (pinfunction "1_1") (pintype "passive"))
      (node (ref "U12") (pin "L7") (pinfunction "A10/AP_L7") (pintype "passive"))
      (node (ref "U8") (pin "G19") (pinfunction "IO_L33P_A15_M1A10_1_G19") (pintype "passive"))
    )
    (net (code "108") (name "/DW_A11") (class "Default")
      (node (ref "R73") (pin "1") (pinfunction "1_1") (pintype "passive"))
      (node (ref "U12") (pin "R7") (pinfunction "A11_R7") (pintype "passive"))
      (node (ref "U8") (pin "F19") (pinfunction "IO_L30N_A20_M1A11_1_F19") (pintype "passive"))
    )
    (net (code "109") (name "/DW_A12") (class "Default")
      (node (ref "R65") (pin "1") (pinfunction "1_1") (pintype "passive"))
      (node (ref "U12") (pin "N7") (pinfunction "A12/BC#_N7") (pintype "passive"))
      (node (ref "U8") (pin "D22") (pinfunction "IO_L31N_A18_M1A12_1_D22") (pintype "passive"))
    )
    (net (code "110") (name "/DW_A13") (class "Default")
      (node (ref "R75") (pin "1") (pinfunction "1_1") (pintype "passive"))
      (node (ref "U12") (pin "T3") (pinfunction "A13_T3") (pintype "passive"))
      (node (ref "U8") (pin "D19") (pinfunction "IO_L29P_A23_M1A13_1_D19") (pintype "passive"))
    )
    (net (code "111") (name "/DW_A14") (class "Default")
      (node (ref "R76") (pin "1") (pinfunction "1_1") (pintype "passive"))
      (node (ref "U12") (pin "T7") (pinfunction "A14_T7") (pintype "passive"))
      (node (ref "U8") (pin "D20") (pinfunction "IO_L29N_A22_M1A14_1_D20") (pintype "passive"))
    )
    (net (code "112") (name "/DW_BA0") (class "Default")
      (node (ref "R61") (pin "1") (pinfunction "1_1") (pintype "passive"))
      (node (ref "U12") (pin "M2") (pinfunction "BA0_M2") (pintype "passive"))
      (node (ref "U8") (pin "J17") (pinfunction "IO_L36P_A9_M1BA0_1_J17") (pintype "passive"))
    )
    (net (code "113") (name "/DW_BA1") (class "Default")
      (node (ref "R66") (pin "1") (pinfunction "1_1") (pintype "passive"))
      (node (ref "U12") (pin "N8") (pinfunction "BA1_N8") (pintype "passive"))
      (node (ref "U8") (pin "K17") (pinfunction "IO_L36N_A8_M1BA1_1_K17") (pintype "passive"))
    )
    (net (code "114") (name "/DW_BA2") (class "Default")
      (node (ref "R62") (pin "1") (pinfunction "1_1") (pintype "passive"))
      (node (ref "U12") (pin "M3") (pinfunction "BA2_M3") (pintype "passive"))
      (node (ref "U8") (pin "H18") (pinfunction "IO_L34N_A12_M1BA2_1_H18") (pintype "passive"))
    )
    (net (code "115") (name "/DW_CAS") (class "Default")
      (node (ref "R57") (pin "1") (pinfunction "1_1") (pintype "passive"))
      (node (ref "U12") (pin "K3") (pinfunction "CAS#_K3") (pintype "passive"))
      (node (ref "U8") (pin "H22") (pinfunction "IO_L41N_GCLK8_M1CASN_1_H22") (pintype "passive"))
    )
    (net (code "116") (name "/DW_CK+") (class "Default")
      (node (ref "R155") (pin "1") (pinfunction "1_1") (pintype "passive"))
      (node (ref "U12") (pin "J7") (pinfunction "CK_J7") (pintype "passive"))
      (node (ref "U8") (pin "H20") (pinfunction "IO_L38P_A5_M1CLK_1_H20") (pintype "passive"))
    )
    (net (code "117") (name "/DW_CK-") (class "Default")
      (node (ref "R155") (pin "2") (pinfunction "2_2") (pintype "passive"))
      (node (ref "U12") (pin "K7") (pinfunction "CK#_K7") (pintype "passive"))
      (node (ref "U8") (pin "J19") (pinfunction "IO_L38N_A4_M1CLKN_1_J19") (pintype "passive"))
    )
    (net (code "118") (name "/DW_CKE") (class "Default")
      (node (ref "R51") (pin "1") (pinfunction "1_1") (pintype "passive"))
      (node (ref "U12") (pin "K9") (pinfunction "CKE_K9") (pintype "passive"))
      (node (ref "U8") (pin "D21") (pinfunction "IO_L31P_A19_M1CKE_1_D21") (pintype "passive"))
    )
    (net (code "119") (name "/DW_D0") (class "Default")
      (node (ref "U12") (pin "E3") (pinfunction "DQ0_E3") (pintype "passive"))
      (node (ref "U8") (pin "N20") (pinfunction "IO_L47P_FWE_B_M1DQ0_1_N20") (pintype "passive"))
    )
    (net (code "120") (name "/DW_D1") (class "Default")
      (node (ref "U12") (pin "F7") (pinfunction "DQ1_F7") (pintype "passive"))
      (node (ref "U8") (pin "N22") (pinfunction "IO_L47N_LDC_M1DQ1_1_N22") (pintype "passive"))
    )
    (net (code "121") (name "/DW_D2") (class "Default")
      (node (ref "U12") (pin "F2") (pinfunction "DQ2_F2") (pintype "passive"))
      (node (ref "U8") (pin "M21") (pinfunction "IO_L46P_FCS_B_M1DQ2_1_M21") (pintype "passive"))
    )
    (net (code "122") (name "/DW_D3") (class "Default")
      (node (ref "U12") (pin "F8") (pinfunction "DQ3_F8") (pintype "passive"))
      (node (ref "U8") (pin "M22") (pinfunction "IO_L46N_FOE_B_M1DQ3_1_M22") (pintype "passive"))
    )
    (net (code "123") (name "/DW_D4") (class "Default")
      (node (ref "U12") (pin "H3") (pinfunction "DQ4_H3") (pintype "passive"))
      (node (ref "U8") (pin "J20") (pinfunction "IO_L43P_GCLK5_M1DQ4_1_J20") (pintype "passive"))
    )
    (net (code "124") (name "/DW_D5") (class "Default")
      (node (ref "U12") (pin "H8") (pinfunction "DQ5_H8") (pintype "passive"))
      (node (ref "U8") (pin "J22") (pinfunction "IO_L43N_GCLK4_M1DQ5_1_J22") (pintype "passive"))
    )
    (net (code "125") (name "/DW_D6") (class "Default")
      (node (ref "U12") (pin "G2") (pinfunction "DQ6_G2") (pintype "passive"))
      (node (ref "U8") (pin "K21") (pinfunction "IO_L44P_A3_M1DQ6_1_K21") (pintype "passive"))
    )
    (net (code "126") (name "/DW_D7") (class "Default")
      (node (ref "U12") (pin "H7") (pinfunction "DQ7_H7") (pintype "passive"))
      (node (ref "U8") (pin "K22") (pinfunction "IO_L44N_A2_M1DQ7_1_K22") (pintype "passive"))
    )
    (net (code "127") (name "/DW_D8") (class "Default")
      (node (ref "U12") (pin "D7") (pinfunction "DQ8_D7") (pintype "passive"))
      (node (ref "U8") (pin "P21") (pinfunction "IO_L48P_HDC_M1DQ8_1_P21") (pintype "passive"))
    )
    (net (code "128") (name "/DW_D9") (class "Default")
      (node (ref "U12") (pin "C3") (pinfunction "DQ9_C3") (pintype "passive"))
      (node (ref "U8") (pin "P22") (pinfunction "IO_L48N_M1DQ9_1_P22") (pintype "passive"))
    )
    (net (code "129") (name "/DW_D10") (class "Default")
      (node (ref "U12") (pin "C8") (pinfunction "DQ10_C8") (pintype "passive"))
      (node (ref "U8") (pin "R20") (pinfunction "IO_L49P_M1DQ10_1_R20") (pintype "passive"))
    )
    (net (code "130") (name "/DW_D11") (class "Default")
      (node (ref "U12") (pin "C2") (pinfunction "DQ11_C2") (pintype "passive"))
      (node (ref "U8") (pin "R22") (pinfunction "IO_L49N_M1DQ11_1_R22") (pintype "passive"))
    )
    (net (code "131") (name "/DW_D12") (class "Default")
      (node (ref "U12") (pin "A7") (pinfunction "DQ12_A7") (pintype "passive"))
      (node (ref "U8") (pin "U20") (pinfunction "IO_L51P_M1DQ12_1_U20") (pintype "passive"))
    )
    (net (code "132") (name "/DW_D13") (class "Default")
      (node (ref "U12") (pin "A2") (pinfunction "DQ13_A2") (pintype "passive"))
      (node (ref "U8") (pin "U22") (pinfunction "IO_L51N_M1DQ13_1_U22") (pintype "passive"))
    )
    (net (code "133") (name "/DW_D14") (class "Default")
      (node (ref "U12") (pin "B8") (pinfunction "DQ14_B8") (pintype "passive"))
      (node (ref "U8") (pin "V21") (pinfunction "IO_L52P_M1DQ14_1_V21") (pintype "passive"))
    )
    (net (code "134") (name "/DW_D15") (class "Default")
      (node (ref "U12") (pin "A3") (pinfunction "DQ15_A3") (pintype "passive"))
      (node (ref "U8") (pin "V22") (pinfunction "IO_L52N_M1DQ15_1_V22") (pintype "passive"))
    )
    (net (code "135") (name "/DW_LDM") (class "Default")
      (node (ref "R186") (pin "1") (pinfunction "1_1") (pintype "passive"))
      (node (ref "U12") (pin "E7") (pinfunction "LDM_E7") (pintype "passive"))
    )
    (net (code "136") (name "/DW_LDQS+") (class "Default")
      (node (ref "U12") (pin "F3") (pinfunction "LDQS_F3") (pintype "passive"))
      (node (ref "U8") (pin "L20") (pinfunction "IO_L45P_A1_M1LDQS_1_L20") (pintype "passive"))
    )
    (net (code "137") (name "/DW_LDQS-") (class "Default")
      (node (ref "U12") (pin "G3") (pinfunction "LDQS#_G3") (pintype "passive"))
      (node (ref "U8") (pin "L22") (pinfunction "IO_L45N_A0_M1LDQSN_1_L22") (pintype "passive"))
    )
    (net (code "138") (name "/DW_ODT") (class "Default")
      (node (ref "R56") (pin "1") (pinfunction "1_1") (pintype "passive"))
      (node (ref "U12") (pin "K1") (pinfunction "ODT_K1") (pintype "passive"))
      (node (ref "U8") (pin "G22") (pinfunction "IO_L39N_M1ODT_1_G22") (pintype "passive"))
    )
    (net (code "139") (name "/DW_RAS") (class "Default")
      (node (ref "R54") (pin "1") (pinfunction "1_1") (pintype "passive"))
      (node (ref "U12") (pin "J3") (pinfunction "RAS#_J3") (pintype "passive"))
      (node (ref "U8") (pin "H21") (pinfunction "IO_L41P_GCLK9_IRDY1_M1RASN_1_H21") (pintype "passive"))
    )
    (net (code "140") (name "/DW_RST") (class "Default")
      (node (ref "R52") (pin "1") (pinfunction "1_1") (pintype "passive"))
      (node (ref "U12") (pin "T2") (pinfunction "RESET#_T2") (pintype "passive"))
      (node (ref "U8") (pin "F18") (pinfunction "IO_L30P_A21_M1RESET_1_F18") (pintype "passive"))
    )
    (net (code "141") (name "/DW_UDM") (class "Default")
      (node (ref "R187") (pin "1") (pinfunction "1_1") (pintype "passive"))
      (node (ref "U12") (pin "D3") (pinfunction "UDM_D3") (pintype "passive"))
    )
    (net (code "142") (name "/DW_UDQS+") (class "Default")
      (node (ref "U12") (pin "C7") (pinfunction "UDQS_C7") (pintype "passive"))
      (node (ref "U8") (pin "T21") (pinfunction "IO_L50P_M1UDQS_1_T21") (pintype "passive"))
    )
    (net (code "143") (name "/DW_UDQS-") (class "Default")
      (node (ref "U12") (pin "B7") (pinfunction "UDQS#_B7") (pintype "passive"))
      (node (ref "U8") (pin "T22") (pinfunction "IO_L50N_M1UDQSN_1_T22") (pintype "passive"))
    )
    (net (code "144") (name "/DW_WE") (class "Default")
      (node (ref "R59") (pin "1") (pinfunction "1_1") (pintype "passive"))
      (node (ref "U12") (pin "L3") (pinfunction "WE#_L3") (pintype "passive"))
      (node (ref "U8") (pin "H19") (pinfunction "IO_L34P_A13_M1WE_1_H19") (pintype "passive"))
    )
    (net (code "145") (name "/EDGE") (class "Default")
      (node (ref "U121") (pin "1") (pinfunction "1_1") (pintype "passive"))
      (node (ref "U122") (pin "2") (pinfunction "2_2") (pintype "passive"))
      (node (ref "U3") (pin "9") (pinfunction "EDGE/HTPLG_9") (pintype "passive"))
    )
    (net (code "146") (name "/FPGA_27M_OUT") (class "Default")
      (node (ref "U8") (pin "U19") (pinfunction "IO_L70P_1_U19") (pintype "passive"))
    )
    (net (code "147") (name "/FPGA_ADV7393_HS") (class "Default")
      (node (ref "U8") (pin "F17") (pinfunction "IO_L10N_1_F17") (pintype "passive"))
    )
    (net (code "148") (name "/FPGA_ADV7393_P0") (class "Default")
      (node (ref "U8") (pin "C19") (pinfunction "IO_L1P_A25_1_C19") (pintype "passive"))
    )
    (net (code "149") (name "/FPGA_ADV7393_P1") (class "Default")
      (node (ref "U8") (pin "A20") (pinfunction "IO_L20P_1_A20") (pintype "passive"))
    )
    (net (code "150") (name "/FPGA_ADV7393_P2") (class "Default")
      (node (ref "U8") (pin "A21") (pinfunction "IO_L20N_1_A21") (pintype "passive"))
    )
    (net (code "151") (name "/FPGA_ADV7393_P3") (class "Default")
      (node (ref "U8") (pin "B21") (pinfunction "IO_L19P_1_B21") (pintype "passive"))
    )
    (net (code "152") (name "/FPGA_ADV7393_P4") (class "Default")
      (node (ref "U8") (pin "B22") (pinfunction "IO_L19N_1_B22") (pintype "passive"))
    )
    (net (code "153") (name "/FPGA_ADV7393_P5") (class "Default")
      (node (ref "U8") (pin "M18") (pinfunction "IO_L71N_1_M18") (pintype "passive"))
    )
    (net (code "154") (name "/FPGA_ADV7393_P6") (class "Default")
      (node (ref "U8") (pin "M17") (pinfunction "IO_L71P_1_M17") (pintype "passive"))
    )
    (net (code "155") (name "/FPGA_ADV7393_P7") (class "Default")
      (node (ref "U8") (pin "M16") (pinfunction "IO_L58P_1_M16") (pintype "passive"))
    )
    (net (code "156") (name "/FPGA_ADV7393_P8") (class "Default")
      (node (ref "U8") (pin "P20") (pinfunction "IO_L59N_1_P20") (pintype "passive"))
    )
    (net (code "157") (name "/FPGA_ADV7393_P9") (class "Default")
      (node (ref "U8") (pin "P19") (pinfunction "IO_L59P_1_P19") (pintype "passive"))
    )
    (net (code "158") (name "/FPGA_ADV7393_P10") (class "Default")
      (node (ref "U8") (pin "W22") (pinfunction "IO_L60N_1_W22") (pintype "passive"))
    )
    (net (code "159") (name "/FPGA_ADV7393_P11") (class "Default")
      (node (ref "U8") (pin "T20") (pinfunction "IO_L74N_DOUT_BUSY_1_T20") (pintype "passive"))
    )
    (net (code "160") (name "/FPGA_ADV7393_P12") (class "Default")
      (node (ref "U8") (pin "V20") (pinfunction "IO_L70N_1_V20") (pintype "passive"))
    )
    (net (code "161") (name "/FPGA_ADV7393_P13") (class "Default")
      (node (ref "U8") (pin "W20") (pinfunction "IO_L60P_1_W20") (pintype "passive"))
    )
    (net (code "162") (name "/FPGA_ADV7393_P14") (class "Default")
      (node (ref "U8") (pin "P18") (pinfunction "IO_L73P_1_P18") (pintype "passive"))
    )
    (net (code "163") (name "/FPGA_ADV7393_P15") (class "Default")
      (node (ref "U8") (pin "P17") (pinfunction "IO_L72P_1_P17") (pintype "passive"))
    )
    (net (code "164") (name "/FPGA_ADV7393_RESET") (class "Default")
      (node (ref "U8") (pin "T19") (pinfunction "IO_L74P_AWAKE_1_T19") (pintype "passive"))
    )
    (net (code "165") (name "/FPGA_ADV7393_SCL") (class "Default")
      (node (ref "U8") (pin "R19") (pinfunction "IO_L73N_1_R19") (pintype "passive"))
    )
    (net (code "166") (name "/FPGA_ADV7393_SDA") (class "Default")
      (node (ref "U8") (pin "N16") (pinfunction "IO_L72N_1_N16") (pintype "passive"))
    )
    (net (code "167") (name "/FPGA_ADV7393_VS") (class "Default")
      (node (ref "U8") (pin "F16") (pinfunction "IO_L10P_1_F16") (pintype "passive"))
    )
    (net (code "168") (name "/FPGA_DONE") (class "Default")
      (node (ref "LED1") (pin "4") (pinfunction "A_4") (pintype "passive"))
      (node (ref "R18") (pin "2") (pinfunction "2_2") (pintype "passive"))
      (node (ref "U100") (pin "2") (pinfunction "A_2") (pintype "passive"))
      (node (ref "U8") (pin "Y22") (pinfunction "DONE_2_Y22") (pintype "passive"))
    )
    (net (code "169") (name "/FPGA_DVI_SCL") (class "Default")
      (node (ref "Q8") (pin "2") (pinfunction "S_2") (pintype "passive"))
      (node (ref "R105") (pin "1") (pinfunction "1_1") (pintype "passive"))
      (node (ref "U19") (pin "1") (pinfunction "SX_1") (pintype "passive"))
      (node (ref "U8") (pin "AA21") (pinfunction "IO_L2P_CMPCLK_2_AA21") (pintype "passive"))
    )
    (net (code "170") (name "/FPGA_DVI_SDA") (class "Default")
      (node (ref "Q7") (pin "2") (pinfunction "S_2") (pintype "passive"))
      (node (ref "R104") (pin "1") (pinfunction "1_1") (pintype "passive"))
      (node (ref "U19") (pin "7") (pinfunction "SY_7") (pintype "passive"))
      (node (ref "U8") (pin "AB21") (pinfunction "IO_L2N_CMPMOSI_2_AB21") (pintype "passive"))
    )
    (net (code "171") (name "/FPGA_RXD") (class "Default")
      (node (ref "R160") (pin "2") (pinfunction "2_2") (pintype "passive"))
      (node (ref "U8") (pin "R15") (pinfunction "IO_L10N_2_R15") (pintype "passive"))
    )
    (net (code "172") (name "/FPGA_TCK") (class "Default")
      (node (ref "D4") (pin "3") (pinfunction "AK_3") (pintype "passive"))
      (node (ref "R22") (pin "2") (pinfunction "2_2") (pintype "passive"))
      (node (ref "U8") (pin "G15") (pinfunction "TCK_G15") (pintype "passive"))
    )
    (net (code "173") (name "/FPGA_TDI") (class "Default")
      (node (ref "D3") (pin "3") (pinfunction "AK_3") (pintype "passive"))
      (node (ref "R21") (pin "2") (pinfunction "2_2") (pintype "passive"))
      (node (ref "U8") (pin "E18") (pinfunction "TDI_E18") (pintype "passive"))
    )
    (net (code "174") (name "/FPGA_TDO") (class "Default")
      (node (ref "D2") (pin "3") (pinfunction "AK_3") (pintype "passive"))
      (node (ref "R20") (pin "2") (pinfunction "2_2") (pintype "passive"))
      (node (ref "U8") (pin "A19") (pinfunction "TDO_A19") (pintype "passive"))
    )
    (net (code "175") (name "/FPGA_TMS") (class "Default")
      (node (ref "D1") (pin "3") (pinfunction "AK_3") (pintype "passive"))
      (node (ref "R19") (pin "2") (pinfunction "2_2") (pintype "passive"))
      (node (ref "U8") (pin "C18") (pinfunction "TMS_C18") (pintype "passive"))
    )
    (net (code "176") (name "/FPGA_TXD") (class "Default")
      (node (ref "R159") (pin "2") (pinfunction "2_2") (pintype "passive"))
      (node (ref "U8") (pin "V17") (pinfunction "IO_L11P_2_V17") (pintype "passive"))
    )
    (net (code "177") (name "/HDMI_SCL") (class "Default")
      (node (ref "Q12") (pin "2") (pinfunction "S_2") (pintype "passive"))
      (node (ref "R109") (pin "1") (pinfunction "1_1") (pintype "passive"))
      (node (ref "U33") (pin "6") (pinfunction "SCL_6") (pintype "passive"))
      (node (ref "U8") (pin "A13") (pinfunction "IO_L38N_VREF_0_A13") (pintype "passive"))
    )
    (net (code "178") (name "/HDMI_SDA") (class "Default")
      (node (ref "Q11") (pin "2") (pinfunction "S_2") (pintype "passive"))
      (node (ref "R108") (pin "1") (pinfunction "1_1") (pintype "passive"))
      (node (ref "U33") (pin "5") (pinfunction "SDA_5") (pintype "passive"))
      (node (ref "U8") (pin "A17") (pinfunction "IO_L64N_SCP4_0_A17") (pintype "passive"))
    )
    (net (code "179") (name "/HSYC") (class "Default")
      (node (ref "D6") (pin "4") (pinfunction "4_4") (pintype "passive"))
      (node (ref "DSUB1") (pin "13") (pinfunction "13_13") (pintype "passive"))
      (node (ref "Q3") (pin "3") (pinfunction "D_3") (pintype "passive"))
      (node (ref "R94") (pin "2") (pinfunction "2_2") (pintype "passive"))
    )
    (net (code "180") (name "/IN_5V") (class "Default")
      (node (ref "D21") (pin "1") (pinfunction "C_1") (pintype "passive"))
      (node (ref "F1") (pin "2") (pinfunction "2_2") (pintype "passive"))
      (node (ref "USB3") (pin "18") (pinfunction "+5VPower_18") (pintype "passive"))
    )
    (net (code "181") (name "/IN_HPD") (class "Default")
      (node (ref "D16") (pin "4") (pinfunction "4_4") (pintype "passive"))
      (node (ref "Q10") (pin "3") (pinfunction "D_3") (pintype "passive"))
      (node (ref "R112") (pin "1") (pinfunction "1_1") (pintype "passive"))
      (node (ref "USB3") (pin "19") (pinfunction "HotPlugDetect_19") (pintype "passive"))
    )
    (net (code "182") (name "/IN_SCL") (class "Default")
      (node (ref "D16") (pin "1") (pinfunction "1_1") (pintype "passive"))
      (node (ref "Q12") (pin "3") (pinfunction "D_3") (pintype "passive"))
      (node (ref "R111") (pin "1") (pinfunction "1_1") (pintype "passive"))
      (node (ref "USB3") (pin "15") (pinfunction "SCL_15") (pintype "passive"))
    )
    (net (code "183") (name "/IN_SDA") (class "Default")
      (node (ref "D16") (pin "6") (pinfunction "6_6") (pintype "passive"))
      (node (ref "Q11") (pin "3") (pinfunction "D_3") (pintype "passive"))
      (node (ref "R110") (pin "2") (pinfunction "2_2") (pintype "passive"))
      (node (ref "USB3") (pin "16") (pinfunction "SDA_16") (pintype "passive"))
    )
    (net (code "184") (name "/ISEL") (class "Default")
      (node (ref "RN2") (pin "7") (pinfunction "7_7") (pintype "passive"))
      (node (ref "SW1") (pin "2") (pinfunction "A2_2") (pintype "passive"))
      (node (ref "U3") (pin "13") (pinfunction "ISEL/RST#_13") (pintype "passive"))
    )
    (net (code "185") (name "/MSEN") (class "Default")
      (node (ref "RN2") (pin "8") (pinfunction "8_8") (pintype "passive"))
      (node (ref "SW1") (pin "1") (pinfunction "A1_1") (pintype "passive"))
      (node (ref "U21") (pin "2") (pinfunction "2_2") (pintype "passive"))
      (node (ref "U3") (pin "11") (pinfunction "MSEN/PO1_11") (pintype "passive"))
    )
    (net (code "186") (name "/OCK_INV") (class "Default")
      (node (ref "RN3") (pin "8") (pinfunction "8_8") (pintype "passive"))
      (node (ref "SW2") (pin "1") (pinfunction "A1_1") (pintype "passive"))
      (node (ref "U2") (pin "100") (pinfunction "OCK_INV_100") (pintype "passive"))
    )
    (net (code "187") (name "/PIXS") (class "Default")
      (node (ref "RN3") (pin "5") (pinfunction "5_5") (pintype "passive"))
      (node (ref "SW2") (pin "4") (pinfunction "A4_4") (pintype "passive"))
      (node (ref "U2") (pin "4") (pinfunction "PIXS_4") (pintype "passive"))
    )
    (net (code "188") (name "/QSPI_CCLK") (class "Default")
      (node (ref "R11") (pin "1") (pinfunction "1_1") (pintype "passive"))
      (node (ref "R24") (pin "1") (pinfunction "1_1") (pintype "passive"))
      (node (ref "R25") (pin "2") (pinfunction "2_2") (pintype "passive"))
      (node (ref "U123") (pin "6") (pinfunction "CLK_6") (pintype "passive"))
    )
    (net (code "189") (name "/QSPI_CS") (class "Default")
      (node (ref "R12") (pin "1") (pinfunction "1_1") (pintype "passive"))
      (node (ref "R15") (pin "1") (pinfunction "1_1") (pintype "passive"))
      (node (ref "U123") (pin "1") (pinfunction "CS#_1") (pintype "passive"))
    )
    (net (code "190") (name "/QSPI_DIN") (class "Default")
      (node (ref "R7") (pin "1") (pinfunction "1_1") (pintype "passive"))
      (node (ref "U123") (pin "2") (pinfunction "DO_2") (pintype "passive"))
    )
    (net (code "191") (name "/QSPI_HOLD") (class "Default")
      (node (ref "R13") (pin "1") (pinfunction "1_1") (pintype "passive"))
      (node (ref "R16") (pin "1") (pinfunction "1_1") (pintype "passive"))
      (node (ref "U123") (pin "7") (pinfunction "IO3_7") (pintype "passive"))
    )
    (net (code "192") (name "/QSPI_OUT") (class "Default")
      (node (ref "R6") (pin "1") (pinfunction "1_1") (pintype "passive"))
      (node (ref "U123") (pin "5") (pinfunction "DI_5") (pintype "passive"))
    )
    (net (code "193") (name "/QSPI_WP") (class "Default")
      (node (ref "R14") (pin "1") (pinfunction "1_1") (pintype "passive"))
      (node (ref "R17") (pin "1") (pinfunction "1_1") (pintype "passive"))
      (node (ref "U123") (pin "3") (pinfunction "IO2_3") (pintype "passive"))
    )
    (net (code "194") (name "/RXD") (class "Default")
      (node (ref "R160") (pin "1") (pinfunction "1_1") (pintype "passive"))
    )
    (net (code "195") (name "/ST") (class "Default")
      (node (ref "RN3") (pin "6") (pinfunction "6_6") (pintype "passive"))
      (node (ref "SW2") (pin "3") (pinfunction "A3_3") (pintype "passive"))
      (node (ref "U2") (pin "3") (pinfunction "ST_3") (pintype "passive"))
    )
    (net (code "196") (name "/TCK") (class "Default")
      (node (ref "CN2") (pin "1") (pinfunction "1_1") (pintype "passive"))
      (node (ref "R22") (pin "1") (pinfunction "1_1") (pintype "passive"))
    )
    (net (code "197") (name "/TDI") (class "Default")
      (node (ref "CN2") (pin "9") (pinfunction "9_9") (pintype "passive"))
      (node (ref "R21") (pin "1") (pinfunction "1_1") (pintype "passive"))
    )
    (net (code "198") (name "/TDO") (class "Default")
      (node (ref "CN2") (pin "3") (pinfunction "3_3") (pintype "passive"))
      (node (ref "R20") (pin "1") (pinfunction "1_1") (pintype "passive"))
    )
    (net (code "199") (name "/TFP401_C+") (class "Default")
      (node (ref "D14") (pin "4") (pinfunction "IN_4") (pintype "passive"))
      (node (ref "D14") (pin "7") (pinfunction "NC_7") (pintype "passive"))
      (node (ref "U2") (pin "93") (pinfunction "RxC+_93") (pintype "passive"))
      (node (ref "USB3") (pin "10") (pinfunction "TMDSClock+_10") (pintype "passive"))
    )
    (net (code "200") (name "/TFP401_C-") (class "Default")
      (node (ref "D14") (pin "5") (pinfunction "IN_5") (pintype "passive"))
      (node (ref "D14") (pin "6") (pinfunction "NC_6") (pintype "passive"))
      (node (ref "U2") (pin "94") (pinfunction "RxC−_94") (pintype "passive"))
      (node (ref "USB3") (pin "12") (pinfunction "TMDSClock-_12") (pintype "passive"))
    )
    (net (code "201") (name "/TFP401_CTL1") (class "Default")
      (node (ref "RN13") (pin "5") (pinfunction "5_5") (pintype "passive"))
      (node (ref "U2") (pin "40") (pinfunction "CTL1_40") (pintype "passive"))
    )
    (net (code "202") (name "/TFP401_CTL1_FPGA") (class "Default")
      (node (ref "RN13") (pin "4") (pinfunction "4_4") (pintype "passive"))
      (node (ref "U8") (pin "A16") (pinfunction "IO_L63N_SCP6_0_A16") (pintype "passive"))
    )
    (net (code "203") (name "/TFP401_CTL2") (class "Default")
      (node (ref "RN13") (pin "6") (pinfunction "6_6") (pintype "passive"))
      (node (ref "U2") (pin "41") (pinfunction "CTL2_41") (pintype "passive"))
    )
    (net (code "204") (name "/TFP401_CTL2_FPGA") (class "Default")
      (node (ref "RN13") (pin "3") (pinfunction "3_3") (pintype "passive"))
      (node (ref "U8") (pin "B16") (pinfunction "IO_L63P_SCP7_0_B16") (pintype "passive"))
    )
    (net (code "205") (name "/TFP401_CTL3") (class "Default")
      (node (ref "RN13") (pin "7") (pinfunction "7_7") (pintype "passive"))
      (node (ref "U2") (pin "42") (pinfunction "CTL3_42") (pintype "passive"))
    )
    (net (code "206") (name "/TFP401_CTL3_FPGA") (class "Default")
      (node (ref "RN13") (pin "2") (pinfunction "2_2") (pintype "passive"))
      (node (ref "U8") (pin "D17") (pinfunction "IO_L66N_SCP0_0_D17") (pintype "passive"))
    )
    (net (code "207") (name "/TFP401_D0") (class "Default")
      (node (ref "RN7") (pin "5") (pinfunction "5_5") (pintype "passive"))
      (node (ref "U2") (pin "10") (pinfunction "QE0_10") (pintype "passive"))
    )
    (net (code "208") (name "/TFP401_D0+") (class "Default")
      (node (ref "D14") (pin "1") (pinfunction "IN_1") (pintype "passive"))
      (node (ref "D14") (pin "10") (pinfunction "NC_10") (pintype "passive"))
      (node (ref "U2") (pin "90") (pinfunction "Rx0+_90") (pintype "passive"))
      (node (ref "USB3") (pin "7") (pinfunction "TMDSData0+_7") (pintype "passive"))
    )
    (net (code "209") (name "/TFP401_D0-") (class "Default")
      (node (ref "D14") (pin "2") (pinfunction "IN_2") (pintype "passive"))
      (node (ref "D14") (pin "9") (pinfunction "NC_9") (pintype "passive"))
      (node (ref "U2") (pin "91") (pinfunction "Rx0−_91") (pintype "passive"))
      (node (ref "USB3") (pin "9") (pinfunction "TMDSData0-_9") (pintype "passive"))
    )
    (net (code "210") (name "/TFP401_D0_FPGA") (class "Default")
      (node (ref "RN7") (pin "4") (pinfunction "4_4") (pintype "passive"))
      (node (ref "U8") (pin "C5") (pinfunction "IO_L2P_0_C5") (pintype "passive"))
    )
    (net (code "211") (name "/TFP401_D1") (class "Default")
      (node (ref "RN7") (pin "6") (pinfunction "6_6") (pintype "passive"))
      (node (ref "U2") (pin "11") (pinfunction "QE1_11") (pintype "passive"))
    )
    (net (code "212") (name "/TFP401_D1+") (class "Default")
      (node (ref "D13") (pin "4") (pinfunction "IN_4") (pintype "passive"))
      (node (ref "D13") (pin "7") (pinfunction "NC_7") (pintype "passive"))
      (node (ref "U2") (pin "85") (pinfunction "Rx1+_85") (pintype "passive"))
      (node (ref "USB3") (pin "4") (pinfunction "TMDSData1+_4") (pintype "passive"))
    )
    (net (code "213") (name "/TFP401_D1-") (class "Default")
      (node (ref "D13") (pin "5") (pinfunction "IN_5") (pintype "passive"))
      (node (ref "D13") (pin "6") (pinfunction "NC_6") (pintype "passive"))
      (node (ref "U2") (pin "86") (pinfunction "Rx1−_86") (pintype "passive"))
      (node (ref "USB3") (pin "6") (pinfunction "TMDSData1-_6") (pintype "passive"))
    )
    (net (code "214") (name "/TFP401_D1_FPGA") (class "Default")
      (node (ref "RN7") (pin "3") (pinfunction "3_3") (pintype "passive"))
      (node (ref "U8") (pin "A5") (pinfunction "IO_L2N_0_A5") (pintype "passive"))
    )
    (net (code "215") (name "/TFP401_D2") (class "Default")
      (node (ref "RN7") (pin "7") (pinfunction "7_7") (pintype "passive"))
      (node (ref "U2") (pin "12") (pinfunction "QE2_12") (pintype "passive"))
    )
    (net (code "216") (name "/TFP401_D2+") (class "Default")
      (node (ref "D13") (pin "1") (pinfunction "IN_1") (pintype "passive"))
      (node (ref "D13") (pin "10") (pinfunction "NC_10") (pintype "passive"))
      (node (ref "U2") (pin "80") (pinfunction "Rx2+_80") (pintype "passive"))
      (node (ref "USB3") (pin "1") (pinfunction "TMDSData2+_1") (pintype "passive"))
    )
    (net (code "217") (name "/TFP401_D2-") (class "Default")
      (node (ref "D13") (pin "2") (pinfunction "IN_2") (pintype "passive"))
      (node (ref "D13") (pin "9") (pinfunction "NC_9") (pintype "passive"))
      (node (ref "U2") (pin "81") (pinfunction "Rx2−_81") (pintype "passive"))
      (node (ref "USB3") (pin "3") (pinfunction "TMDSData2-_3") (pintype "passive"))
    )
    (net (code "218") (name "/TFP401_D2_FPGA") (class "Default")
      (node (ref "RN7") (pin "2") (pinfunction "2_2") (pintype "passive"))
      (node (ref "U8") (pin "D6") (pinfunction "IO_L3P_0_D6") (pintype "passive"))
    )
    (net (code "219") (name "/TFP401_D3") (class "Default")
      (node (ref "RN7") (pin "8") (pinfunction "8_8") (pintype "passive"))
      (node (ref "U2") (pin "13") (pinfunction "QE3_13") (pintype "passive"))
    )
    (net (code "220") (name "/TFP401_D3_FPGA") (class "Default")
      (node (ref "RN7") (pin "1") (pinfunction "1_1") (pintype "passive"))
      (node (ref "U8") (pin "C6") (pinfunction "IO_L3N_0_C6") (pintype "passive"))
    )
    (net (code "221") (name "/TFP401_D4") (class "Default")
      (node (ref "RN8") (pin "5") (pinfunction "5_5") (pintype "passive"))
      (node (ref "U2") (pin "14") (pinfunction "QE4_14") (pintype "passive"))
    )
    (net (code "222") (name "/TFP401_D4_FPGA") (class "Default")
      (node (ref "RN8") (pin "4") (pinfunction "4_4") (pintype "passive"))
      (node (ref "U8") (pin "A6") (pinfunction "IO_L4N_0_A6") (pintype "passive"))
    )
    (net (code "223") (name "/TFP401_D5") (class "Default")
      (node (ref "RN8") (pin "6") (pinfunction "6_6") (pintype "passive"))
      (node (ref "U2") (pin "15") (pinfunction "QE5_15") (pintype "passive"))
    )
    (net (code "224") (name "/TFP401_D5_FPGA") (class "Default")
      (node (ref "RN8") (pin "3") (pinfunction "3_3") (pintype "passive"))
      (node (ref "U8") (pin "B6") (pinfunction "IO_L4P_0_B6") (pintype "passive"))
    )
    (net (code "225") (name "/TFP401_D6") (class "Default")
      (node (ref "RN8") (pin "7") (pinfunction "7_7") (pintype "passive"))
      (node (ref "U2") (pin "16") (pinfunction "QE6_16") (pintype "passive"))
    )
    (net (code "226") (name "/TFP401_D6_FPGA") (class "Default")
      (node (ref "RN8") (pin "2") (pinfunction "2_2") (pintype "passive"))
      (node (ref "U8") (pin "C7") (pinfunction "IO_L5P_0_C7") (pintype "passive"))
    )
    (net (code "227") (name "/TFP401_D7") (class "Default")
      (node (ref "RN8") (pin "8") (pinfunction "8_8") (pintype "passive"))
      (node (ref "U2") (pin "17") (pinfunction "QE7_17") (pintype "passive"))
    )
    (net (code "228") (name "/TFP401_D7_FPGA") (class "Default")
      (node (ref "RN8") (pin "1") (pinfunction "1_1") (pintype "passive"))
      (node (ref "U8") (pin "A7") (pinfunction "IO_L5N_0_A7") (pintype "passive"))
    )
    (net (code "229") (name "/TFP401_D8") (class "Default")
      (node (ref "RN9") (pin "5") (pinfunction "5_5") (pintype "passive"))
      (node (ref "U2") (pin "20") (pinfunction "QE8_20") (pintype "passive"))
    )
    (net (code "230") (name "/TFP401_D8_FPGA") (class "Default")
      (node (ref "RN9") (pin "4") (pinfunction "4_4") (pintype "passive"))
      (node (ref "U8") (pin "D7") (pinfunction "IO_L32P_0_D7") (pintype "passive"))
    )
    (net (code "231") (name "/TFP401_D9") (class "Default")
      (node (ref "RN9") (pin "6") (pinfunction "6_6") (pintype "passive"))
      (node (ref "U2") (pin "21") (pinfunction "QE9_21") (pintype "passive"))
    )
    (net (code "232") (name "/TFP401_D9_FPGA") (class "Default")
      (node (ref "RN9") (pin "3") (pinfunction "3_3") (pintype "passive"))
      (node (ref "U8") (pin "D8") (pinfunction "IO_L32N_0_D8") (pintype "passive"))
    )
    (net (code "233") (name "/TFP401_D10") (class "Default")
      (node (ref "RN9") (pin "7") (pinfunction "7_7") (pintype "passive"))
      (node (ref "U2") (pin "22") (pinfunction "QE10_22") (pintype "passive"))
    )
    (net (code "234") (name "/TFP401_D10_FPGA") (class "Default")
      (node (ref "RN9") (pin "2") (pinfunction "2_2") (pintype "passive"))
      (node (ref "U8") (pin "A8") (pinfunction "IO_L6N_0_A8") (pintype "passive"))
    )
    (net (code "235") (name "/TFP401_D11") (class "Default")
      (node (ref "RN9") (pin "8") (pinfunction "8_8") (pintype "passive"))
      (node (ref "U2") (pin "23") (pinfunction "QE11_23") (pintype "passive"))
    )
    (net (code "236") (name "/TFP401_D11_FPGA") (class "Default")
      (node (ref "RN9") (pin "1") (pinfunction "1_1") (pintype "passive"))
      (node (ref "U8") (pin "B8") (pinfunction "IO_L6P_0_B8") (pintype "passive"))
    )
    (net (code "237") (name "/TFP401_D12") (class "Default")
      (node (ref "RN28") (pin "5") (pinfunction "5_5") (pintype "passive"))
      (node (ref "U2") (pin "24") (pinfunction "QE12_24") (pintype "passive"))
    )
    (net (code "238") (name "/TFP401_D12_FPGA") (class "Default")
      (node (ref "RN28") (pin "4") (pinfunction "4_4") (pintype "passive"))
      (node (ref "U8") (pin "C8") (pinfunction "IO_L7N_0_C8") (pintype "passive"))
    )
    (net (code "239") (name "/TFP401_D13") (class "Default")
      (node (ref "RN28") (pin "6") (pinfunction "6_6") (pintype "passive"))
      (node (ref "U2") (pin "25") (pinfunction "QE13_25") (pintype "passive"))
    )
    (net (code "240") (name "/TFP401_D13_FPGA") (class "Default")
      (node (ref "RN28") (pin "3") (pinfunction "3_3") (pintype "passive"))
      (node (ref "U8") (pin "A9") (pinfunction "IO_L8N_VREF_0_A9") (pintype "passive"))
    )
    (net (code "241") (name "/TFP401_D14") (class "Default")
      (node (ref "RN28") (pin "7") (pinfunction "7_7") (pintype "passive"))
      (node (ref "U2") (pin "26") (pinfunction "QE14_26") (pintype "passive"))
    )
    (net (code "242") (name "/TFP401_D14_FPGA") (class "Default")
      (node (ref "RN28") (pin "2") (pinfunction "2_2") (pintype "passive"))
      (node (ref "U8") (pin "C9") (pinfunction "IO_L8P_0_C9") (pintype "passive"))
    )
    (net (code "243") (name "/TFP401_D15") (class "Default")
      (node (ref "RN28") (pin "8") (pinfunction "8_8") (pintype "passive"))
      (node (ref "U2") (pin "27") (pinfunction "QE15_27") (pintype "passive"))
    )
    (net (code "244") (name "/TFP401_D15_FPGA") (class "Default")
      (node (ref "RN28") (pin "1") (pinfunction "1_1") (pintype "passive"))
      (node (ref "U8") (pin "D9") (pinfunction "IO_L7P_0_D9") (pintype "passive"))
    )
    (net (code "245") (name "/TFP401_D16") (class "Default")
      (node (ref "RN11") (pin "5") (pinfunction "5_5") (pintype "passive"))
      (node (ref "U2") (pin "30") (pinfunction "QE16_30") (pintype "passive"))
    )
    (net (code "246") (name "/TFP401_D16_FPGA") (class "Default")
      (node (ref "RN11") (pin "4") (pinfunction "4_4") (pintype "passive"))
      (node (ref "U8") (pin "C14") (pinfunction "IO_L49N_0_C14") (pintype "passive"))
    )
    (net (code "247") (name "/TFP401_D17") (class "Default")
      (node (ref "RN11") (pin "6") (pinfunction "6_6") (pintype "passive"))
      (node (ref "U2") (pin "31") (pinfunction "QE17_31") (pintype "passive"))
    )
    (net (code "248") (name "/TFP401_D17_FPGA") (class "Default")
      (node (ref "RN11") (pin "3") (pinfunction "3_3") (pintype "passive"))
      (node (ref "U8") (pin "B14") (pinfunction "IO_L50P_0_B14") (pintype "passive"))
    )
    (net (code "249") (name "/TFP401_D18") (class "Default")
      (node (ref "RN11") (pin "7") (pinfunction "7_7") (pintype "passive"))
      (node (ref "U2") (pin "32") (pinfunction "QE18_32") (pintype "passive"))
    )
    (net (code "250") (name "/TFP401_D18_FPGA") (class "Default")
      (node (ref "RN11") (pin "2") (pinfunction "2_2") (pintype "passive"))
      (node (ref "U8") (pin "A14") (pinfunction "IO_L50N_0_A14") (pintype "passive"))
    )
    (net (code "251") (name "/TFP401_D19") (class "Default")
      (node (ref "RN11") (pin "8") (pinfunction "8_8") (pintype "passive"))
      (node (ref "U2") (pin "33") (pinfunction "QE19_33") (pintype "passive"))
    )
    (net (code "252") (name "/TFP401_D19_FPGA") (class "Default")
      (node (ref "RN11") (pin "1") (pinfunction "1_1") (pintype "passive"))
      (node (ref "U8") (pin "D15") (pinfunction "IO_L62P_0_D15") (pintype "passive"))
    )
    (net (code "253") (name "/TFP401_D20") (class "Default")
      (node (ref "RN12") (pin "5") (pinfunction "5_5") (pintype "passive"))
      (node (ref "U2") (pin "34") (pinfunction "QE20_34") (pintype "passive"))
    )
    (net (code "254") (name "/TFP401_D20_FPGA") (class "Default")
      (node (ref "RN12") (pin "4") (pinfunction "4_4") (pintype "passive"))
      (node (ref "U8") (pin "C15") (pinfunction "IO_L51P_0_C15") (pintype "passive"))
    )
    (net (code "255") (name "/TFP401_D21") (class "Default")
      (node (ref "RN12") (pin "6") (pinfunction "6_6") (pintype "passive"))
      (node (ref "U2") (pin "35") (pinfunction "QE21_35") (pintype "passive"))
    )
    (net (code "256") (name "/TFP401_D21_FPGA") (class "Default")
      (node (ref "RN12") (pin "3") (pinfunction "3_3") (pintype "passive"))
      (node (ref "U8") (pin "A15") (pinfunction "IO_L51N_0_A15") (pintype "passive"))
    )
    (net (code "257") (name "/TFP401_D22") (class "Default")
      (node (ref "RN12") (pin "7") (pinfunction "7_7") (pintype "passive"))
      (node (ref "U2") (pin "36") (pinfunction "QE22_36") (pintype "passive"))
    )
    (net (code "258") (name "/TFP401_D22_FPGA") (class "Default")
      (node (ref "RN12") (pin "2") (pinfunction "2_2") (pintype "passive"))
      (node (ref "U8") (pin "E16") (pinfunction "IO_L66P_SCP1_0_E16") (pintype "passive"))
    )
    (net (code "259") (name "/TFP401_D23") (class "Default")
      (node (ref "RN12") (pin "8") (pinfunction "8_8") (pintype "passive"))
      (node (ref "U2") (pin "37") (pinfunction "QE23_37") (pintype "passive"))
    )
    (net (code "260") (name "/TFP401_D23_FPGA") (class "Default")
      (node (ref "RN12") (pin "1") (pinfunction "1_1") (pintype "passive"))
      (node (ref "U8") (pin "C16") (pinfunction "IO_L62N_VREF_0_C16") (pintype "passive"))
    )
    (net (code "261") (name "/TFP401_DE") (class "Default")
      (node (ref "RN21") (pin "5") (pinfunction "5_5") (pintype "passive"))
      (node (ref "U2") (pin "46") (pinfunction "DE_46") (pintype "passive"))
    )
    (net (code "262") (name "/TFP401_DE_FPGA") (class "Default")
      (node (ref "RN21") (pin "4") (pinfunction "4_4") (pintype "passive"))
      (node (ref "U8") (pin "C17") (pinfunction "IO_L64P_SCP5_0_C17") (pintype "passive"))
    )
    (net (code "263") (name "/TFP401_HSYNC") (class "Default")
      (node (ref "RN21") (pin "7") (pinfunction "7_7") (pintype "passive"))
      (node (ref "U2") (pin "48") (pinfunction "HSYNC_48") (pintype "passive"))
    )
    (net (code "264") (name "/TFP401_HSYNC_FPGA") (class "Default")
      (node (ref "RN21") (pin "2") (pinfunction "2_2") (pintype "passive"))
      (node (ref "U8") (pin "A18") (pinfunction "IO_L65N_SCP2_0_A18") (pintype "passive"))
    )
    (net (code "265") (name "/TFP401_ODCK") (class "Default")
      (node (ref "R190") (pin "1") (pinfunction "1_1") (pintype "passive"))
      (node (ref "U2") (pin "44") (pinfunction "ODCK_44") (pintype "passive"))
    )
    (net (code "266") (name "/TFP401_ODCK_FPGA") (class "Default")
      (node (ref "R190") (pin "2") (pinfunction "2_2") (pintype "passive"))
      (node (ref "U8") (pin "B10") (pinfunction "IO_L34P_GCLK19_0_B10") (pintype "passive"))
    )
    (net (code "267") (name "/TFP401_VSYNC") (class "Default")
      (node (ref "RN21") (pin "6") (pinfunction "6_6") (pintype "passive"))
      (node (ref "U2") (pin "47") (pinfunction "VSYNC_47") (pintype "passive"))
    )
    (net (code "268") (name "/TFP401_VSYNC_FPGA") (class "Default")
      (node (ref "RN21") (pin "3") (pinfunction "3_3") (pintype "passive"))
      (node (ref "U8") (pin "B18") (pinfunction "IO_L65P_SCP3_0_B18") (pintype "passive"))
    )
    (net (code "269") (name "/TFP410_CLK") (class "Default")
      (node (ref "R151") (pin "1") (pinfunction "1_1") (pintype "passive"))
      (node (ref "U3") (pin "57") (pinfunction "IDCK+_57") (pintype "passive"))
    )
    (net (code "270") (name "/TFP410_CLK_FPGA") (class "Default")
      (node (ref "R151") (pin "2") (pinfunction "2_2") (pintype "passive"))
      (node (ref "U8") (pin "AB12") (pinfunction "IO_L31N_GCLK30_D15_2_AB12") (pintype "passive"))
    )
    (net (code "271") (name "/TFP410_D0") (class "Default")
      (node (ref "RN25") (pin "8") (pinfunction "8_8") (pintype "passive"))
      (node (ref "U3") (pin "63") (pinfunction "DATA0_63") (pintype "passive"))
    )
    (net (code "272") (name "/TFP410_D0_FPGA") (class "Default")
      (node (ref "RN25") (pin "1") (pinfunction "1_1") (pintype "passive"))
      (node (ref "U8") (pin "W10") (pinfunction "IO_L44P_2_W10") (pintype "passive"))
    )
    (net (code "273") (name "/TFP410_D1") (class "Default")
      (node (ref "RN25") (pin "7") (pinfunction "7_7") (pintype "passive"))
      (node (ref "U3") (pin "62") (pinfunction "DATA1_62") (pintype "passive"))
    )
    (net (code "274") (name "/TFP410_D1_FPGA") (class "Default")
      (node (ref "RN25") (pin "2") (pinfunction "2_2") (pintype "passive"))
      (node (ref "U8") (pin "T11") (pinfunction "IO_L40N_2_T11") (pintype "passive"))
    )
    (net (code "275") (name "/TFP410_D2") (class "Default")
      (node (ref "RN25") (pin "6") (pinfunction "6_6") (pintype "passive"))
      (node (ref "U3") (pin "61") (pinfunction "DATA2_61") (pintype "passive"))
    )
    (net (code "276") (name "/TFP410_D2_FPGA") (class "Default")
      (node (ref "RN25") (pin "3") (pinfunction "3_3") (pintype "passive"))
      (node (ref "U8") (pin "R11") (pinfunction "IO_L40P_2_R11") (pintype "passive"))
    )
    (net (code "277") (name "/TFP410_D3") (class "Default")
      (node (ref "RN25") (pin "5") (pinfunction "5_5") (pintype "passive"))
      (node (ref "U3") (pin "60") (pinfunction "DATA3_60") (pintype "passive"))
    )
    (net (code "278") (name "/TFP410_D3_FPGA") (class "Default")
      (node (ref "RN25") (pin "4") (pinfunction "4_4") (pintype "passive"))
      (node (ref "U8") (pin "T12") (pinfunction "IO_L22P_2_T12") (pintype "passive"))
    )
    (net (code "279") (name "/TFP410_D4") (class "Default")
      (node (ref "RN27") (pin "8") (pinfunction "8_8") (pintype "passive"))
      (node (ref "U3") (pin "59") (pinfunction "DATA4_59") (pintype "passive"))
    )
    (net (code "280") (name "/TFP410_D4_FPGA") (class "Default")
      (node (ref "RN27") (pin "1") (pinfunction "1_1") (pintype "passive"))
      (node (ref "U8") (pin "U12") (pinfunction "IO_L22N_2_U12") (pintype "passive"))
    )
    (net (code "281") (name "/TFP410_D5") (class "Default")
      (node (ref "RN27") (pin "7") (pinfunction "7_7") (pintype "passive"))
      (node (ref "U3") (pin "58") (pinfunction "DATA5_58") (pintype "passive"))
    )
    (net (code "282") (name "/TFP410_D5_FPGA") (class "Default")
      (node (ref "RN27") (pin "2") (pinfunction "2_2") (pintype "passive"))
      (node (ref "U8") (pin "Y12") (pinfunction "IO_L29N_GCLK2_2_Y12") (pintype "passive"))
    )
    (net (code "283") (name "/TFP410_D6") (class "Default")
      (node (ref "RN27") (pin "6") (pinfunction "6_6") (pintype "passive"))
      (node (ref "U3") (pin "55") (pinfunction "DATA6_55") (pintype "passive"))
    )
    (net (code "284") (name "/TFP410_D6_FPGA") (class "Default")
      (node (ref "RN27") (pin "3") (pinfunction "3_3") (pintype "passive"))
      (node (ref "U8") (pin "V13") (pinfunction "IO_L18P_2_V13") (pintype "passive"))
    )
    (net (code "285") (name "/TFP410_D7") (class "Default")
      (node (ref "RN27") (pin "5") (pinfunction "5_5") (pintype "passive"))
      (node (ref "U3") (pin "54") (pinfunction "DATA7_54") (pintype "passive"))
    )
    (net (code "286") (name "/TFP410_D7_FPGA") (class "Default")
      (node (ref "RN27") (pin "4") (pinfunction "4_4") (pintype "passive"))
      (node (ref "U8") (pin "T14") (pinfunction "IO_L23P_2_T14") (pintype "passive"))
    )
    (net (code "287") (name "/TFP410_D8") (class "Default")
      (node (ref "RN23") (pin "8") (pinfunction "8_8") (pintype "passive"))
      (node (ref "U3") (pin "53") (pinfunction "DATA8_53") (pintype "passive"))
    )
    (net (code "288") (name "/TFP410_D8_FPGA") (class "Default")
      (node (ref "RN23") (pin "1") (pinfunction "1_1") (pintype "passive"))
      (node (ref "U8") (pin "W14") (pinfunction "IO_L20P_2_W14") (pintype "passive"))
    )
    (net (code "289") (name "/TFP410_D9") (class "Default")
      (node (ref "RN23") (pin "7") (pinfunction "7_7") (pintype "passive"))
      (node (ref "U3") (pin "52") (pinfunction "DATA9_52") (pintype "passive"))
    )
    (net (code "290") (name "/TFP410_D9_FPGA") (class "Default")
      (node (ref "RN23") (pin "2") (pinfunction "2_2") (pintype "passive"))
      (node (ref "U8") (pin "AB14") (pinfunction "IO_L16N_VREF_2_AB14") (pintype "passive"))
    )
    (net (code "291") (name "/TFP410_D10") (class "Default")
      (node (ref "RN23") (pin "6") (pinfunction "6_6") (pintype "passive"))
      (node (ref "U3") (pin "51") (pinfunction "DATA10_51") (pintype "passive"))
    )
    (net (code "292") (name "/TFP410_D10_FPGA") (class "Default")
      (node (ref "RN23") (pin "3") (pinfunction "3_3") (pintype "passive"))
      (node (ref "U8") (pin "Y14") (pinfunction "IO_L20N_2_Y14") (pintype "passive"))
    )
    (net (code "293") (name "/TFP410_D11") (class "Default")
      (node (ref "RN23") (pin "5") (pinfunction "5_5") (pintype "passive"))
      (node (ref "U3") (pin "50") (pinfunction "DATA11_50") (pintype "passive"))
    )
    (net (code "294") (name "/TFP410_D11_FPGA") (class "Default")
      (node (ref "RN23") (pin "4") (pinfunction "4_4") (pintype "passive"))
      (node (ref "U8") (pin "W15") (pinfunction "IO_L17N_2_W15") (pintype "passive"))
    )
    (net (code "295") (name "/TFP410_D12") (class "Default")
      (node (ref "RN4") (pin "8") (pinfunction "8_8") (pintype "passive"))
      (node (ref "U3") (pin "47") (pinfunction "DATA12_47") (pintype "passive"))
    )
    (net (code "296") (name "/TFP410_D12_FPGA") (class "Default")
      (node (ref "RN4") (pin "1") (pinfunction "1_1") (pintype "passive"))
      (node (ref "U8") (pin "AB15") (pinfunction "IO_L21N_2_AB15") (pintype "passive"))
    )
    (net (code "297") (name "/TFP410_D13") (class "Default")
      (node (ref "RN4") (pin "7") (pinfunction "7_7") (pintype "passive"))
      (node (ref "U3") (pin "46") (pinfunction "DATA13_46") (pintype "passive"))
    )
    (net (code "298") (name "/TFP410_D13_FPGA") (class "Default")
      (node (ref "RN4") (pin "2") (pinfunction "2_2") (pintype "passive"))
      (node (ref "U8") (pin "T16") (pinfunction "IO_L7P_2_T16") (pintype "passive"))
    )
    (net (code "299") (name "/TFP410_D14") (class "Default")
      (node (ref "RN4") (pin "6") (pinfunction "6_6") (pintype "passive"))
      (node (ref "U3") (pin "45") (pinfunction "DATA14_45") (pintype "passive"))
    )
    (net (code "300") (name "/TFP410_D14_FPGA") (class "Default")
      (node (ref "RN4") (pin "3") (pinfunction "3_3") (pintype "passive"))
      (node (ref "U8") (pin "Y16") (pinfunction "IO_L17P_2_Y16") (pintype "passive"))
    )
    (net (code "301") (name "/TFP410_D15") (class "Default")
      (node (ref "RN4") (pin "5") (pinfunction "5_5") (pintype "passive"))
      (node (ref "U3") (pin "44") (pinfunction "DATA15_44") (pintype "passive"))
    )
    (net (code "302") (name "/TFP410_D15_FPGA") (class "Default")
      (node (ref "RN4") (pin "4") (pinfunction "4_4") (pintype "passive"))
      (node (ref "U8") (pin "AB16") (pinfunction "IO_L19N_2_AB16") (pintype "passive"))
    )
    (net (code "303") (name "/TFP410_D16") (class "Default")
      (node (ref "RN5") (pin "8") (pinfunction "8_8") (pintype "passive"))
      (node (ref "U3") (pin "43") (pinfunction "DATA16_43") (pintype "passive"))
    )
    (net (code "304") (name "/TFP410_D16_FPGA") (class "Default")
      (node (ref "RN5") (pin "1") (pinfunction "1_1") (pintype "passive"))
      (node (ref "U8") (pin "AA16") (pinfunction "IO_L19P_2_AA16") (pintype "passive"))
    )
    (net (code "305") (name "/TFP410_D17") (class "Default")
      (node (ref "RN5") (pin "7") (pinfunction "7_7") (pintype "passive"))
      (node (ref "U3") (pin "42") (pinfunction "DATA17_42") (pintype "passive"))
    )
    (net (code "306") (name "/TFP410_D17_FPGA") (class "Default")
      (node (ref "RN5") (pin "2") (pinfunction "2_2") (pintype "passive"))
      (node (ref "U8") (pin "Y17") (pinfunction "IO_L15P_2_Y17") (pintype "passive"))
    )
    (net (code "307") (name "/TFP410_D18") (class "Default")
      (node (ref "RN5") (pin "6") (pinfunction "6_6") (pintype "passive"))
      (node (ref "U3") (pin "41") (pinfunction "DATA18_41") (pintype "passive"))
    )
    (net (code "308") (name "/TFP410_D18_FPGA") (class "Default")
      (node (ref "RN5") (pin "3") (pinfunction "3_3") (pintype "passive"))
      (node (ref "U8") (pin "AB17") (pinfunction "IO_L15N_2_AB17") (pintype "passive"))
    )
    (net (code "309") (name "/TFP410_D19") (class "Default")
      (node (ref "RN5") (pin "5") (pinfunction "5_5") (pintype "passive"))
      (node (ref "U3") (pin "40") (pinfunction "DATA19_40") (pintype "passive"))
    )
    (net (code "310") (name "/TFP410_D19_FPGA") (class "Default")
      (node (ref "RN5") (pin "4") (pinfunction "4_4") (pintype "passive"))
      (node (ref "U8") (pin "V18") (pinfunction "IO_L9N_2_V18") (pintype "passive"))
    )
    (net (code "311") (name "/TFP410_D20") (class "Default")
      (node (ref "RN6") (pin "8") (pinfunction "8_8") (pintype "passive"))
      (node (ref "U3") (pin "39") (pinfunction "DATA20_39") (pintype "passive"))
    )
    (net (code "312") (name "/TFP410_D20_FPGA") (class "Default")
      (node (ref "RN6") (pin "1") (pinfunction "1_1") (pintype "passive"))
      (node (ref "U8") (pin "W18") (pinfunction "IO_L6P_2_W18") (pintype "passive"))
    )
    (net (code "313") (name "/TFP410_D21") (class "Default")
      (node (ref "RN6") (pin "7") (pinfunction "7_7") (pintype "passive"))
      (node (ref "U3") (pin "38") (pinfunction "DATA21_38") (pintype "passive"))
    )
    (net (code "314") (name "/TFP410_D21_FPGA") (class "Default")
      (node (ref "RN6") (pin "2") (pinfunction "2_2") (pintype "passive"))
      (node (ref "U8") (pin "AB18") (pinfunction "IO_L14N_D12_2_AB18") (pintype "passive"))
    )
    (net (code "315") (name "/TFP410_D22") (class "Default")
      (node (ref "RN6") (pin "6") (pinfunction "6_6") (pintype "passive"))
      (node (ref "U3") (pin "37") (pinfunction "DATA22_37") (pintype "passive"))
    )
    (net (code "316") (name "/TFP410_D22_FPGA") (class "Default")
      (node (ref "RN6") (pin "3") (pinfunction "3_3") (pintype "passive"))
      (node (ref "U8") (pin "AA18") (pinfunction "IO_L14P_D11_2_AA18") (pintype "passive"))
    )
    (net (code "317") (name "/TFP410_D23") (class "Default")
      (node (ref "RN6") (pin "5") (pinfunction "5_5") (pintype "passive"))
      (node (ref "U3") (pin "36") (pinfunction "DATA23_36") (pintype "passive"))
    )
    (net (code "318") (name "/TFP410_D23_FPGA") (class "Default")
      (node (ref "RN6") (pin "4") (pinfunction "4_4") (pintype "passive"))
      (node (ref "U8") (pin "AB19") (pinfunction "IO_L5N_2_AB19") (pintype "passive"))
    )
    (net (code "319") (name "/TMS") (class "Default")
      (node (ref "CN2") (pin "5") (pinfunction "5_5") (pintype "passive"))
      (node (ref "R19") (pin "1") (pinfunction "1_1") (pintype "passive"))
    )
    (net (code "320") (name "/TXD") (class "Default")
      (node (ref "R159") (pin "1") (pinfunction "1_1") (pintype "passive"))
    )
    (net (code "321") (name "/UP_A0") (class "Default")
      (node (ref "R37") (pin "1") (pinfunction "1_1") (pintype "passive"))
      (node (ref "U5") (pin "N3") (pinfunction "A0_N3") (pintype "passive"))
      (node (ref "U8") (pin "H2") (pinfunction "IO_L47P_M3A0_3_H2") (pintype "passive"))
    )
    (net (code "322") (name "/UP_A1") (class "Default")
      (node (ref "R42") (pin "1") (pinfunction "1_1") (pintype "passive"))
      (node (ref "U5") (pin "P7") (pinfunction "A1_P7") (pintype "passive"))
      (node (ref "U8") (pin "H1") (pinfunction "IO_L47N_M3A1_3_H1") (pintype "passive"))
    )
    (net (code "323") (name "/UP_A2") (class "Default")
      (node (ref "R41") (pin "1") (pinfunction "1_1") (pintype "passive"))
      (node (ref "U5") (pin "P3") (pinfunction "A2_P3") (pintype "passive"))
      (node (ref "U8") (pin "H5") (pinfunction "IO_L49N_M3A2_3_H5") (pintype "passive"))
    )
    (net (code "324") (name "/UP_A3") (class "Default")
      (node (ref "R36") (pin "1") (pinfunction "1_1") (pintype "passive"))
      (node (ref "U5") (pin "N2") (pinfunction "A3_N2") (pintype "passive"))
      (node (ref "U8") (pin "K6") (pinfunction "IO_L45P_M3A3_3_K6") (pintype "passive"))
    )
    (net (code "325") (name "/UP_A4") (class "Default")
      (node (ref "R43") (pin "1") (pinfunction "1_1") (pintype "passive"))
      (node (ref "U5") (pin "P8") (pinfunction "A4_P8") (pintype "passive"))
      (node (ref "U8") (pin "F3") (pinfunction "IO_L51N_M3A4_3_F3") (pintype "passive"))
    )
    (net (code "326") (name "/UP_A5") (class "Default")
      (node (ref "R40") (pin "1") (pinfunction "1_1") (pintype "passive"))
      (node (ref "U5") (pin "P2") (pinfunction "A5_P2") (pintype "passive"))
      (node (ref "U8") (pin "K3") (pinfunction "IO_L44P_GCLK21_M3A5_3_K3") (pintype "passive"))
    )
    (net (code "327") (name "/UP_A6") (class "Default")
      (node (ref "R47") (pin "1") (pinfunction "1_1") (pintype "passive"))
      (node (ref "U5") (pin "R8") (pinfunction "A6_R8") (pintype "passive"))
      (node (ref "U8") (pin "J4") (pinfunction "IO_L44N_GCLK20_M3A6_3_J4") (pintype "passive"))
    )
    (net (code "328") (name "/UP_A7") (class "Default")
      (node (ref "R44") (pin "1") (pinfunction "1_1") (pintype "passive"))
      (node (ref "U5") (pin "R2") (pinfunction "A7_R2") (pintype "passive"))
      (node (ref "U8") (pin "H6") (pinfunction "IO_L49P_M3A7_3_H6") (pintype "passive"))
    )
    (net (code "329") (name "/UP_A8") (class "Default")
      (node (ref "R50") (pin "1") (pinfunction "1_1") (pintype "passive"))
      (node (ref "U5") (pin "T8") (pinfunction "A8_T8") (pintype "passive"))
      (node (ref "U8") (pin "E3") (pinfunction "IO_L52P_M3A8_3_E3") (pintype "passive"))
    )
    (net (code "330") (name "/UP_A9") (class "Default")
      (node (ref "R45") (pin "1") (pinfunction "1_1") (pintype "passive"))
      (node (ref "U5") (pin "R3") (pinfunction "A9_R3") (pintype "passive"))
      (node (ref "U8") (pin "E1") (pinfunction "IO_L52N_M3A9_3_E1") (pintype "passive"))
    )
    (net (code "331") (name "/UP_A10") (class "Default")
      (node (ref "R33") (pin "1") (pinfunction "1_1") (pintype "passive"))
      (node (ref "U5") (pin "L7") (pinfunction "A10/AP_L7") (pintype "passive"))
      (node (ref "U8") (pin "G4") (pinfunction "IO_L51P_M3A10_3_G4") (pintype "passive"))
    )
    (net (code "332") (name "/UP_A11") (class "Default")
      (node (ref "R46") (pin "1") (pinfunction "1_1") (pintype "passive"))
      (node (ref "U5") (pin "R7") (pinfunction "A11_R7") (pintype "passive"))
      (node (ref "U8") (pin "C1") (pinfunction "IO_L54N_M3A11_3_C1") (pintype "passive"))
    )
    (net (code "333") (name "/UP_A12") (class "Default")
      (node (ref "R38") (pin "1") (pinfunction "1_1") (pintype "passive"))
      (node (ref "U5") (pin "N7") (pinfunction "A12/BC#_N7") (pintype "passive"))
      (node (ref "U8") (pin "D1") (pinfunction "IO_L53N_M3A12_3_D1") (pintype "passive"))
    )
    (net (code "334") (name "/UP_A13") (class "Default")
      (node (ref "R48") (pin "1") (pinfunction "1_1") (pintype "passive"))
      (node (ref "U5") (pin "T3") (pinfunction "A13_T3") (pintype "passive"))
      (node (ref "U8") (pin "G6") (pinfunction "IO_L55P_M3A13_3_G6") (pintype "passive"))
    )
    (net (code "335") (name "/UP_A14") (class "Default")
      (node (ref "R49") (pin "1") (pinfunction "1_1") (pintype "passive"))
      (node (ref "U5") (pin "T7") (pinfunction "A14_T7") (pintype "passive"))
      (node (ref "U8") (pin "F5") (pinfunction "IO_L55N_M3A14_3_F5") (pintype "passive"))
    )
    (net (code "336") (name "/UP_BA0") (class "Default")
      (node (ref "R34") (pin "1") (pinfunction "1_1") (pintype "passive"))
      (node (ref "U5") (pin "M2") (pinfunction "BA0_M2") (pintype "passive"))
      (node (ref "U8") (pin "G3") (pinfunction "IO_L48P_M3BA0_3_G3") (pintype "passive"))
    )
    (net (code "337") (name "/UP_BA1") (class "Default")
      (node (ref "R39") (pin "1") (pinfunction "1_1") (pintype "passive"))
      (node (ref "U5") (pin "N8") (pinfunction "BA1_N8") (pintype "passive"))
      (node (ref "U8") (pin "G1") (pinfunction "IO_L48N_M3BA1_3_G1") (pintype "passive"))
    )
    (net (code "338") (name "/UP_BA2") (class "Default")
      (node (ref "R35") (pin "1") (pinfunction "1_1") (pintype "passive"))
      (node (ref "U5") (pin "M3") (pinfunction "BA2_M3") (pintype "passive"))
      (node (ref "U8") (pin "F1") (pinfunction "IO_L50N_M3BA2_3_F1") (pintype "passive"))
    )
    (net (code "339") (name "/UP_CAS") (class "Default")
      (node (ref "R30") (pin "1") (pinfunction "1_1") (pintype "passive"))
      (node (ref "U5") (pin "K3") (pinfunction "CAS#_K3") (pintype "passive"))
      (node (ref "U8") (pin "K4") (pinfunction "IO_L43N_GCLK22_IRDY2_M3CASN_3_K4") (pintype "passive"))
    )
    (net (code "340") (name "/UP_CK+") (class "Default")
      (node (ref "R156") (pin "1") (pinfunction "1_1") (pintype "passive"))
      (node (ref "U5") (pin "J7") (pinfunction "CK_J7") (pintype "passive"))
      (node (ref "U8") (pin "H4") (pinfunction "IO_L46P_M3CLK_3_H4") (pintype "passive"))
    )
    (net (code "341") (name "/UP_CK-") (class "Default")
      (node (ref "R156") (pin "2") (pinfunction "2_2") (pintype "passive"))
      (node (ref "U5") (pin "K7") (pinfunction "CK#_K7") (pintype "passive"))
      (node (ref "U8") (pin "H3") (pinfunction "IO_L46N_M3CLKN_3_H3") (pintype "passive"))
    )
    (net (code "342") (name "/UP_CKE") (class "Default")
      (node (ref "R1") (pin "1") (pinfunction "1_1") (pintype "passive"))
      (node (ref "U5") (pin "K9") (pinfunction "CKE_K9") (pintype "passive"))
      (node (ref "U8") (pin "D2") (pinfunction "IO_L53P_M3CKE_3_D2") (pintype "passive"))
    )
    (net (code "343") (name "/UP_D0") (class "Default")
      (node (ref "U5") (pin "E3") (pinfunction "DQ0_E3") (pintype "passive"))
      (node (ref "U8") (pin "N3") (pinfunction "IO_L37P_M3DQ0_3_N3") (pintype "passive"))
    )
    (net (code "344") (name "/UP_D1") (class "Default")
      (node (ref "U5") (pin "F7") (pinfunction "DQ1_F7") (pintype "passive"))
      (node (ref "U8") (pin "N1") (pinfunction "IO_L37N_M3DQ1_3_N1") (pintype "passive"))
    )
    (net (code "345") (name "/UP_D2") (class "Default")
      (node (ref "U5") (pin "F2") (pinfunction "DQ2_F2") (pintype "passive"))
      (node (ref "U8") (pin "M2") (pinfunction "IO_L38P_M3DQ2_3_M2") (pintype "passive"))
    )
    (net (code "346") (name "/UP_D3") (class "Default")
      (node (ref "U5") (pin "F8") (pinfunction "DQ3_F8") (pintype "passive"))
      (node (ref "U8") (pin "M1") (pinfunction "IO_L38N_M3DQ3_3_M1") (pintype "passive"))
    )
    (net (code "347") (name "/UP_D4") (class "Default")
      (node (ref "U5") (pin "H3") (pinfunction "DQ4_H3") (pintype "passive"))
      (node (ref "U8") (pin "J3") (pinfunction "IO_L41P_GCLK27_M3DQ4_3_J3") (pintype "passive"))
    )
    (net (code "348") (name "/UP_D5") (class "Default")
      (node (ref "U5") (pin "H8") (pinfunction "DQ5_H8") (pintype "passive"))
      (node (ref "U8") (pin "J1") (pinfunction "IO_L41N_GCLK26_M3DQ5_3_J1") (pintype "passive"))
    )
    (net (code "349") (name "/UP_D6") (class "Default")
      (node (ref "U5") (pin "G2") (pinfunction "DQ6_G2") (pintype "passive"))
      (node (ref "U8") (pin "K2") (pinfunction "IO_L40P_M3DQ6_3_K2") (pintype "passive"))
    )
    (net (code "350") (name "/UP_D7") (class "Default")
      (node (ref "U5") (pin "H7") (pinfunction "DQ7_H7") (pintype "passive"))
      (node (ref "U8") (pin "K1") (pinfunction "IO_L40N_M3DQ7_3_K1") (pintype "passive"))
    )
    (net (code "351") (name "/UP_D8") (class "Default")
      (node (ref "U5") (pin "D7") (pinfunction "DQ8_D7") (pintype "passive"))
      (node (ref "U8") (pin "P2") (pinfunction "IO_L36P_M3DQ8_3_P2") (pintype "passive"))
    )
    (net (code "352") (name "/UP_D9") (class "Default")
      (node (ref "U5") (pin "C3") (pinfunction "DQ9_C3") (pintype "passive"))
      (node (ref "U8") (pin "P1") (pinfunction "IO_L36N_M3DQ9_3_P1") (pintype "passive"))
    )
    (net (code "353") (name "/UP_D10") (class "Default")
      (node (ref "U5") (pin "C8") (pinfunction "DQ10_C8") (pintype "passive"))
      (node (ref "U8") (pin "R3") (pinfunction "IO_L35P_M3DQ10_3_R3") (pintype "passive"))
    )
    (net (code "354") (name "/UP_D11") (class "Default")
      (node (ref "U5") (pin "C2") (pinfunction "DQ11_C2") (pintype "passive"))
      (node (ref "U8") (pin "R1") (pinfunction "IO_L35N_M3DQ11_3_R1") (pintype "passive"))
    )
    (net (code "355") (name "/UP_D12") (class "Default")
      (node (ref "U5") (pin "A7") (pinfunction "DQ12_A7") (pintype "passive"))
      (node (ref "U8") (pin "U3") (pinfunction "IO_L33P_M3DQ12_3_U3") (pintype "passive"))
    )
    (net (code "356") (name "/UP_D13") (class "Default")
      (node (ref "U5") (pin "A2") (pinfunction "DQ13_A2") (pintype "passive"))
      (node (ref "U8") (pin "U1") (pinfunction "IO_L33N_M3DQ13_3_U1") (pintype "passive"))
    )
    (net (code "357") (name "/UP_D14") (class "Default")
      (node (ref "U5") (pin "B8") (pinfunction "DQ14_B8") (pintype "passive"))
      (node (ref "U8") (pin "V2") (pinfunction "IO_L32P_M3DQ14_3_V2") (pintype "passive"))
    )
    (net (code "358") (name "/UP_D15") (class "Default")
      (node (ref "U5") (pin "A3") (pinfunction "DQ15_A3") (pintype "passive"))
      (node (ref "U8") (pin "V1") (pinfunction "IO_L32N_M3DQ15_3_V1") (pintype "passive"))
    )
    (net (code "359") (name "/UP_LDM") (class "Default")
      (node (ref "R188") (pin "1") (pinfunction "1_1") (pintype "passive"))
      (node (ref "U5") (pin "E7") (pinfunction "LDM_E7") (pintype "passive"))
    )
    (net (code "360") (name "/UP_LDQS+") (class "Default")
      (node (ref "U5") (pin "F3") (pinfunction "LDQS_F3") (pintype "passive"))
      (node (ref "U8") (pin "L3") (pinfunction "IO_L39P_M3LDQS_3_L3") (pintype "passive"))
    )
    (net (code "361") (name "/UP_LDQS-") (class "Default")
      (node (ref "U5") (pin "G3") (pinfunction "LDQS#_G3") (pintype "passive"))
      (node (ref "U8") (pin "L1") (pinfunction "IO_L39N_M3LDQSN_3_L1") (pintype "passive"))
    )
    (net (code "362") (name "/UP_ODT") (class "Default")
      (node (ref "R29") (pin "1") (pinfunction "1_1") (pintype "passive"))
      (node (ref "U5") (pin "K1") (pinfunction "ODT_K1") (pintype "passive"))
      (node (ref "U8") (pin "J6") (pinfunction "IO_L45N_M3ODT_3_J6") (pintype "passive"))
    )
    (net (code "363") (name "/UP_RAS") (class "Default")
      (node (ref "R27") (pin "1") (pinfunction "1_1") (pintype "passive"))
      (node (ref "U5") (pin "J3") (pinfunction "RAS#_J3") (pintype "passive"))
      (node (ref "U8") (pin "K5") (pinfunction "IO_L43P_GCLK23_M3RASN_3_K5") (pintype "passive"))
    )
    (net (code "364") (name "/UP_RST") (class "Default")
      (node (ref "R2") (pin "1") (pinfunction "1_1") (pintype "passive"))
      (node (ref "U5") (pin "T2") (pinfunction "RESET#_T2") (pintype "passive"))
      (node (ref "U8") (pin "C3") (pinfunction "IO_L54P_M3RESET_3_C3") (pintype "passive"))
    )
    (net (code "365") (name "/UP_UDM") (class "Default")
      (node (ref "R189") (pin "1") (pinfunction "1_1") (pintype "passive"))
      (node (ref "U5") (pin "D3") (pinfunction "UDM_D3") (pintype "passive"))
    )
    (net (code "366") (name "/UP_UDQS+") (class "Default")
      (node (ref "U5") (pin "C7") (pinfunction "UDQS_C7") (pintype "passive"))
      (node (ref "U8") (pin "T2") (pinfunction "IO_L34P_M3UDQS_3_T2") (pintype "passive"))
    )
    (net (code "367") (name "/UP_UDQS-") (class "Default")
      (node (ref "U5") (pin "B7") (pinfunction "UDQS#_B7") (pintype "passive"))
      (node (ref "U8") (pin "T1") (pinfunction "IO_L34N_M3UDQSN_3_T1") (pintype "passive"))
    )
    (net (code "368") (name "/UP_WE") (class "Default")
      (node (ref "R32") (pin "1") (pinfunction "1_1") (pintype "passive"))
      (node (ref "U5") (pin "L3") (pinfunction "WE#_L3") (pintype "passive"))
      (node (ref "U8") (pin "F2") (pinfunction "IO_L50P_M3WE_3_F2") (pintype "passive"))
    )
    (net (code "369") (name "/USER_KEY") (class "Default")
      (node (ref "R150") (pin "1") (pinfunction "1_1") (pintype "passive"))
      (node (ref "SW3") (pin "1") (pinfunction "1_1") (pintype "passive"))
      (node (ref "U8") (pin "V11") (pinfunction "IO_L42P_2_V11") (pintype "passive"))
    )
    (net (code "370") (name "/USER_KEY1") (class "Default")
      (node (ref "R168") (pin "1") (pinfunction "1_1") (pintype "passive"))
      (node (ref "SW4") (pin "1") (pinfunction "1_1") (pintype "passive"))
      (node (ref "U8") (pin "U10") (pinfunction "IO_L52N_2_U10") (pintype "passive"))
    )
    (net (code "371") (name "/USER_KEY2") (class "Default")
      (node (ref "R169") (pin "1") (pinfunction "1_1") (pintype "passive"))
      (node (ref "SW5") (pin "1") (pinfunction "1_1") (pintype "passive"))
      (node (ref "U8") (pin "T15") (pinfunction "IO_L7N_2_T15") (pintype "passive"))
    )
    (net (code "372") (name "/USER_LED") (class "Default")
      (node (ref "Q16") (pin "1") (pinfunction "G_1") (pintype "passive"))
      (node (ref "R149") (pin "2") (pinfunction "2_2") (pintype "passive"))
      (node (ref "U8") (pin "R13") (pinfunction "IO_L23N_2_R13") (pintype "passive"))
    )
    (net (code "373") (name "/VGAC_B") (class "Default")
      (node (ref "C115") (pin "2") (pinfunction "2_2") (pintype "passive"))
      (node (ref "DSUB1") (pin "3") (pinfunction "3_3") (pintype "passive"))
      (node (ref "U17") (pin "2") (pinfunction "2_2") (pintype "passive"))
    )
    (net (code "374") (name "/VGAC_G") (class "Default")
      (node (ref "C116") (pin "2") (pinfunction "2_2") (pintype "passive"))
      (node (ref "DSUB1") (pin "2") (pinfunction "2_2") (pintype "passive"))
      (node (ref "U16") (pin "2") (pinfunction "2_2") (pintype "passive"))
    )
    (net (code "375") (name "/VGAC_R") (class "Default")
      (node (ref "C117") (pin "2") (pinfunction "2_2") (pintype "passive"))
      (node (ref "DSUB1") (pin "1") (pinfunction "1_1") (pintype "passive"))
      (node (ref "U15") (pin "2") (pinfunction "2_2") (pintype "passive"))
    )
    (net (code "376") (name "/VGA_5V") (class "Default")
      (node (ref "C118") (pin "2") (pinfunction "2_2") (pintype "passive"))
      (node (ref "DSUB1") (pin "9") (pinfunction "9_9") (pintype "passive"))
      (node (ref "U18") (pin "2") (pinfunction "2_2") (pintype "passive"))
    )
    (net (code "377") (name "/VGA_B") (class "Default")
      (node (ref "C114") (pin "2") (pinfunction "2_2") (pintype "passive"))
      (node (ref "R84") (pin "2") (pinfunction "2_2") (pintype "passive"))
      (node (ref "U17") (pin "1") (pinfunction "1_1") (pintype "passive"))
      (node (ref "U4") (pin "28") (pinfunction "IOB_28") (pintype "passive"))
    )
    (net (code "378") (name "/VGA_G") (class "Default")
      (node (ref "C113") (pin "2") (pinfunction "2_2") (pintype "passive"))
      (node (ref "R85") (pin "2") (pinfunction "2_2") (pintype "passive"))
      (node (ref "U16") (pin "1") (pinfunction "1_1") (pintype "passive"))
      (node (ref "U4") (pin "32") (pinfunction "IOG_32") (pintype "passive"))
    )
    (net (code "379") (name "/VGA_R") (class "Default")
      (node (ref "C112") (pin "2") (pinfunction "2_2") (pintype "passive"))
      (node (ref "R86") (pin "2") (pinfunction "2_2") (pintype "passive"))
      (node (ref "U15") (pin "1") (pinfunction "1_1") (pintype "passive"))
      (node (ref "U4") (pin "34") (pinfunction "IOR_34") (pintype "passive"))
    )
    (net (code "380") (name "/VGA_SCL") (class "Default")
      (node (ref "D6") (pin "1") (pinfunction "1_1") (pintype "passive"))
      (node (ref "DSUB1") (pin "15") (pinfunction "15_15") (pintype "passive"))
      (node (ref "Q2") (pin "3") (pinfunction "D_3") (pintype "passive"))
      (node (ref "R91") (pin "1") (pinfunction "1_1") (pintype "passive"))
    )
    (net (code "381") (name "/VGA_SDA") (class "Default")
      (node (ref "D6") (pin "6") (pinfunction "6_6") (pintype "passive"))
      (node (ref "DSUB1") (pin "12") (pinfunction "12_12") (pintype "passive"))
      (node (ref "Q1") (pin "3") (pinfunction "D_3") (pintype "passive"))
      (node (ref "R90") (pin "2") (pinfunction "2_2") (pintype "passive"))
    )
    (net (code "382") (name "/VSYC") (class "Default")
      (node (ref "D6") (pin "3") (pinfunction "3_3") (pintype "passive"))
      (node (ref "DSUB1") (pin "14") (pinfunction "14_14") (pintype "passive"))
      (node (ref "Q4") (pin "3") (pinfunction "D_3") (pintype "passive"))
      (node (ref "R95") (pin "1") (pinfunction "1_1") (pintype "passive"))
    )
    (net (code "383") (name "401_AVDD") (class "Default")
      (node (ref "C173") (pin "1") (pinfunction "1_1") (pintype "passive"))
      (node (ref "C176") (pin "2") (pinfunction "2_2") (pintype "passive"))
      (node (ref "C181") (pin "1") (pinfunction "1_1") (pintype "passive"))
      (node (ref "C188") (pin "2") (pinfunction "2_2") (pintype "passive"))
      (node (ref "C189") (pin "2") (pinfunction "2_2") (pintype "passive"))
      (node (ref "C190") (pin "2") (pinfunction "2_2") (pintype "passive"))
      (node (ref "L8") (pin "2") (pinfunction "2_2") (pintype "passive"))
      (node (ref "U2") (pin "82") (pinfunction "AVDD_82") (pintype "passive"))
      (node (ref "U2") (pin "84") (pinfunction "AVDD_84") (pintype "passive"))
      (node (ref "U2") (pin "88") (pinfunction "AVDD_88") (pintype "passive"))
      (node (ref "U2") (pin "95") (pinfunction "AVDD_95") (pintype "passive"))
    )
    (net (code "384") (name "401_DVDD") (class "Default")
      (node (ref "C157") (pin "1") (pinfunction "1_1") (pintype "passive"))
      (node (ref "C158") (pin "1") (pinfunction "1_1") (pintype "passive"))
      (node (ref "C166") (pin "2") (pinfunction "2_2") (pintype "passive"))
      (node (ref "C178") (pin "1") (pinfunction "1_1") (pintype "passive"))
      (node (ref "L5") (pin "2") (pinfunction "2_2") (pintype "passive"))
      (node (ref "Q11") (pin "1") (pinfunction "G_1") (pintype "passive"))
      (node (ref "Q12") (pin "1") (pinfunction "G_1") (pintype "passive"))
      (node (ref "R108") (pin "2") (pinfunction "2_2") (pintype "passive"))
      (node (ref "R109") (pin "2") (pinfunction "2_2") (pintype "passive"))
      (node (ref "RN3") (pin "1") (pinfunction "1_1") (pintype "passive"))
      (node (ref "RN3") (pin "2") (pinfunction "2_2") (pintype "passive"))
      (node (ref "RN3") (pin "3") (pinfunction "3_3") (pintype "passive"))
      (node (ref "RN3") (pin "4") (pinfunction "4_4") (pintype "passive"))
      (node (ref "U2") (pin "38") (pinfunction "DVDD_38") (pintype "passive"))
      (node (ref "U2") (pin "6") (pinfunction "DVDD_6") (pintype "passive"))
      (node (ref "U2") (pin "67") (pinfunction "DVDD_67") (pintype "passive"))
      (node (ref "U2") (pin "99") (pinfunction "RSVD_99") (pintype "passive"))
    )
    (net (code "385") (name "401_OVDD") (class "Default")
      (node (ref "C159") (pin "1") (pinfunction "1_1") (pintype "passive"))
      (node (ref "C167") (pin "2") (pinfunction "2_2") (pintype "passive"))
      (node (ref "C169") (pin "2") (pinfunction "2_2") (pintype "passive"))
      (node (ref "C179") (pin "1") (pinfunction "1_1") (pintype "passive"))
      (node (ref "C185") (pin "2") (pinfunction "2_2") (pintype "passive"))
      (node (ref "C186") (pin "2") (pinfunction "2_2") (pintype "passive"))
      (node (ref "C187") (pin "2") (pinfunction "2_2") (pintype "passive"))
      (node (ref "L6") (pin "2") (pinfunction "2_2") (pintype "passive"))
      (node (ref "U2") (pin "18") (pinfunction "OVDD_18") (pintype "passive"))
      (node (ref "U2") (pin "29") (pinfunction "OVDD_29") (pintype "passive"))
      (node (ref "U2") (pin "43") (pinfunction "OVDD_43") (pintype "passive"))
      (node (ref "U2") (pin "57") (pinfunction "OVDD_57") (pintype "passive"))
      (node (ref "U2") (pin "78") (pinfunction "OVDD_78") (pintype "passive"))
    )
    (net (code "386") (name "401_PVDD") (class "Default")
      (node (ref "C162") (pin "1") (pinfunction "1_1") (pintype "passive"))
      (node (ref "C171") (pin "2") (pinfunction "2_2") (pintype "passive"))
      (node (ref "C180") (pin "1") (pinfunction "1_1") (pintype "passive"))
      (node (ref "L7") (pin "2") (pinfunction "2_2") (pintype "passive"))
      (node (ref "U2") (pin "97") (pinfunction "PVDD_97") (pintype "passive"))
    )
    (net (code "387") (name "401_PWR") (class "Default")
      (node (ref "C214") (pin "2") (pinfunction "2_2") (pintype "passive"))
      (node (ref "L31") (pin "2") (pinfunction "2_2") (pintype "passive"))
      (node (ref "L5") (pin "1") (pinfunction "1_1") (pintype "passive"))
      (node (ref "L6") (pin "1") (pinfunction "1_1") (pintype "passive"))
      (node (ref "L7") (pin "1") (pinfunction "1_1") (pintype "passive"))
      (node (ref "L8") (pin "1") (pinfunction "1_1") (pintype "passive"))
    )
    (net (code "388") (name "410_DVDD") (class "Default")
      (node (ref "C129") (pin "1") (pinfunction "1_1") (pintype "passive"))
      (node (ref "C141") (pin "2") (pinfunction "2_2") (pintype "passive"))
      (node (ref "C143") (pin "2") (pinfunction "2_2") (pintype "passive"))
      (node (ref "C182") (pin "1") (pinfunction "1_1") (pintype "passive"))
      (node (ref "C191") (pin "2") (pinfunction "2_2") (pintype "passive"))
      (node (ref "L2") (pin "2") (pinfunction "2_2") (pintype "passive"))
      (node (ref "Q7") (pin "1") (pinfunction "G_1") (pintype "passive"))
      (node (ref "Q8") (pin "1") (pinfunction "G_1") (pintype "passive"))
      (node (ref "R102") (pin "2") (pinfunction "2_2") (pintype "passive"))
      (node (ref "R104") (pin "2") (pinfunction "2_2") (pintype "passive"))
      (node (ref "R105") (pin "2") (pinfunction "2_2") (pintype "passive"))
      (node (ref "RN2") (pin "1") (pinfunction "1_1") (pintype "passive"))
      (node (ref "RN2") (pin "2") (pinfunction "2_2") (pintype "passive"))
      (node (ref "RN2") (pin "3") (pinfunction "3_3") (pintype "passive"))
      (node (ref "RN2") (pin "4") (pinfunction "4_4") (pintype "passive"))
      (node (ref "U101") (pin "2") (pinfunction "2_2") (pintype "passive"))
      (node (ref "U121") (pin "2") (pinfunction "2_2") (pintype "passive"))
      (node (ref "U21") (pin "1") (pinfunction "1_1") (pintype "passive"))
      (node (ref "U3") (pin "1") (pinfunction "DVDD_1") (pintype "passive"))
      (node (ref "U3") (pin "10") (pinfunction "PD#_10") (pintype "passive"))
      (node (ref "U3") (pin "12") (pinfunction "DVDD_12") (pintype "passive"))
      (node (ref "U3") (pin "33") (pinfunction "DVDD_33") (pintype "passive"))
    )
    (net (code "389") (name "410_PVDD") (class "Default")
      (node (ref "C128") (pin "2") (pinfunction "2_2") (pintype "passive"))
      (node (ref "C135") (pin "1") (pinfunction "1_1") (pintype "passive"))
      (node (ref "C136") (pin "1") (pinfunction "1_1") (pintype "passive"))
      (node (ref "C145") (pin "2") (pinfunction "2_2") (pintype "passive"))
      (node (ref "C146") (pin "2") (pinfunction "2_2") (pintype "passive"))
      (node (ref "C184") (pin "1") (pinfunction "1_1") (pintype "passive"))
      (node (ref "L4") (pin "2") (pinfunction "2_2") (pintype "passive"))
      (node (ref "U3") (pin "18") (pinfunction "PVDD_18") (pintype "passive"))
    )
    (net (code "390") (name "410_PWR") (class "Default")
      (node (ref "C212") (pin "2") (pinfunction "2_2") (pintype "passive"))
      (node (ref "L2") (pin "1") (pinfunction "1_1") (pintype "passive"))
      (node (ref "L3") (pin "1") (pinfunction "1_1") (pintype "passive"))
      (node (ref "L30") (pin "2") (pinfunction "2_2") (pintype "passive"))
      (node (ref "L4") (pin "1") (pinfunction "1_1") (pintype "passive"))
    )
    (net (code "391") (name "410_TVDD") (class "Default")
      (node (ref "C132") (pin "1") (pinfunction "1_1") (pintype "passive"))
      (node (ref "C133") (pin "1") (pinfunction "1_1") (pintype "passive"))
      (node (ref "C142") (pin "2") (pinfunction "2_2") (pintype "passive"))
      (node (ref "C144") (pin "2") (pinfunction "2_2") (pintype "passive"))
      (node (ref "C183") (pin "1") (pinfunction "1_1") (pintype "passive"))
      (node (ref "L3") (pin "2") (pinfunction "2_2") (pintype "passive"))
      (node (ref "R98") (pin "2") (pinfunction "2_2") (pintype "passive"))
      (node (ref "U3") (pin "23") (pinfunction "TVDD_23") (pintype "passive"))
      (node (ref "U3") (pin "29") (pinfunction "TVDD_29") (pintype "passive"))
    )
    (net (code "392") (name "7125_3V3") (class "Default")
      (node (ref "C106") (pin "1") (pinfunction "1_1") (pintype "passive"))
      (node (ref "C107") (pin "2") (pinfunction "2_2") (pintype "passive"))
      (node (ref "C108") (pin "1") (pinfunction "1_1") (pintype "passive"))
      (node (ref "C109") (pin "2") (pinfunction "2_2") (pintype "passive"))
      (node (ref "C110") (pin "2") (pinfunction "2_2") (pintype "passive"))
      (node (ref "L33") (pin "2") (pinfunction "2_2") (pintype "passive"))
      (node (ref "Q1") (pin "1") (pinfunction "G_1") (pintype "passive"))
      (node (ref "Q2") (pin "1") (pinfunction "G_1") (pintype "passive"))
      (node (ref "Q3") (pin "1") (pinfunction "G_1") (pintype "passive"))
      (node (ref "Q4") (pin "1") (pinfunction "G_1") (pintype "passive"))
      (node (ref "R81") (pin "1") (pinfunction "1_1") (pintype "passive"))
      (node (ref "R82") (pin "1") (pinfunction "1_1") (pintype "passive"))
      (node (ref "R83") (pin "2") (pinfunction "2_2") (pintype "passive"))
      (node (ref "R87") (pin "2") (pinfunction "2_2") (pintype "passive"))
      (node (ref "R88") (pin "2") (pinfunction "2_2") (pintype "passive"))
      (node (ref "R89") (pin "2") (pinfunction "2_2") (pintype "passive"))
      (node (ref "R92") (pin "2") (pinfunction "2_2") (pintype "passive"))
      (node (ref "R93") (pin "2") (pinfunction "2_2") (pintype "passive"))
      (node (ref "U4") (pin "13") (pinfunction "VAA_13") (pintype "passive"))
      (node (ref "U4") (pin "29") (pinfunction "VAA_29") (pintype "passive"))
      (node (ref "U4") (pin "30") (pinfunction "VAA_30") (pintype "passive"))
    )
    (net (code "393") (name "FPGA_3V3") (class "Default")
      (node (ref "C1") (pin "2") (pinfunction "2_2") (pintype "passive"))
      (node (ref "C2") (pin "2") (pinfunction "2_2") (pintype "passive"))
      (node (ref "C209") (pin "2") (pinfunction "2_2") (pintype "passive"))
      (node (ref "C30") (pin "2") (pinfunction "2_2") (pintype "passive"))
      (node (ref "C31") (pin "2") (pinfunction "2_2") (pintype "passive"))
      (node (ref "C310") (pin "2") (pinfunction "2_2") (pintype "passive"))
      (node (ref "C32") (pin "2") (pinfunction "2_2") (pintype "passive"))
      (node (ref "C33") (pin "2") (pinfunction "2_2") (pintype "passive"))
      (node (ref "C34") (pin "2") (pinfunction "2_2") (pintype "passive"))
      (node (ref "C35") (pin "2") (pinfunction "2_2") (pintype "passive"))
      (node (ref "C36") (pin "2") (pinfunction "2_2") (pintype "passive"))
      (node (ref "C37") (pin "2") (pinfunction "2_2") (pintype "passive"))
      (node (ref "C38") (pin "2") (pinfunction "2_2") (pintype "passive"))
      (node (ref "C39") (pin "2") (pinfunction "2_2") (pintype "passive"))
      (node (ref "C40") (pin "2") (pinfunction "2_2") (pintype "passive"))
      (node (ref "C41") (pin "2") (pinfunction "2_2") (pintype "passive"))
      (node (ref "C54") (pin "2") (pinfunction "2_2") (pintype "passive"))
      (node (ref "C55") (pin "2") (pinfunction "2_2") (pintype "passive"))
      (node (ref "C56") (pin "2") (pinfunction "2_2") (pintype "passive"))
      (node (ref "C57") (pin "2") (pinfunction "2_2") (pintype "passive"))
      (node (ref "C58") (pin "2") (pinfunction "2_2") (pintype "passive"))
      (node (ref "C59") (pin "2") (pinfunction "2_2") (pintype "passive"))
      (node (ref "C60") (pin "2") (pinfunction "2_2") (pintype "passive"))
      (node (ref "C61") (pin "2") (pinfunction "2_2") (pintype "passive"))
      (node (ref "C62") (pin "2") (pinfunction "2_2") (pintype "passive"))
      (node (ref "C63") (pin "2") (pinfunction "2_2") (pintype "passive"))
      (node (ref "C64") (pin "2") (pinfunction "2_2") (pintype "passive"))
      (node (ref "C65") (pin "2") (pinfunction "2_2") (pintype "passive"))
      (node (ref "CN2") (pin "4") (pinfunction "4_4") (pintype "passive"))
      (node (ref "CN2") (pin "6") (pinfunction "6_6") (pintype "passive"))
      (node (ref "D1") (pin "2") (pinfunction "K_2") (pintype "passive"))
      (node (ref "D2") (pin "2") (pinfunction "K_2") (pintype "passive"))
      (node (ref "D3") (pin "2") (pinfunction "K_2") (pintype "passive"))
      (node (ref "D4") (pin "2") (pinfunction "K_2") (pintype "passive"))
      (node (ref "L29") (pin "2") (pinfunction "2_2") (pintype "passive"))
      (node (ref "R15") (pin "2") (pinfunction "2_2") (pintype "passive"))
      (node (ref "R150") (pin "2") (pinfunction "2_2") (pintype "passive"))
      (node (ref "R154") (pin "1") (pinfunction "1_1") (pintype "passive"))
      (node (ref "R16") (pin "2") (pinfunction "2_2") (pintype "passive"))
      (node (ref "R168") (pin "2") (pinfunction "2_2") (pintype "passive"))
      (node (ref "R169") (pin "2") (pinfunction "2_2") (pintype "passive"))
      (node (ref "R17") (pin "2") (pinfunction "2_2") (pintype "passive"))
      (node (ref "R18") (pin "1") (pinfunction "1_1") (pintype "passive"))
      (node (ref "R23") (pin "2") (pinfunction "2_2") (pintype "passive"))
      (node (ref "R24") (pin "2") (pinfunction "2_2") (pintype "passive"))
      (node (ref "R5") (pin "2") (pinfunction "2_2") (pintype "passive"))
      (node (ref "U100") (pin "5") (pinfunction "VCC_5") (pintype "passive"))
      (node (ref "U123") (pin "8") (pinfunction "VCC_8") (pintype "passive"))
      (node (ref "U22") (pin "1") (pinfunction "1_1") (pintype "passive"))
      (node (ref "U23") (pin "1") (pinfunction "1_1") (pintype "passive"))
      (node (ref "U8") (pin "AA11") (pinfunction "VCCO_2_AA11") (pintype "passive"))
      (node (ref "U8") (pin "AA15") (pinfunction "VCCO_2_AA15") (pintype "passive"))
      (node (ref "U8") (pin "AA19") (pinfunction "VCCO_2_AA19") (pintype "passive"))
      (node (ref "U8") (pin "AA22") (pinfunction "IO_L1N_M0_CMPMISO_2_AA22") (pintype "passive"))
      (node (ref "U8") (pin "AA3") (pinfunction "VCCO_2_AA3") (pintype "passive"))
      (node (ref "U8") (pin "AA7") (pinfunction "VCCO_2_AA7") (pintype "passive"))
      (node (ref "U8") (pin "B11") (pinfunction "VCCO_0_B11") (pintype "passive"))
      (node (ref "U8") (pin "B15") (pinfunction "VCCO_0_B15") (pintype "passive"))
      (node (ref "U8") (pin "B19") (pinfunction "VCCO_0_B19") (pintype "passive"))
      (node (ref "U8") (pin "B4") (pinfunction "VCCO_0_B4") (pintype "passive"))
      (node (ref "U8") (pin "B7") (pinfunction "VCCO_0_B7") (pintype "passive"))
      (node (ref "U8") (pin "E13") (pinfunction "VCCO_0_E13") (pintype "passive"))
      (node (ref "U8") (pin "E17") (pinfunction "VCCO_0_E17") (pintype "passive"))
      (node (ref "U8") (pin "E9") (pinfunction "VCCO_0_E9") (pintype "passive"))
      (node (ref "U8") (pin "G10") (pinfunction "VCCO_0_G10") (pintype "passive"))
      (node (ref "U8") (pin "G14") (pinfunction "VCCO_0_G14") (pintype "passive"))
      (node (ref "U8") (pin "T13") (pinfunction "VCCO_2_T13") (pintype "passive"))
      (node (ref "U8") (pin "T9") (pinfunction "VCCO_2_T9") (pintype "passive"))
      (node (ref "U8") (pin "V12") (pinfunction "VCCO_2_V12") (pintype "passive"))
      (node (ref "U8") (pin "V16") (pinfunction "VCCO_2_V16") (pintype "passive"))
      (node (ref "U8") (pin "V8") (pinfunction "VCCO_2_V8") (pintype "passive"))
      (node (ref "U8") (pin "W5") (pinfunction "VCCO_2_W5") (pintype "passive"))
    )
    (net (code "394") (name "GND") (class "Default")
      (node (ref "C1") (pin "1") (pinfunction "1_1") (pintype "passive"))
      (node (ref "C10") (pin "1") (pinfunction "1_1") (pintype "passive"))
      (node (ref "C100") (pin "1") (pinfunction "1_1") (pintype "passive"))
      (node (ref "C101") (pin "1") (pinfunction "1_1") (pintype "passive"))
      (node (ref "C102") (pin "2") (pinfunction "2_2") (pintype "passive"))
      (node (ref "C103") (pin "2") (pinfunction "2_2") (pintype "passive"))
      (node (ref "C104") (pin "2") (pinfunction "2_2") (pintype "passive"))
      (node (ref "C105") (pin "2") (pinfunction "2_2") (pintype "passive"))
      (node (ref "C106") (pin "2") (pinfunction "2_2") (pintype "passive"))
      (node (ref "C107") (pin "1") (pinfunction "1_1") (pintype "passive"))
      (node (ref "C108") (pin "2") (pinfunction "2_2") (pintype "passive"))
      (node (ref "C109") (pin "1") (pinfunction "1_1") (pintype "passive"))
      (node (ref "C11") (pin "1") (pinfunction "1_1") (pintype "passive"))
      (node (ref "C111") (pin "1") (pinfunction "1_1") (pintype "passive"))
      (node (ref "C112") (pin "1") (pinfunction "1_1") (pintype "passive"))
      (node (ref "C113") (pin "1") (pinfunction "1_1") (pintype "passive"))
      (node (ref "C114") (pin "1") (pinfunction "1_1") (pintype "passive"))
      (node (ref "C115") (pin "1") (pinfunction "1_1") (pintype "passive"))
      (node (ref "C116") (pin "1") (pinfunction "1_1") (pintype "passive"))
      (node (ref "C117") (pin "1") (pinfunction "1_1") (pintype "passive"))
      (node (ref "C118") (pin "1") (pinfunction "1_1") (pintype "passive"))
      (node (ref "C119") (pin "2") (pinfunction "2_2") (pintype "passive"))
      (node (ref "C12") (pin "1") (pinfunction "1_1") (pintype "passive"))
      (node (ref "C120") (pin "1") (pinfunction "1_1") (pintype "passive"))
      (node (ref "C121") (pin "1") (pinfunction "1_1") (pintype "passive"))
      (node (ref "C122") (pin "1") (pinfunction "1_1") (pintype "passive"))
      (node (ref "C123") (pin "1") (pinfunction "1_1") (pintype "passive"))
      (node (ref "C124") (pin "2") (pinfunction "2_2") (pintype "passive"))
      (node (ref "C125") (pin "1") (pinfunction "1_1") (pintype "passive"))
      (node (ref "C128") (pin "1") (pinfunction "1_1") (pintype "passive"))
      (node (ref "C129") (pin "2") (pinfunction "2_2") (pintype "passive"))
      (node (ref "C13") (pin "1") (pinfunction "1_1") (pintype "passive"))
      (node (ref "C132") (pin "2") (pinfunction "2_2") (pintype "passive"))
      (node (ref "C133") (pin "2") (pinfunction "2_2") (pintype "passive"))
      (node (ref "C135") (pin "2") (pinfunction "2_2") (pintype "passive"))
      (node (ref "C136") (pin "2") (pinfunction "2_2") (pintype "passive"))
      (node (ref "C14") (pin "1") (pinfunction "1_1") (pintype "passive"))
      (node (ref "C141") (pin "1") (pinfunction "1_1") (pintype "passive"))
      (node (ref "C142") (pin "1") (pinfunction "1_1") (pintype "passive"))
      (node (ref "C143") (pin "1") (pinfunction "1_1") (pintype "passive"))
      (node (ref "C144") (pin "1") (pinfunction "1_1") (pintype "passive"))
      (node (ref "C145") (pin "1") (pinfunction "1_1") (pintype "passive"))
      (node (ref "C146") (pin "1") (pinfunction "1_1") (pintype "passive"))
      (node (ref "C147") (pin "1") (pinfunction "1_1") (pintype "passive"))
      (node (ref "C148") (pin "1") (pinfunction "1_1") (pintype "passive"))
      (node (ref "C149") (pin "1") (pinfunction "1_1") (pintype "passive"))
      (node (ref "C15") (pin "1") (pinfunction "1_1") (pintype "passive"))
      (node (ref "C150") (pin "1") (pinfunction "1_1") (pintype "passive"))
      (node (ref "C153") (pin "2") (pinfunction "2_2") (pintype "passive"))
      (node (ref "C157") (pin "2") (pinfunction "2_2") (pintype "passive"))
      (node (ref "C158") (pin "2") (pinfunction "2_2") (pintype "passive"))
      (node (ref "C159") (pin "2") (pinfunction "2_2") (pintype "passive"))
      (node (ref "C16") (pin "1") (pinfunction "1_1") (pintype "passive"))
      (node (ref "C162") (pin "2") (pinfunction "2_2") (pintype "passive"))
      (node (ref "C166") (pin "1") (pinfunction "1_1") (pintype "passive"))
      (node (ref "C167") (pin "1") (pinfunction "1_1") (pintype "passive"))
      (node (ref "C169") (pin "1") (pinfunction "1_1") (pintype "passive"))
      (node (ref "C17") (pin "1") (pinfunction "1_1") (pintype "passive"))
      (node (ref "C171") (pin "1") (pinfunction "1_1") (pintype "passive"))
      (node (ref "C173") (pin "2") (pinfunction "2_2") (pintype "passive"))
      (node (ref "C176") (pin "1") (pinfunction "1_1") (pintype "passive"))
      (node (ref "C178") (pin "2") (pinfunction "2_2") (pintype "passive"))
      (node (ref "C179") (pin "2") (pinfunction "2_2") (pintype "passive"))
      (node (ref "C18") (pin "1") (pinfunction "1_1") (pintype "passive"))
      (node (ref "C180") (pin "2") (pinfunction "2_2") (pintype "passive"))
      (node (ref "C181") (pin "2") (pinfunction "2_2") (pintype "passive"))
      (node (ref "C182") (pin "2") (pinfunction "2_2") (pintype "passive"))
      (node (ref "C183") (pin "2") (pinfunction "2_2") (pintype "passive"))
      (node (ref "C184") (pin "2") (pinfunction "2_2") (pintype "passive"))
      (node (ref "C185") (pin "1") (pinfunction "1_1") (pintype "passive"))
      (node (ref "C186") (pin "1") (pinfunction "1_1") (pintype "passive"))
      (node (ref "C187") (pin "1") (pinfunction "1_1") (pintype "passive"))
      (node (ref "C188") (pin "1") (pinfunction "1_1") (pintype "passive"))
      (node (ref "C189") (pin "1") (pinfunction "1_1") (pintype "passive"))
      (node (ref "C19") (pin "1") (pinfunction "1_1") (pintype "passive"))
      (node (ref "C190") (pin "1") (pinfunction "1_1") (pintype "passive"))
      (node (ref "C191") (pin "1") (pinfunction "1_1") (pintype "passive"))
      (node (ref "C192") (pin "2") (pinfunction "2_2") (pintype "passive"))
      (node (ref "C193") (pin "1") (pinfunction "1_1") (pintype "passive"))
      (node (ref "C194") (pin "1") (pinfunction "1_1") (pintype "passive"))
      (node (ref "C195") (pin "1") (pinfunction "1_1") (pintype "passive"))
      (node (ref "C196") (pin "1") (pinfunction "1_1") (pintype "passive"))
      (node (ref "C197") (pin "1") (pinfunction "1_1") (pintype "passive"))
      (node (ref "C198") (pin "1") (pinfunction "1_1") (pintype "passive"))
      (node (ref "C199") (pin "1") (pinfunction "1_1") (pintype "passive"))
      (node (ref "C2") (pin "1") (pinfunction "1_1") (pintype "passive"))
      (node (ref "C20") (pin "1") (pinfunction "1_1") (pintype "passive"))
      (node (ref "C200") (pin "1") (pinfunction "1_1") (pintype "passive"))
      (node (ref "C201") (pin "1") (pinfunction "1_1") (pintype "passive"))
      (node (ref "C204") (pin "1") (pinfunction "1_1") (pintype "passive"))
      (node (ref "C205") (pin "1") (pinfunction "1_1") (pintype "passive"))
      (node (ref "C206") (pin "1") (pinfunction "1_1") (pintype "passive"))
      (node (ref "C207") (pin "1") (pinfunction "1_1") (pintype "passive"))
      (node (ref "C208") (pin "1") (pinfunction "1_1") (pintype "passive"))
      (node (ref "C209") (pin "1") (pinfunction "1_1") (pintype "passive"))
      (node (ref "C21") (pin "1") (pinfunction "1_1") (pintype "passive"))
      (node (ref "C210") (pin "1") (pinfunction "1_1") (pintype "passive"))
      (node (ref "C211") (pin "1") (pinfunction "1_1") (pintype "passive"))
      (node (ref "C212") (pin "1") (pinfunction "1_1") (pintype "passive"))
      (node (ref "C213") (pin "1") (pinfunction "1_1") (pintype "passive"))
      (node (ref "C214") (pin "1") (pinfunction "1_1") (pintype "passive"))
      (node (ref "C215") (pin "1") (pinfunction "1_1") (pintype "passive"))
      (node (ref "C216") (pin "1") (pinfunction "1_1") (pintype "passive"))
      (node (ref "C217") (pin "2") (pinfunction "2_2") (pintype "passive"))
      (node (ref "C218") (pin "2") (pinfunction "2_2") (pintype "passive"))
      (node (ref "C219") (pin "2") (pinfunction "2_2") (pintype "passive"))
      (node (ref "C22") (pin "1") (pinfunction "1_1") (pintype "passive"))
      (node (ref "C220") (pin "1") (pinfunction "1_1") (pintype "passive"))
      (node (ref "C221") (pin "1") (pinfunction "1_1") (pintype "passive"))
      (node (ref "C222") (pin "1") (pinfunction "1_1") (pintype "passive"))
      (node (ref "C223") (pin "1") (pinfunction "1_1") (pintype "passive"))
      (node (ref "C224") (pin "1") (pinfunction "1_1") (pintype "passive"))
      (node (ref "C225") (pin "1") (pinfunction "1_1") (pintype "passive"))
      (node (ref "C226") (pin "1") (pinfunction "1_1") (pintype "passive"))
      (node (ref "C227") (pin "1") (pinfunction "1_1") (pintype "passive"))
      (node (ref "C228") (pin "1") (pinfunction "1_1") (pintype "passive"))
      (node (ref "C229") (pin "1") (pinfunction "1_1") (pintype "passive"))
      (node (ref "C23") (pin "1") (pinfunction "1_1") (pintype "passive"))
      (node (ref "C230") (pin "1") (pinfunction "1_1") (pintype "passive"))
      (node (ref "C231") (pin "1") (pinfunction "1_1") (pintype "passive"))
      (node (ref "C232") (pin "1") (pinfunction "1_1") (pintype "passive"))
      (node (ref "C233") (pin "1") (pinfunction "1_1") (pintype "passive"))
      (node (ref "C234") (pin "1") (pinfunction "1_1") (pintype "passive"))
      (node (ref "C235") (pin "1") (pinfunction "1_1") (pintype "passive"))
      (node (ref "C236") (pin "1") (pinfunction "1_1") (pintype "passive"))
      (node (ref "C237") (pin "1") (pinfunction "1_1") (pintype "passive"))
      (node (ref "C238") (pin "1") (pinfunction "1_1") (pintype "passive"))
      (node (ref "C239") (pin "1") (pinfunction "1_1") (pintype "passive"))
      (node (ref "C24") (pin "1") (pinfunction "1_1") (pintype "passive"))
      (node (ref "C240") (pin "1") (pinfunction "1_1") (pintype "passive"))
      (node (ref "C241") (pin "1") (pinfunction "1_1") (pintype "passive"))
      (node (ref "C242") (pin "1") (pinfunction "1_1") (pintype "passive"))
      (node (ref "C243") (pin "1") (pinfunction "1_1") (pintype "passive"))
      (node (ref "C244") (pin "1") (pinfunction "1_1") (pintype "passive"))
      (node (ref "C245") (pin "1") (pinfunction "1_1") (pintype "passive"))
      (node (ref "C246") (pin "1") (pinfunction "1_1") (pintype "passive"))
      (node (ref "C247") (pin "1") (pinfunction "1_1") (pintype "passive"))
      (node (ref "C248") (pin "1") (pinfunction "1_1") (pintype "passive"))
      (node (ref "C249") (pin "1") (pinfunction "1_1") (pintype "passive"))
      (node (ref "C25") (pin "1") (pinfunction "1_1") (pintype "passive"))
      (node (ref "C250") (pin "1") (pinfunction "1_1") (pintype "passive"))
      (node (ref "C251") (pin "1") (pinfunction "1_1") (pintype "passive"))
      (node (ref "C259") (pin "2") (pinfunction "2_2") (pintype "passive"))
      (node (ref "C260") (pin "2") (pinfunction "2_2") (pintype "passive"))
      (node (ref "C261") (pin "1") (pinfunction "1_1") (pintype "passive"))
      (node (ref "C262") (pin "1") (pinfunction "1_1") (pintype "passive"))
      (node (ref "C263") (pin "1") (pinfunction "1_1") (pintype "passive"))
      (node (ref "C264") (pin "1") (pinfunction "1_1") (pintype "passive"))
      (node (ref "C265") (pin "1") (pinfunction "1_1") (pintype "passive"))
      (node (ref "C266") (pin "1") (pinfunction "1_1") (pintype "passive"))
      (node (ref "C267") (pin "1") (pinfunction "1_1") (pintype "passive"))
      (node (ref "C268") (pin "1") (pinfunction "1_1") (pintype "passive"))
      (node (ref "C269") (pin "1") (pinfunction "1_1") (pintype "passive"))
      (node (ref "C270") (pin "1") (pinfunction "1_1") (pintype "passive"))
      (node (ref "C271") (pin "1") (pinfunction "1_1") (pintype "passive"))
      (node (ref "C272") (pin "1") (pinfunction "1_1") (pintype "passive"))
      (node (ref "C273") (pin "1") (pinfunction "1_1") (pintype "passive"))
      (node (ref "C274") (pin "1") (pinfunction "1_1") (pintype "passive"))
      (node (ref "C275") (pin "1") (pinfunction "1_1") (pintype "passive"))
      (node (ref "C276") (pin "1") (pinfunction "1_1") (pintype "passive"))
      (node (ref "C277") (pin "1") (pinfunction "1_1") (pintype "passive"))
      (node (ref "C278") (pin "1") (pinfunction "1_1") (pintype "passive"))
      (node (ref "C279") (pin "1") (pinfunction "1_1") (pintype "passive"))
      (node (ref "C280") (pin "1") (pinfunction "1_1") (pintype "passive"))
      (node (ref "C281") (pin "1") (pinfunction "1_1") (pintype "passive"))
      (node (ref "C282") (pin "1") (pinfunction "1_1") (pintype "passive"))
      (node (ref "C283") (pin "1") (pinfunction "1_1") (pintype "passive"))
      (node (ref "C284") (pin "1") (pinfunction "1_1") (pintype "passive"))
      (node (ref "C285") (pin "1") (pinfunction "1_1") (pintype "passive"))
      (node (ref "C286") (pin "1") (pinfunction "1_1") (pintype "passive"))
      (node (ref "C287") (pin "1") (pinfunction "1_1") (pintype "passive"))
      (node (ref "C288") (pin "1") (pinfunction "1_1") (pintype "passive"))
      (node (ref "C289") (pin "1") (pinfunction "1_1") (pintype "passive"))
      (node (ref "C29") (pin "1") (pinfunction "1_1") (pintype "passive"))
      (node (ref "C290") (pin "1") (pinfunction "1_1") (pintype "passive"))
      (node (ref "C291") (pin "1") (pinfunction "1_1") (pintype "passive"))
      (node (ref "C292") (pin "1") (pinfunction "1_1") (pintype "passive"))
      (node (ref "C293") (pin "1") (pinfunction "1_1") (pintype "passive"))
      (node (ref "C294") (pin "1") (pinfunction "1_1") (pintype "passive"))
      (node (ref "C295") (pin "1") (pinfunction "1_1") (pintype "passive"))
      (node (ref "C296") (pin "1") (pinfunction "1_1") (pintype "passive"))
      (node (ref "C297") (pin "1") (pinfunction "1_1") (pintype "passive"))
      (node (ref "C298") (pin "1") (pinfunction "1_1") (pintype "passive"))
      (node (ref "C299") (pin "1") (pinfunction "1_1") (pintype "passive"))
      (node (ref "C3") (pin "1") (pinfunction "1_1") (pintype "passive"))
      (node (ref "C30") (pin "1") (pinfunction "1_1") (pintype "passive"))
      (node (ref "C300") (pin "1") (pinfunction "1_1") (pintype "passive"))
      (node (ref "C301") (pin "1") (pinfunction "1_1") (pintype "passive"))
      (node (ref "C302") (pin "1") (pinfunction "1_1") (pintype "passive"))
      (node (ref "C303") (pin "1") (pinfunction "1_1") (pintype "passive"))
      (node (ref "C304") (pin "1") (pinfunction "1_1") (pintype "passive"))
      (node (ref "C305") (pin "1") (pinfunction "1_1") (pintype "passive"))
      (node (ref "C306") (pin "1") (pinfunction "1_1") (pintype "passive"))
      (node (ref "C307") (pin "1") (pinfunction "1_1") (pintype "passive"))
      (node (ref "C308") (pin "1") (pinfunction "1_1") (pintype "passive"))
      (node (ref "C309") (pin "1") (pinfunction "1_1") (pintype "passive"))
      (node (ref "C31") (pin "1") (pinfunction "1_1") (pintype "passive"))
      (node (ref "C310") (pin "1") (pinfunction "1_1") (pintype "passive"))
      (node (ref "C311") (pin "1") (pinfunction "1_1") (pintype "passive"))
      (node (ref "C312") (pin "1") (pinfunction "1_1") (pintype "passive"))
      (node (ref "C313") (pin "1") (pinfunction "1_1") (pintype "passive"))
      (node (ref "C32") (pin "1") (pinfunction "1_1") (pintype "passive"))
      (node (ref "C33") (pin "1") (pinfunction "1_1") (pintype "passive"))
      (node (ref "C34") (pin "1") (pinfunction "1_1") (pintype "passive"))
      (node (ref "C35") (pin "1") (pinfunction "1_1") (pintype "passive"))
      (node (ref "C36") (pin "1") (pinfunction "1_1") (pintype "passive"))
      (node (ref "C37") (pin "1") (pinfunction "1_1") (pintype "passive"))
      (node (ref "C38") (pin "1") (pinfunction "1_1") (pintype "passive"))
      (node (ref "C39") (pin "1") (pinfunction "1_1") (pintype "passive"))
      (node (ref "C4") (pin "1") (pinfunction "1_1") (pintype "passive"))
      (node (ref "C40") (pin "1") (pinfunction "1_1") (pintype "passive"))
      (node (ref "C41") (pin "1") (pinfunction "1_1") (pintype "passive"))
      (node (ref "C42") (pin "1") (pinfunction "1_1") (pintype "passive"))
      (node (ref "C43") (pin "1") (pinfunction "1_1") (pintype "passive"))
      (node (ref "C44") (pin "1") (pinfunction "1_1") (pintype "passive"))
      (node (ref "C45") (pin "1") (pinfunction "1_1") (pintype "passive"))
      (node (ref "C46") (pin "1") (pinfunction "1_1") (pintype "passive"))
      (node (ref "C47") (pin "1") (pinfunction "1_1") (pintype "passive"))
      (node (ref "C48") (pin "1") (pinfunction "1_1") (pintype "passive"))
      (node (ref "C49") (pin "1") (pinfunction "1_1") (pintype "passive"))
      (node (ref "C5") (pin "1") (pinfunction "1_1") (pintype "passive"))
      (node (ref "C50") (pin "1") (pinfunction "1_1") (pintype "passive"))
      (node (ref "C51") (pin "1") (pinfunction "1_1") (pintype "passive"))
      (node (ref "C52") (pin "1") (pinfunction "1_1") (pintype "passive"))
      (node (ref "C53") (pin "1") (pinfunction "1_1") (pintype "passive"))
      (node (ref "C54") (pin "1") (pinfunction "1_1") (pintype "passive"))
      (node (ref "C55") (pin "1") (pinfunction "1_1") (pintype "passive"))
      (node (ref "C56") (pin "1") (pinfunction "1_1") (pintype "passive"))
      (node (ref "C57") (pin "1") (pinfunction "1_1") (pintype "passive"))
      (node (ref "C58") (pin "1") (pinfunction "1_1") (pintype "passive"))
      (node (ref "C59") (pin "1") (pinfunction "1_1") (pintype "passive"))
      (node (ref "C6") (pin "1") (pinfunction "1_1") (pintype "passive"))
      (node (ref "C60") (pin "1") (pinfunction "1_1") (pintype "passive"))
      (node (ref "C61") (pin "1") (pinfunction "1_1") (pintype "passive"))
      (node (ref "C62") (pin "1") (pinfunction "1_1") (pintype "passive"))
      (node (ref "C63") (pin "1") (pinfunction "1_1") (pintype "passive"))
      (node (ref "C64") (pin "1") (pinfunction "1_1") (pintype "passive"))
      (node (ref "C65") (pin "1") (pinfunction "1_1") (pintype "passive"))
      (node (ref "C66") (pin "1") (pinfunction "1_1") (pintype "passive"))
      (node (ref "C67") (pin "1") (pinfunction "1_1") (pintype "passive"))
      (node (ref "C68") (pin "1") (pinfunction "1_1") (pintype "passive"))
      (node (ref "C69") (pin "1") (pinfunction "1_1") (pintype "passive"))
      (node (ref "C7") (pin "1") (pinfunction "1_1") (pintype "passive"))
      (node (ref "C70") (pin "1") (pinfunction "1_1") (pintype "passive"))
      (node (ref "C71") (pin "1") (pinfunction "1_1") (pintype "passive"))
      (node (ref "C72") (pin "1") (pinfunction "1_1") (pintype "passive"))
      (node (ref "C73") (pin "1") (pinfunction "1_1") (pintype "passive"))
      (node (ref "C74") (pin "1") (pinfunction "1_1") (pintype "passive"))
      (node (ref "C75") (pin "1") (pinfunction "1_1") (pintype "passive"))
      (node (ref "C76") (pin "1") (pinfunction "1_1") (pintype "passive"))
      (node (ref "C77") (pin "1") (pinfunction "1_1") (pintype "passive"))
      (node (ref "C78") (pin "1") (pinfunction "1_1") (pintype "passive"))
      (node (ref "C79") (pin "1") (pinfunction "1_1") (pintype "passive"))
      (node (ref "C8") (pin "1") (pinfunction "1_1") (pintype "passive"))
      (node (ref "C80") (pin "1") (pinfunction "1_1") (pintype "passive"))
      (node (ref "C81") (pin "1") (pinfunction "1_1") (pintype "passive"))
      (node (ref "C82") (pin "1") (pinfunction "1_1") (pintype "passive"))
      (node (ref "C83") (pin "1") (pinfunction "1_1") (pintype "passive"))
      (node (ref "C84") (pin "1") (pinfunction "1_1") (pintype "passive"))
      (node (ref "C85") (pin "1") (pinfunction "1_1") (pintype "passive"))
      (node (ref "C86") (pin "1") (pinfunction "1_1") (pintype "passive"))
      (node (ref "C87") (pin "1") (pinfunction "1_1") (pintype "passive"))
      (node (ref "C88") (pin "1") (pinfunction "1_1") (pintype "passive"))
      (node (ref "C89") (pin "1") (pinfunction "1_1") (pintype "passive"))
      (node (ref "C9") (pin "1") (pinfunction "1_1") (pintype "passive"))
      (node (ref "C90") (pin "1") (pinfunction "1_1") (pintype "passive"))
      (node (ref "C91") (pin "1") (pinfunction "1_1") (pintype "passive"))
      (node (ref "C92") (pin "1") (pinfunction "1_1") (pintype "passive"))
      (node (ref "C93") (pin "1") (pinfunction "1_1") (pintype "passive"))
      (node (ref "C94") (pin "1") (pinfunction "1_1") (pintype "passive"))
      (node (ref "C95") (pin "1") (pinfunction "1_1") (pintype "passive"))
      (node (ref "C96") (pin "1") (pinfunction "1_1") (pintype "passive"))
      (node (ref "C97") (pin "1") (pinfunction "1_1") (pintype "passive"))
      (node (ref "C98") (pin "1") (pinfunction "1_1") (pintype "passive"))
      (node (ref "C99") (pin "1") (pinfunction "1_1") (pintype "passive"))
      (node (ref "CN2") (pin "10") (pinfunction "10_10") (pintype "passive"))
      (node (ref "CN2") (pin "2") (pinfunction "2_2") (pintype "passive"))
      (node (ref "D1") (pin "1") (pinfunction "A_1") (pintype "passive"))
      (node (ref "D12") (pin "2") (pinfunction "2_2") (pintype "passive"))
      (node (ref "D13") (pin "3") (pinfunction "GND_3") (pintype "passive"))
      (node (ref "D13") (pin "8") (pinfunction "GND_8") (pintype "passive"))
      (node (ref "D14") (pin "3") (pinfunction "GND_3") (pintype "passive"))
      (node (ref "D14") (pin "8") (pinfunction "GND_8") (pintype "passive"))
      (node (ref "D16") (pin "2") (pinfunction "2_2") (pintype "passive"))
      (node (ref "D2") (pin "1") (pinfunction "A_1") (pintype "passive"))
      (node (ref "D20") (pin "2") (pinfunction "A_2") (pintype "passive"))
      (node (ref "D21") (pin "2") (pinfunction "A_2") (pintype "passive"))
      (node (ref "D3") (pin "1") (pinfunction "A_1") (pintype "passive"))
      (node (ref "D4") (pin "1") (pinfunction "A_1") (pintype "passive"))
      (node (ref "D6") (pin "2") (pinfunction "2_2") (pintype "passive"))
      (node (ref "D7") (pin "3") (pinfunction "GND_3") (pintype "passive"))
      (node (ref "D7") (pin "8") (pinfunction "GND_8") (pintype "passive"))
      (node (ref "D8") (pin "3") (pinfunction "GND_3") (pintype "passive"))
      (node (ref "D8") (pin "8") (pinfunction "GND_8") (pintype "passive"))
      (node (ref "DC3") (pin "4") (pinfunction "4_4") (pintype "passive"))
      (node (ref "DC3") (pin "6") (pinfunction "6_6") (pintype "passive"))
      (node (ref "DSUB1") (pin "10") (pinfunction "10_10") (pintype "passive"))
      (node (ref "DSUB1") (pin "16") (pinfunction "16_16") (pintype "passive"))
      (node (ref "DSUB1") (pin "17") (pinfunction "17_17") (pintype "passive"))
      (node (ref "DSUB1") (pin "5") (pinfunction "5_5") (pintype "passive"))
      (node (ref "DSUB1") (pin "6") (pinfunction "6_6") (pintype "passive"))
      (node (ref "DSUB1") (pin "7") (pinfunction "7_7") (pintype "passive"))
      (node (ref "DSUB1") (pin "8") (pinfunction "8_8") (pintype "passive"))
      (node (ref "LED1") (pin "2") (pinfunction "K_2") (pintype "passive"))
      (node (ref "Q10") (pin "2") (pinfunction "S_2") (pintype "passive"))
      (node (ref "Q13") (pin "2") (pinfunction "S_2") (pintype "passive"))
      (node (ref "Q14") (pin "2") (pinfunction "S_2") (pintype "passive"))
      (node (ref "Q15") (pin "2") (pinfunction "S_2") (pintype "passive"))
      (node (ref "Q16") (pin "2") (pinfunction "S_2") (pintype "passive"))
      (node (ref "Q5") (pin "2") (pinfunction "S_2") (pintype "passive"))
      (node (ref "Q6") (pin "2") (pinfunction "S_2") (pintype "passive"))
      (node (ref "Q9") (pin "2") (pinfunction "S_2") (pintype "passive"))
      (node (ref "R1") (pin "2") (pinfunction "2_2") (pintype "passive"))
      (node (ref "R103") (pin "1") (pinfunction "1_1") (pintype "passive"))
      (node (ref "R134") (pin "1") (pinfunction "1_1") (pintype "passive"))
      (node (ref "R137") (pin "1") (pinfunction "1_1") (pintype "passive"))
      (node (ref "R139") (pin "1") (pinfunction "1_1") (pintype "passive"))
      (node (ref "R141") (pin "1") (pinfunction "1_1") (pintype "passive"))
      (node (ref "R149") (pin "1") (pinfunction "1_1") (pintype "passive"))
      (node (ref "R185") (pin "1") (pinfunction "1_1") (pintype "passive"))
      (node (ref "R186") (pin "2") (pinfunction "2_2") (pintype "passive"))
      (node (ref "R187") (pin "2") (pinfunction "2_2") (pintype "passive"))
      (node (ref "R188") (pin "2") (pinfunction "2_2") (pintype "passive"))
      (node (ref "R189") (pin "2") (pinfunction "2_2") (pintype "passive"))
      (node (ref "R196") (pin "1") (pinfunction "1_1") (pintype "passive"))
      (node (ref "R197") (pin "1") (pinfunction "1_1") (pintype "passive"))
      (node (ref "R198") (pin "1") (pinfunction "1_1") (pintype "passive"))
      (node (ref "R2") (pin "2") (pinfunction "2_2") (pintype "passive"))
      (node (ref "R25") (pin "1") (pinfunction "1_1") (pintype "passive"))
      (node (ref "R26") (pin "2") (pinfunction "2_2") (pintype "passive"))
      (node (ref "R51") (pin "2") (pinfunction "2_2") (pintype "passive"))
      (node (ref "R52") (pin "2") (pinfunction "2_2") (pintype "passive"))
      (node (ref "R53") (pin "2") (pinfunction "2_2") (pintype "passive"))
      (node (ref "R78") (pin "3") (pinfunction "3_3") (pintype "passive"))
      (node (ref "R84") (pin "1") (pinfunction "1_1") (pintype "passive"))
      (node (ref "R85") (pin "1") (pinfunction "1_1") (pintype "passive"))
      (node (ref "R86") (pin "1") (pinfunction "1_1") (pintype "passive"))
      (node (ref "R97") (pin "1") (pinfunction "1_1") (pintype "passive"))
      (node (ref "SW1") (pin "5") (pinfunction "B4_5") (pintype "passive"))
      (node (ref "SW1") (pin "6") (pinfunction "B3_6") (pintype "passive"))
      (node (ref "SW1") (pin "7") (pinfunction "B2_7") (pintype "passive"))
      (node (ref "SW1") (pin "8") (pinfunction "B1_8") (pintype "passive"))
      (node (ref "SW2") (pin "5") (pinfunction "B4_5") (pintype "passive"))
      (node (ref "SW2") (pin "6") (pinfunction "B3_6") (pintype "passive"))
      (node (ref "SW2") (pin "7") (pinfunction "B2_7") (pintype "passive"))
      (node (ref "SW2") (pin "8") (pinfunction "B1_8") (pintype "passive"))
      (node (ref "U100") (pin "3") (pinfunction "GND_3") (pintype "passive"))
      (node (ref "U102") (pin "1") (pinfunction "1_1") (pintype "passive"))
      (node (ref "U12") (pin "A9") (pinfunction "VSS_A9") (pintype "passive"))
      (node (ref "U12") (pin "B1") (pinfunction "VSSQ_B1") (pintype "passive"))
      (node (ref "U12") (pin "B3") (pinfunction "VSS_B3") (pintype "passive"))
      (node (ref "U12") (pin "B9") (pinfunction "VSSQ_B9") (pintype "passive"))
      (node (ref "U12") (pin "D1") (pinfunction "VSSQ_D1") (pintype "passive"))
      (node (ref "U12") (pin "D8") (pinfunction "VSSQ_D8") (pintype "passive"))
      (node (ref "U12") (pin "E1") (pinfunction "VSS_E1") (pintype "passive"))
      (node (ref "U12") (pin "E2") (pinfunction "VSSQ_E2") (pintype "passive"))
      (node (ref "U12") (pin "E8") (pinfunction "VSSQ_E8") (pintype "passive"))
      (node (ref "U12") (pin "F9") (pinfunction "VSSQ_F9") (pintype "passive"))
      (node (ref "U12") (pin "G1") (pinfunction "VSSQ_G1") (pintype "passive"))
      (node (ref "U12") (pin "G8") (pinfunction "VSS_G8") (pintype "passive"))
      (node (ref "U12") (pin "G9") (pinfunction "VSSQ_G9") (pintype "passive"))
      (node (ref "U12") (pin "J2") (pinfunction "VSS_J2") (pintype "passive"))
      (node (ref "U12") (pin "J8") (pinfunction "VSS_J8") (pintype "passive"))
      (node (ref "U12") (pin "L2") (pinfunction "CS#_L2") (pintype "passive"))
      (node (ref "U12") (pin "M1") (pinfunction "VSS_M1") (pintype "passive"))
      (node (ref "U12") (pin "M9") (pinfunction "VSS_M9") (pintype "passive"))
      (node (ref "U12") (pin "P1") (pinfunction "VSS_P1") (pintype "passive"))
      (node (ref "U12") (pin "P9") (pinfunction "VSS_P9") (pintype "passive"))
      (node (ref "U12") (pin "T1") (pinfunction "VSS_T1") (pintype "passive"))
      (node (ref "U12") (pin "T9") (pinfunction "VSS_T9") (pintype "passive"))
      (node (ref "U122") (pin "1") (pinfunction "1_1") (pintype "passive"))
      (node (ref "U123") (pin "4") (pinfunction "GND_4") (pintype "passive"))
      (node (ref "U13") (pin "2") (pinfunction "V-_2") (pintype "passive"))
      (node (ref "U14") (pin "1") (pinfunction "1_1") (pintype "passive"))
      (node (ref "U19") (pin "4") (pinfunction "GND_4") (pintype "passive"))
      (node (ref "U2") (pin "101") (pinfunction "EP_101") (pintype "passive"))
      (node (ref "U2") (pin "19") (pinfunction "OGND_19") (pintype "passive"))
      (node (ref "U2") (pin "28") (pinfunction "OGND_28") (pintype "passive"))
      (node (ref "U2") (pin "39") (pinfunction "GND_39") (pintype "passive"))
      (node (ref "U2") (pin "45") (pinfunction "OGND_45") (pintype "passive"))
      (node (ref "U2") (pin "5") (pinfunction "GND_5") (pintype "passive"))
      (node (ref "U2") (pin "58") (pinfunction "OGND_58") (pintype "passive"))
      (node (ref "U2") (pin "68") (pinfunction "GND_68") (pintype "passive"))
      (node (ref "U2") (pin "76") (pinfunction "OGND_76") (pintype "passive"))
      (node (ref "U2") (pin "79") (pinfunction "AGND_79") (pintype "passive"))
      (node (ref "U2") (pin "83") (pinfunction "AGND_83") (pintype "passive"))
      (node (ref "U2") (pin "87") (pinfunction "AGND_87") (pintype "passive"))
      (node (ref "U2") (pin "89") (pinfunction "AGND_89") (pintype "passive"))
      (node (ref "U2") (pin "92") (pinfunction "AGND_92") (pintype "passive"))
      (node (ref "U2") (pin "98") (pinfunction "PGND_98") (pintype "passive"))
      (node (ref "U25") (pin "1") (pinfunction "1_1") (pintype "passive"))
      (node (ref "U3") (pin "16") (pinfunction "DGND_16") (pintype "passive"))
      (node (ref "U3") (pin "17") (pinfunction "PGND_17") (pintype "passive"))
      (node (ref "U3") (pin "20") (pinfunction "TGND_20") (pintype "passive"))
      (node (ref "U3") (pin "26") (pinfunction "TGND_26") (pintype "passive"))
      (node (ref "U3") (pin "32") (pinfunction "TGND_32") (pintype "passive"))
      (node (ref "U3") (pin "34") (pinfunction "RESERVED_34") (pintype "passive"))
      (node (ref "U3") (pin "48") (pinfunction "DGND_48") (pintype "passive"))
      (node (ref "U3") (pin "56") (pinfunction "IDCK-_56") (pintype "passive"))
      (node (ref "U3") (pin "64") (pinfunction "DGND_64") (pintype "passive"))
      (node (ref "U3") (pin "65") (pinfunction "EP_65") (pintype "passive"))
      (node (ref "U33") (pin "1") (pinfunction "A0_1") (pintype "passive"))
      (node (ref "U33") (pin "2") (pinfunction "A1_2") (pintype "passive"))
      (node (ref "U33") (pin "3") (pinfunction "A2_3") (pintype "passive"))
      (node (ref "U33") (pin "4") (pinfunction "GND_4") (pintype "passive"))
      (node (ref "U33") (pin "7") (pinfunction "WP_7") (pintype "passive"))
      (node (ref "U4") (pin "1") (pinfunction "GND_1") (pintype "passive"))
      (node (ref "U4") (pin "14") (pinfunction "GND_14") (pintype "passive"))
      (node (ref "U4") (pin "15") (pinfunction "GND_15") (pintype "passive"))
      (node (ref "U4") (pin "2") (pinfunction "GND_2") (pintype "passive"))
      (node (ref "U4") (pin "25") (pinfunction "GND_25") (pintype "passive"))
      (node (ref "U4") (pin "26") (pinfunction "GND_26") (pintype "passive"))
      (node (ref "U4") (pin "27") (pinfunction "IOB#_27") (pintype "passive"))
      (node (ref "U4") (pin "31") (pinfunction "IOG#_31") (pintype "passive"))
      (node (ref "U4") (pin "33") (pinfunction "IOR#_33") (pintype "passive"))
      (node (ref "U4") (pin "39") (pinfunction "GND_39") (pintype "passive"))
      (node (ref "U4") (pin "40") (pinfunction "GND_40") (pintype "passive"))
      (node (ref "U4") (pin "49") (pinfunction "EP_49") (pintype "passive"))
      (node (ref "U5") (pin "A9") (pinfunction "VSS_A9") (pintype "passive"))
      (node (ref "U5") (pin "B1") (pinfunction "VSSQ_B1") (pintype "passive"))
      (node (ref "U5") (pin "B3") (pinfunction "VSS_B3") (pintype "passive"))
      (node (ref "U5") (pin "B9") (pinfunction "VSSQ_B9") (pintype "passive"))
      (node (ref "U5") (pin "D1") (pinfunction "VSSQ_D1") (pintype "passive"))
      (node (ref "U5") (pin "D8") (pinfunction "VSSQ_D8") (pintype "passive"))
      (node (ref "U5") (pin "E1") (pinfunction "VSS_E1") (pintype "passive"))
      (node (ref "U5") (pin "E2") (pinfunction "VSSQ_E2") (pintype "passive"))
      (node (ref "U5") (pin "E8") (pinfunction "VSSQ_E8") (pintype "passive"))
      (node (ref "U5") (pin "F9") (pinfunction "VSSQ_F9") (pintype "passive"))
      (node (ref "U5") (pin "G1") (pinfunction "VSSQ_G1") (pintype "passive"))
      (node (ref "U5") (pin "G8") (pinfunction "VSS_G8") (pintype "passive"))
      (node (ref "U5") (pin "G9") (pinfunction "VSSQ_G9") (pintype "passive"))
      (node (ref "U5") (pin "J2") (pinfunction "VSS_J2") (pintype "passive"))
      (node (ref "U5") (pin "J8") (pinfunction "VSS_J8") (pintype "passive"))
      (node (ref "U5") (pin "L2") (pinfunction "CS#_L2") (pintype "passive"))
      (node (ref "U5") (pin "M1") (pinfunction "VSS_M1") (pintype "passive"))
      (node (ref "U5") (pin "M9") (pinfunction "VSS_M9") (pintype "passive"))
      (node (ref "U5") (pin "P1") (pinfunction "VSS_P1") (pintype "passive"))
      (node (ref "U5") (pin "P9") (pinfunction "VSS_P9") (pintype "passive"))
      (node (ref "U5") (pin "T1") (pinfunction "VSS_T1") (pintype "passive"))
      (node (ref "U5") (pin "T9") (pinfunction "VSS_T9") (pintype "passive"))
      (node (ref "U69") (pin "15") (pinfunction "PGND_15") (pintype "passive"))
      (node (ref "U69") (pin "16") (pinfunction "PGND_16") (pintype "passive"))
      (node (ref "U69") (pin "17") (pinfunction "EP_17") (pintype "passive"))
      (node (ref "U69") (pin "6") (pinfunction "AGND_6") (pintype "passive"))
      (node (ref "U69") (pin "8") (pinfunction "DEF_8") (pintype "passive"))
      (node (ref "U7") (pin "11") (pinfunction "EPAD_11") (pintype "passive"))
      (node (ref "U7") (pin "4") (pinfunction "PGND_4") (pintype "passive"))
      (node (ref "U7") (pin "8") (pinfunction "GND_8") (pintype "passive"))
      (node (ref "U70") (pin "15") (pinfunction "PGND_15") (pintype "passive"))
      (node (ref "U70") (pin "16") (pinfunction "PGND_16") (pintype "passive"))
      (node (ref "U70") (pin "17") (pinfunction "EP_17") (pintype "passive"))
      (node (ref "U70") (pin "6") (pinfunction "AGND_6") (pintype "passive"))
      (node (ref "U70") (pin "8") (pinfunction "DEF_8") (pintype "passive"))
      (node (ref "U71") (pin "15") (pinfunction "EP_15") (pintype "passive"))
      (node (ref "U71") (pin "2") (pinfunction "GND_2") (pintype "passive"))
      (node (ref "U71") (pin "3") (pinfunction "GND_3") (pintype "passive"))
      (node (ref "U75") (pin "1") (pinfunction "1_1") (pintype "passive"))
      (node (ref "U76") (pin "1") (pinfunction "1_1") (pintype "passive"))
      (node (ref "U77") (pin "1") (pinfunction "K_1") (pintype "passive"))
      (node (ref "U8") (pin "A1") (pinfunction "GND_A1") (pintype "passive"))
      (node (ref "U8") (pin "A22") (pinfunction "GND_A22") (pintype "passive"))
      (node (ref "U8") (pin "A3") (pinfunction "IO_L1P_HSWAPEN_0_A3") (pintype "passive"))
      (node (ref "U8") (pin "AA13") (pinfunction "GND_AA13") (pintype "passive"))
      (node (ref "U8") (pin "AA17") (pinfunction "GND_AA17") (pintype "passive"))
      (node (ref "U8") (pin "AA5") (pinfunction "GND_AA5") (pintype "passive"))
      (node (ref "U8") (pin "AA9") (pinfunction "GND_AA9") (pintype "passive"))
      (node (ref "U8") (pin "AB1") (pinfunction "GND_AB1") (pintype "passive"))
      (node (ref "U8") (pin "AB22") (pinfunction "GND_AB22") (pintype "passive"))
      (node (ref "U8") (pin "B13") (pinfunction "GND_B13") (pintype "passive"))
      (node (ref "U8") (pin "B17") (pinfunction "GND_B17") (pintype "passive"))
      (node (ref "U8") (pin "B5") (pinfunction "GND_B5") (pintype "passive"))
      (node (ref "U8") (pin "B9") (pinfunction "GND_B9") (pintype "passive"))
      (node (ref "U8") (pin "D18") (pinfunction "GND_D18") (pintype "passive"))
      (node (ref "U8") (pin "D4") (pinfunction "GND_D4") (pintype "passive"))
      (node (ref "U8") (pin "E11") (pinfunction "GND_E11") (pintype "passive"))
      (node (ref "U8") (pin "E15") (pinfunction "GND_E15") (pintype "passive"))
      (node (ref "U8") (pin "E2") (pinfunction "GND_E2") (pintype "passive"))
      (node (ref "U8") (pin "E21") (pinfunction "GND_E21") (pintype "passive"))
      (node (ref "U8") (pin "E7") (pinfunction "GND_E7") (pintype "passive"))
      (node (ref "U8") (pin "G18") (pinfunction "GND_G18") (pintype "passive"))
      (node (ref "U8") (pin "G5") (pinfunction "GND_G5") (pintype "passive"))
      (node (ref "U8") (pin "H7") (pinfunction "GND_H7") (pintype "passive"))
      (node (ref "U8") (pin "J11") (pinfunction "GND_J11") (pintype "passive"))
      (node (ref "U8") (pin "J13") (pinfunction "GND_J13") (pintype "passive"))
      (node (ref "U8") (pin "J15") (pinfunction "GND_J15") (pintype "passive"))
      (node (ref "U8") (pin "J2") (pinfunction "GND_J2") (pintype "passive"))
      (node (ref "U8") (pin "J21") (pinfunction "GND_J21") (pintype "passive"))
      (node (ref "U8") (pin "J9") (pinfunction "GND_J9") (pintype "passive"))
      (node (ref "U8") (pin "K10") (pinfunction "GND_K10") (pintype "passive"))
      (node (ref "U8") (pin "K12") (pinfunction "GND_K12") (pintype "passive"))
      (node (ref "U8") (pin "K14") (pinfunction "GND_K14") (pintype "passive"))
      (node (ref "U8") (pin "L11") (pinfunction "GND_L11") (pintype "passive"))
      (node (ref "U8") (pin "L13") (pinfunction "GND_L13") (pintype "passive"))
      (node (ref "U8") (pin "L18") (pinfunction "GND_L18") (pintype "passive"))
      (node (ref "U8") (pin "L5") (pinfunction "GND_L5") (pintype "passive"))
      (node (ref "U8") (pin "L9") (pinfunction "GND_L9") (pintype "passive"))
      (node (ref "U8") (pin "M10") (pinfunction "GND_M10") (pintype "passive"))
      (node (ref "U8") (pin "M12") (pinfunction "GND_M12") (pintype "passive"))
      (node (ref "U8") (pin "M14") (pinfunction "GND_M14") (pintype "passive"))
      (node (ref "U8") (pin "N11") (pinfunction "GND_N11") (pintype "passive"))
      (node (ref "U8") (pin "N13") (pinfunction "GND_N13") (pintype "passive"))
      (node (ref "U8") (pin "N15") (pinfunction "SUSPEND_N15") (pintype "passive"))
      (node (ref "U8") (pin "N17") (pinfunction "GND_N17") (pintype "passive"))
      (node (ref "U8") (pin "N2") (pinfunction "GND_N2") (pintype "passive"))
      (node (ref "U8") (pin "N21") (pinfunction "GND_N21") (pintype "passive"))
      (node (ref "U8") (pin "N9") (pinfunction "GND_N9") (pintype "passive"))
      (node (ref "U8") (pin "P10") (pinfunction "GND_P10") (pintype "passive"))
      (node (ref "U8") (pin "P12") (pinfunction "GND_P12") (pintype "passive"))
      (node (ref "U8") (pin "P14") (pinfunction "GND_P14") (pintype "passive"))
      (node (ref "U8") (pin "R18") (pinfunction "GND_R18") (pintype "passive"))
      (node (ref "U8") (pin "R5") (pinfunction "GND_R5") (pintype "passive"))
      (node (ref "U8") (pin "U15") (pinfunction "IO_L13P_M1_2_U15") (pintype "passive"))
      (node (ref "U8") (pin "U2") (pinfunction "GND_U2") (pintype "passive"))
      (node (ref "U8") (pin "U21") (pinfunction "GND_U21") (pintype "passive"))
      (node (ref "U8") (pin "U7") (pinfunction "GND_U7") (pintype "passive"))
      (node (ref "U8") (pin "V10") (pinfunction "GND_V10") (pintype "passive"))
      (node (ref "U8") (pin "V14") (pinfunction "GND_V14") (pintype "passive"))
      (node (ref "U8") (pin "V4") (pinfunction "GND_V4") (pintype "passive"))
      (node (ref "U8") (pin "W16") (pinfunction "GND_W16") (pintype "passive"))
      (node (ref "U8") (pin "W19") (pinfunction "GND_W19") (pintype "passive"))
      (node (ref "U8") (pin "W7") (pinfunction "GND_W7") (pintype "passive"))
      (node (ref "U82") (pin "1") (pinfunction "1_1") (pintype "passive"))
      (node (ref "U82") (pin "2") (pinfunction "2_2") (pintype "passive"))
      (node (ref "U82") (pin "3") (pinfunction "3_3") (pintype "passive"))
      (node (ref "U82") (pin "4") (pinfunction "4_4") (pintype "passive"))
      (node (ref "U83") (pin "1") (pinfunction "1_1") (pintype "passive"))
      (node (ref "U83") (pin "2") (pinfunction "2_2") (pintype "passive"))
      (node (ref "U83") (pin "3") (pinfunction "3_3") (pintype "passive"))
      (node (ref "U83") (pin "4") (pinfunction "4_4") (pintype "passive"))
      (node (ref "U84") (pin "1") (pinfunction "1_1") (pintype "passive"))
      (node (ref "U84") (pin "2") (pinfunction "2_2") (pintype "passive"))
      (node (ref "U84") (pin "3") (pinfunction "3_3") (pintype "passive"))
      (node (ref "U84") (pin "4") (pinfunction "4_4") (pintype "passive"))
      (node (ref "U85") (pin "1") (pinfunction "1_1") (pintype "passive"))
      (node (ref "U85") (pin "2") (pinfunction "2_2") (pintype "passive"))
      (node (ref "U85") (pin "3") (pinfunction "3_3") (pintype "passive"))
      (node (ref "U85") (pin "4") (pinfunction "4_4") (pintype "passive"))
      (node (ref "USB2") (pin "11") (pinfunction "TMDSClockShield_11") (pintype "passive"))
      (node (ref "USB2") (pin "17") (pinfunction "DDC/CECGround_17") (pintype "passive"))
      (node (ref "USB2") (pin "2") (pinfunction "TMDSData2Shield_2") (pintype "passive"))
      (node (ref "USB2") (pin "20") (pinfunction "EH_20") (pintype "passive"))
      (node (ref "USB2") (pin "5") (pinfunction "TMDSData1Shield_5") (pintype "passive"))
      (node (ref "USB2") (pin "8") (pinfunction "TMDSData0Shield_8") (pintype "passive"))
      (node (ref "USB3") (pin "11") (pinfunction "TMDSClockShield_11") (pintype "passive"))
      (node (ref "USB3") (pin "17") (pinfunction "DDC/CECGround_17") (pintype "passive"))
      (node (ref "USB3") (pin "2") (pinfunction "TMDSData2Shield_2") (pintype "passive"))
      (node (ref "USB3") (pin "20") (pinfunction "EH_20") (pintype "passive"))
      (node (ref "USB3") (pin "5") (pinfunction "TMDSData1Shield_5") (pintype "passive"))
      (node (ref "USB3") (pin "8") (pinfunction "TMDSData0Shield_8") (pintype "passive"))
      (node (ref "X1") (pin "2") (pinfunction "GND_2") (pintype "passive"))
      (node (ref "X2") (pin "2") (pinfunction "GND_2") (pintype "passive"))
    )
    (net (code "395") (name "Net-(C201-Pad2)") (class "Default")
      (node (ref "C201") (pin "2") (pinfunction "2_2") (pintype "passive"))
      (node (ref "R140") (pin "1") (pinfunction "1_1") (pintype "passive"))
    )
    (net (code "396") (name "Net-(C202-Pad2)") (class "Default")
      (node (ref "C202") (pin "2") (pinfunction "2_2") (pintype "passive"))
      (node (ref "L26") (pin "1") (pinfunction "1_1") (pintype "passive"))
      (node (ref "U71") (pin "11") (pinfunction "PH_11") (pintype "passive"))
      (node (ref "U71") (pin "12") (pinfunction "PH_12") (pintype "passive"))
    )
    (net (code "397") (name "Net-(C206-Pad2)") (class "Default")
      (node (ref "C206") (pin "2") (pinfunction "2_2") (pintype "passive"))
      (node (ref "L26") (pin "2") (pinfunction "2_2") (pintype "passive"))
      (node (ref "L27") (pin "1") (pinfunction "1_1") (pintype "passive"))
      (node (ref "R142") (pin "2") (pinfunction "2_2") (pintype "passive"))
      (node (ref "R146") (pin "2") (pinfunction "2_2") (pintype "passive"))
    )
    (net (code "398") (name "Net-(C216-Pad2)") (class "Default")
      (node (ref "C216") (pin "2") (pinfunction "2_2") (pintype "passive"))
      (node (ref "L32") (pin "2") (pinfunction "2_2") (pintype "passive"))
      (node (ref "L33") (pin "1") (pinfunction "1_1") (pintype "passive"))
    )
    (net (code "399") (name "Net-(D5-K)") (class "Default")
      (node (ref "D5") (pin "1") (pinfunction "K_1") (pintype "passive"))
      (node (ref "U18") (pin "1") (pinfunction "1_1") (pintype "passive"))
    )
    (net (code "400") (name "Net-(D11-K)") (class "Default")
      (node (ref "D11") (pin "1") (pinfunction "K_1") (pintype "passive"))
      (node (ref "U24") (pin "1") (pinfunction "1_1") (pintype "passive"))
    )
    (net (code "401") (name "Net-(D17-A)") (class "Default")
      (node (ref "D17") (pin "2") (pinfunction "A_2") (pintype "passive"))
      (node (ref "F1") (pin "1") (pinfunction "1_1") (pintype "passive"))
    )
    (net (code "402") (name "Net-(D20-C)") (class "Default")
      (node (ref "D20") (pin "1") (pinfunction "C_1") (pintype "passive"))
      (node (ref "DC3") (pin "3") (pinfunction "3_3") (pintype "passive"))
      (node (ref "F2") (pin "2") (pinfunction "2_2") (pintype "passive"))
    )
    (net (code "403") (name "Net-(D22-A-Pad1)") (class "Default")
      (node (ref "D22") (pin "1") (pinfunction "A_1") (pintype "passive"))
      (node (ref "R110") (pin "1") (pinfunction "1_1") (pintype "passive"))
    )
    (net (code "404") (name "Net-(D22-A-Pad2)") (class "Default")
      (node (ref "D22") (pin "2") (pinfunction "A_2") (pintype "passive"))
      (node (ref "R111") (pin "2") (pinfunction "2_2") (pintype "passive"))
    )
    (net (code "405") (name "Net-(D23-A-Pad1)") (class "Default")
      (node (ref "D23") (pin "1") (pinfunction "A_1") (pintype "passive"))
      (node (ref "R106") (pin "1") (pinfunction "1_1") (pintype "passive"))
    )
    (net (code "406") (name "Net-(D23-A-Pad2)") (class "Default")
      (node (ref "D23") (pin "2") (pinfunction "A_2") (pintype "passive"))
      (node (ref "R107") (pin "2") (pinfunction "2_2") (pintype "passive"))
    )
    (net (code "407") (name "Net-(D24-A-Pad1)") (class "Default")
      (node (ref "D24") (pin "1") (pinfunction "A_1") (pintype "passive"))
      (node (ref "R90") (pin "1") (pinfunction "1_1") (pintype "passive"))
    )
    (net (code "408") (name "Net-(D24-A-Pad2)") (class "Default")
      (node (ref "D24") (pin "2") (pinfunction "A_2") (pintype "passive"))
      (node (ref "R91") (pin "2") (pinfunction "2_2") (pintype "passive"))
    )
    (net (code "409") (name "Net-(D25-A-Pad1)") (class "Default")
      (node (ref "D25") (pin "1") (pinfunction "A_1") (pintype "passive"))
      (node (ref "R94") (pin "1") (pinfunction "1_1") (pintype "passive"))
    )
    (net (code "410") (name "Net-(D25-A-Pad2)") (class "Default")
      (node (ref "D25") (pin "2") (pinfunction "A_2") (pintype "passive"))
      (node (ref "R95") (pin "2") (pinfunction "2_2") (pintype "passive"))
    )
    (net (code "411") (name "Net-(L22-Pad1)") (class "Default")
      (node (ref "L22") (pin "1") (pinfunction "1_1") (pintype "passive"))
      (node (ref "U69") (pin "1") (pinfunction "SW_1") (pintype "passive"))
      (node (ref "U69") (pin "2") (pinfunction "SW_2") (pintype "passive"))
      (node (ref "U69") (pin "3") (pinfunction "SW_3") (pintype "passive"))
    )
    (net (code "412") (name "Net-(L24-Pad1)") (class "Default")
      (node (ref "L24") (pin "1") (pinfunction "1_1") (pintype "passive"))
      (node (ref "U70") (pin "1") (pinfunction "SW_1") (pintype "passive"))
      (node (ref "U70") (pin "2") (pinfunction "SW_2") (pintype "passive"))
      (node (ref "U70") (pin "3") (pinfunction "SW_3") (pintype "passive"))
    )
    (net (code "413") (name "Net-(LED1-K-Pad1)") (class "Default")
      (node (ref "LED1") (pin "1") (pinfunction "K_1") (pintype "passive"))
      (node (ref "R185") (pin "2") (pinfunction "2_2") (pintype "passive"))
    )
    (net (code "414") (name "Net-(Q5-D)") (class "Default")
      (node (ref "Q5") (pin "3") (pinfunction "D_3") (pintype "passive"))
      (node (ref "Q6") (pin "1") (pinfunction "G_1") (pintype "passive"))
      (node (ref "U26") (pin "1") (pinfunction "1_1") (pintype "passive"))
    )
    (net (code "415") (name "Net-(Q10-G)") (class "Default")
      (node (ref "Q10") (pin "1") (pinfunction "G_1") (pintype "passive"))
      (node (ref "Q9") (pin "3") (pinfunction "D_3") (pintype "passive"))
      (node (ref "U31") (pin "1") (pinfunction "1_1") (pintype "passive"))
    )
    (net (code "416") (name "Net-(Q13-D)") (class "Default")
      (node (ref "Q13") (pin "3") (pinfunction "D_3") (pintype "passive"))
      (node (ref "U78") (pin "1") (pinfunction "K_1") (pintype "passive"))
    )
    (net (code "417") (name "Net-(Q13-G)") (class "Default")
      (node (ref "Q13") (pin "1") (pinfunction "G_1") (pintype "passive"))
      (node (ref "R133") (pin "1") (pinfunction "1_1") (pintype "passive"))
      (node (ref "U69") (pin "4") (pinfunction "PG_4") (pintype "passive"))
    )
    (net (code "418") (name "Net-(Q14-D)") (class "Default")
      (node (ref "Q14") (pin "3") (pinfunction "D_3") (pintype "passive"))
      (node (ref "U79") (pin "1") (pinfunction "K_1") (pintype "passive"))
    )
    (net (code "419") (name "Net-(Q14-G)") (class "Default")
      (node (ref "Q14") (pin "1") (pinfunction "G_1") (pintype "passive"))
      (node (ref "R136") (pin "1") (pinfunction "1_1") (pintype "passive"))
      (node (ref "U70") (pin "4") (pinfunction "PG_4") (pintype "passive"))
    )
    (net (code "420") (name "Net-(Q15-D)") (class "Default")
      (node (ref "Q15") (pin "3") (pinfunction "D_3") (pintype "passive"))
      (node (ref "U80") (pin "1") (pinfunction "K_1") (pintype "passive"))
    )
    (net (code "421") (name "Net-(Q15-G)") (class "Default")
      (node (ref "Q15") (pin "1") (pinfunction "G_1") (pintype "passive"))
      (node (ref "R146") (pin "1") (pinfunction "1_1") (pintype "passive"))
      (node (ref "U71") (pin "14") (pinfunction "PWRGD_14") (pintype "passive"))
    )
    (net (code "422") (name "Net-(Q16-D)") (class "Default")
      (node (ref "Q16") (pin "3") (pinfunction "D_3") (pintype "passive"))
      (node (ref "U81") (pin "1") (pinfunction "K_1") (pintype "passive"))
    )
    (net (code "423") (name "Net-(R78-Pad2)") (class "Default")
      (node (ref "R78") (pin "2") (pinfunction "2_2") (pintype "passive"))
      (node (ref "R80") (pin "2") (pinfunction "2_2") (pintype "passive"))
    )
    (net (code "424") (name "Net-(R196-Pad2)") (class "Default")
      (node (ref "R196") (pin "2") (pinfunction "2_2") (pintype "passive"))
      (node (ref "SW3") (pin "2") (pinfunction "2_2") (pintype "passive"))
    )
    (net (code "425") (name "Net-(R197-Pad2)") (class "Default")
      (node (ref "R197") (pin "2") (pinfunction "2_2") (pintype "passive"))
      (node (ref "SW4") (pin "2") (pinfunction "2_2") (pintype "passive"))
    )
    (net (code "426") (name "Net-(R198-Pad2)") (class "Default")
      (node (ref "R198") (pin "2") (pinfunction "2_2") (pintype "passive"))
      (node (ref "SW5") (pin "2") (pinfunction "2_2") (pintype "passive"))
    )
    (net (code "427") (name "Net-(U2-PDO#)") (class "Default")
      (node (ref "U2") (pin "8") (pinfunction "SCDT_8") (pintype "passive"))
      (node (ref "U2") (pin "9") (pinfunction "PDO#_9") (pintype "passive"))
    )
    (net (code "428") (name "Net-(U3-DKEN)") (class "Default")
      (node (ref "R102") (pin "1") (pinfunction "1_1") (pintype "passive"))
      (node (ref "R103") (pin "2") (pinfunction "2_2") (pintype "passive"))
      (node (ref "U3") (pin "35") (pinfunction "DKEN_35") (pintype "passive"))
    )
    (net (code "429") (name "Net-(U3-TFADJ)") (class "Default")
      (node (ref "R98") (pin "1") (pinfunction "1_1") (pintype "passive"))
      (node (ref "U3") (pin "19") (pinfunction "TFADJ_19") (pintype "passive"))
    )
    (net (code "430") (name "Net-(U3-VREF)") (class "Default")
      (node (ref "U101") (pin "1") (pinfunction "1_1") (pintype "passive"))
      (node (ref "U102") (pin "2") (pinfunction "2_2") (pintype "passive"))
      (node (ref "U3") (pin "3") (pinfunction "VREF_3") (pintype "passive"))
    )
    (net (code "431") (name "Net-(U4-COMP)") (class "Default")
      (node (ref "C110") (pin "1") (pinfunction "1_1") (pintype "passive"))
      (node (ref "U4") (pin "35") (pinfunction "COMP_35") (pintype "passive"))
    )
    (net (code "432") (name "Net-(U4-RSET)") (class "Default")
      (node (ref "R80") (pin "1") (pinfunction "1_1") (pintype "passive"))
      (node (ref "U4") (pin "37") (pinfunction "RSET_37") (pintype "passive"))
    )
    (net (code "433") (name "Net-(U5-ZQ)") (class "Default")
      (node (ref "R26") (pin "1") (pinfunction "1_1") (pintype "passive"))
      (node (ref "U5") (pin "L8") (pinfunction "ZQ_L8") (pintype "passive"))
    )
    (net (code "434") (name "Net-(U7-EN)") (class "Default")
      (node (ref "L1") (pin "1") (pinfunction "1_1") (pintype "passive"))
      (node (ref "U7") (pin "10") (pinfunction "VIN_10") (pintype "passive"))
      (node (ref "U7") (pin "7") (pinfunction "EN_7") (pintype "passive"))
    )
    (net (code "435") (name "Net-(U7-REFIN)") (class "Default")
      (node (ref "C119") (pin "1") (pinfunction "1_1") (pintype "passive"))
      (node (ref "R96") (pin "2") (pinfunction "2_2") (pintype "passive"))
      (node (ref "R97") (pin "2") (pinfunction "2_2") (pintype "passive"))
      (node (ref "U7") (pin "1") (pinfunction "REFIN_1") (pintype "passive"))
    )
    (net (code "436") (name "Net-(U8C-IO_L1P_CCLK_2)") (class "Default")
      (node (ref "R11") (pin "2") (pinfunction "2_2") (pintype "passive"))
      (node (ref "U8") (pin "Y21") (pinfunction "IO_L1P_CCLK_2_Y21") (pintype "passive"))
    )
    (net (code "437") (name "Net-(U8C-IO_L3N_MOSI_CSI_B_MISO0_2)") (class "Default")
      (node (ref "R6") (pin "2") (pinfunction "2_2") (pintype "passive"))
      (node (ref "U8") (pin "AB20") (pinfunction "IO_L3N_MOSI_CSI_B_MISO0_2_AB20") (pintype "passive"))
    )
    (net (code "438") (name "Net-(U8C-IO_L3P_D0_DIN_MISO_MISO1_2)") (class "Default")
      (node (ref "R7") (pin "2") (pinfunction "2_2") (pintype "passive"))
      (node (ref "U8") (pin "AA20") (pinfunction "IO_L3P_D0_DIN_MISO_MISO1_2_AA20") (pintype "passive"))
    )
    (net (code "439") (name "Net-(U8C-IO_L12N_D2_MISO3_2)") (class "Default")
      (node (ref "R13") (pin "2") (pinfunction "2_2") (pintype "passive"))
      (node (ref "U8") (pin "U13") (pinfunction "IO_L12N_D2_MISO3_2_U13") (pintype "passive"))
    )
    (net (code "440") (name "Net-(U8C-IO_L12P_D1_MISO2_2)") (class "Default")
      (node (ref "R14") (pin "2") (pinfunction "2_2") (pintype "passive"))
      (node (ref "U8") (pin "U14") (pinfunction "IO_L12P_D1_MISO2_2_U14") (pintype "passive"))
    )
    (net (code "441") (name "Net-(U8C-IO_L65N_CSO_B_2)") (class "Default")
      (node (ref "R12") (pin "2") (pinfunction "2_2") (pintype "passive"))
      (node (ref "U8") (pin "T5") (pinfunction "IO_L65N_CSO_B_2_T5") (pintype "passive"))
    )
    (net (code "442") (name "Net-(U8C-IO_L65P_INIT_B_2)") (class "Default")
      (node (ref "C3") (pin "2") (pinfunction "2_2") (pintype "passive"))
      (node (ref "R23") (pin "1") (pinfunction "1_1") (pintype "passive"))
      (node (ref "U8") (pin "T6") (pinfunction "IO_L65P_INIT_B_2_T6") (pintype "passive"))
    )
    (net (code "443") (name "Net-(U8E-PROGRAM_B_2)") (class "Default")
      (node (ref "C4") (pin "2") (pinfunction "2_2") (pintype "passive"))
      (node (ref "R5") (pin "1") (pinfunction "1_1") (pintype "passive"))
      (node (ref "U8") (pin "AA1") (pinfunction "PROGRAM_B_2_AA1") (pintype "passive"))
    )
    (net (code "444") (name "Net-(U12-ZQ)") (class "Default")
      (node (ref "R53") (pin "1") (pinfunction "1_1") (pintype "passive"))
      (node (ref "U12") (pin "L8") (pinfunction "ZQ_L8") (pintype "passive"))
    )
    (net (code "445") (name "Net-(U69-FB)") (class "Default")
      (node (ref "R134") (pin "2") (pinfunction "2_2") (pintype "passive"))
      (node (ref "R135") (pin "1") (pinfunction "1_1") (pintype "passive"))
      (node (ref "U69") (pin "5") (pinfunction "FB_5") (pintype "passive"))
    )
    (net (code "446") (name "Net-(U69-FSW)") (class "Default")
      (node (ref "C194") (pin "2") (pinfunction "2_2") (pintype "passive"))
      (node (ref "L22") (pin "2") (pinfunction "2_2") (pintype "passive"))
      (node (ref "L23") (pin "1") (pinfunction "1_1") (pintype "passive"))
      (node (ref "R133") (pin "2") (pinfunction "2_2") (pintype "passive"))
      (node (ref "R135") (pin "2") (pinfunction "2_2") (pintype "passive"))
      (node (ref "U69") (pin "14") (pinfunction "VOS_14") (pintype "passive"))
      (node (ref "U69") (pin "7") (pinfunction "FSW_7") (pintype "passive"))
    )
    (net (code "447") (name "Net-(U69-SS{slash}TR)") (class "Default")
      (node (ref "C195") (pin "2") (pinfunction "2_2") (pintype "passive"))
      (node (ref "U69") (pin "9") (pinfunction "SS/TR_9") (pintype "passive"))
    )
    (net (code "448") (name "Net-(U70-FB)") (class "Default")
      (node (ref "R137") (pin "2") (pinfunction "2_2") (pintype "passive"))
      (node (ref "R138") (pin "1") (pinfunction "1_1") (pintype "passive"))
      (node (ref "U70") (pin "5") (pinfunction "FB_5") (pintype "passive"))
    )
    (net (code "449") (name "Net-(U70-FSW)") (class "Default")
      (node (ref "C197") (pin "2") (pinfunction "2_2") (pintype "passive"))
      (node (ref "L24") (pin "2") (pinfunction "2_2") (pintype "passive"))
      (node (ref "L25") (pin "1") (pinfunction "1_1") (pintype "passive"))
      (node (ref "R136") (pin "2") (pinfunction "2_2") (pintype "passive"))
      (node (ref "R138") (pin "2") (pinfunction "2_2") (pintype "passive"))
      (node (ref "U70") (pin "14") (pinfunction "VOS_14") (pintype "passive"))
      (node (ref "U70") (pin "7") (pinfunction "FSW_7") (pintype "passive"))
    )
    (net (code "450") (name "Net-(U70-SS{slash}TR)") (class "Default")
      (node (ref "C198") (pin "2") (pinfunction "2_2") (pintype "passive"))
      (node (ref "U70") (pin "9") (pinfunction "SS/TR_9") (pintype "passive"))
    )
    (net (code "451") (name "Net-(U71-BOOT)") (class "Default")
      (node (ref "C202") (pin "1") (pinfunction "1_1") (pintype "passive"))
      (node (ref "U71") (pin "13") (pinfunction "BOOT_13") (pintype "passive"))
    )
    (net (code "452") (name "Net-(U71-COMP)") (class "Default")
      (node (ref "R140") (pin "2") (pinfunction "2_2") (pintype "passive"))
      (node (ref "U71") (pin "8") (pinfunction "COMP_8") (pintype "passive"))
    )
    (net (code "453") (name "Net-(U71-RT{slash}CLK)") (class "Default")
      (node (ref "R139") (pin "2") (pinfunction "2_2") (pintype "passive"))
      (node (ref "U71") (pin "1") (pinfunction "RT/CLK_1") (pintype "passive"))
    )
    (net (code "454") (name "Net-(U71-SS{slash}TR)") (class "Default")
      (node (ref "C200") (pin "2") (pinfunction "2_2") (pintype "passive"))
      (node (ref "U71") (pin "9") (pinfunction "SS/TR_9") (pintype "passive"))
    )
    (net (code "455") (name "Net-(U71-VSENSE)") (class "Default")
      (node (ref "R141") (pin "2") (pinfunction "2_2") (pintype "passive"))
      (node (ref "R142") (pin "1") (pinfunction "1_1") (pintype "passive"))
      (node (ref "U71") (pin "7") (pinfunction "VSENSE_7") (pintype "passive"))
    )
    (net (code "456") (name "Net-(U77-A)") (class "Default")
      (node (ref "R143") (pin "1") (pinfunction "1_1") (pintype "passive"))
      (node (ref "U77") (pin "2") (pinfunction "A_2") (pintype "passive"))
    )
    (net (code "457") (name "Net-(U78-A)") (class "Default")
      (node (ref "R144") (pin "1") (pinfunction "1_1") (pintype "passive"))
      (node (ref "U78") (pin "2") (pinfunction "A_2") (pintype "passive"))
    )
    (net (code "458") (name "Net-(U79-A)") (class "Default")
      (node (ref "R145") (pin "1") (pinfunction "1_1") (pintype "passive"))
      (node (ref "U79") (pin "2") (pinfunction "A_2") (pintype "passive"))
    )
    (net (code "459") (name "Net-(U80-A)") (class "Default")
      (node (ref "R147") (pin "1") (pinfunction "1_1") (pintype "passive"))
      (node (ref "U80") (pin "2") (pinfunction "A_2") (pintype "passive"))
    )
    (net (code "460") (name "Net-(U81-A)") (class "Default")
      (node (ref "R148") (pin "1") (pinfunction "1_1") (pintype "passive"))
      (node (ref "U81") (pin "2") (pinfunction "A_2") (pintype "passive"))
    )
    (net (code "461") (name "Net-(U100-Y)") (class "Default")
      (node (ref "LED1") (pin "3") (pinfunction "A_3") (pintype "passive"))
      (node (ref "R154") (pin "2") (pinfunction "2_2") (pintype "passive"))
      (node (ref "U100") (pin "4") (pinfunction "Y_4") (pintype "passive"))
    )
    (net (code "462") (name "Net-(X1-Tri-state)") (class "Default")
      (node (ref "C147") (pin "2") (pinfunction "2_2") (pintype "passive"))
      (node (ref "U22") (pin "2") (pinfunction "2_2") (pintype "passive"))
      (node (ref "X1") (pin "1") (pinfunction "Tri-state_1") (pintype "passive"))
      (node (ref "X1") (pin "4") (pinfunction "VDD_4") (pintype "passive"))
    )
    (net (code "463") (name "Net-(X2-OE)") (class "Default")
      (node (ref "C148") (pin "2") (pinfunction "2_2") (pintype "passive"))
      (node (ref "U23") (pin "2") (pinfunction "2_2") (pintype "passive"))
      (node (ref "X2") (pin "1") (pinfunction "OE_1") (pintype "passive"))
      (node (ref "X2") (pin "4") (pinfunction "VDD_4") (pintype "passive"))
    )
    (net (code "464") (name "VCC_1V2") (class "Default")
      (node (ref "C10") (pin "2") (pinfunction "2_2") (pintype "passive"))
      (node (ref "C11") (pin "2") (pinfunction "2_2") (pintype "passive"))
      (node (ref "C12") (pin "2") (pinfunction "2_2") (pintype "passive"))
      (node (ref "C13") (pin "2") (pinfunction "2_2") (pintype "passive"))
      (node (ref "C14") (pin "2") (pinfunction "2_2") (pintype "passive"))
      (node (ref "C15") (pin "2") (pinfunction "2_2") (pintype "passive"))
      (node (ref "C16") (pin "2") (pinfunction "2_2") (pintype "passive"))
      (node (ref "C207") (pin "2") (pinfunction "2_2") (pintype "passive"))
      (node (ref "C293") (pin "2") (pinfunction "2_2") (pintype "passive"))
      (node (ref "C294") (pin "2") (pinfunction "2_2") (pintype "passive"))
      (node (ref "C295") (pin "2") (pinfunction "2_2") (pintype "passive"))
      (node (ref "C296") (pin "2") (pinfunction "2_2") (pintype "passive"))
      (node (ref "C297") (pin "2") (pinfunction "2_2") (pintype "passive"))
      (node (ref "C298") (pin "2") (pinfunction "2_2") (pintype "passive"))
      (node (ref "C299") (pin "2") (pinfunction "2_2") (pintype "passive"))
      (node (ref "C300") (pin "2") (pinfunction "2_2") (pintype "passive"))
      (node (ref "C301") (pin "2") (pinfunction "2_2") (pintype "passive"))
      (node (ref "C302") (pin "2") (pinfunction "2_2") (pintype "passive"))
      (node (ref "C5") (pin "2") (pinfunction "2_2") (pintype "passive"))
      (node (ref "C6") (pin "2") (pinfunction "2_2") (pintype "passive"))
      (node (ref "C7") (pin "2") (pinfunction "2_2") (pintype "passive"))
      (node (ref "C8") (pin "2") (pinfunction "2_2") (pintype "passive"))
      (node (ref "C9") (pin "2") (pinfunction "2_2") (pintype "passive"))
      (node (ref "L27") (pin "2") (pinfunction "2_2") (pintype "passive"))
      (node (ref "U74") (pin "1") (pinfunction "1_1") (pintype "passive"))
      (node (ref "U8") (pin "J10") (pinfunction "VCCINT_J10") (pintype "passive"))
      (node (ref "U8") (pin "J12") (pinfunction "VCCINT_J12") (pintype "passive"))
      (node (ref "U8") (pin "J14") (pinfunction "VCCINT_J14") (pintype "passive"))
      (node (ref "U8") (pin "J8") (pinfunction "VCCINT_J8") (pintype "passive"))
      (node (ref "U8") (pin "K11") (pinfunction "VCCINT_K11") (pintype "passive"))
      (node (ref "U8") (pin "K13") (pinfunction "VCCINT_K13") (pintype "passive"))
      (node (ref "U8") (pin "K9") (pinfunction "VCCINT_K9") (pintype "passive"))
      (node (ref "U8") (pin "L10") (pinfunction "VCCINT_L10") (pintype "passive"))
      (node (ref "U8") (pin "L12") (pinfunction "VCCINT_L12") (pintype "passive"))
      (node (ref "U8") (pin "L14") (pinfunction "VCCINT_L14") (pintype "passive"))
      (node (ref "U8") (pin "M11") (pinfunction "VCCINT_M11") (pintype "passive"))
      (node (ref "U8") (pin "M13") (pinfunction "VCCINT_M13") (pintype "passive"))
      (node (ref "U8") (pin "M9") (pinfunction "VCCINT_M9") (pintype "passive"))
      (node (ref "U8") (pin "N10") (pinfunction "VCCINT_N10") (pintype "passive"))
      (node (ref "U8") (pin "N12") (pinfunction "VCCINT_N12") (pintype "passive"))
      (node (ref "U8") (pin "N14") (pinfunction "VCCINT_N14") (pintype "passive"))
      (node (ref "U8") (pin "P11") (pinfunction "VCCINT_P11") (pintype "passive"))
      (node (ref "U8") (pin "P13") (pinfunction "VCCINT_P13") (pintype "passive"))
      (node (ref "U8") (pin "P9") (pinfunction "VCCINT_P9") (pintype "passive"))
      (node (ref "U8") (pin "R14") (pinfunction "VCCINT_R14") (pintype "passive"))
    )
    (net (code "465") (name "VCC_1V5") (class "Default")
      (node (ref "C120") (pin "2") (pinfunction "2_2") (pintype "passive"))
      (node (ref "C123") (pin "2") (pinfunction "2_2") (pintype "passive"))
      (node (ref "C311") (pin "2") (pinfunction "2_2") (pintype "passive"))
      (node (ref "C312") (pin "2") (pinfunction "2_2") (pintype "passive"))
      (node (ref "C42") (pin "2") (pinfunction "2_2") (pintype "passive"))
      (node (ref "C43") (pin "2") (pinfunction "2_2") (pintype "passive"))
      (node (ref "C44") (pin "2") (pinfunction "2_2") (pintype "passive"))
      (node (ref "C45") (pin "2") (pinfunction "2_2") (pintype "passive"))
      (node (ref "C46") (pin "2") (pinfunction "2_2") (pintype "passive"))
      (node (ref "C47") (pin "2") (pinfunction "2_2") (pintype "passive"))
      (node (ref "C48") (pin "2") (pinfunction "2_2") (pintype "passive"))
      (node (ref "C49") (pin "2") (pinfunction "2_2") (pintype "passive"))
      (node (ref "C50") (pin "2") (pinfunction "2_2") (pintype "passive"))
      (node (ref "C51") (pin "2") (pinfunction "2_2") (pintype "passive"))
      (node (ref "C52") (pin "2") (pinfunction "2_2") (pintype "passive"))
      (node (ref "C53") (pin "2") (pinfunction "2_2") (pintype "passive"))
      (node (ref "C66") (pin "2") (pinfunction "2_2") (pintype "passive"))
      (node (ref "C67") (pin "2") (pinfunction "2_2") (pintype "passive"))
      (node (ref "C68") (pin "2") (pinfunction "2_2") (pintype "passive"))
      (node (ref "C69") (pin "2") (pinfunction "2_2") (pintype "passive"))
      (node (ref "C70") (pin "2") (pinfunction "2_2") (pintype "passive"))
      (node (ref "C71") (pin "2") (pinfunction "2_2") (pintype "passive"))
      (node (ref "C72") (pin "2") (pinfunction "2_2") (pintype "passive"))
      (node (ref "C73") (pin "2") (pinfunction "2_2") (pintype "passive"))
      (node (ref "C74") (pin "2") (pinfunction "2_2") (pintype "passive"))
      (node (ref "C75") (pin "2") (pinfunction "2_2") (pintype "passive"))
      (node (ref "C76") (pin "2") (pinfunction "2_2") (pintype "passive"))
      (node (ref "C77") (pin "2") (pinfunction "2_2") (pintype "passive"))
      (node (ref "L25") (pin "2") (pinfunction "2_2") (pintype "passive"))
      (node (ref "L34") (pin "1") (pinfunction "1_1") (pintype "passive"))
      (node (ref "R96") (pin "1") (pinfunction "1_1") (pintype "passive"))
      (node (ref "U7") (pin "2") (pinfunction "VLDOIN_2") (pintype "passive"))
      (node (ref "U73") (pin "1") (pinfunction "1_1") (pintype "passive"))
      (node (ref "U8") (pin "C2") (pinfunction "VCCO_3_C2") (pintype "passive"))
      (node (ref "U8") (pin "C21") (pinfunction "VCCO_1_C21") (pintype "passive"))
      (node (ref "U8") (pin "E19") (pinfunction "VCCO_1_E19") (pintype "passive"))
      (node (ref "U8") (pin "F4") (pinfunction "VCCO_3_F4") (pintype "passive"))
      (node (ref "U8") (pin "F6") (pinfunction "VCCO_3_F6") (pintype "passive"))
      (node (ref "U8") (pin "G2") (pinfunction "VCCO_3_G2") (pintype "passive"))
      (node (ref "U8") (pin "G21") (pinfunction "VCCO_1_G21") (pintype "passive"))
      (node (ref "U8") (pin "J18") (pinfunction "VCCO_1_J18") (pintype "passive"))
      (node (ref "U8") (pin "J5") (pinfunction "VCCO_3_J5") (pintype "passive"))
      (node (ref "U8") (pin "L16") (pinfunction "VCCO_1_L16") (pintype "passive"))
      (node (ref "U8") (pin "L2") (pinfunction "VCCO_3_L2") (pintype "passive"))
      (node (ref "U8") (pin "L21") (pinfunction "VCCO_1_L21") (pintype "passive"))
      (node (ref "U8") (pin "L7") (pinfunction "VCCO_3_L7") (pintype "passive"))
      (node (ref "U8") (pin "N18") (pinfunction "VCCO_1_N18") (pintype "passive"))
      (node (ref "U8") (pin "N5") (pinfunction "VCCO_3_N5") (pintype "passive"))
      (node (ref "U8") (pin "R2") (pinfunction "VCCO_3_R2") (pintype "passive"))
      (node (ref "U8") (pin "R21") (pinfunction "VCCO_1_R21") (pintype "passive"))
      (node (ref "U8") (pin "U18") (pinfunction "VCCO_1_U18") (pintype "passive"))
      (node (ref "U8") (pin "U5") (pinfunction "VCCO_3_U5") (pintype "passive"))
      (node (ref "U8") (pin "W2") (pinfunction "VCCO_3_W2") (pintype "passive"))
      (node (ref "U8") (pin "W21") (pinfunction "VCCO_1_W21") (pintype "passive"))
    )
    (net (code "466") (name "VCC_3V3") (class "Default")
      (node (ref "C125") (pin "2") (pinfunction "2_2") (pintype "passive"))
      (node (ref "C150") (pin "2") (pinfunction "2_2") (pintype "passive"))
      (node (ref "C204") (pin "2") (pinfunction "2_2") (pintype "passive"))
      (node (ref "C208") (pin "2") (pinfunction "2_2") (pintype "passive"))
      (node (ref "C210") (pin "2") (pinfunction "2_2") (pintype "passive"))
      (node (ref "C211") (pin "2") (pinfunction "2_2") (pintype "passive"))
      (node (ref "C213") (pin "2") (pinfunction "2_2") (pintype "passive"))
      (node (ref "C215") (pin "2") (pinfunction "2_2") (pintype "passive"))
      (node (ref "L1") (pin "2") (pinfunction "2_2") (pintype "passive"))
      (node (ref "L23") (pin "2") (pinfunction "2_2") (pintype "passive"))
      (node (ref "L28") (pin "1") (pinfunction "1_1") (pintype "passive"))
      (node (ref "L29") (pin "1") (pinfunction "1_1") (pintype "passive"))
      (node (ref "L30") (pin "1") (pinfunction "1_1") (pintype "passive"))
      (node (ref "L31") (pin "1") (pinfunction "1_1") (pintype "passive"))
      (node (ref "L32") (pin "1") (pinfunction "1_1") (pintype "passive"))
      (node (ref "Q9") (pin "1") (pinfunction "G_1") (pintype "passive"))
      (node (ref "U19") (pin "8") (pinfunction "VCC_8") (pintype "passive"))
      (node (ref "U26") (pin "2") (pinfunction "2_2") (pintype "passive"))
      (node (ref "U27") (pin "2") (pinfunction "2_2") (pintype "passive"))
      (node (ref "U33") (pin "8") (pinfunction "VCC_8") (pintype "passive"))
      (node (ref "U72") (pin "1") (pinfunction "1_1") (pintype "passive"))
    )
    (net (code "467") (name "VCC_5V") (class "Default")
      (node (ref "C153") (pin "1") (pinfunction "1_1") (pintype "passive"))
      (node (ref "C192") (pin "1") (pinfunction "1_1") (pintype "passive"))
      (node (ref "C193") (pin "2") (pinfunction "2_2") (pintype "passive"))
      (node (ref "C196") (pin "2") (pinfunction "2_2") (pintype "passive"))
      (node (ref "C199") (pin "2") (pinfunction "2_2") (pintype "passive"))
      (node (ref "C217") (pin "1") (pinfunction "1_1") (pintype "passive"))
      (node (ref "C218") (pin "1") (pinfunction "1_1") (pintype "passive"))
      (node (ref "C219") (pin "1") (pinfunction "1_1") (pintype "passive"))
      (node (ref "D11") (pin "2") (pinfunction "A_2") (pintype "passive"))
      (node (ref "D12") (pin "5") (pinfunction "5_5") (pintype "passive"))
      (node (ref "D16") (pin "5") (pinfunction "5_5") (pintype "passive"))
      (node (ref "D17") (pin "1") (pinfunction "K_1") (pintype "passive"))
      (node (ref "D22") (pin "3") (pinfunction "C_3") (pintype "passive"))
      (node (ref "D23") (pin "3") (pinfunction "C_3") (pintype "passive"))
      (node (ref "D24") (pin "3") (pinfunction "C_3") (pintype "passive"))
      (node (ref "D25") (pin "3") (pinfunction "C_3") (pintype "passive"))
      (node (ref "D5") (pin "2") (pinfunction "A_2") (pintype "passive"))
      (node (ref "D6") (pin "5") (pinfunction "5_5") (pintype "passive"))
      (node (ref "F2") (pin "1") (pinfunction "1_1") (pintype "passive"))
      (node (ref "R112") (pin "2") (pinfunction "2_2") (pintype "passive"))
      (node (ref "R143") (pin "2") (pinfunction "2_2") (pintype "passive"))
      (node (ref "R144") (pin "2") (pinfunction "2_2") (pintype "passive"))
      (node (ref "R145") (pin "2") (pinfunction "2_2") (pintype "passive"))
      (node (ref "R147") (pin "2") (pinfunction "2_2") (pintype "passive"))
      (node (ref "R148") (pin "2") (pinfunction "2_2") (pintype "passive"))
      (node (ref "U11") (pin "1") (pinfunction "1_1") (pintype "passive"))
      (node (ref "U31") (pin "2") (pinfunction "2_2") (pintype "passive"))
      (node (ref "U69") (pin "10") (pinfunction "AVIN_10") (pintype "passive"))
      (node (ref "U69") (pin "11") (pinfunction "PVIN_11") (pintype "passive"))
      (node (ref "U69") (pin "12") (pinfunction "PVIN_12") (pintype "passive"))
      (node (ref "U69") (pin "13") (pinfunction "EN_13") (pintype "passive"))
      (node (ref "U70") (pin "10") (pinfunction "AVIN_10") (pintype "passive"))
      (node (ref "U70") (pin "11") (pinfunction "PVIN_11") (pintype "passive"))
      (node (ref "U70") (pin "12") (pinfunction "PVIN_12") (pintype "passive"))
      (node (ref "U70") (pin "13") (pinfunction "EN_13") (pintype "passive"))
      (node (ref "U71") (pin "10") (pinfunction "EN_10") (pintype "passive"))
      (node (ref "U71") (pin "4") (pinfunction "PVIN_4") (pintype "passive"))
      (node (ref "U71") (pin "5") (pinfunction "PVIN_5") (pintype "passive"))
      (node (ref "U71") (pin "6") (pinfunction "VIN_6") (pintype "passive"))
    )
    (net (code "468") (name "VCC_AUX") (class "Default")
      (node (ref "C17") (pin "2") (pinfunction "2_2") (pintype "passive"))
      (node (ref "C18") (pin "2") (pinfunction "2_2") (pintype "passive"))
      (node (ref "C19") (pin "2") (pinfunction "2_2") (pintype "passive"))
      (node (ref "C20") (pin "2") (pinfunction "2_2") (pintype "passive"))
      (node (ref "C205") (pin "2") (pinfunction "2_2") (pintype "passive"))
      (node (ref "C21") (pin "2") (pinfunction "2_2") (pintype "passive"))
      (node (ref "C22") (pin "2") (pinfunction "2_2") (pintype "passive"))
      (node (ref "C23") (pin "2") (pinfunction "2_2") (pintype "passive"))
      (node (ref "C24") (pin "2") (pinfunction "2_2") (pintype "passive"))
      (node (ref "C25") (pin "2") (pinfunction "2_2") (pintype "passive"))
      (node (ref "C29") (pin "2") (pinfunction "2_2") (pintype "passive"))
      (node (ref "C303") (pin "2") (pinfunction "2_2") (pintype "passive"))
      (node (ref "C304") (pin "2") (pinfunction "2_2") (pintype "passive"))
      (node (ref "C305") (pin "2") (pinfunction "2_2") (pintype "passive"))
      (node (ref "C306") (pin "2") (pinfunction "2_2") (pintype "passive"))
      (node (ref "C307") (pin "2") (pinfunction "2_2") (pintype "passive"))
      (node (ref "C308") (pin "2") (pinfunction "2_2") (pintype "passive"))
      (node (ref "C309") (pin "2") (pinfunction "2_2") (pintype "passive"))
      (node (ref "L28") (pin "2") (pinfunction "2_2") (pintype "passive"))
      (node (ref "U8") (pin "D16") (pinfunction "VCCAUX_D16") (pintype "passive"))
      (node (ref "U8") (pin "F11") (pinfunction "VCCAUX_F11") (pintype "passive"))
      (node (ref "U8") (pin "G12") (pinfunction "VCCAUX_G12") (pintype "passive"))
      (node (ref "U8") (pin "H15") (pinfunction "VCCAUX_H15") (pintype "passive"))
      (node (ref "U8") (pin "H9") (pinfunction "VCCAUX_H9") (pintype "passive"))
      (node (ref "U8") (pin "K15") (pinfunction "VCCAUX_K15") (pintype "passive"))
      (node (ref "U8") (pin "L8") (pinfunction "VCCAUX_L8") (pintype "passive"))
      (node (ref "U8") (pin "M15") (pinfunction "VCCAUX_M15") (pintype "passive"))
      (node (ref "U8") (pin "N8") (pinfunction "VCCAUX_N8") (pintype "passive"))
      (node (ref "U8") (pin "R10") (pinfunction "VCCAUX_R10") (pintype "passive"))
      (node (ref "U8") (pin "R12") (pinfunction "VCCAUX_R12") (pintype "passive"))
      (node (ref "U8") (pin "R6") (pinfunction "VCCAUX_R6") (pintype "passive"))
      (node (ref "U8") (pin "U11") (pinfunction "VCCAUX_U11") (pintype "passive"))
      (node (ref "U8") (pin "V6") (pinfunction "VCCAUX_V6") (pintype "passive"))
    )
    (net (code "469") (name "VDD_DDR3") (class "Default")
      (node (ref "C261") (pin "2") (pinfunction "2_2") (pintype "passive"))
      (node (ref "C262") (pin "2") (pinfunction "2_2") (pintype "passive"))
      (node (ref "C263") (pin "2") (pinfunction "2_2") (pintype "passive"))
      (node (ref "C264") (pin "2") (pinfunction "2_2") (pintype "passive"))
      (node (ref "C265") (pin "2") (pinfunction "2_2") (pintype "passive"))
      (node (ref "C266") (pin "2") (pinfunction "2_2") (pintype "passive"))
      (node (ref "C267") (pin "2") (pinfunction "2_2") (pintype "passive"))
      (node (ref "C268") (pin "2") (pinfunction "2_2") (pintype "passive"))
      (node (ref "C269") (pin "2") (pinfunction "2_2") (pintype "passive"))
      (node (ref "C270") (pin "2") (pinfunction "2_2") (pintype "passive"))
      (node (ref "C271") (pin "2") (pinfunction "2_2") (pintype "passive"))
      (node (ref "C272") (pin "2") (pinfunction "2_2") (pintype "passive"))
      (node (ref "C273") (pin "2") (pinfunction "2_2") (pintype "passive"))
      (node (ref "C274") (pin "2") (pinfunction "2_2") (pintype "passive"))
      (node (ref "C275") (pin "2") (pinfunction "2_2") (pintype "passive"))
      (node (ref "C276") (pin "2") (pinfunction "2_2") (pintype "passive"))
      (node (ref "C277") (pin "2") (pinfunction "2_2") (pintype "passive"))
      (node (ref "C278") (pin "2") (pinfunction "2_2") (pintype "passive"))
      (node (ref "C279") (pin "2") (pinfunction "2_2") (pintype "passive"))
      (node (ref "C280") (pin "2") (pinfunction "2_2") (pintype "passive"))
      (node (ref "C281") (pin "2") (pinfunction "2_2") (pintype "passive"))
      (node (ref "C282") (pin "2") (pinfunction "2_2") (pintype "passive"))
      (node (ref "C283") (pin "2") (pinfunction "2_2") (pintype "passive"))
      (node (ref "C284") (pin "2") (pinfunction "2_2") (pintype "passive"))
      (node (ref "C285") (pin "2") (pinfunction "2_2") (pintype "passive"))
      (node (ref "C286") (pin "2") (pinfunction "2_2") (pintype "passive"))
      (node (ref "C287") (pin "2") (pinfunction "2_2") (pintype "passive"))
      (node (ref "C288") (pin "2") (pinfunction "2_2") (pintype "passive"))
      (node (ref "C289") (pin "2") (pinfunction "2_2") (pintype "passive"))
      (node (ref "C290") (pin "2") (pinfunction "2_2") (pintype "passive"))
      (node (ref "C291") (pin "2") (pinfunction "2_2") (pintype "passive"))
      (node (ref "C292") (pin "2") (pinfunction "2_2") (pintype "passive"))
      (node (ref "C313") (pin "2") (pinfunction "2_2") (pintype "passive"))
      (node (ref "L34") (pin "2") (pinfunction "2_2") (pintype "passive"))
      (node (ref "U12") (pin "A1") (pinfunction "VDDQ_A1") (pintype "passive"))
      (node (ref "U12") (pin "A8") (pinfunction "VDDQ_A8") (pintype "passive"))
      (node (ref "U12") (pin "B2") (pinfunction "VDD_B2") (pintype "passive"))
      (node (ref "U12") (pin "C1") (pinfunction "VDDQ_C1") (pintype "passive"))
      (node (ref "U12") (pin "C9") (pinfunction "VDDQ_C9") (pintype "passive"))
      (node (ref "U12") (pin "D2") (pinfunction "VDDQ_D2") (pintype "passive"))
      (node (ref "U12") (pin "D9") (pinfunction "VDD_D9") (pintype "passive"))
      (node (ref "U12") (pin "E9") (pinfunction "VDDQ_E9") (pintype "passive"))
      (node (ref "U12") (pin "F1") (pinfunction "VDDQ_F1") (pintype "passive"))
      (node (ref "U12") (pin "G7") (pinfunction "VDD_G7") (pintype "passive"))
      (node (ref "U12") (pin "H2") (pinfunction "VDDQ_H2") (pintype "passive"))
      (node (ref "U12") (pin "H9") (pinfunction "VDDQ_H9") (pintype "passive"))
      (node (ref "U12") (pin "K2") (pinfunction "VDD_K2") (pintype "passive"))
      (node (ref "U12") (pin "K8") (pinfunction "VDD_K8") (pintype "passive"))
      (node (ref "U12") (pin "N1") (pinfunction "VDD_N1") (pintype "passive"))
      (node (ref "U12") (pin "N9") (pinfunction "VDD_N9") (pintype "passive"))
      (node (ref "U12") (pin "R1") (pinfunction "VDD_R1") (pintype "passive"))
      (node (ref "U12") (pin "R9") (pinfunction "VDD_R9") (pintype "passive"))
      (node (ref "U5") (pin "A1") (pinfunction "VDDQ_A1") (pintype "passive"))
      (node (ref "U5") (pin "A8") (pinfunction "VDDQ_A8") (pintype "passive"))
      (node (ref "U5") (pin "B2") (pinfunction "VDD_B2") (pintype "passive"))
      (node (ref "U5") (pin "C1") (pinfunction "VDDQ_C1") (pintype "passive"))
      (node (ref "U5") (pin "C9") (pinfunction "VDDQ_C9") (pintype "passive"))
      (node (ref "U5") (pin "D2") (pinfunction "VDDQ_D2") (pintype "passive"))
      (node (ref "U5") (pin "D9") (pinfunction "VDD_D9") (pintype "passive"))
      (node (ref "U5") (pin "E9") (pinfunction "VDDQ_E9") (pintype "passive"))
      (node (ref "U5") (pin "F1") (pinfunction "VDDQ_F1") (pintype "passive"))
      (node (ref "U5") (pin "G7") (pinfunction "VDD_G7") (pintype "passive"))
      (node (ref "U5") (pin "H2") (pinfunction "VDDQ_H2") (pintype "passive"))
      (node (ref "U5") (pin "H9") (pinfunction "VDDQ_H9") (pintype "passive"))
      (node (ref "U5") (pin "K2") (pinfunction "VDD_K2") (pintype "passive"))
      (node (ref "U5") (pin "K8") (pinfunction "VDD_K8") (pintype "passive"))
      (node (ref "U5") (pin "N1") (pinfunction "VDD_N1") (pintype "passive"))
      (node (ref "U5") (pin "N9") (pinfunction "VDD_N9") (pintype "passive"))
      (node (ref "U5") (pin "R1") (pinfunction "VDD_R1") (pintype "passive"))
      (node (ref "U5") (pin "R9") (pinfunction "VDD_R9") (pintype "passive"))
    )
    (net (code "470") (name "VDD_DDR3_REF") (class "Default")
      (node (ref "C102") (pin "1") (pinfunction "1_1") (pintype "passive"))
      (node (ref "C103") (pin "1") (pinfunction "1_1") (pintype "passive"))
      (node (ref "C104") (pin "1") (pinfunction "1_1") (pintype "passive"))
      (node (ref "C105") (pin "1") (pinfunction "1_1") (pintype "passive"))
      (node (ref "C124") (pin "1") (pinfunction "1_1") (pintype "passive"))
      (node (ref "U12") (pin "H1") (pinfunction "VREFDQ_H1") (pintype "passive"))
      (node (ref "U12") (pin "M8") (pinfunction "VREFCA_M8") (pintype "passive"))
      (node (ref "U5") (pin "H1") (pinfunction "VREFDQ_H1") (pintype "passive"))
      (node (ref "U5") (pin "M8") (pinfunction "VREFCA_M8") (pintype "passive"))
      (node (ref "U7") (pin "6") (pinfunction "REFOUT_6") (pintype "passive"))
      (node (ref "U8") (pin "B20") (pinfunction "IO_L1N_A24_VREF_1_B20") (pintype "passive"))
      (node (ref "U8") (pin "B3") (pinfunction "IO_L83N_VREF_3_B3") (pintype "passive"))
      (node (ref "U8") (pin "H17") (pinfunction "IO_L28N_VREF_1_H17") (pintype "passive"))
      (node (ref "U8") (pin "K8") (pinfunction "IO_L57N_VREF_3_K8") (pintype "passive"))
      (node (ref "U8") (pin "M4") (pinfunction "IO_L31N_VREF_3_M4") (pintype "passive"))
      (node (ref "U8") (pin "N19") (pinfunction "IO_L53N_VREF_1_N19") (pintype "passive"))
      (node (ref "U8") (pin "Y1") (pinfunction "IO_L1N_VREF_3_Y1") (pintype "passive"))
    )
    (net (code "471") (name "VTT_DDR3") (class "Default")
      (node (ref "C100") (pin "2") (pinfunction "2_2") (pintype "passive"))
      (node (ref "C101") (pin "2") (pinfunction "2_2") (pintype "passive"))
      (node (ref "C121") (pin "2") (pinfunction "2_2") (pintype "passive"))
      (node (ref "C122") (pin "2") (pinfunction "2_2") (pintype "passive"))
      (node (ref "C220") (pin "2") (pinfunction "2_2") (pintype "passive"))
      (node (ref "C221") (pin "2") (pinfunction "2_2") (pintype "passive"))
      (node (ref "C222") (pin "2") (pinfunction "2_2") (pintype "passive"))
      (node (ref "C223") (pin "2") (pinfunction "2_2") (pintype "passive"))
      (node (ref "C224") (pin "2") (pinfunction "2_2") (pintype "passive"))
      (node (ref "C225") (pin "2") (pinfunction "2_2") (pintype "passive"))
      (node (ref "C226") (pin "2") (pinfunction "2_2") (pintype "passive"))
      (node (ref "C227") (pin "2") (pinfunction "2_2") (pintype "passive"))
      (node (ref "C228") (pin "2") (pinfunction "2_2") (pintype "passive"))
      (node (ref "C229") (pin "2") (pinfunction "2_2") (pintype "passive"))
      (node (ref "C230") (pin "2") (pinfunction "2_2") (pintype "passive"))
      (node (ref "C231") (pin "2") (pinfunction "2_2") (pintype "passive"))
      (node (ref "C232") (pin "2") (pinfunction "2_2") (pintype "passive"))
      (node (ref "C233") (pin "2") (pinfunction "2_2") (pintype "passive"))
      (node (ref "C234") (pin "2") (pinfunction "2_2") (pintype "passive"))
      (node (ref "C235") (pin "2") (pinfunction "2_2") (pintype "passive"))
      (node (ref "C236") (pin "2") (pinfunction "2_2") (pintype "passive"))
      (node (ref "C237") (pin "2") (pinfunction "2_2") (pintype "passive"))
      (node (ref "C238") (pin "2") (pinfunction "2_2") (pintype "passive"))
      (node (ref "C239") (pin "2") (pinfunction "2_2") (pintype "passive"))
      (node (ref "C240") (pin "2") (pinfunction "2_2") (pintype "passive"))
      (node (ref "C241") (pin "2") (pinfunction "2_2") (pintype "passive"))
      (node (ref "C242") (pin "2") (pinfunction "2_2") (pintype "passive"))
      (node (ref "C243") (pin "2") (pinfunction "2_2") (pintype "passive"))
      (node (ref "C244") (pin "2") (pinfunction "2_2") (pintype "passive"))
      (node (ref "C245") (pin "2") (pinfunction "2_2") (pintype "passive"))
      (node (ref "C246") (pin "2") (pinfunction "2_2") (pintype "passive"))
      (node (ref "C247") (pin "2") (pinfunction "2_2") (pintype "passive"))
      (node (ref "C248") (pin "2") (pinfunction "2_2") (pintype "passive"))
      (node (ref "C249") (pin "2") (pinfunction "2_2") (pintype "passive"))
      (node (ref "C250") (pin "2") (pinfunction "2_2") (pintype "passive"))
      (node (ref "C251") (pin "2") (pinfunction "2_2") (pintype "passive"))
      (node (ref "C259") (pin "1") (pinfunction "1_1") (pintype "passive"))
      (node (ref "C260") (pin "1") (pinfunction "1_1") (pintype "passive"))
      (node (ref "C78") (pin "2") (pinfunction "2_2") (pintype "passive"))
      (node (ref "C79") (pin "2") (pinfunction "2_2") (pintype "passive"))
      (node (ref "C80") (pin "2") (pinfunction "2_2") (pintype "passive"))
      (node (ref "C81") (pin "2") (pinfunction "2_2") (pintype "passive"))
      (node (ref "C82") (pin "2") (pinfunction "2_2") (pintype "passive"))
      (node (ref "C83") (pin "2") (pinfunction "2_2") (pintype "passive"))
      (node (ref "C84") (pin "2") (pinfunction "2_2") (pintype "passive"))
      (node (ref "C85") (pin "2") (pinfunction "2_2") (pintype "passive"))
      (node (ref "C86") (pin "2") (pinfunction "2_2") (pintype "passive"))
      (node (ref "C87") (pin "2") (pinfunction "2_2") (pintype "passive"))
      (node (ref "C88") (pin "2") (pinfunction "2_2") (pintype "passive"))
      (node (ref "C89") (pin "2") (pinfunction "2_2") (pintype "passive"))
      (node (ref "C90") (pin "2") (pinfunction "2_2") (pintype "passive"))
      (node (ref "C91") (pin "2") (pinfunction "2_2") (pintype "passive"))
      (node (ref "C92") (pin "2") (pinfunction "2_2") (pintype "passive"))
      (node (ref "C93") (pin "2") (pinfunction "2_2") (pintype "passive"))
      (node (ref "C94") (pin "2") (pinfunction "2_2") (pintype "passive"))
      (node (ref "C95") (pin "2") (pinfunction "2_2") (pintype "passive"))
      (node (ref "C96") (pin "2") (pinfunction "2_2") (pintype "passive"))
      (node (ref "C97") (pin "2") (pinfunction "2_2") (pintype "passive"))
      (node (ref "C98") (pin "2") (pinfunction "2_2") (pintype "passive"))
      (node (ref "C99") (pin "2") (pinfunction "2_2") (pintype "passive"))
      (node (ref "R27") (pin "2") (pinfunction "2_2") (pintype "passive"))
      (node (ref "R29") (pin "2") (pinfunction "2_2") (pintype "passive"))
      (node (ref "R30") (pin "2") (pinfunction "2_2") (pintype "passive"))
      (node (ref "R32") (pin "2") (pinfunction "2_2") (pintype "passive"))
      (node (ref "R33") (pin "2") (pinfunction "2_2") (pintype "passive"))
      (node (ref "R34") (pin "2") (pinfunction "2_2") (pintype "passive"))
      (node (ref "R35") (pin "2") (pinfunction "2_2") (pintype "passive"))
      (node (ref "R36") (pin "2") (pinfunction "2_2") (pintype "passive"))
      (node (ref "R37") (pin "2") (pinfunction "2_2") (pintype "passive"))
      (node (ref "R38") (pin "2") (pinfunction "2_2") (pintype "passive"))
      (node (ref "R39") (pin "2") (pinfunction "2_2") (pintype "passive"))
      (node (ref "R40") (pin "2") (pinfunction "2_2") (pintype "passive"))
      (node (ref "R41") (pin "2") (pinfunction "2_2") (pintype "passive"))
      (node (ref "R42") (pin "2") (pinfunction "2_2") (pintype "passive"))
      (node (ref "R43") (pin "2") (pinfunction "2_2") (pintype "passive"))
      (node (ref "R44") (pin "2") (pinfunction "2_2") (pintype "passive"))
      (node (ref "R45") (pin "2") (pinfunction "2_2") (pintype "passive"))
      (node (ref "R46") (pin "2") (pinfunction "2_2") (pintype "passive"))
      (node (ref "R47") (pin "2") (pinfunction "2_2") (pintype "passive"))
      (node (ref "R48") (pin "2") (pinfunction "2_2") (pintype "passive"))
      (node (ref "R49") (pin "2") (pinfunction "2_2") (pintype "passive"))
      (node (ref "R50") (pin "2") (pinfunction "2_2") (pintype "passive"))
      (node (ref "R54") (pin "2") (pinfunction "2_2") (pintype "passive"))
      (node (ref "R56") (pin "2") (pinfunction "2_2") (pintype "passive"))
      (node (ref "R57") (pin "2") (pinfunction "2_2") (pintype "passive"))
      (node (ref "R59") (pin "2") (pinfunction "2_2") (pintype "passive"))
      (node (ref "R60") (pin "2") (pinfunction "2_2") (pintype "passive"))
      (node (ref "R61") (pin "2") (pinfunction "2_2") (pintype "passive"))
      (node (ref "R62") (pin "2") (pinfunction "2_2") (pintype "passive"))
      (node (ref "R63") (pin "2") (pinfunction "2_2") (pintype "passive"))
      (node (ref "R64") (pin "2") (pinfunction "2_2") (pintype "passive"))
      (node (ref "R65") (pin "2") (pinfunction "2_2") (pintype "passive"))
      (node (ref "R66") (pin "2") (pinfunction "2_2") (pintype "passive"))
      (node (ref "R67") (pin "2") (pinfunction "2_2") (pintype "passive"))
      (node (ref "R68") (pin "2") (pinfunction "2_2") (pintype "passive"))
      (node (ref "R69") (pin "2") (pinfunction "2_2") (pintype "passive"))
      (node (ref "R70") (pin "2") (pinfunction "2_2") (pintype "passive"))
      (node (ref "R71") (pin "2") (pinfunction "2_2") (pintype "passive"))
      (node (ref "R72") (pin "2") (pinfunction "2_2") (pintype "passive"))
      (node (ref "R73") (pin "2") (pinfunction "2_2") (pintype "passive"))
      (node (ref "R74") (pin "2") (pinfunction "2_2") (pintype "passive"))
      (node (ref "R75") (pin "2") (pinfunction "2_2") (pintype "passive"))
      (node (ref "R76") (pin "2") (pinfunction "2_2") (pintype "passive"))
      (node (ref "R77") (pin "2") (pinfunction "2_2") (pintype "passive"))
      (node (ref "U7") (pin "3") (pinfunction "VO_3") (pintype "passive"))
      (node (ref "U7") (pin "5") (pinfunction "VOSNS_5") (pintype "passive"))
    )
    (net (code "472") (name "unconnected-(CN2-Pad7)") (class "Default")
      (node (ref "CN2") (pin "7") (pinfunction "7_7") (pintype "passive+no_connect"))
    )
    (net (code "473") (name "unconnected-(CN2-Pad8)") (class "Default")
      (node (ref "CN2") (pin "8") (pinfunction "8_8") (pintype "passive+no_connect"))
    )
    (net (code "474") (name "unconnected-(D12-Pad3)") (class "Default")
      (node (ref "D12") (pin "3") (pinfunction "3_3") (pintype "passive+no_connect"))
    )
    (net (code "475") (name "unconnected-(D16-Pad3)") (class "Default")
      (node (ref "D16") (pin "3") (pinfunction "3_3") (pintype "passive+no_connect"))
    )
    (net (code "476") (name "unconnected-(DSUB1-Pad4)") (class "Default")
      (node (ref "DSUB1") (pin "4") (pinfunction "4_4") (pintype "passive+no_connect"))
    )
    (net (code "477") (name "unconnected-(DSUB1-Pad11)") (class "Default")
      (node (ref "DSUB1") (pin "11") (pinfunction "11_11") (pintype "passive+no_connect"))
    )
    (net (code "478") (name "unconnected-(R78-Pad1)") (class "Default")
      (node (ref "R78") (pin "1") (pinfunction "1_1") (pintype "passive"))
    )
    (net (code "479") (name "unconnected-(RN13-Pad1)") (class "Default")
      (node (ref "RN13") (pin "1") (pinfunction "1_1") (pintype "passive+no_connect"))
    )
    (net (code "480") (name "unconnected-(RN13-Pad8)") (class "Default")
      (node (ref "RN13") (pin "8") (pinfunction "8_8") (pintype "passive+no_connect"))
    )
    (net (code "481") (name "unconnected-(RN14-Pad3)") (class "Default")
      (node (ref "RN14") (pin "3") (pinfunction "3_3") (pintype "passive"))
    )
    (net (code "482") (name "unconnected-(RN14-Pad4)") (class "Default")
      (node (ref "RN14") (pin "4") (pinfunction "4_4") (pintype "passive"))
    )
    (net (code "483") (name "unconnected-(RN14-Pad5)") (class "Default")
      (node (ref "RN14") (pin "5") (pinfunction "5_5") (pintype "passive"))
    )
    (net (code "484") (name "unconnected-(RN14-Pad6)") (class "Default")
      (node (ref "RN14") (pin "6") (pinfunction "6_6") (pintype "passive"))
    )
    (net (code "485") (name "unconnected-(RN21-Pad1)") (class "Default")
      (node (ref "RN21") (pin "1") (pinfunction "1_1") (pintype "passive+no_connect"))
    )
    (net (code "486") (name "unconnected-(RN21-Pad8)") (class "Default")
      (node (ref "RN21") (pin "8") (pinfunction "8_8") (pintype "passive+no_connect"))
    )
    (net (code "487") (name "unconnected-(RN22-Pad1)") (class "Default")
      (node (ref "RN22") (pin "1") (pinfunction "1_1") (pintype "passive+no_connect"))
    )
    (net (code "488") (name "unconnected-(RN22-Pad2)") (class "Default")
      (node (ref "RN22") (pin "2") (pinfunction "2_2") (pintype "passive+no_connect"))
    )
    (net (code "489") (name "unconnected-(RN22-Pad7)") (class "Default")
      (node (ref "RN22") (pin "7") (pinfunction "7_7") (pintype "passive+no_connect"))
    )
    (net (code "490") (name "unconnected-(RN22-Pad8)") (class "Default")
      (node (ref "RN22") (pin "8") (pinfunction "8_8") (pintype "passive+no_connect"))
    )
    (net (code "491") (name "unconnected-(U2-EXT_RES-Pad96)") (class "Default")
      (node (ref "U2") (pin "96") (pinfunction "EXT_RES_96") (pintype "passive+no_connect"))
    )
    (net (code "492") (name "unconnected-(U2-PD#-Pad2)") (class "Default")
      (node (ref "U2") (pin "2") (pinfunction "PD#_2") (pintype "passive+no_connect"))
    )
    (net (code "493") (name "unconnected-(U2-QO0-Pad49)") (class "Default")
      (node (ref "U2") (pin "49") (pinfunction "QO0_49") (pintype "passive+no_connect"))
    )
    (net (code "494") (name "unconnected-(U2-QO1-Pad50)") (class "Default")
      (node (ref "U2") (pin "50") (pinfunction "QO1_50") (pintype "passive+no_connect"))
    )
    (net (code "495") (name "unconnected-(U2-QO2-Pad51)") (class "Default")
      (node (ref "U2") (pin "51") (pinfunction "QO2_51") (pintype "passive+no_connect"))
    )
    (net (code "496") (name "unconnected-(U2-QO3-Pad52)") (class "Default")
      (node (ref "U2") (pin "52") (pinfunction "QO3_52") (pintype "passive+no_connect"))
    )
    (net (code "497") (name "unconnected-(U2-QO4-Pad53)") (class "Default")
      (node (ref "U2") (pin "53") (pinfunction "QO4_53") (pintype "passive+no_connect"))
    )
    (net (code "498") (name "unconnected-(U2-QO5-Pad54)") (class "Default")
      (node (ref "U2") (pin "54") (pinfunction "QO5_54") (pintype "passive+no_connect"))
    )
    (net (code "499") (name "unconnected-(U2-QO6-Pad55)") (class "Default")
      (node (ref "U2") (pin "55") (pinfunction "QO6_55") (pintype "passive+no_connect"))
    )
    (net (code "500") (name "unconnected-(U2-QO7-Pad56)") (class "Default")
      (node (ref "U2") (pin "56") (pinfunction "QO7_56") (pintype "passive+no_connect"))
    )
    (net (code "501") (name "unconnected-(U2-QO8-Pad59)") (class "Default")
      (node (ref "U2") (pin "59") (pinfunction "QO8_59") (pintype "passive+no_connect"))
    )
    (net (code "502") (name "unconnected-(U2-QO9-Pad60)") (class "Default")
      (node (ref "U2") (pin "60") (pinfunction "QO9_60") (pintype "passive+no_connect"))
    )
    (net (code "503") (name "unconnected-(U2-QO10-Pad61)") (class "Default")
      (node (ref "U2") (pin "61") (pinfunction "QO10_61") (pintype "passive+no_connect"))
    )
    (net (code "504") (name "unconnected-(U2-QO11-Pad62)") (class "Default")
      (node (ref "U2") (pin "62") (pinfunction "QO11_62") (pintype "passive+no_connect"))
    )
    (net (code "505") (name "unconnected-(U2-QO12-Pad63)") (class "Default")
      (node (ref "U2") (pin "63") (pinfunction "QO12_63") (pintype "passive+no_connect"))
    )
    (net (code "506") (name "unconnected-(U2-QO13-Pad64)") (class "Default")
      (node (ref "U2") (pin "64") (pinfunction "QO13_64") (pintype "passive+no_connect"))
    )
    (net (code "507") (name "unconnected-(U2-QO14-Pad65)") (class "Default")
      (node (ref "U2") (pin "65") (pinfunction "QO14_65") (pintype "passive+no_connect"))
    )
    (net (code "508") (name "unconnected-(U2-QO15-Pad66)") (class "Default")
      (node (ref "U2") (pin "66") (pinfunction "QO15_66") (pintype "passive+no_connect"))
    )
    (net (code "509") (name "unconnected-(U2-QO16-Pad69)") (class "Default")
      (node (ref "U2") (pin "69") (pinfunction "QO16_69") (pintype "passive+no_connect"))
    )
    (net (code "510") (name "unconnected-(U2-QO17-Pad70)") (class "Default")
      (node (ref "U2") (pin "70") (pinfunction "QO17_70") (pintype "passive+no_connect"))
    )
    (net (code "511") (name "unconnected-(U2-QO18-Pad71)") (class "Default")
      (node (ref "U2") (pin "71") (pinfunction "QO18_71") (pintype "passive+no_connect"))
    )
    (net (code "512") (name "unconnected-(U2-QO19-Pad72)") (class "Default")
      (node (ref "U2") (pin "72") (pinfunction "QO19_72") (pintype "passive+no_connect"))
    )
    (net (code "513") (name "unconnected-(U2-QO20-Pad73)") (class "Default")
      (node (ref "U2") (pin "73") (pinfunction "QO20_73") (pintype "passive+no_connect"))
    )
    (net (code "514") (name "unconnected-(U2-QO21-Pad74)") (class "Default")
      (node (ref "U2") (pin "74") (pinfunction "QO21_74") (pintype "passive+no_connect"))
    )
    (net (code "515") (name "unconnected-(U2-QO22-Pad75)") (class "Default")
      (node (ref "U2") (pin "75") (pinfunction "QO22_75") (pintype "passive+no_connect"))
    )
    (net (code "516") (name "unconnected-(U2-QO23-Pad77)") (class "Default")
      (node (ref "U2") (pin "77") (pinfunction "QO23_77") (pintype "passive+no_connect"))
    )
    (net (code "517") (name "unconnected-(U2-STAG#-Pad7)") (class "Default")
      (node (ref "U2") (pin "7") (pinfunction "STAG#_7") (pintype "passive+no_connect"))
    )
    (net (code "518") (name "unconnected-(U3-NC-Pad49)") (class "Default")
      (node (ref "U3") (pin "49") (pinfunction "NC_49") (pintype "passive+no_connect"))
    )
    (net (code "519") (name "unconnected-(U5-NC-PadJ1)") (class "Default")
      (node (ref "U5") (pin "J1") (pinfunction "NC_J1") (pintype "passive+no_connect"))
    )
    (net (code "520") (name "unconnected-(U5-NC-PadJ9)") (class "Default")
      (node (ref "U5") (pin "J9") (pinfunction "NC_J9") (pintype "passive+no_connect"))
    )
    (net (code "521") (name "unconnected-(U5-NC-PadL1)") (class "Default")
      (node (ref "U5") (pin "L1") (pinfunction "NC_L1") (pintype "passive+no_connect"))
    )
    (net (code "522") (name "unconnected-(U5-NC-PadL9)") (class "Default")
      (node (ref "U5") (pin "L9") (pinfunction "NC_L9") (pintype "passive+no_connect"))
    )
    (net (code "523") (name "unconnected-(U5-NC-PadM7)") (class "Default")
      (node (ref "U5") (pin "M7") (pinfunction "NC_M7") (pintype "passive+no_connect"))
    )
    (net (code "524") (name "unconnected-(U7-PGOOD-Pad9)") (class "Default")
      (node (ref "U7") (pin "9") (pinfunction "PGOOD_9") (pintype "passive+no_connect"))
    )
    (net (code "525") (name "unconnected-(U8A-IO_L1N_VREF_0-PadA4)") (class "Default")
      (node (ref "U8") (pin "A4") (pinfunction "IO_L1N_VREF_0_A4") (pintype "passive+no_connect"))
    )
    (net (code "526") (name "unconnected-(U8A-IO_L33N_0-PadC10)") (class "Default")
      (node (ref "U8") (pin "C10") (pinfunction "IO_L33N_0_C10") (pintype "passive"))
    )
    (net (code "527") (name "unconnected-(U8A-IO_L33P_0-PadD10)") (class "Default")
      (node (ref "U8") (pin "D10") (pinfunction "IO_L33P_0_D10") (pintype "passive"))
    )
    (net (code "528") (name "unconnected-(U8A-IO_L34N_GCLK18_0-PadA10)") (class "Default")
      (node (ref "U8") (pin "A10") (pinfunction "IO_L34N_GCLK18_0_A10") (pintype "passive"))
    )
    (net (code "529") (name "unconnected-(U8A-IO_L35N_GCLK16_0-PadA11)") (class "Default")
      (node (ref "U8") (pin "A11") (pinfunction "IO_L35N_GCLK16_0_A11") (pintype "passive"))
    )
    (net (code "530") (name "unconnected-(U8A-IO_L35P_GCLK17_0-PadC11)") (class "Default")
      (node (ref "U8") (pin "C11") (pinfunction "IO_L35P_GCLK17_0_C11") (pintype "passive"))
    )
    (net (code "531") (name "unconnected-(U8A-IO_L36N_GCLK14_0-PadC12)") (class "Default")
      (node (ref "U8") (pin "C12") (pinfunction "IO_L36N_GCLK14_0_C12") (pintype "passive"))
    )
    (net (code "532") (name "unconnected-(U8A-IO_L36P_GCLK15_0-PadD11)") (class "Default")
      (node (ref "U8") (pin "D11") (pinfunction "IO_L36P_GCLK15_0_D11") (pintype "passive"))
    )
    (net (code "533") (name "unconnected-(U8A-IO_L37N_GCLK12_0-PadA12)") (class "Default")
      (node (ref "U8") (pin "A12") (pinfunction "IO_L37N_GCLK12_0_A12") (pintype "passive"))
    )
    (net (code "534") (name "unconnected-(U8A-IO_L37P_GCLK13_0-PadB12)") (class "Default")
      (node (ref "U8") (pin "B12") (pinfunction "IO_L37P_GCLK13_0_B12") (pintype "passive"))
    )
    (net (code "535") (name "unconnected-(U8A-IO_L38P_0-PadC13)") (class "Default")
      (node (ref "U8") (pin "C13") (pinfunction "IO_L38P_0_C13") (pintype "passive"))
    )
    (net (code "536") (name "unconnected-(U8A-IO_L49P_0-PadD14)") (class "Default")
      (node (ref "U8") (pin "D14") (pinfunction "IO_L49P_0_D14") (pintype "passive+no_connect"))
    )
    (net (code "537") (name "unconnected-(U8B-IO_L9N_1-PadG17)") (class "Default")
      (node (ref "U8") (pin "G17") (pinfunction "IO_L9N_1_G17") (pintype "passive+no_connect"))
    )
    (net (code "538") (name "unconnected-(U8B-IO_L9P_1-PadG16)") (class "Default")
      (node (ref "U8") (pin "G16") (pinfunction "IO_L9P_1_G16") (pintype "passive+no_connect"))
    )
    (net (code "539") (name "unconnected-(U8B-IO_L21N_1-PadJ16)") (class "Default")
      (node (ref "U8") (pin "J16") (pinfunction "IO_L21N_1_J16") (pintype "passive+no_connect"))
    )
    (net (code "540") (name "unconnected-(U8B-IO_L21P_1-PadK16)") (class "Default")
      (node (ref "U8") (pin "K16") (pinfunction "IO_L21P_1_K16") (pintype "passive+no_connect"))
    )
    (net (code "541") (name "unconnected-(U8B-IO_L28P_1-PadH16)") (class "Default")
      (node (ref "U8") (pin "H16") (pinfunction "IO_L28P_1_H16") (pintype "passive+no_connect"))
    )
    (net (code "542") (name "unconnected-(U8B-IO_L42N_GCLK6_TRDY1_M1LDM_1-PadL19)") (class "Default")
      (node (ref "U8") (pin "L19") (pinfunction "IO_L42N_GCLK6_TRDY1_M1LDM_1_L19") (pintype "passive+no_connect"))
    )
    (net (code "543") (name "unconnected-(U8B-IO_L42P_GCLK7_M1UDM_1-PadM20)") (class "Default")
      (node (ref "U8") (pin "M20") (pinfunction "IO_L42P_GCLK7_M1UDM_1_M20") (pintype "passive+no_connect"))
    )
    (net (code "544") (name "unconnected-(U8B-IO_L53P_1-PadM19)") (class "Default")
      (node (ref "U8") (pin "M19") (pinfunction "IO_L53P_1_M19") (pintype "passive+no_connect"))
    )
    (net (code "545") (name "unconnected-(U8B-IO_L58N_1-PadL15)") (class "Default")
      (node (ref "U8") (pin "L15") (pinfunction "IO_L58N_1_L15") (pintype "passive+no_connect"))
    )
    (net (code "546") (name "unconnected-(U8B-IO_L61N_1-PadK18)") (class "Default")
      (node (ref "U8") (pin "K18") (pinfunction "IO_L61N_1_K18") (pintype "passive+no_connect"))
    )
    (net (code "547") (name "unconnected-(U8B-IO_L61P_1-PadL17)") (class "Default")
      (node (ref "U8") (pin "L17") (pinfunction "IO_L61P_1_L17") (pintype "passive+no_connect"))
    )
    (net (code "548") (name "unconnected-(U8C-IO_L4N_VREF_2-PadT17)") (class "Default")
      (node (ref "U8") (pin "T17") (pinfunction "IO_L4N_VREF_2_T17") (pintype "passive+no_connect"))
    )
    (net (code "549") (name "unconnected-(U8C-IO_L4P_2-PadT18)") (class "Default")
      (node (ref "U8") (pin "T18") (pinfunction "IO_L4P_2_T18") (pintype "passive+no_connect"))
    )
    (net (code "550") (name "unconnected-(U8C-IO_L5P_2-PadY19)") (class "Default")
      (node (ref "U8") (pin "Y19") (pinfunction "IO_L5P_2_Y19") (pintype "passive+no_connect"))
    )
    (net (code "551") (name "unconnected-(U8C-IO_L6N_2-PadY18)") (class "Default")
      (node (ref "U8") (pin "Y18") (pinfunction "IO_L6N_2_Y18") (pintype "passive"))
    )
    (net (code "552") (name "unconnected-(U8C-IO_L8N_2-PadU16)") (class "Default")
      (node (ref "U8") (pin "U16") (pinfunction "IO_L8N_2_U16") (pintype "passive+no_connect"))
    )
    (net (code "553") (name "unconnected-(U8C-IO_L8P_2-PadU17)") (class "Default")
      (node (ref "U8") (pin "U17") (pinfunction "IO_L8P_2_U17") (pintype "passive+no_connect"))
    )
    (net (code "554") (name "unconnected-(U8C-IO_L9P_2-PadV19)") (class "Default")
      (node (ref "U8") (pin "V19") (pinfunction "IO_L9P_2_V19") (pintype "passive+no_connect"))
    )
    (net (code "555") (name "unconnected-(U8C-IO_L10P_2-PadR16)") (class "Default")
      (node (ref "U8") (pin "R16") (pinfunction "IO_L10P_2_R16") (pintype "passive+no_connect"))
    )
    (net (code "556") (name "unconnected-(U8C-IO_L11N_2-PadW17)") (class "Default")
      (node (ref "U8") (pin "W17") (pinfunction "IO_L11N_2_W17") (pintype "passive+no_connect"))
    )
    (net (code "557") (name "unconnected-(U8C-IO_L13N_D10_2-PadV15)") (class "Default")
      (node (ref "U8") (pin "V15") (pinfunction "IO_L13N_D10_2_V15") (pintype "passive+no_connect"))
    )
    (net (code "558") (name "unconnected-(U8C-IO_L16P_2-PadAA14)") (class "Default")
      (node (ref "U8") (pin "AA14") (pinfunction "IO_L16P_2_AA14") (pintype "passive+no_connect"))
    )
    (net (code "559") (name "unconnected-(U8C-IO_L18N_2-PadW13)") (class "Default")
      (node (ref "U8") (pin "W13") (pinfunction "IO_L18N_2_W13") (pintype "passive+no_connect"))
    )
    (net (code "560") (name "unconnected-(U8C-IO_L21P_2-PadY15)") (class "Default")
      (node (ref "U8") (pin "Y15") (pinfunction "IO_L21P_2_Y15") (pintype "passive+no_connect"))
    )
    (net (code "561") (name "unconnected-(U8C-IO_L29P_GCLK3_2-PadW12)") (class "Default")
      (node (ref "U8") (pin "W12") (pinfunction "IO_L29P_GCLK3_2_W12") (pintype "passive+no_connect"))
    )
    (net (code "562") (name "unconnected-(U8C-IO_L30P_GCLK1_D13_2-PadY13)") (class "Default")
      (node (ref "U8") (pin "Y13") (pinfunction "IO_L30P_GCLK1_D13_2_Y13") (pintype "passive+no_connect"))
    )
    (net (code "563") (name "unconnected-(U8C-IO_L43N_2-PadAB9)") (class "Default")
      (node (ref "U8") (pin "AB9") (pinfunction "IO_L43N_2_AB9") (pintype "passive+no_connect"))
    )
    (net (code "564") (name "unconnected-(U8C-IO_L43P_2-PadY9)") (class "Default")
      (node (ref "U8") (pin "Y9") (pinfunction "IO_L43P_2_Y9") (pintype "passive+no_connect"))
    )
    (net (code "565") (name "unconnected-(U8C-IO_L48P_D7_2-PadY7)") (class "Default")
      (node (ref "U8") (pin "Y7") (pinfunction "IO_L48P_D7_2_Y7") (pintype "passive+no_connect"))
    )
    (net (code "566") (name "unconnected-(U8D-IO_L1P_3-PadY2)") (class "Default")
      (node (ref "U8") (pin "Y2") (pinfunction "IO_L1P_3_Y2") (pintype "passive+no_connect"))
    )
    (net (code "567") (name "unconnected-(U8D-IO_L2N_3-PadW1)") (class "Default")
      (node (ref "U8") (pin "W1") (pinfunction "IO_L2N_3_W1") (pintype "passive+no_connect"))
    )
    (net (code "568") (name "unconnected-(U8D-IO_L2P_3-PadW3)") (class "Default")
      (node (ref "U8") (pin "W3") (pinfunction "IO_L2P_3_W3") (pintype "passive"))
    )
    (net (code "569") (name "unconnected-(U8D-IO_L7N_3-PadP7)") (class "Default")
      (node (ref "U8") (pin "P7") (pinfunction "IO_L7N_3_P7") (pintype "passive+no_connect"))
    )
    (net (code "570") (name "unconnected-(U8D-IO_L7P_3-PadP8)") (class "Default")
      (node (ref "U8") (pin "P8") (pinfunction "IO_L7P_3_P8") (pintype "passive+no_connect"))
    )
    (net (code "571") (name "unconnected-(U8D-IO_L8N_3-PadP5)") (class "Default")
      (node (ref "U8") (pin "P5") (pinfunction "IO_L8N_3_P5") (pintype "passive+no_connect"))
    )
    (net (code "572") (name "unconnected-(U8D-IO_L8P_3-PadP6)") (class "Default")
      (node (ref "U8") (pin "P6") (pinfunction "IO_L8P_3_P6") (pintype "passive+no_connect"))
    )
    (net (code "573") (name "unconnected-(U8D-IO_L9N_3-PadT3)") (class "Default")
      (node (ref "U8") (pin "T3") (pinfunction "IO_L9N_3_T3") (pintype "passive+no_connect"))
    )
    (net (code "574") (name "unconnected-(U8D-IO_L9P_3-PadT4)") (class "Default")
      (node (ref "U8") (pin "T4") (pinfunction "IO_L9P_3_T4") (pintype "passive+no_connect"))
    )
    (net (code "575") (name "unconnected-(U8D-IO_L10N_3-PadV3)") (class "Default")
      (node (ref "U8") (pin "V3") (pinfunction "IO_L10N_3_V3") (pintype "passive+no_connect"))
    )
    (net (code "576") (name "unconnected-(U8D-IO_L10P_3-PadU4)") (class "Default")
      (node (ref "U8") (pin "U4") (pinfunction "IO_L10P_3_U4") (pintype "passive+no_connect"))
    )
    (net (code "577") (name "unconnected-(U8D-IO_L11N_3-PadN7)") (class "Default")
      (node (ref "U8") (pin "N7") (pinfunction "IO_L11N_3_N7") (pintype "passive+no_connect"))
    )
    (net (code "578") (name "unconnected-(U8D-IO_L11P_3-PadN6)") (class "Default")
      (node (ref "U8") (pin "N6") (pinfunction "IO_L11P_3_N6") (pintype "passive+no_connect"))
    )
    (net (code "579") (name "unconnected-(U8D-IO_L23N_3-PadM8)") (class "Default")
      (node (ref "U8") (pin "M8") (pinfunction "IO_L23N_3_M8") (pintype "passive+no_connect"))
    )
    (net (code "580") (name "unconnected-(U8D-IO_L23P_3-PadM7)") (class "Default")
      (node (ref "U8") (pin "M7") (pinfunction "IO_L23P_3_M7") (pintype "passive+no_connect"))
    )
    (net (code "581") (name "unconnected-(U8D-IO_L24N_3-PadP4)") (class "Default")
      (node (ref "U8") (pin "P4") (pinfunction "IO_L24N_3_P4") (pintype "passive+no_connect"))
    )
    (net (code "582") (name "unconnected-(U8D-IO_L24P_3-PadR4)") (class "Default")
      (node (ref "U8") (pin "R4") (pinfunction "IO_L24P_3_R4") (pintype "passive+no_connect"))
    )
    (net (code "583") (name "unconnected-(U8D-IO_L25N_3-PadL6)") (class "Default")
      (node (ref "U8") (pin "L6") (pinfunction "IO_L25N_3_L6") (pintype "passive+no_connect"))
    )
    (net (code "584") (name "unconnected-(U8D-IO_L25P_3-PadM6)") (class "Default")
      (node (ref "U8") (pin "M6") (pinfunction "IO_L25P_3_M6") (pintype "passive+no_connect"))
    )
    (net (code "585") (name "unconnected-(U8D-IO_L26N_3-PadN4)") (class "Default")
      (node (ref "U8") (pin "N4") (pinfunction "IO_L26N_3_N4") (pintype "passive+no_connect"))
    )
    (net (code "586") (name "unconnected-(U8D-IO_L26P_3-PadP3)") (class "Default")
      (node (ref "U8") (pin "P3") (pinfunction "IO_L26P_3_P3") (pintype "passive+no_connect"))
    )
    (net (code "587") (name "unconnected-(U8D-IO_L31P_3-PadM5)") (class "Default")
      (node (ref "U8") (pin "M5") (pinfunction "IO_L31P_3_M5") (pintype "passive+no_connect"))
    )
    (net (code "588") (name "unconnected-(U8D-IO_L42N_GCLK24_M3LDM_3-PadL4)") (class "Default")
      (node (ref "U8") (pin "L4") (pinfunction "IO_L42N_GCLK24_M3LDM_3_L4") (pintype "passive+no_connect"))
    )
    (net (code "589") (name "unconnected-(U8D-IO_L42P_GCLK25_TRDY2_M3UDM_3-PadM3)") (class "Default")
      (node (ref "U8") (pin "M3") (pinfunction "IO_L42P_GCLK25_TRDY2_M3UDM_3_M3") (pintype "passive+no_connect"))
    )
    (net (code "590") (name "unconnected-(U8D-IO_L57P_3-PadK7)") (class "Default")
      (node (ref "U8") (pin "K7") (pinfunction "IO_L57P_3_K7") (pintype "passive+no_connect"))
    )
    (net (code "591") (name "unconnected-(U8D-IO_L58N_3-PadE4)") (class "Default")
      (node (ref "U8") (pin "E4") (pinfunction "IO_L58N_3_E4") (pintype "passive+no_connect"))
    )
    (net (code "592") (name "unconnected-(U8D-IO_L58P_3-PadD5)") (class "Default")
      (node (ref "U8") (pin "D5") (pinfunction "IO_L58P_3_D5") (pintype "passive+no_connect"))
    )
    (net (code "593") (name "unconnected-(U8D-IO_L59N_3-PadH8)") (class "Default")
      (node (ref "U8") (pin "H8") (pinfunction "IO_L59N_3_H8") (pintype "passive+no_connect"))
    )
    (net (code "594") (name "unconnected-(U8D-IO_L59P_3-PadJ7)") (class "Default")
      (node (ref "U8") (pin "J7") (pinfunction "IO_L59P_3_J7") (pintype "passive+no_connect"))
    )
    (net (code "595") (name "unconnected-(U8D-IO_L60N_3-PadB1)") (class "Default")
      (node (ref "U8") (pin "B1") (pinfunction "IO_L60N_3_B1") (pintype "passive+no_connect"))
    )
    (net (code "596") (name "unconnected-(U8D-IO_L60P_3-PadB2)") (class "Default")
      (node (ref "U8") (pin "B2") (pinfunction "IO_L60P_3_B2") (pintype "passive+no_connect"))
    )
    (net (code "597") (name "unconnected-(U8D-IO_L80N_3-PadF7)") (class "Default")
      (node (ref "U8") (pin "F7") (pinfunction "IO_L80N_3_F7") (pintype "passive+no_connect"))
    )
    (net (code "598") (name "unconnected-(U8D-IO_L80P_3-PadG7)") (class "Default")
      (node (ref "U8") (pin "G7") (pinfunction "IO_L80P_3_G7") (pintype "passive+no_connect"))
    )
    (net (code "599") (name "unconnected-(U8D-IO_L81N_3-PadC4)") (class "Default")
      (node (ref "U8") (pin "C4") (pinfunction "IO_L81N_3_C4") (pintype "passive+no_connect"))
    )
    (net (code "600") (name "unconnected-(U8D-IO_L81P_3-PadD3)") (class "Default")
      (node (ref "U8") (pin "D3") (pinfunction "IO_L81P_3_D3") (pintype "passive+no_connect"))
    )
    (net (code "601") (name "unconnected-(U8D-IO_L82N_3-PadE6)") (class "Default")
      (node (ref "U8") (pin "E6") (pinfunction "IO_L82N_3_E6") (pintype "passive+no_connect"))
    )
    (net (code "602") (name "unconnected-(U8D-IO_L82P_3-PadE5)") (class "Default")
      (node (ref "U8") (pin "E5") (pinfunction "IO_L82P_3_E5") (pintype "passive+no_connect"))
    )
    (net (code "603") (name "unconnected-(U8D-IO_L83P_3-PadA2)") (class "Default")
      (node (ref "U8") (pin "A2") (pinfunction "IO_L83P_3_A2") (pintype "passive+no_connect"))
    )
    (net (code "604") (name "unconnected-(U8E-CMPCS_B_2-PadY20)") (class "Default")
      (node (ref "U8") (pin "Y20") (pinfunction "CMPCS_B_2_Y20") (pintype "passive+no_connect"))
    )
    (net (code "605") (name "unconnected-(U8H-NC-PadD12)") (class "Default")
      (node (ref "U8") (pin "D12") (pinfunction "NC_D12") (pintype "passive+no_connect"))
    )
    (net (code "606") (name "unconnected-(U8H-NC-PadD13)") (class "Default")
      (node (ref "U8") (pin "D13") (pinfunction "NC_D13") (pintype "passive+no_connect"))
    )
    (net (code "607") (name "unconnected-(U8H-NC-PadE8)") (class "Default")
      (node (ref "U8") (pin "E8") (pinfunction "NC_E8") (pintype "passive+no_connect"))
    )
    (net (code "608") (name "unconnected-(U8H-NC-PadE10)") (class "Default")
      (node (ref "U8") (pin "E10") (pinfunction "NC_E10") (pintype "passive+no_connect"))
    )
    (net (code "609") (name "unconnected-(U8H-NC-PadE12)") (class "Default")
      (node (ref "U8") (pin "E12") (pinfunction "NC_E12") (pintype "passive+no_connect"))
    )
    (net (code "610") (name "unconnected-(U8H-NC-PadE14)") (class "Default")
      (node (ref "U8") (pin "E14") (pinfunction "NC_E14") (pintype "passive+no_connect"))
    )
    (net (code "611") (name "unconnected-(U8H-NC-PadF8)") (class "Default")
      (node (ref "U8") (pin "F8") (pinfunction "NC_F8") (pintype "passive+no_connect"))
    )
    (net (code "612") (name "unconnected-(U8H-NC-PadF9)") (class "Default")
      (node (ref "U8") (pin "F9") (pinfunction "NC_F9") (pintype "passive+no_connect"))
    )
    (net (code "613") (name "unconnected-(U8H-NC-PadF10)") (class "Default")
      (node (ref "U8") (pin "F10") (pinfunction "NC_F10") (pintype "passive+no_connect"))
    )
    (net (code "614") (name "unconnected-(U8H-NC-PadF12)") (class "Default")
      (node (ref "U8") (pin "F12") (pinfunction "NC_F12") (pintype "passive+no_connect"))
    )
    (net (code "615") (name "unconnected-(U8H-NC-PadF13)") (class "Default")
      (node (ref "U8") (pin "F13") (pinfunction "NC_F13") (pintype "passive+no_connect"))
    )
    (net (code "616") (name "unconnected-(U8H-NC-PadF14)") (class "Default")
      (node (ref "U8") (pin "F14") (pinfunction "NC_F14") (pintype "passive+no_connect"))
    )
    (net (code "617") (name "unconnected-(U8H-NC-PadF15)") (class "Default")
      (node (ref "U8") (pin "F15") (pinfunction "NC_F15") (pintype "passive+no_connect"))
    )
    (net (code "618") (name "unconnected-(U8H-NC-PadG8)") (class "Default")
      (node (ref "U8") (pin "G8") (pinfunction "NC_G8") (pintype "passive+no_connect"))
    )
    (net (code "619") (name "unconnected-(U8H-NC-PadG9)") (class "Default")
      (node (ref "U8") (pin "G9") (pinfunction "NC_G9") (pintype "passive+no_connect"))
    )
    (net (code "620") (name "unconnected-(U8H-NC-PadG11)") (class "Default")
      (node (ref "U8") (pin "G11") (pinfunction "NC_G11") (pintype "passive+no_connect"))
    )
    (net (code "621") (name "unconnected-(U8H-NC-PadG13)") (class "Default")
      (node (ref "U8") (pin "G13") (pinfunction "NC_G13") (pintype "passive+no_connect"))
    )
    (net (code "622") (name "unconnected-(U8H-NC-PadH10)") (class "Default")
      (node (ref "U8") (pin "H10") (pinfunction "NC_H10") (pintype "passive+no_connect"))
    )
    (net (code "623") (name "unconnected-(U8H-NC-PadH11)") (class "Default")
      (node (ref "U8") (pin "H11") (pinfunction "NC_H11") (pintype "passive+no_connect"))
    )
    (net (code "624") (name "unconnected-(U8H-NC-PadH12)") (class "Default")
      (node (ref "U8") (pin "H12") (pinfunction "NC_H12") (pintype "passive+no_connect"))
    )
    (net (code "625") (name "unconnected-(U8H-NC-PadH13)") (class "Default")
      (node (ref "U8") (pin "H13") (pinfunction "NC_H13") (pintype "passive+no_connect"))
    )
    (net (code "626") (name "unconnected-(U8H-NC-PadH14)") (class "Default")
      (node (ref "U8") (pin "H14") (pinfunction "NC_H14") (pintype "passive+no_connect"))
    )
    (net (code "627") (name "unconnected-(U8H-NC-PadP15)") (class "Default")
      (node (ref "U8") (pin "P15") (pinfunction "NC_P15") (pintype "passive+no_connect"))
    )
    (net (code "628") (name "unconnected-(U8H-NC-PadP16)") (class "Default")
      (node (ref "U8") (pin "P16") (pinfunction "NC_P16") (pintype "passive+no_connect"))
    )
    (net (code "629") (name "unconnected-(U8H-NC-PadR17)") (class "Default")
      (node (ref "U8") (pin "R17") (pinfunction "NC_R17") (pintype "passive+no_connect"))
    )
    (net (code "630") (name "unconnected-(U12-NC-PadJ1)") (class "Default")
      (node (ref "U12") (pin "J1") (pinfunction "NC_J1") (pintype "passive+no_connect"))
    )
    (net (code "631") (name "unconnected-(U12-NC-PadJ9)") (class "Default")
      (node (ref "U12") (pin "J9") (pinfunction "NC_J9") (pintype "passive+no_connect"))
    )
    (net (code "632") (name "unconnected-(U12-NC-PadL1)") (class "Default")
      (node (ref "U12") (pin "L1") (pinfunction "NC_L1") (pintype "passive+no_connect"))
    )
    (net (code "633") (name "unconnected-(U12-NC-PadL9)") (class "Default")
      (node (ref "U12") (pin "L9") (pinfunction "NC_L9") (pintype "passive+no_connect"))
    )
    (net (code "634") (name "unconnected-(U12-NC-PadM7)") (class "Default")
      (node (ref "U12") (pin "M7") (pinfunction "NC_M7") (pintype "passive+no_connect"))
    )
    (net (code "635") (name "unconnected-(U13-NC-Pad3)") (class "Default")
      (node (ref "U13") (pin "3") (pinfunction "NC_3") (pintype "passive+no_connect"))
    )
    (net (code "636") (name "unconnected-(U100-NC-Pad1)") (class "Default")
      (node (ref "U100") (pin "1") (pinfunction "NC_1") (pintype "passive+no_connect"))
    )
    (net (code "637") (name "unconnected-(USB2-CEC-Pad13)") (class "Default")
      (node (ref "USB2") (pin "13") (pinfunction "CEC_13") (pintype "passive+no_connect"))
    )
    (net (code "638") (name "unconnected-(USB2-Reserved(N.C.)-Pad14)") (class "Default")
      (node (ref "USB2") (pin "14") (pinfunction "Reserved(N.C.)_14") (pintype "passive+no_connect"))
    )
    (net (code "639") (name "unconnected-(USB3-CEC-Pad13)") (class "Default")
      (node (ref "USB3") (pin "13") (pinfunction "CEC_13") (pintype "passive+no_connect"))
    )
    (net (code "640") (name "unconnected-(USB3-Reserved(N.C.)-Pad14)") (class "Default")
      (node (ref "USB3") (pin "14") (pinfunction "Reserved(N.C.)_14") (pintype "passive+no_connect"))
    )
  )
)
